# botball_v5.net
KiCad netlist of a schematic drawn in EAGLE
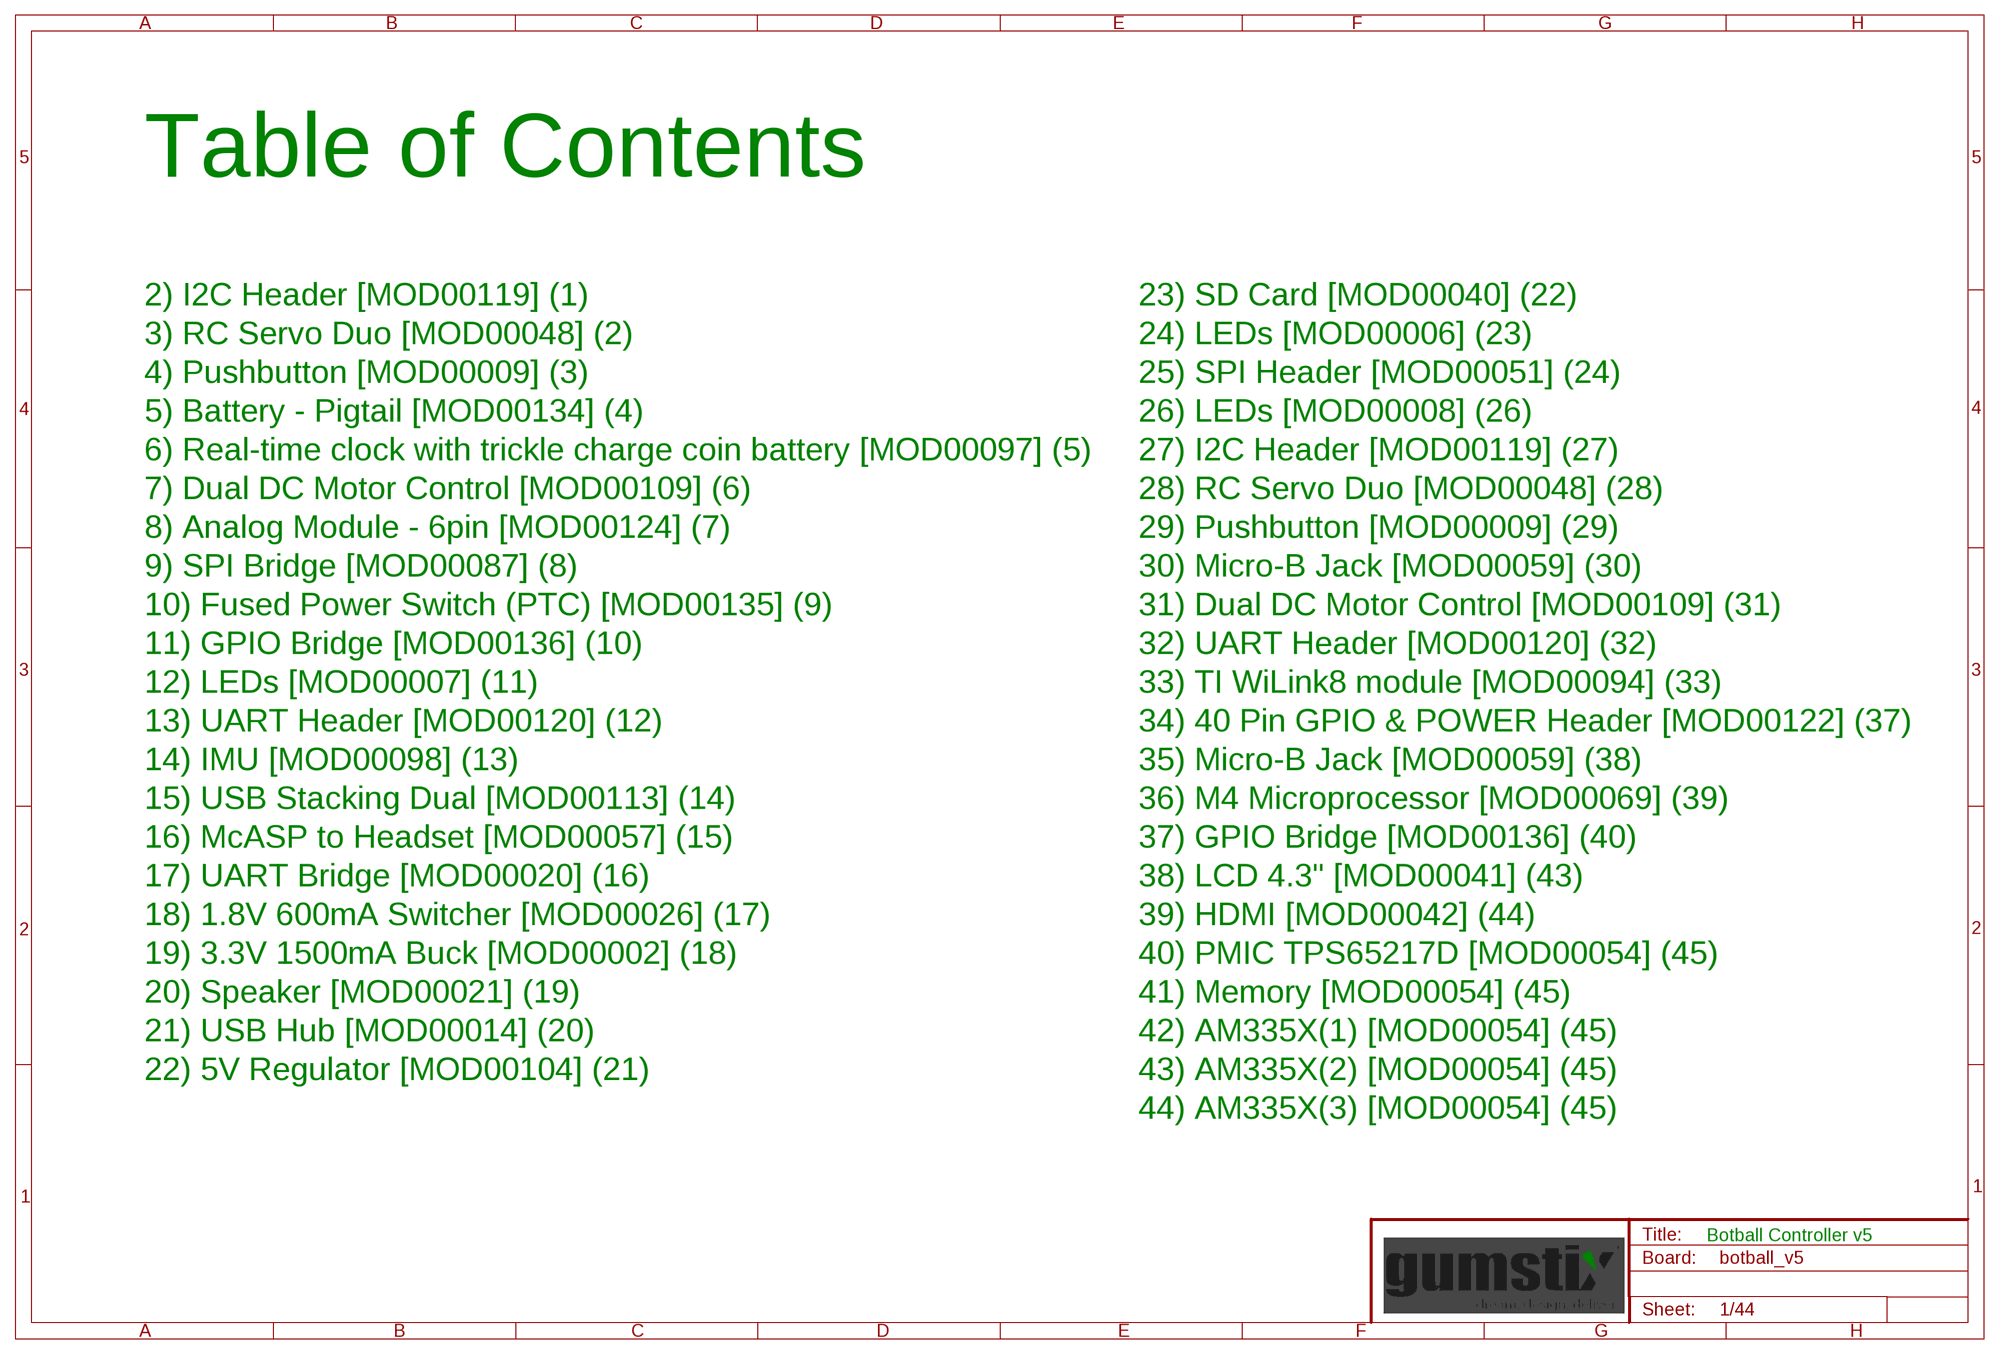
[diagram p0: schematic, sheet 1]
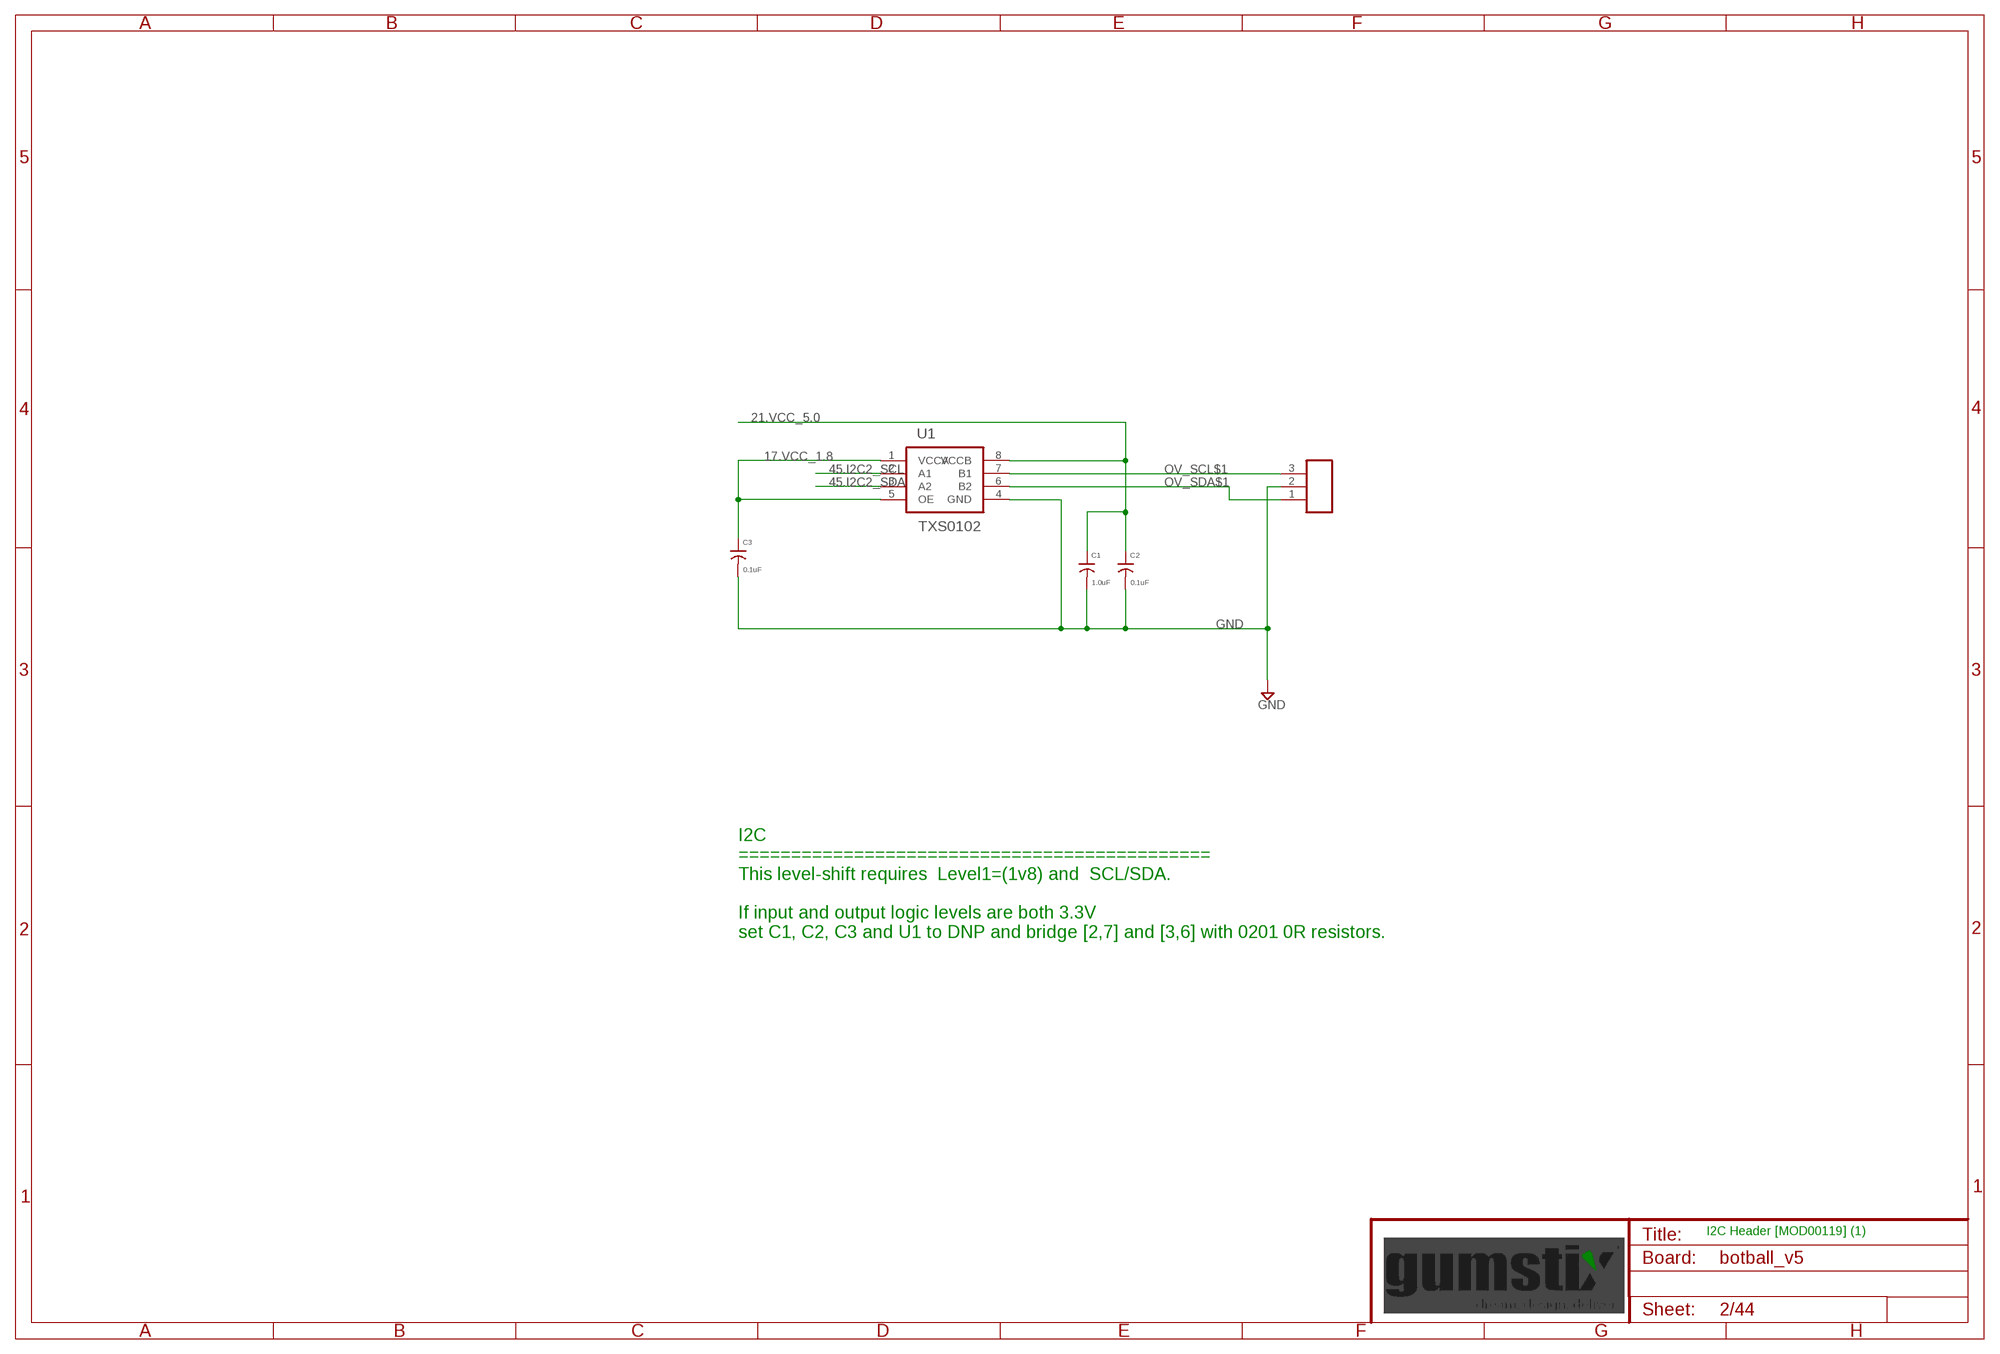
[diagram p1: schematic, sheet 2]
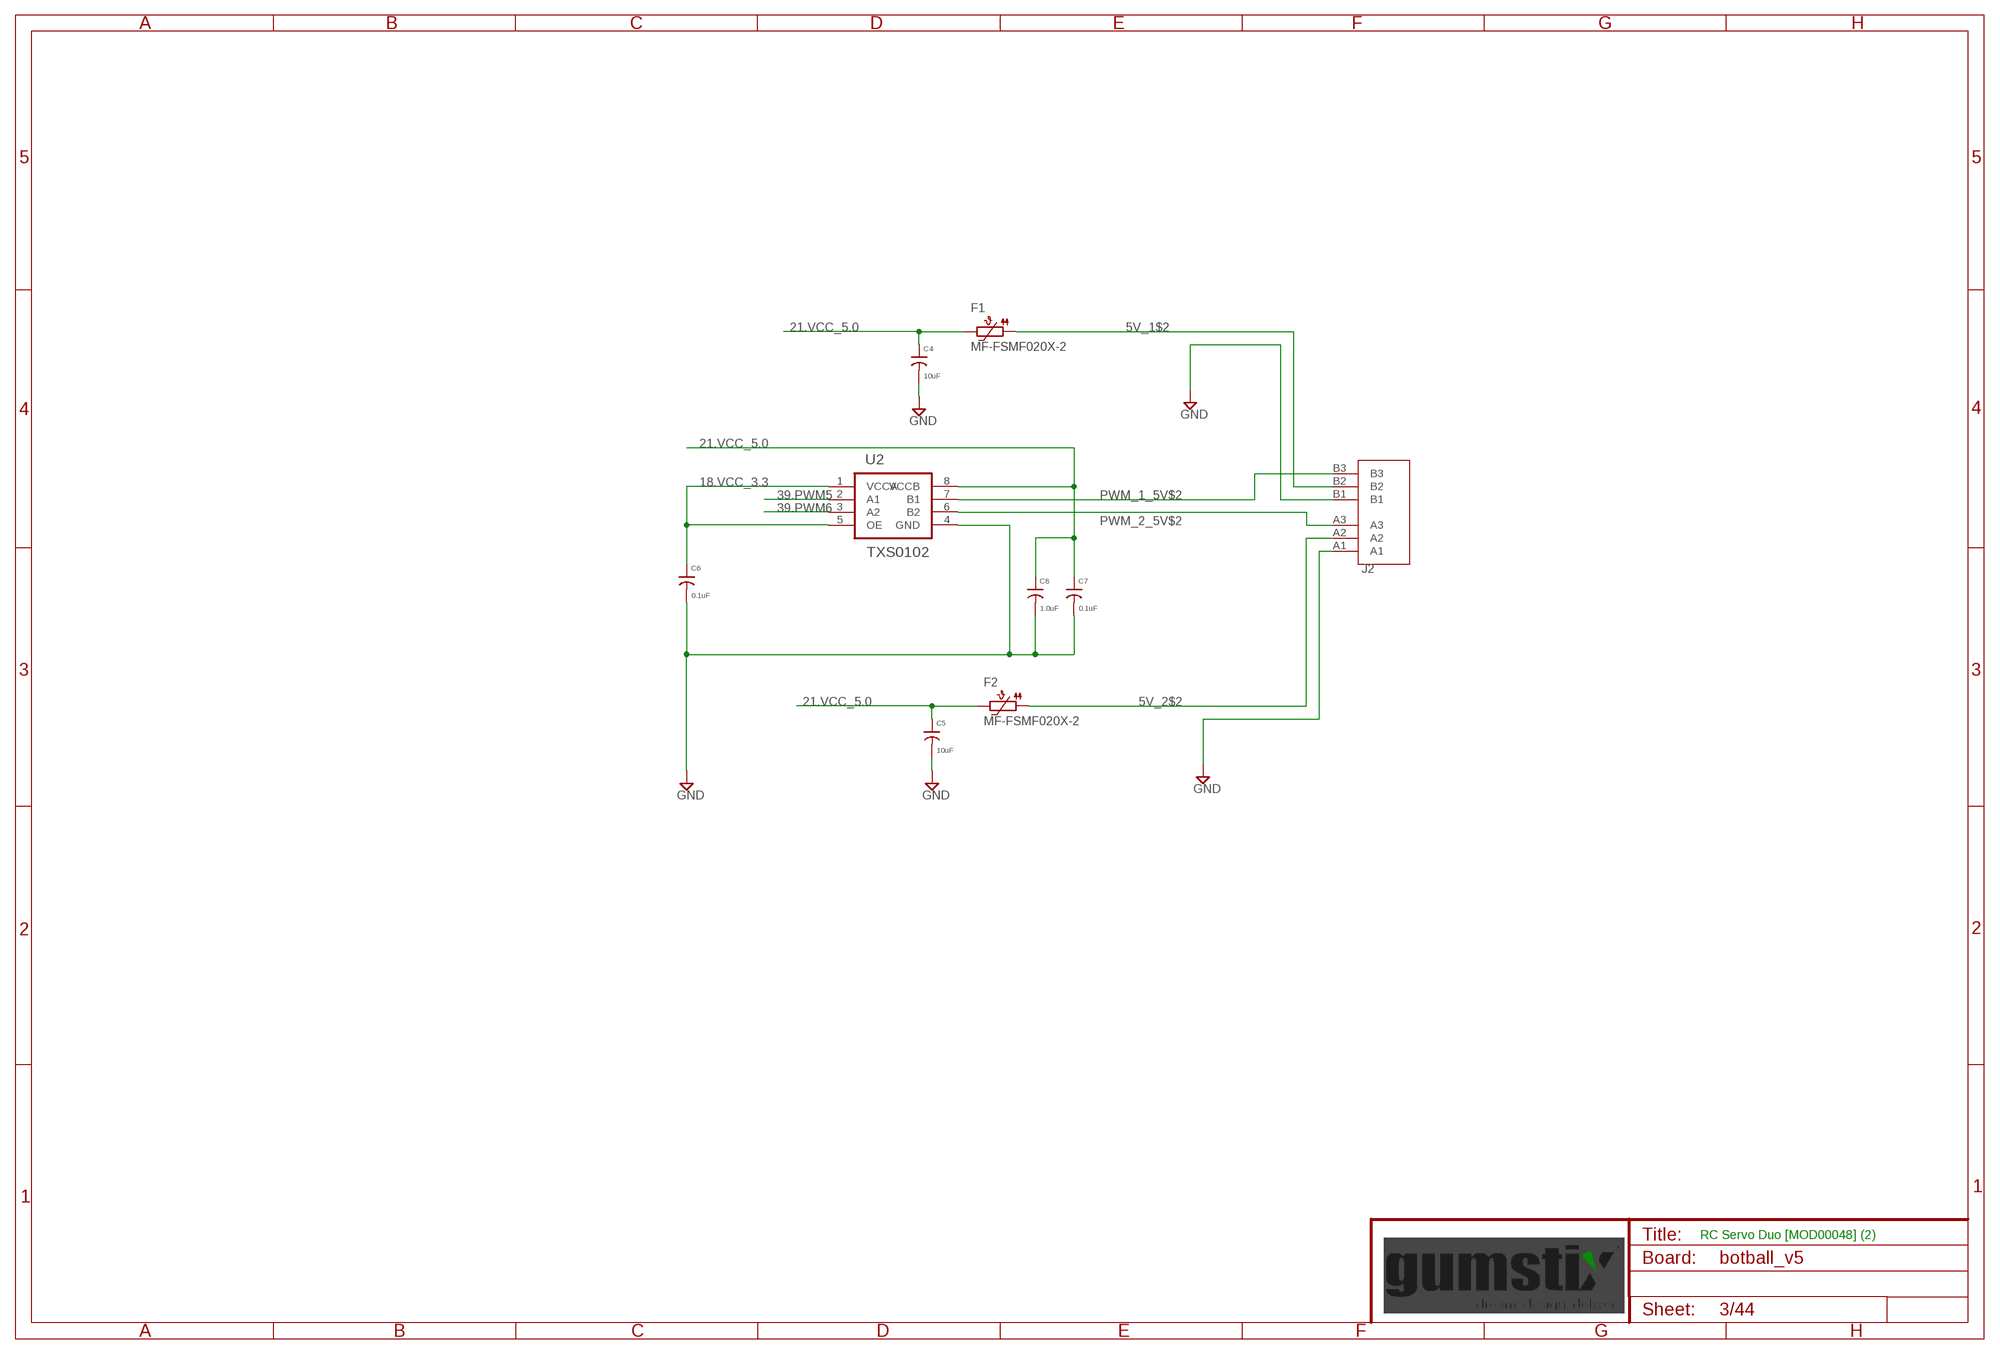
[diagram p2: schematic, sheet 3]
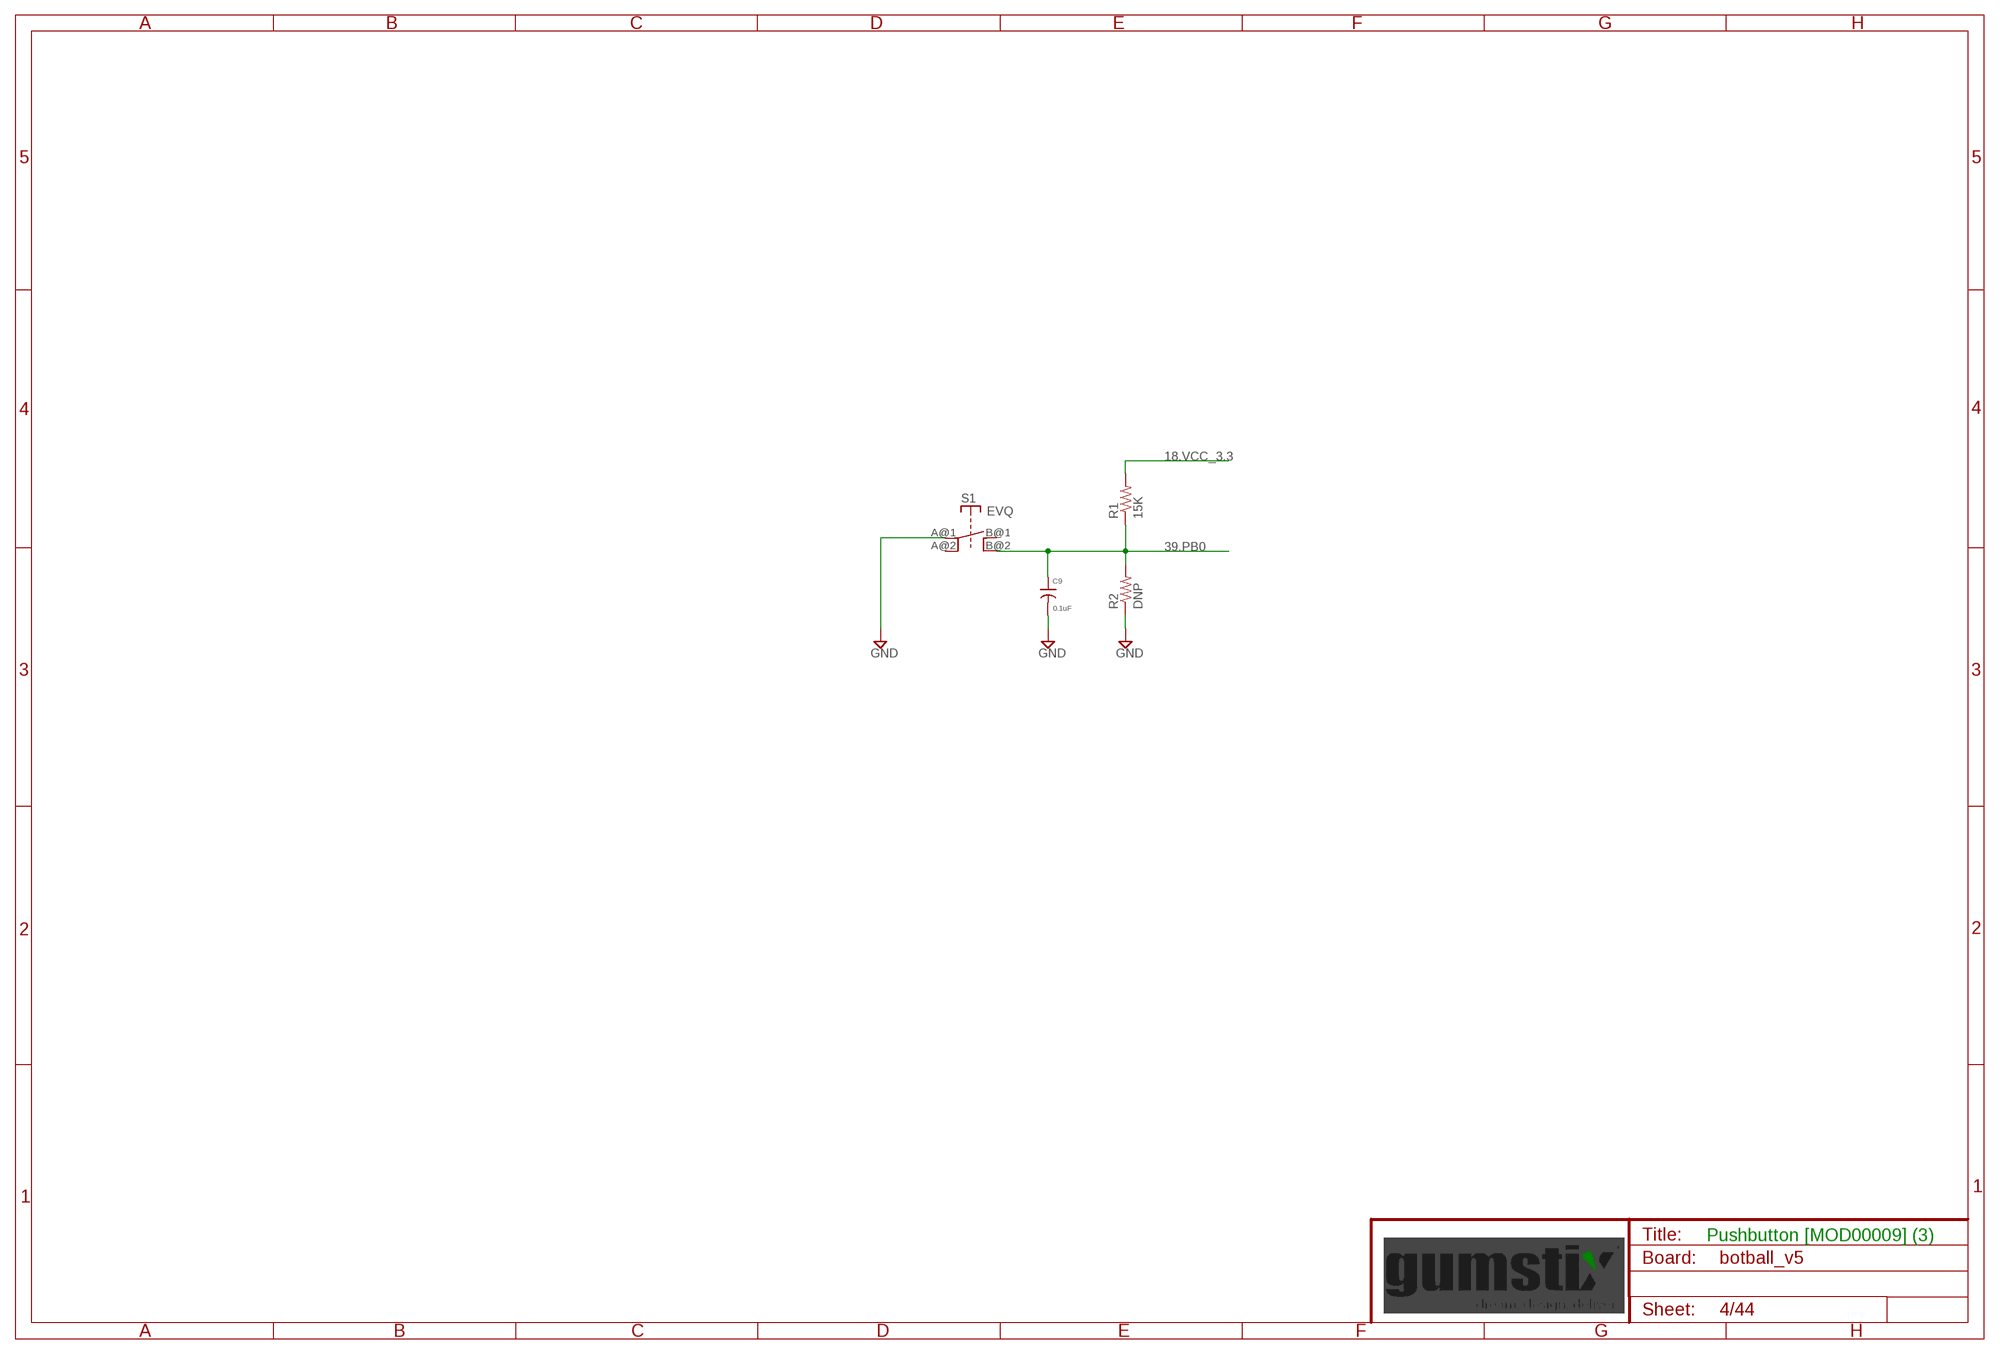
[diagram p3: schematic, sheet 4]
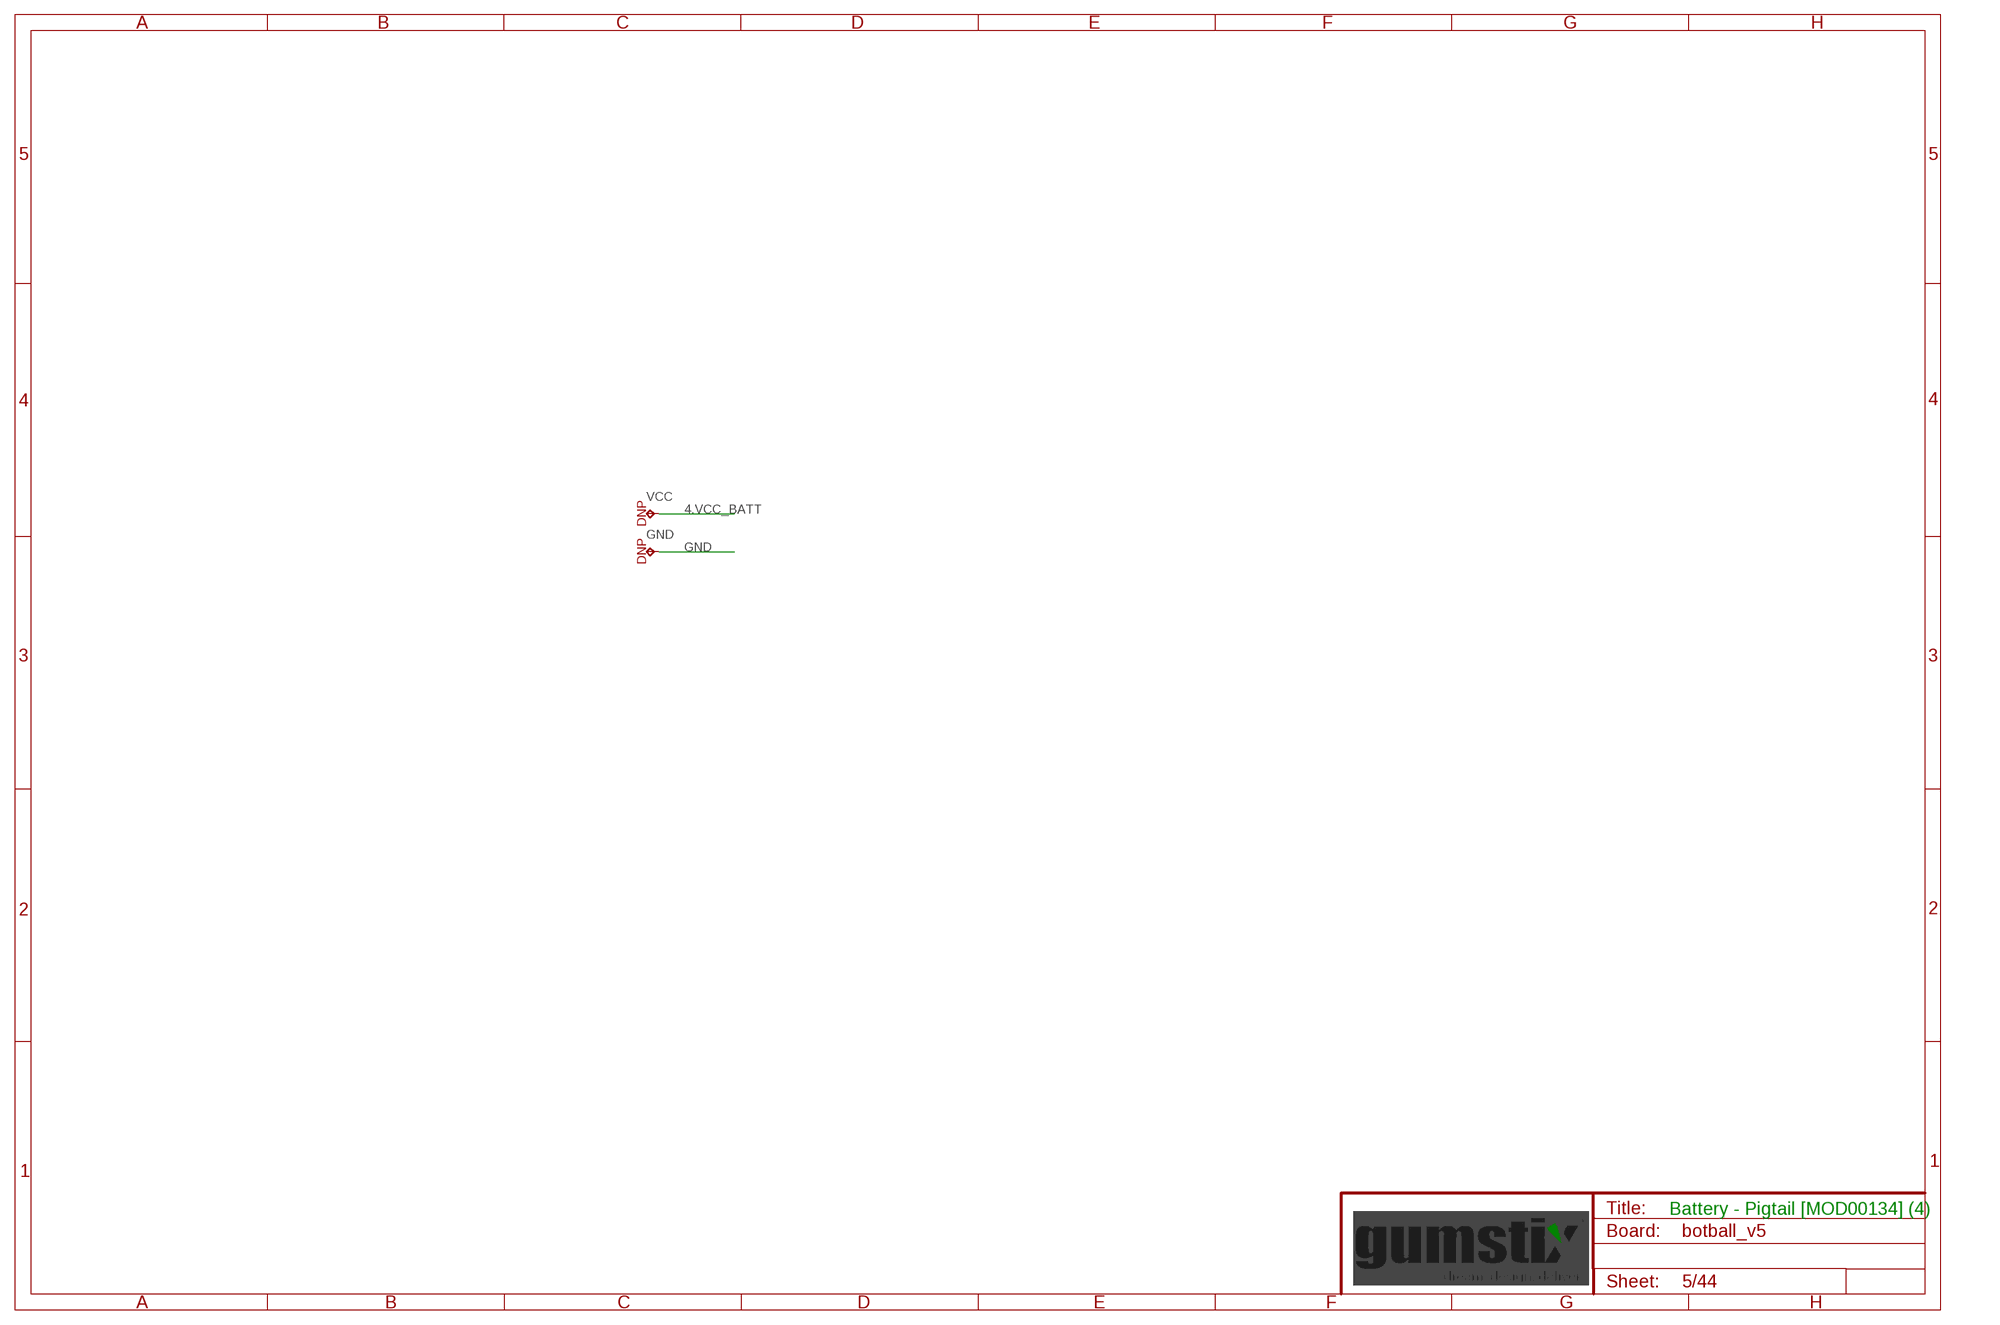
[diagram p4: schematic, sheet 5]
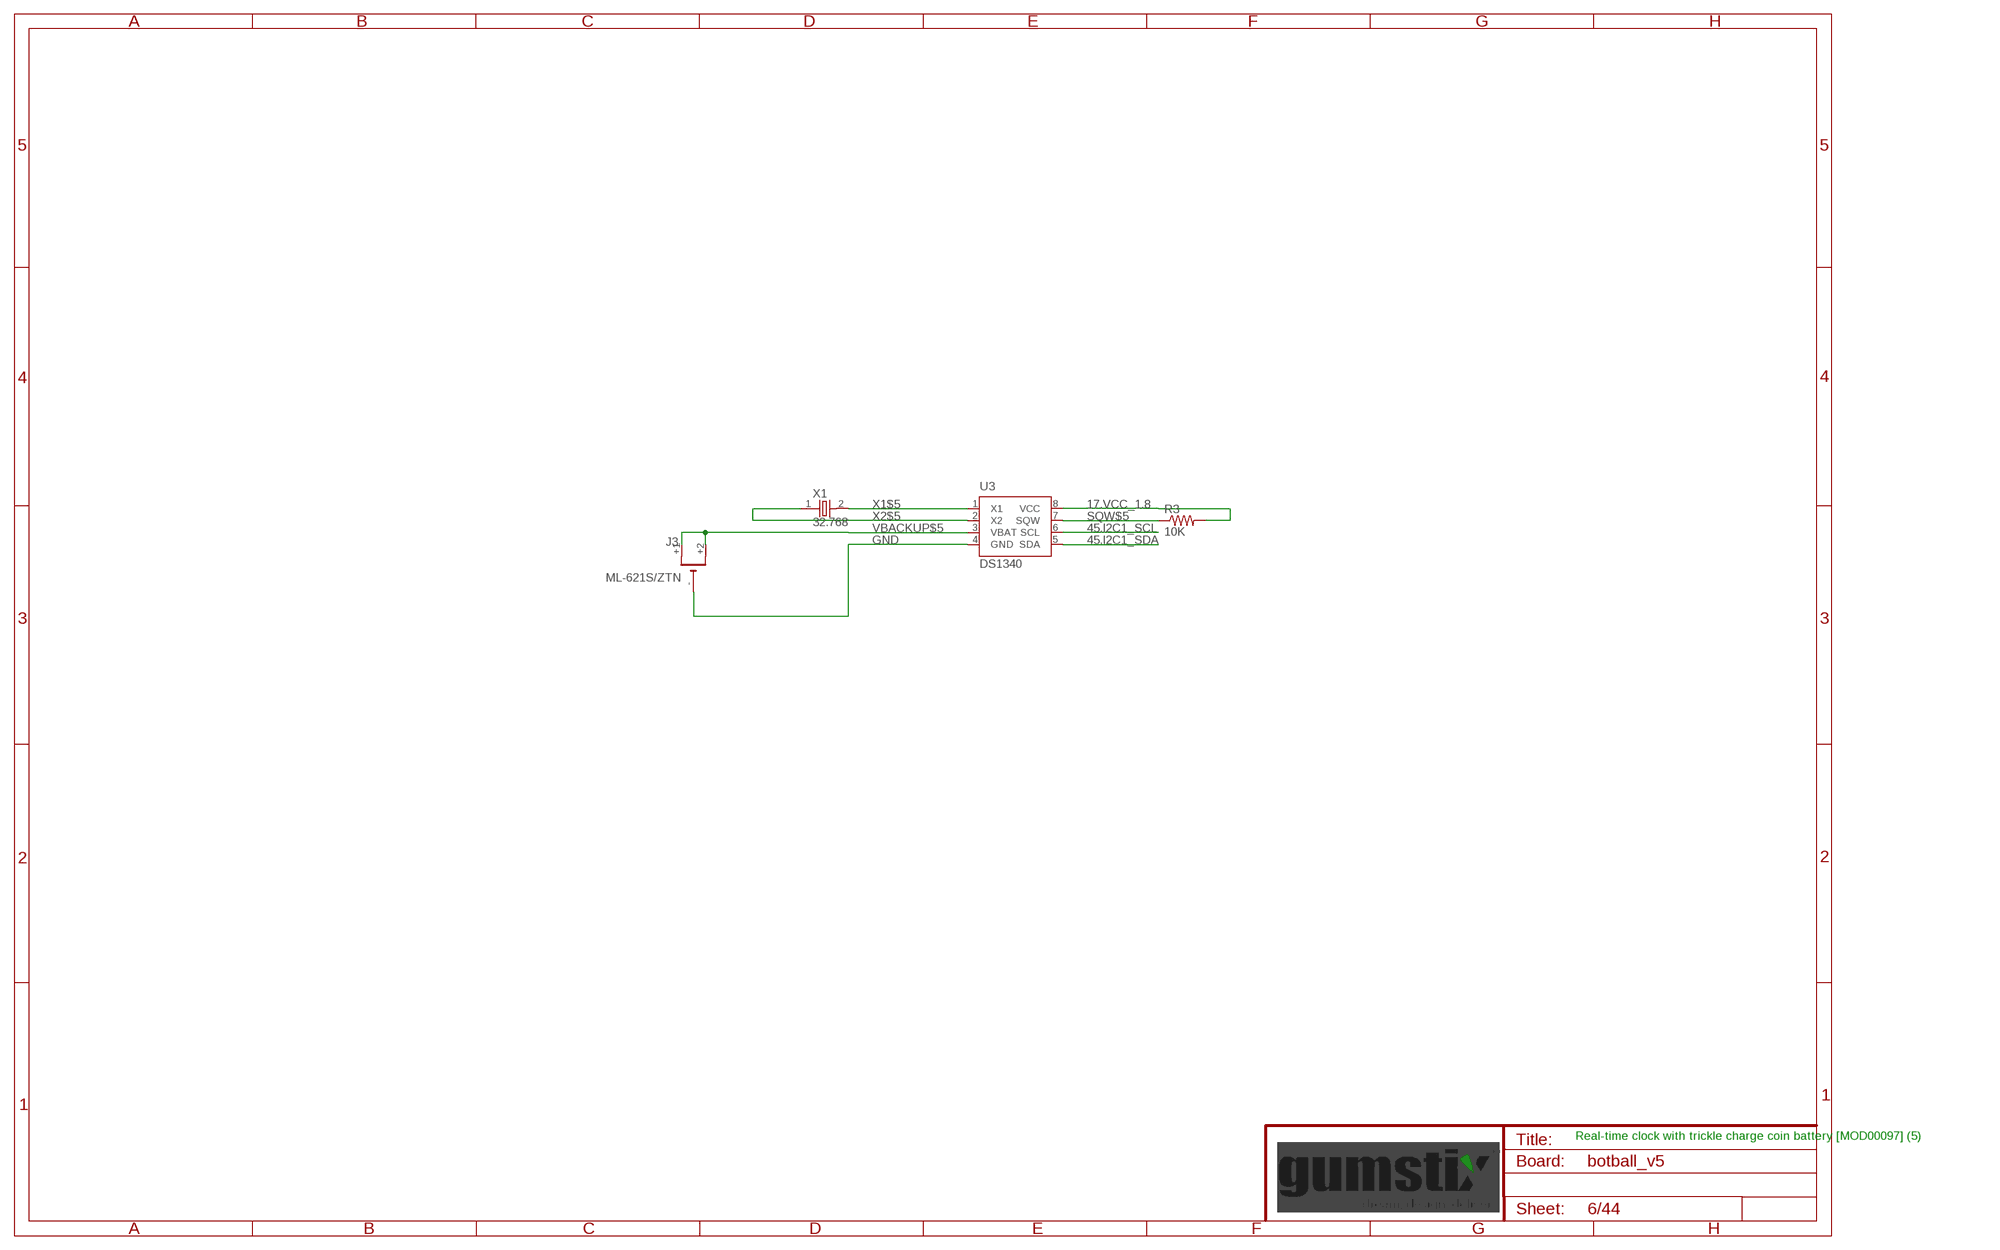
[diagram p5: schematic, sheet 6]
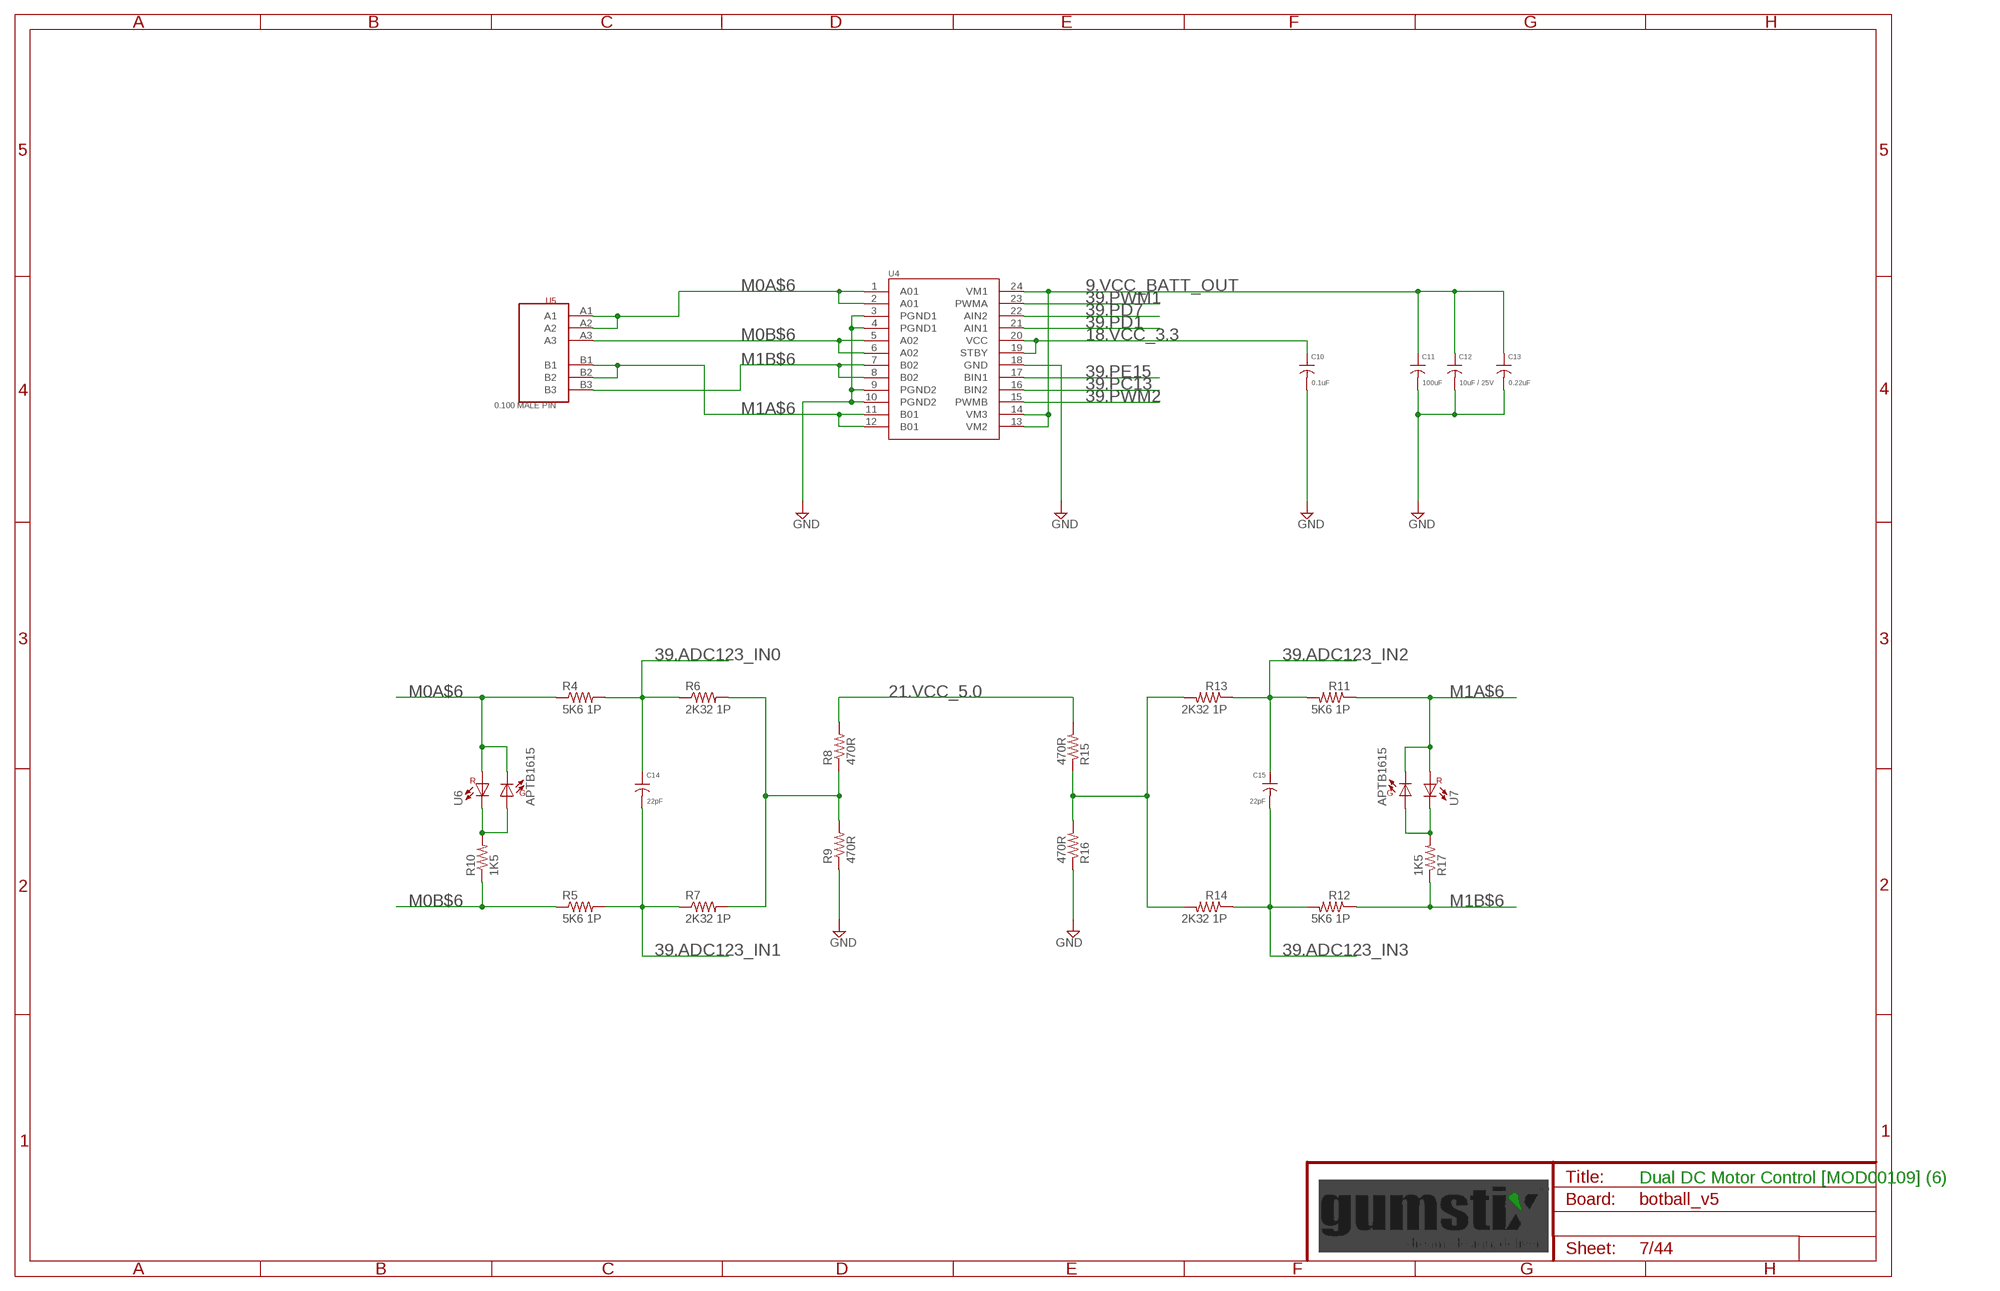
[diagram p6: schematic, sheet 7]
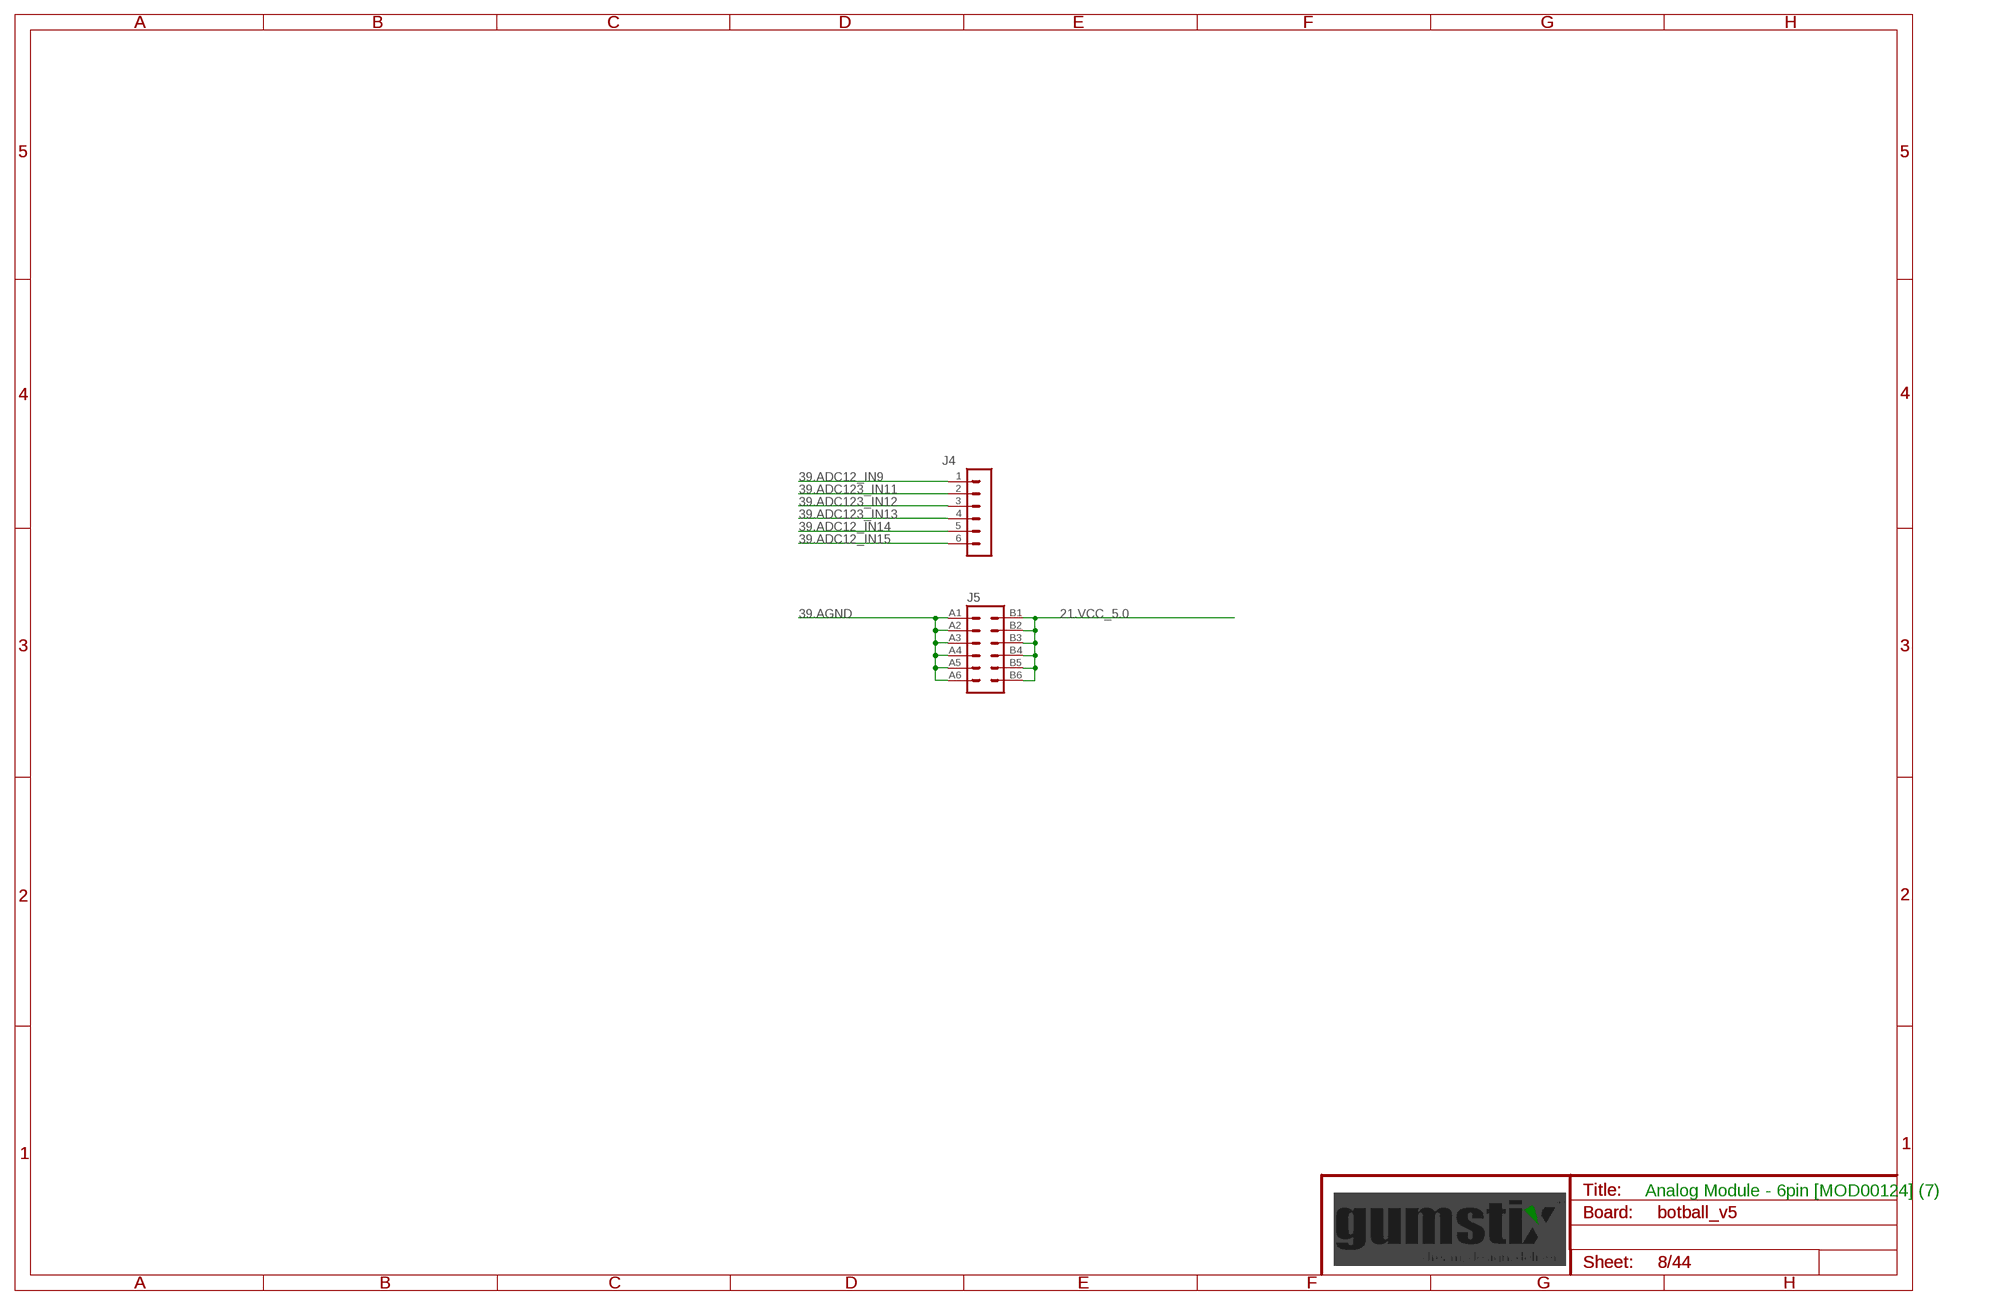
[diagram p7: schematic, sheet 8]
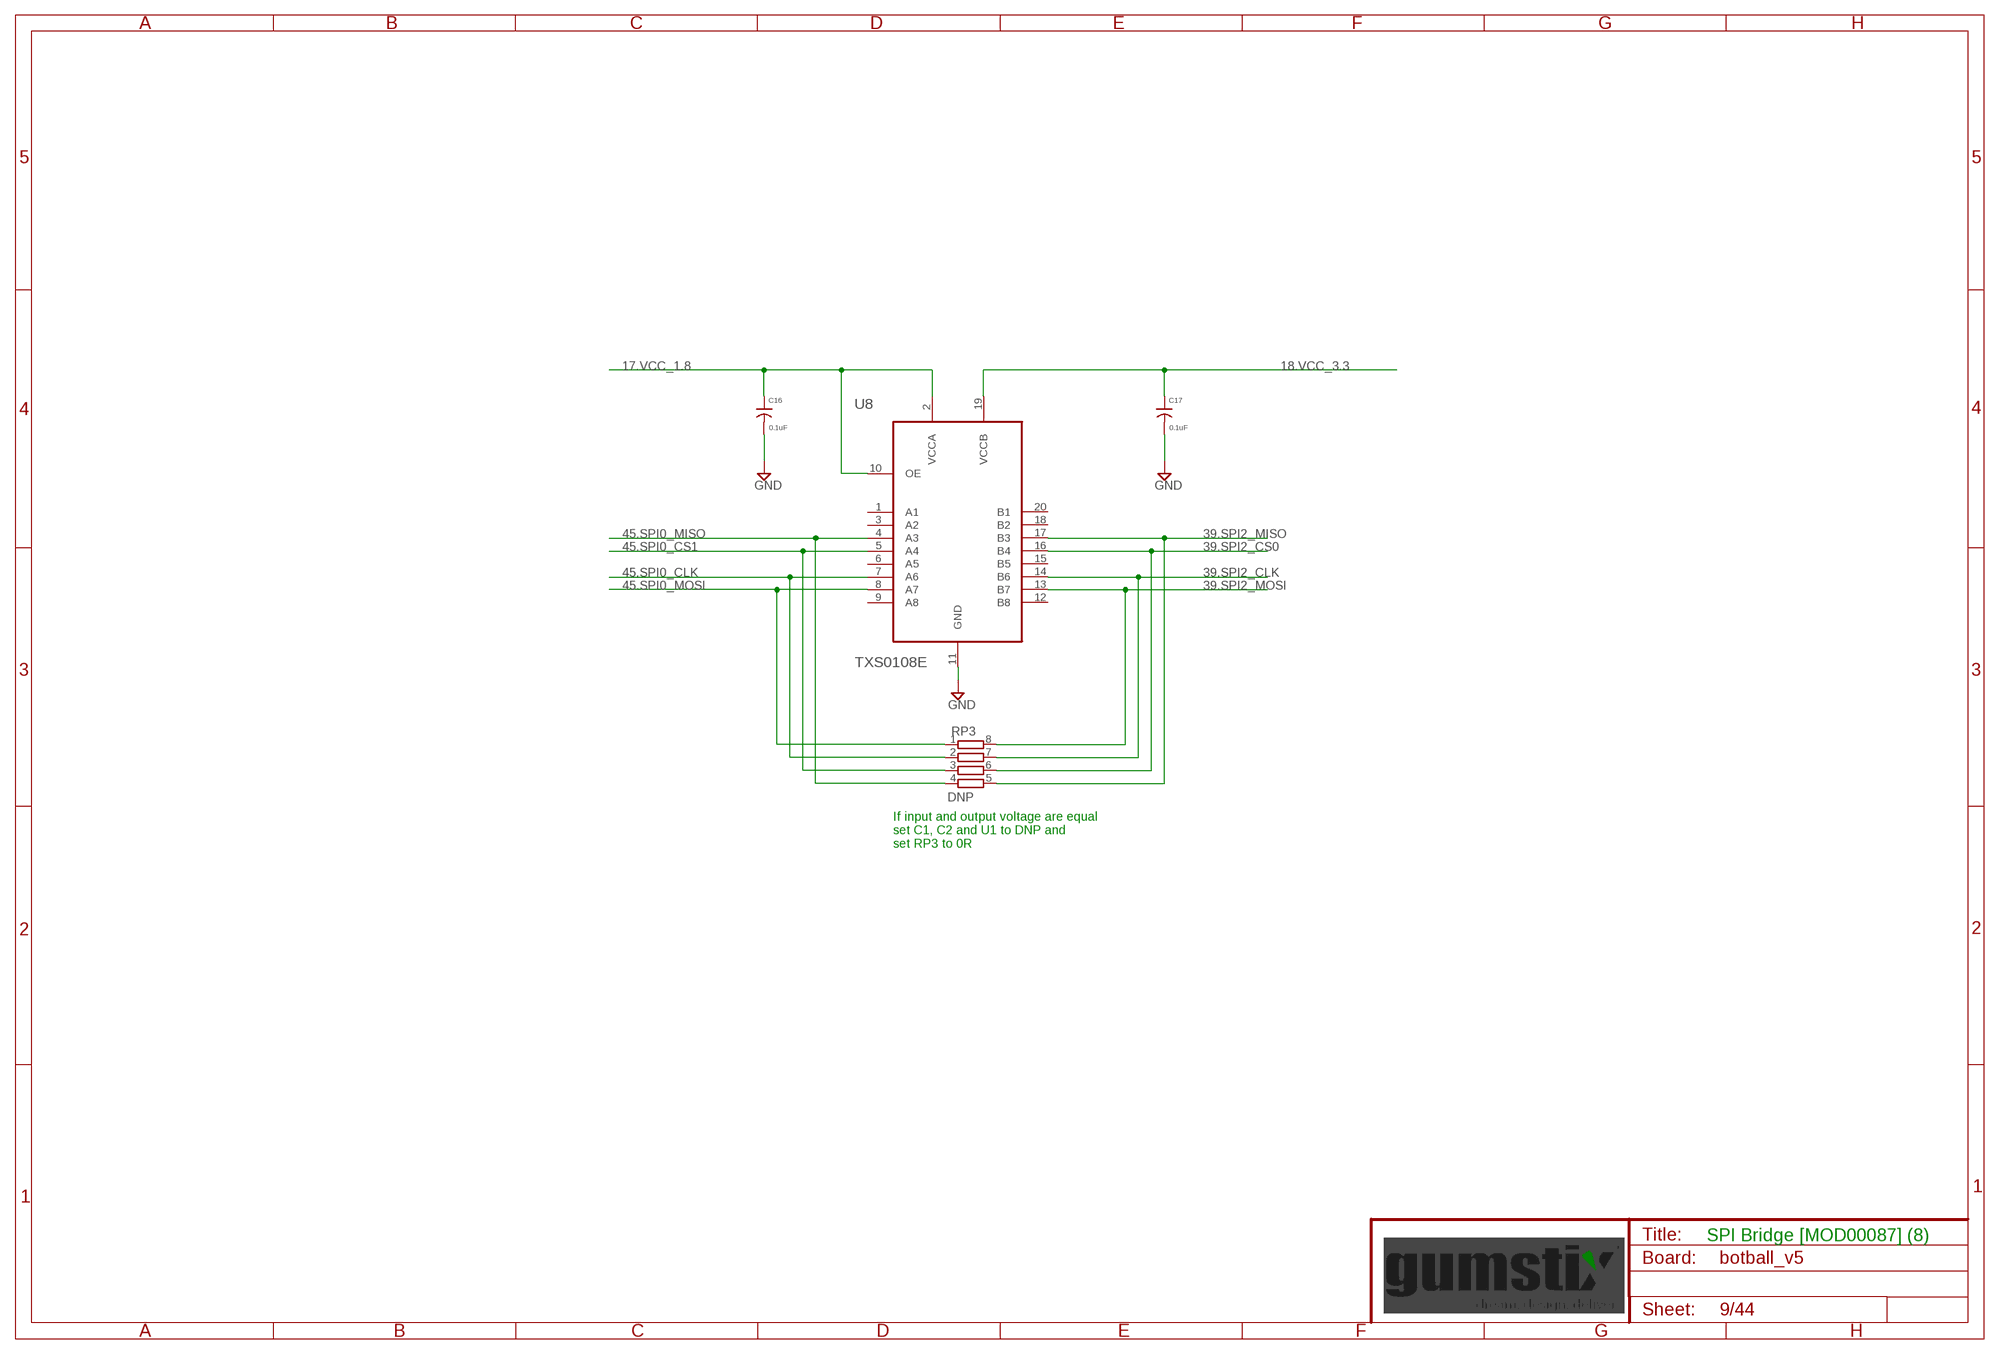
[diagram p8: schematic, sheet 9]
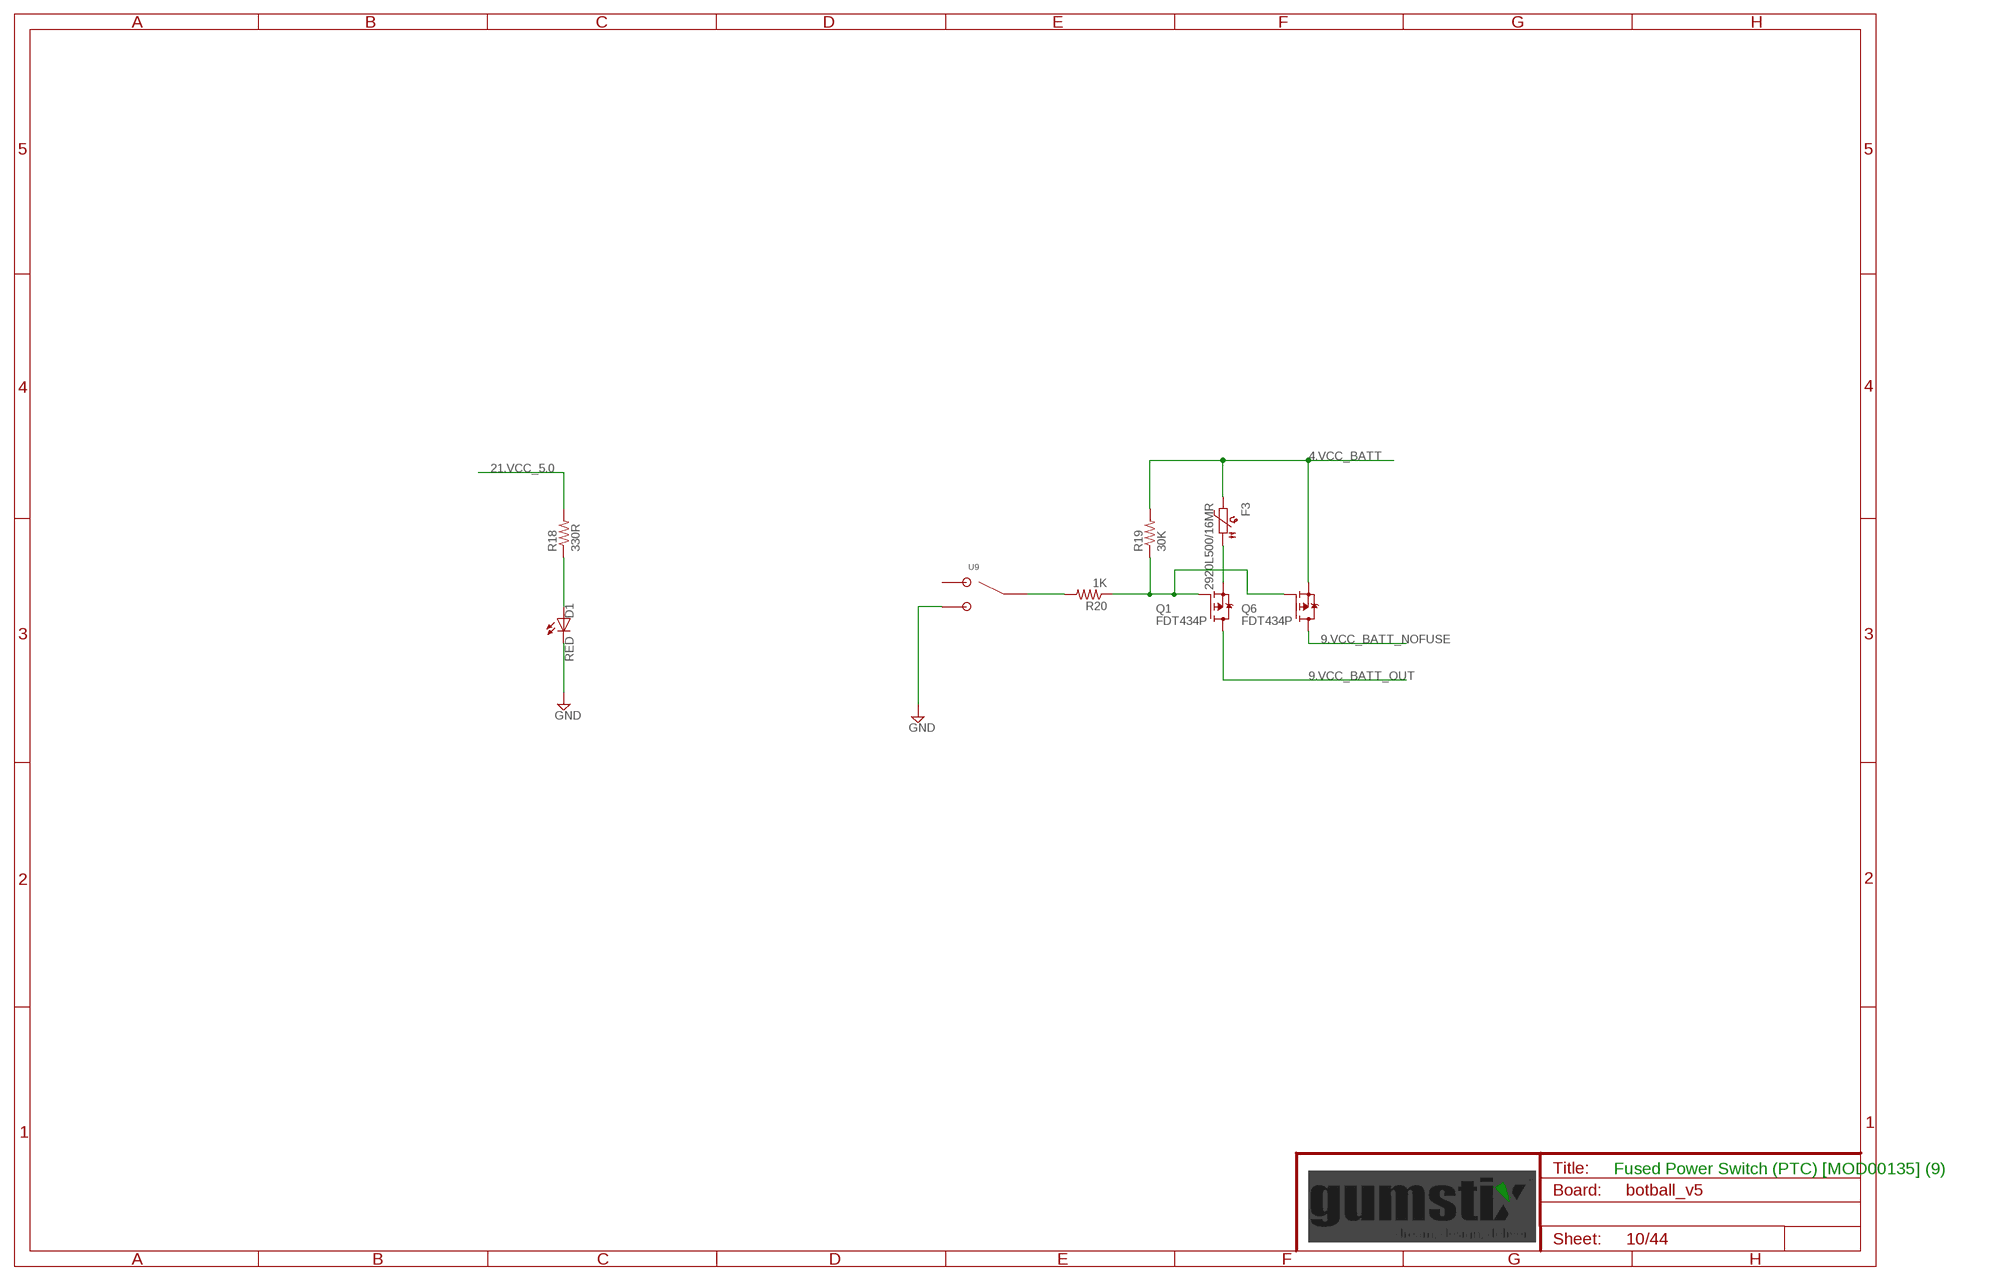
[diagram p9: schematic, sheet 10]
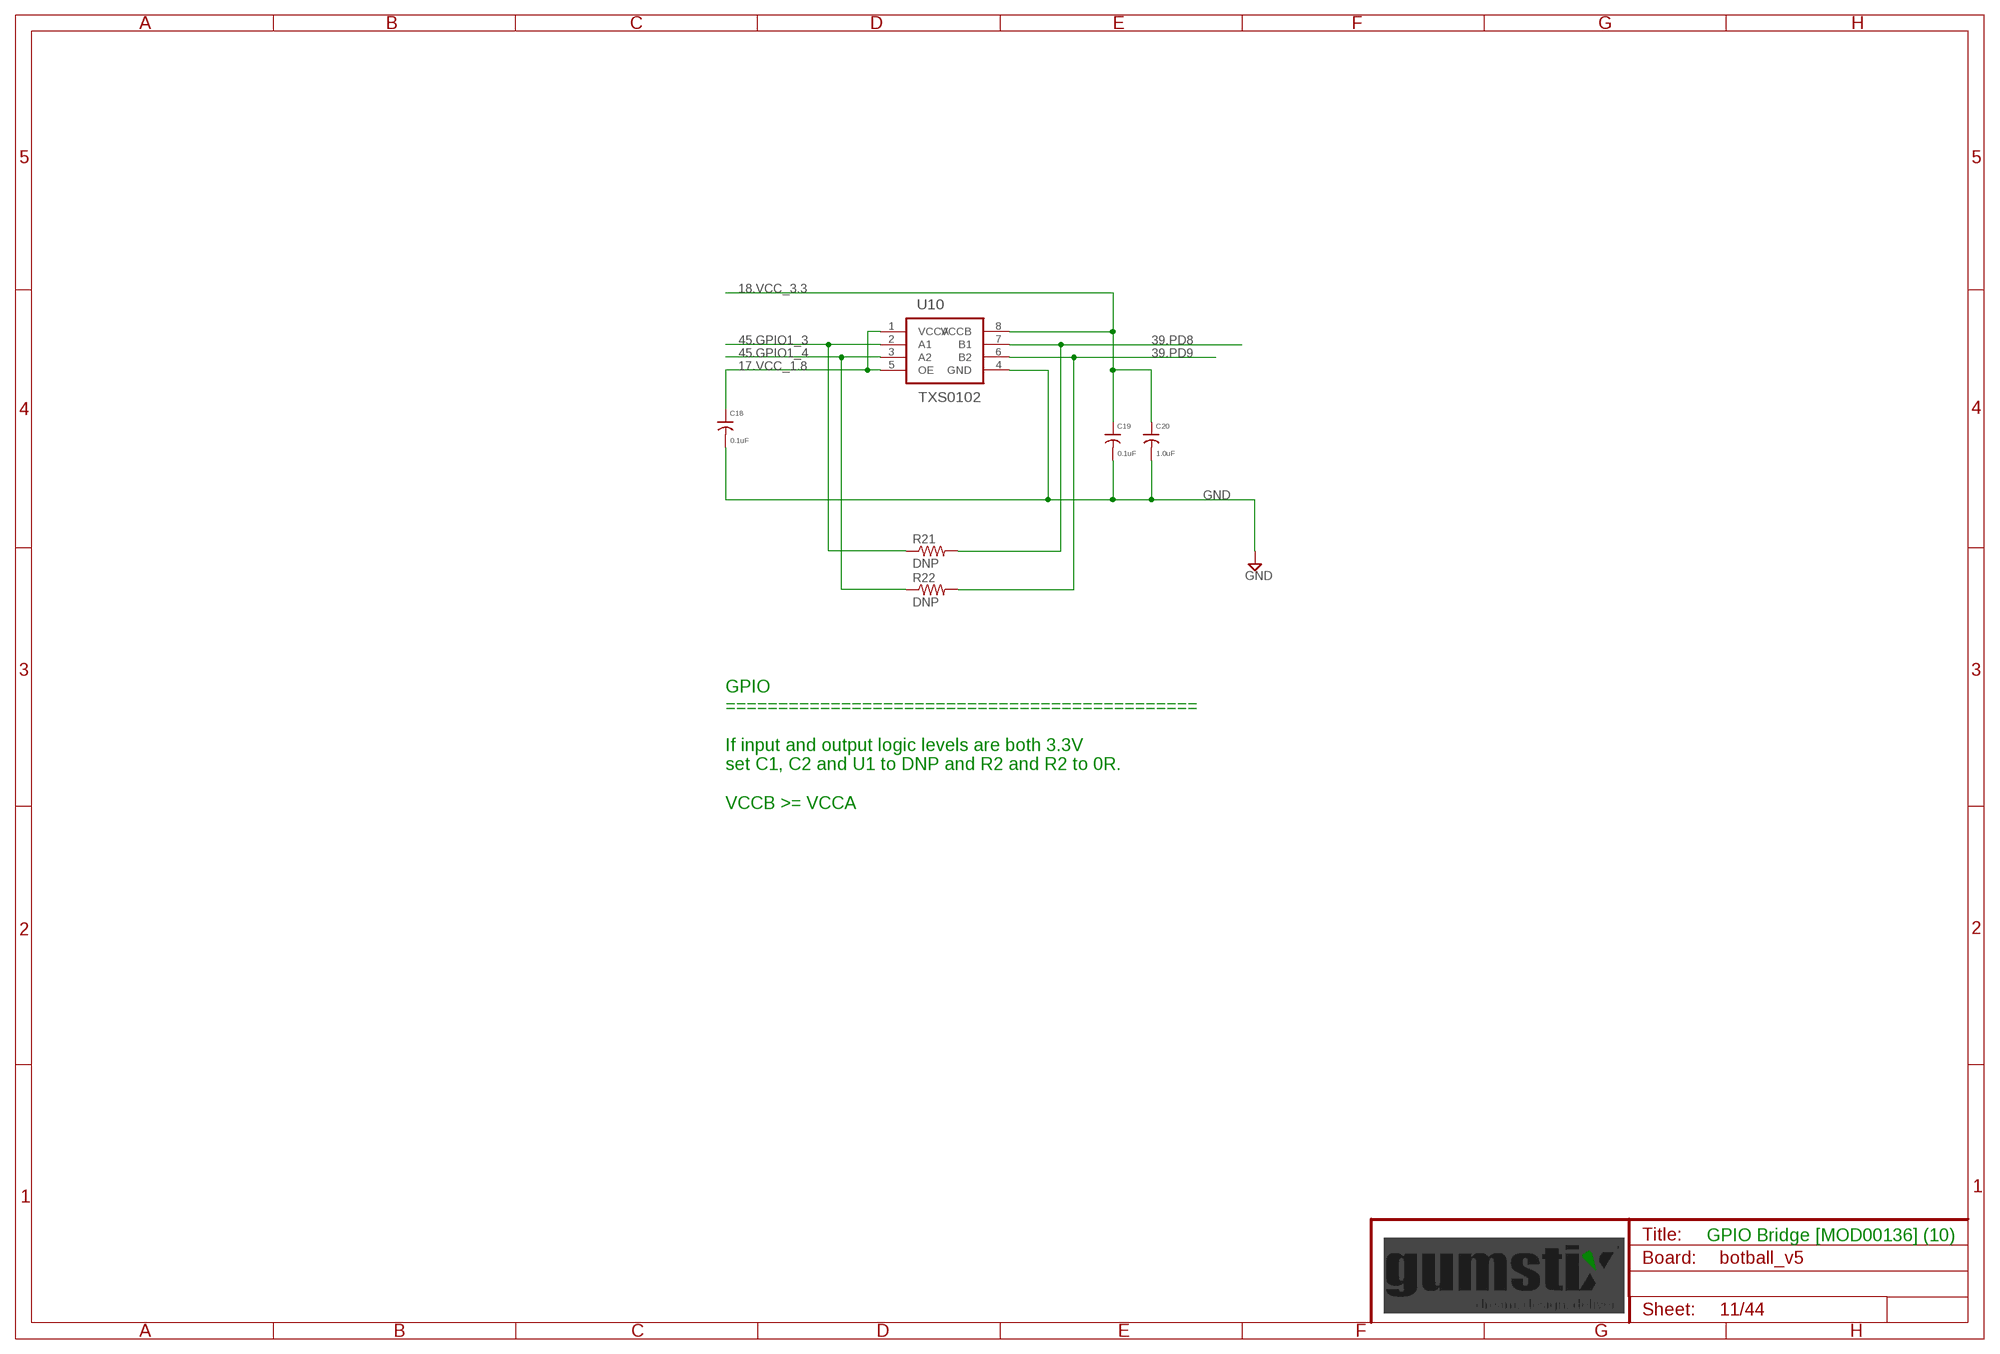
[diagram p10: schematic, sheet 11]
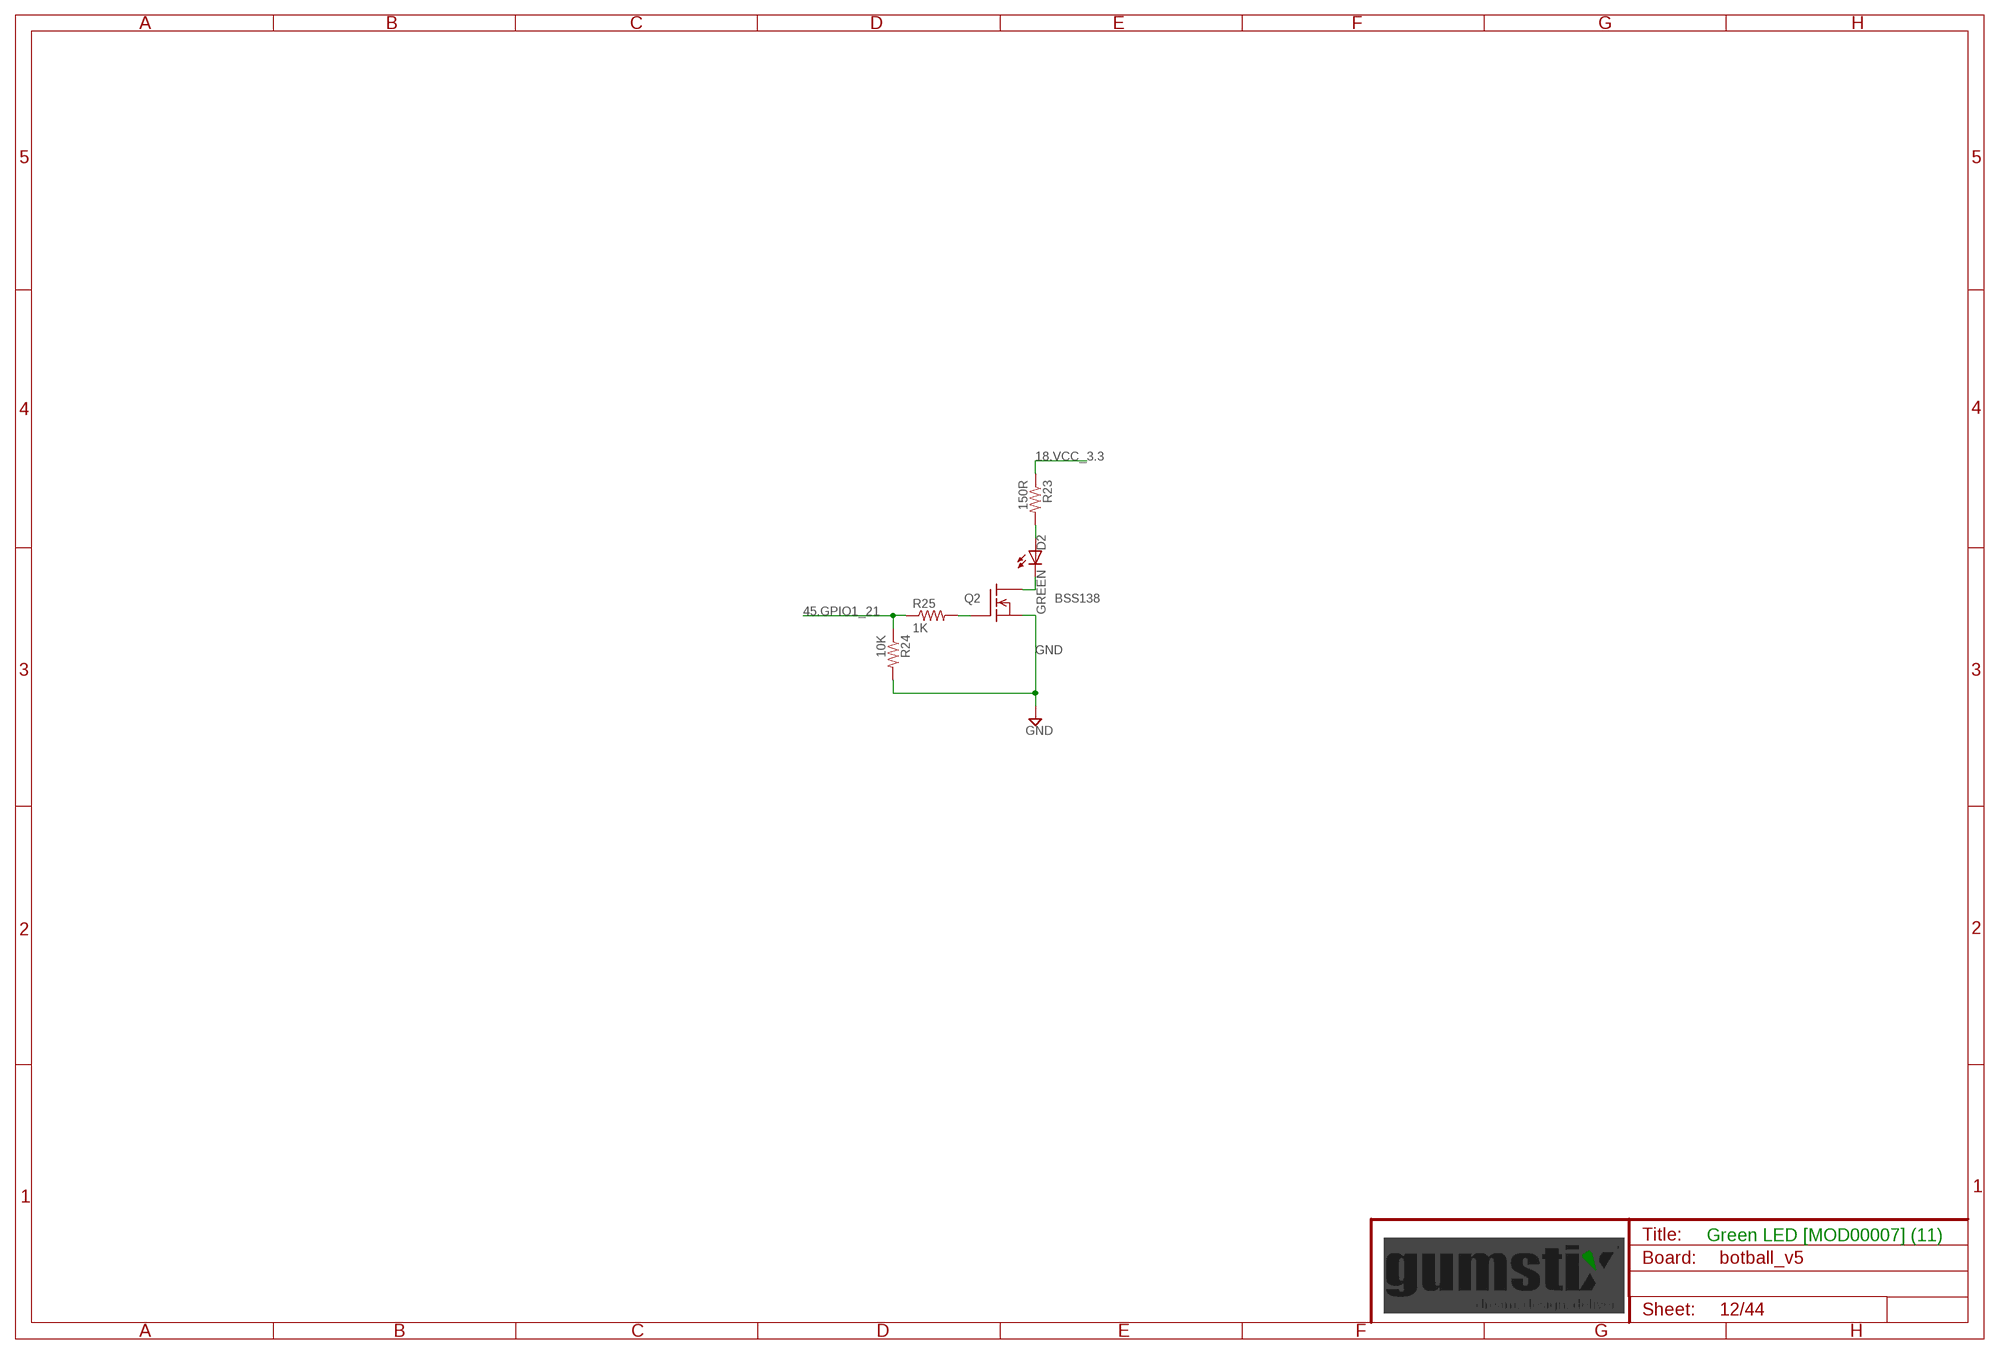
[diagram p11: schematic, sheet 12]
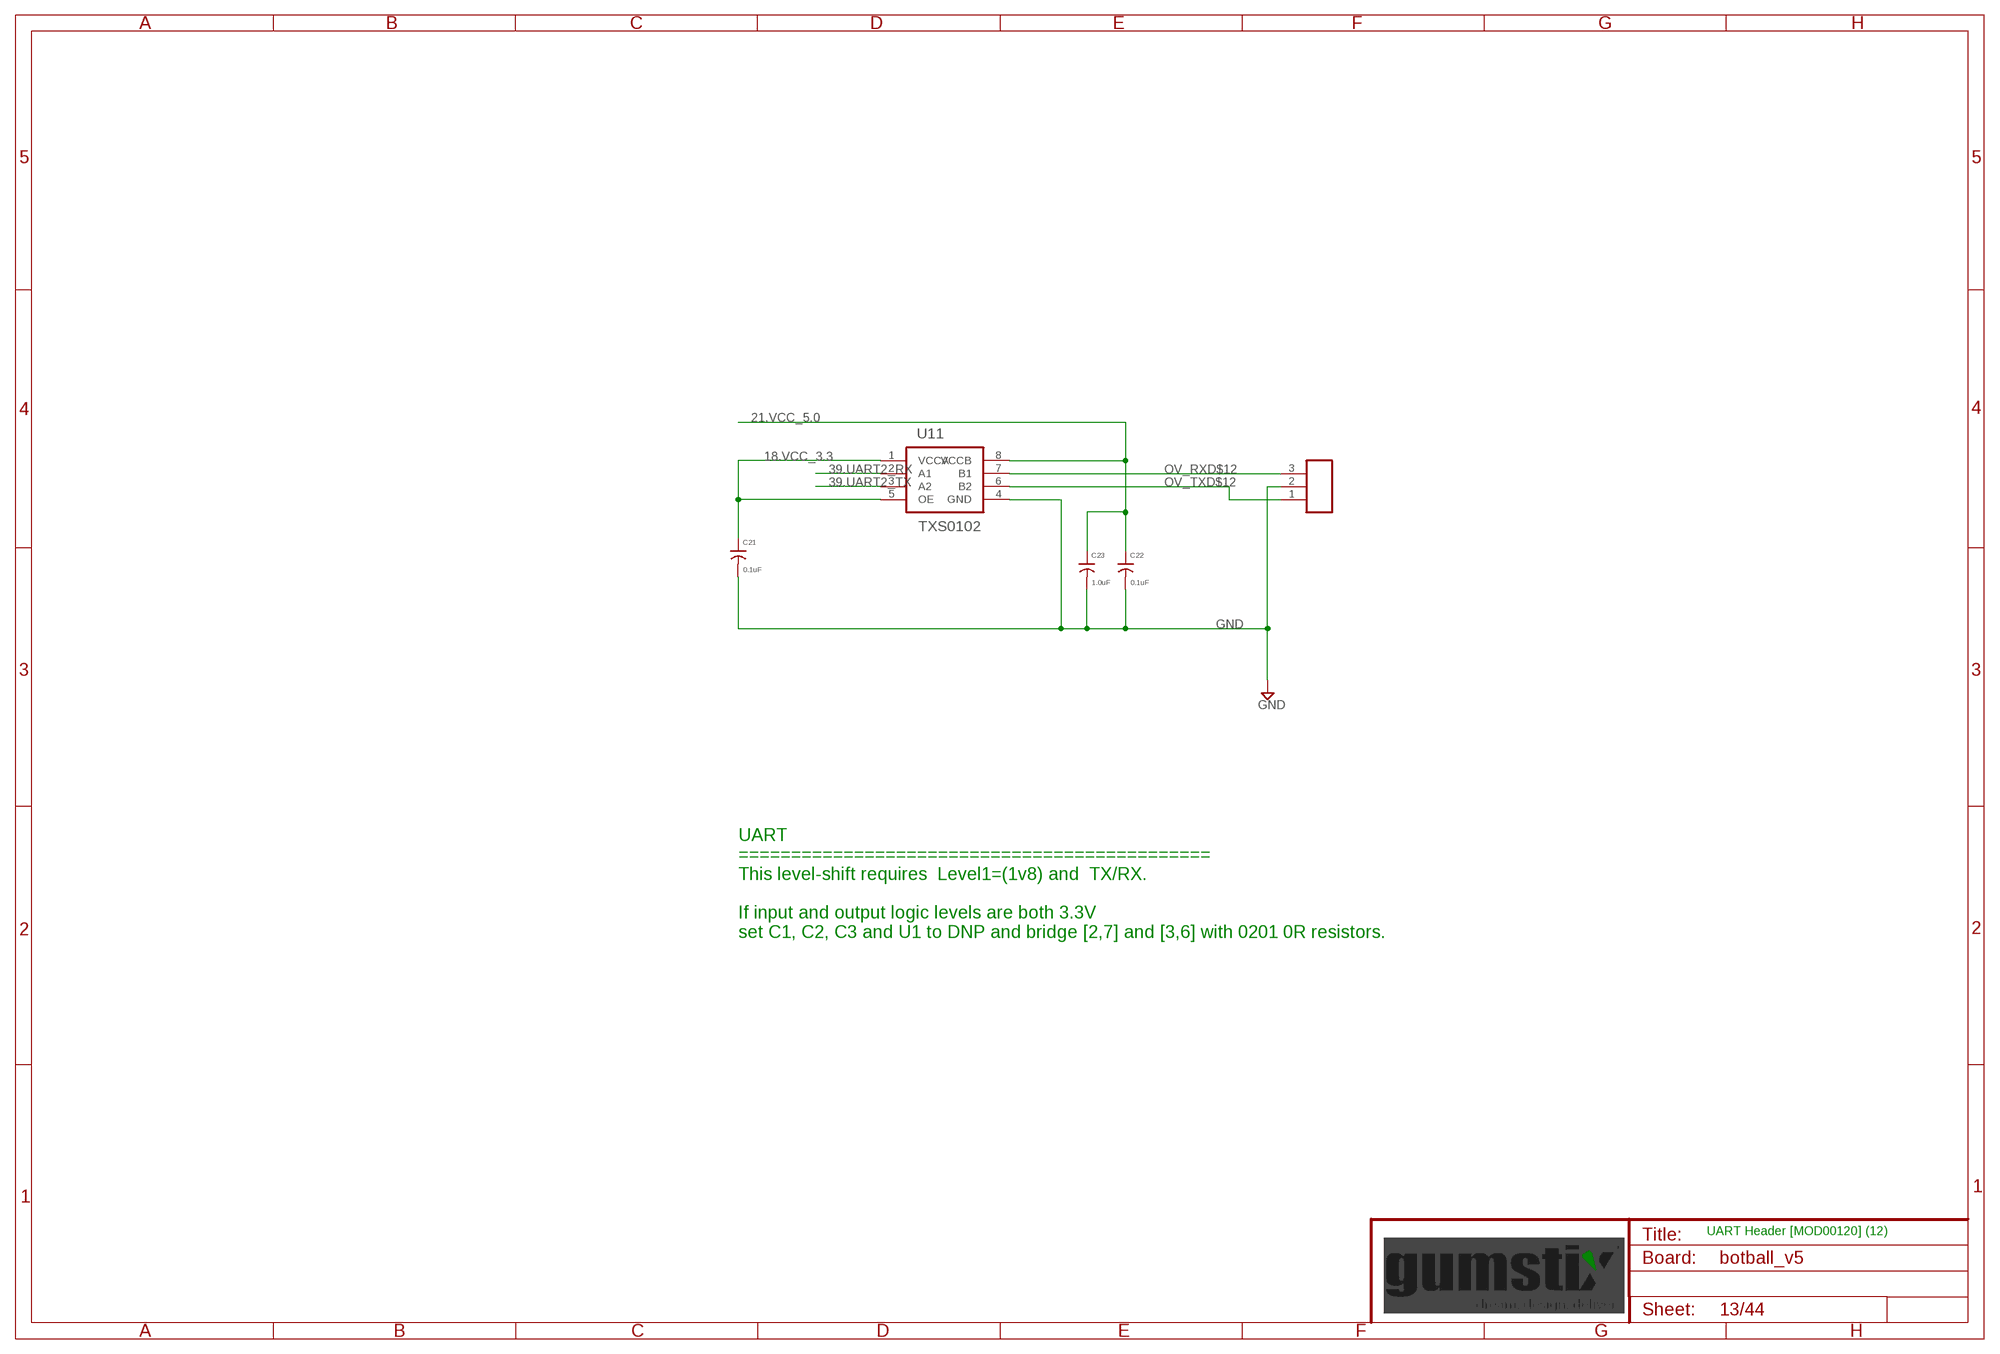
[diagram p12: schematic, sheet 13]
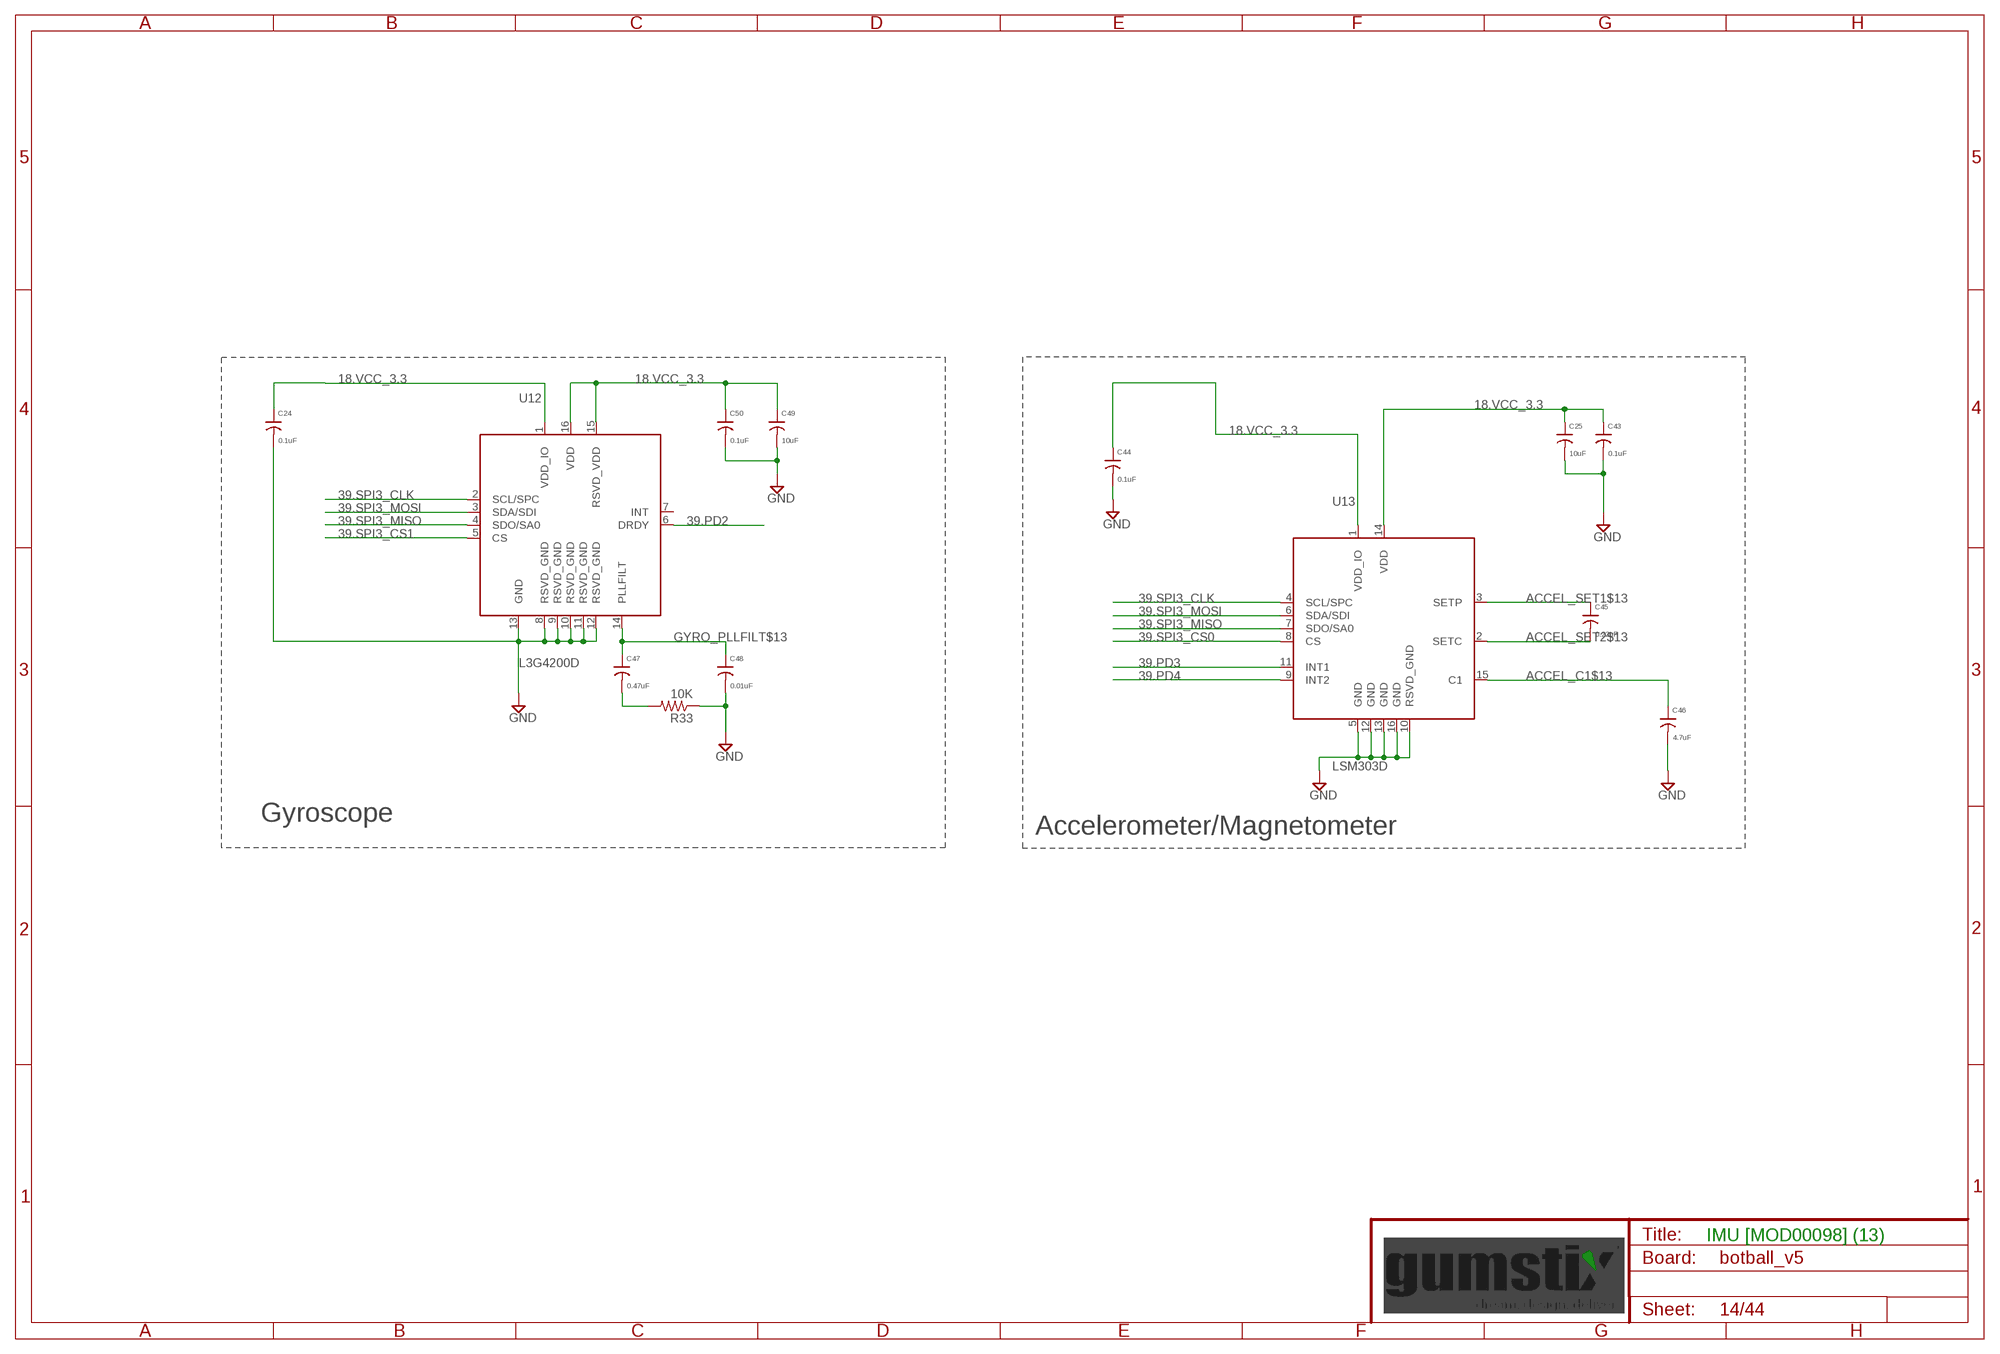
[diagram p13: schematic, sheet 14]
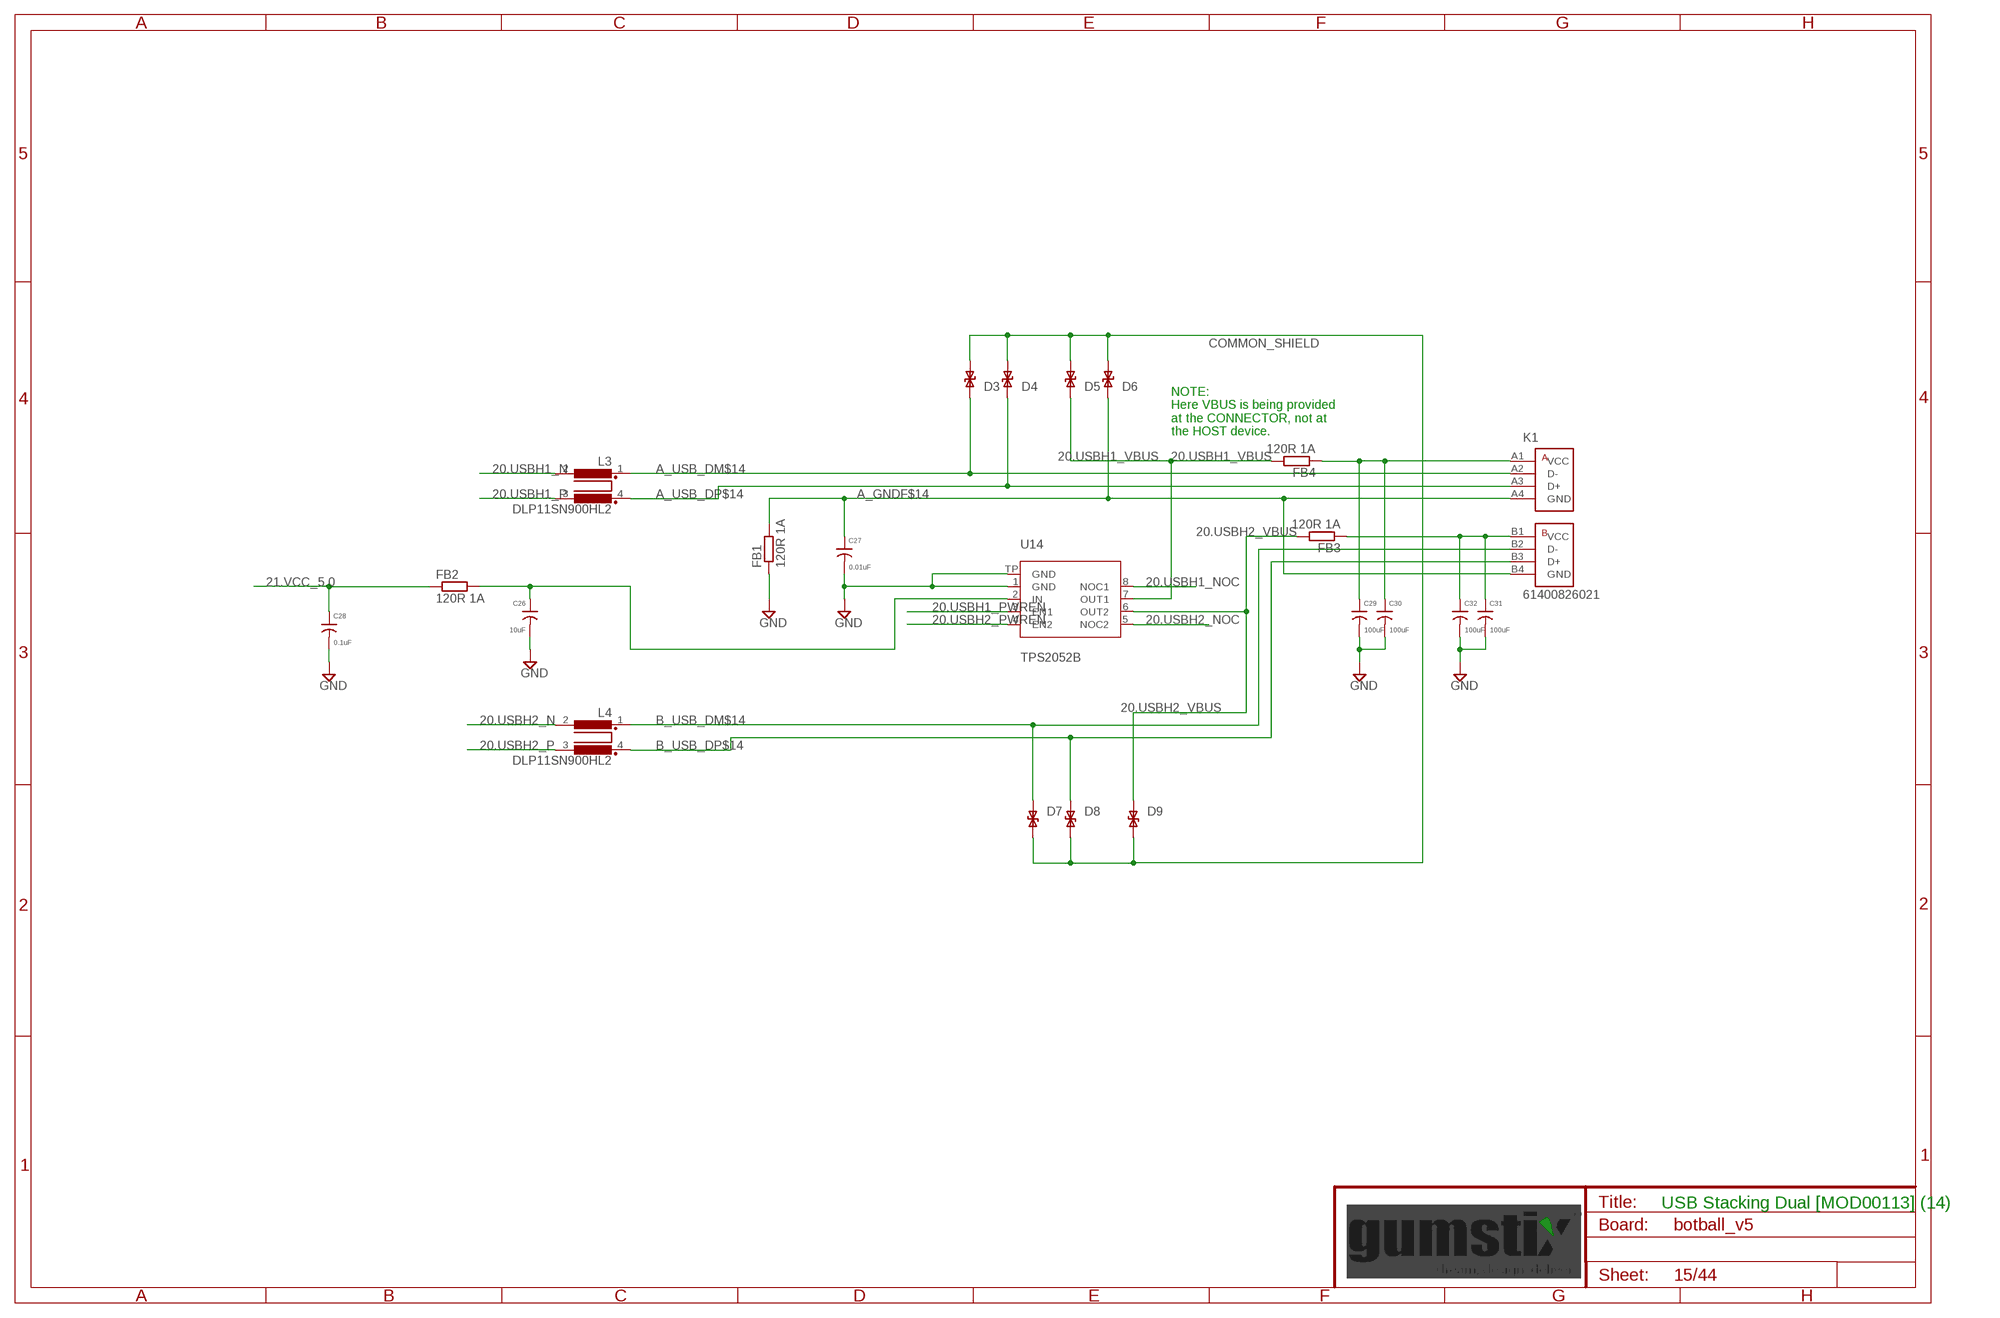
[diagram p14: schematic, sheet 15]
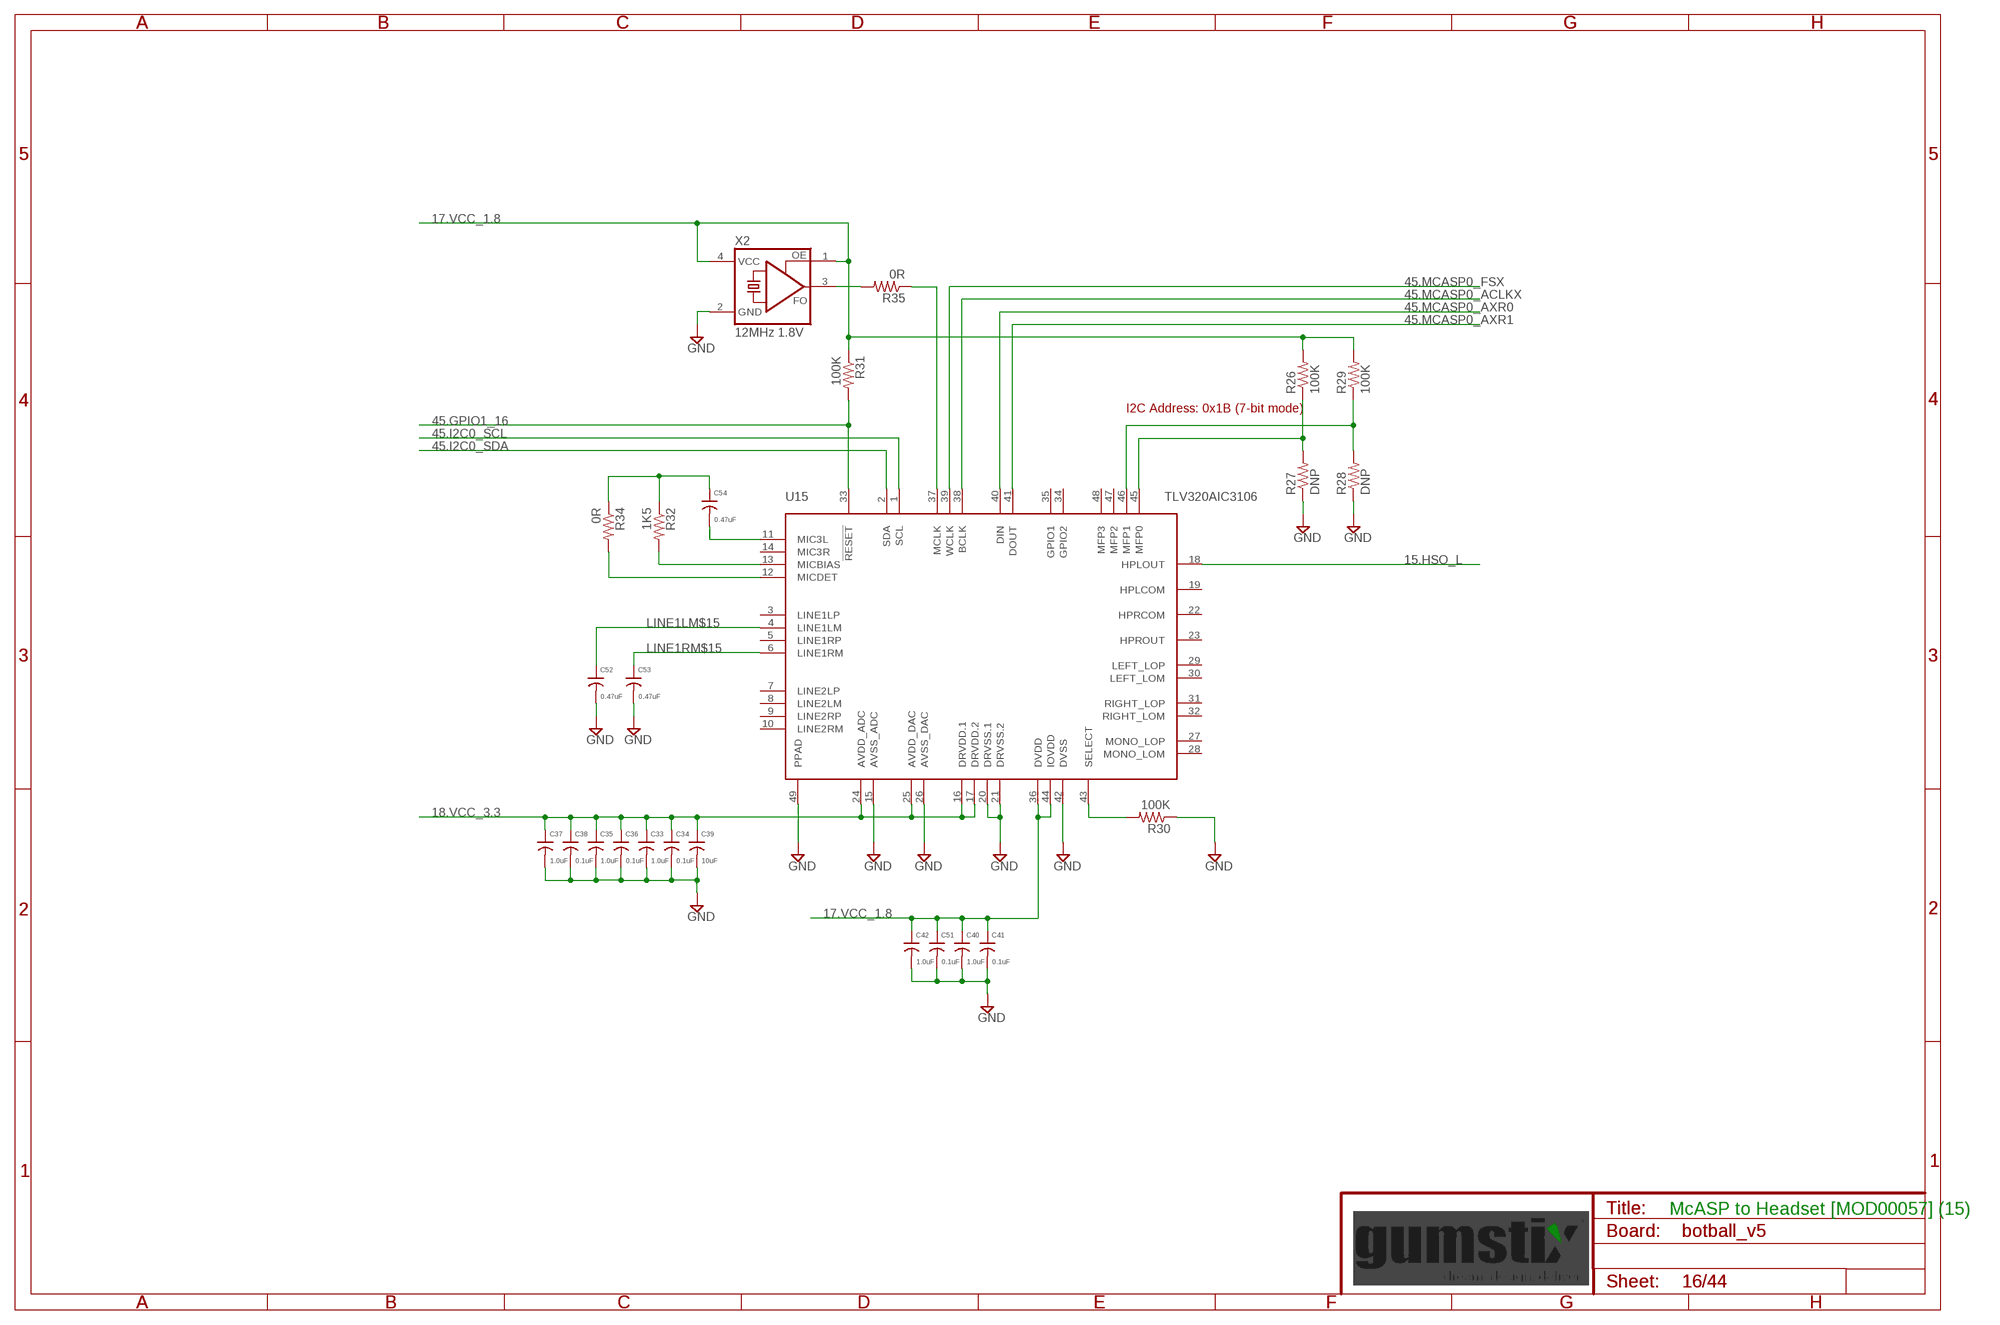
[diagram p15: schematic, sheet 16]
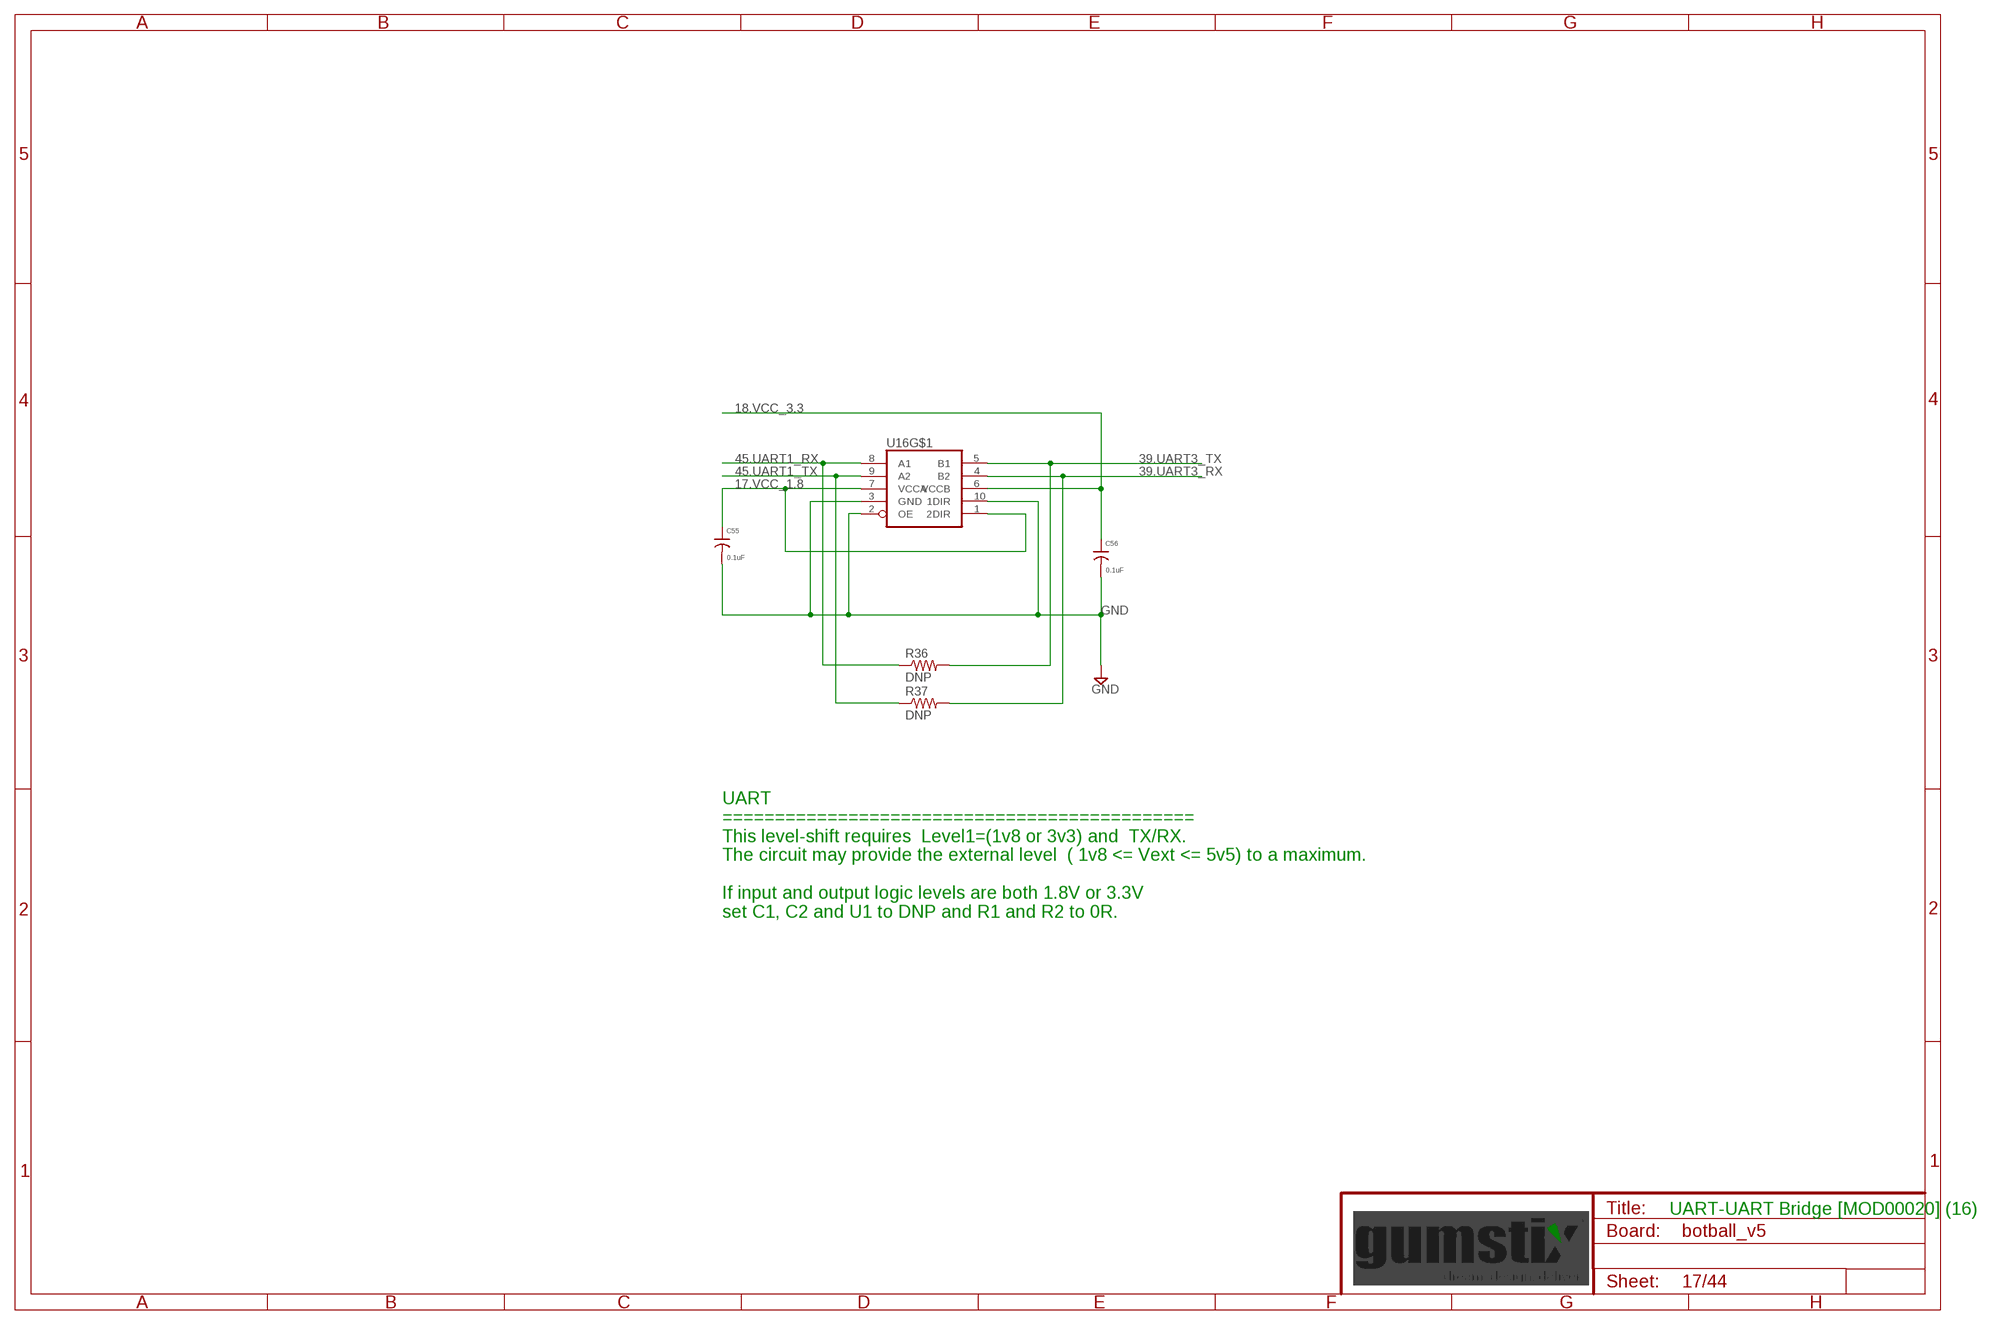
[diagram p16: schematic, sheet 17]
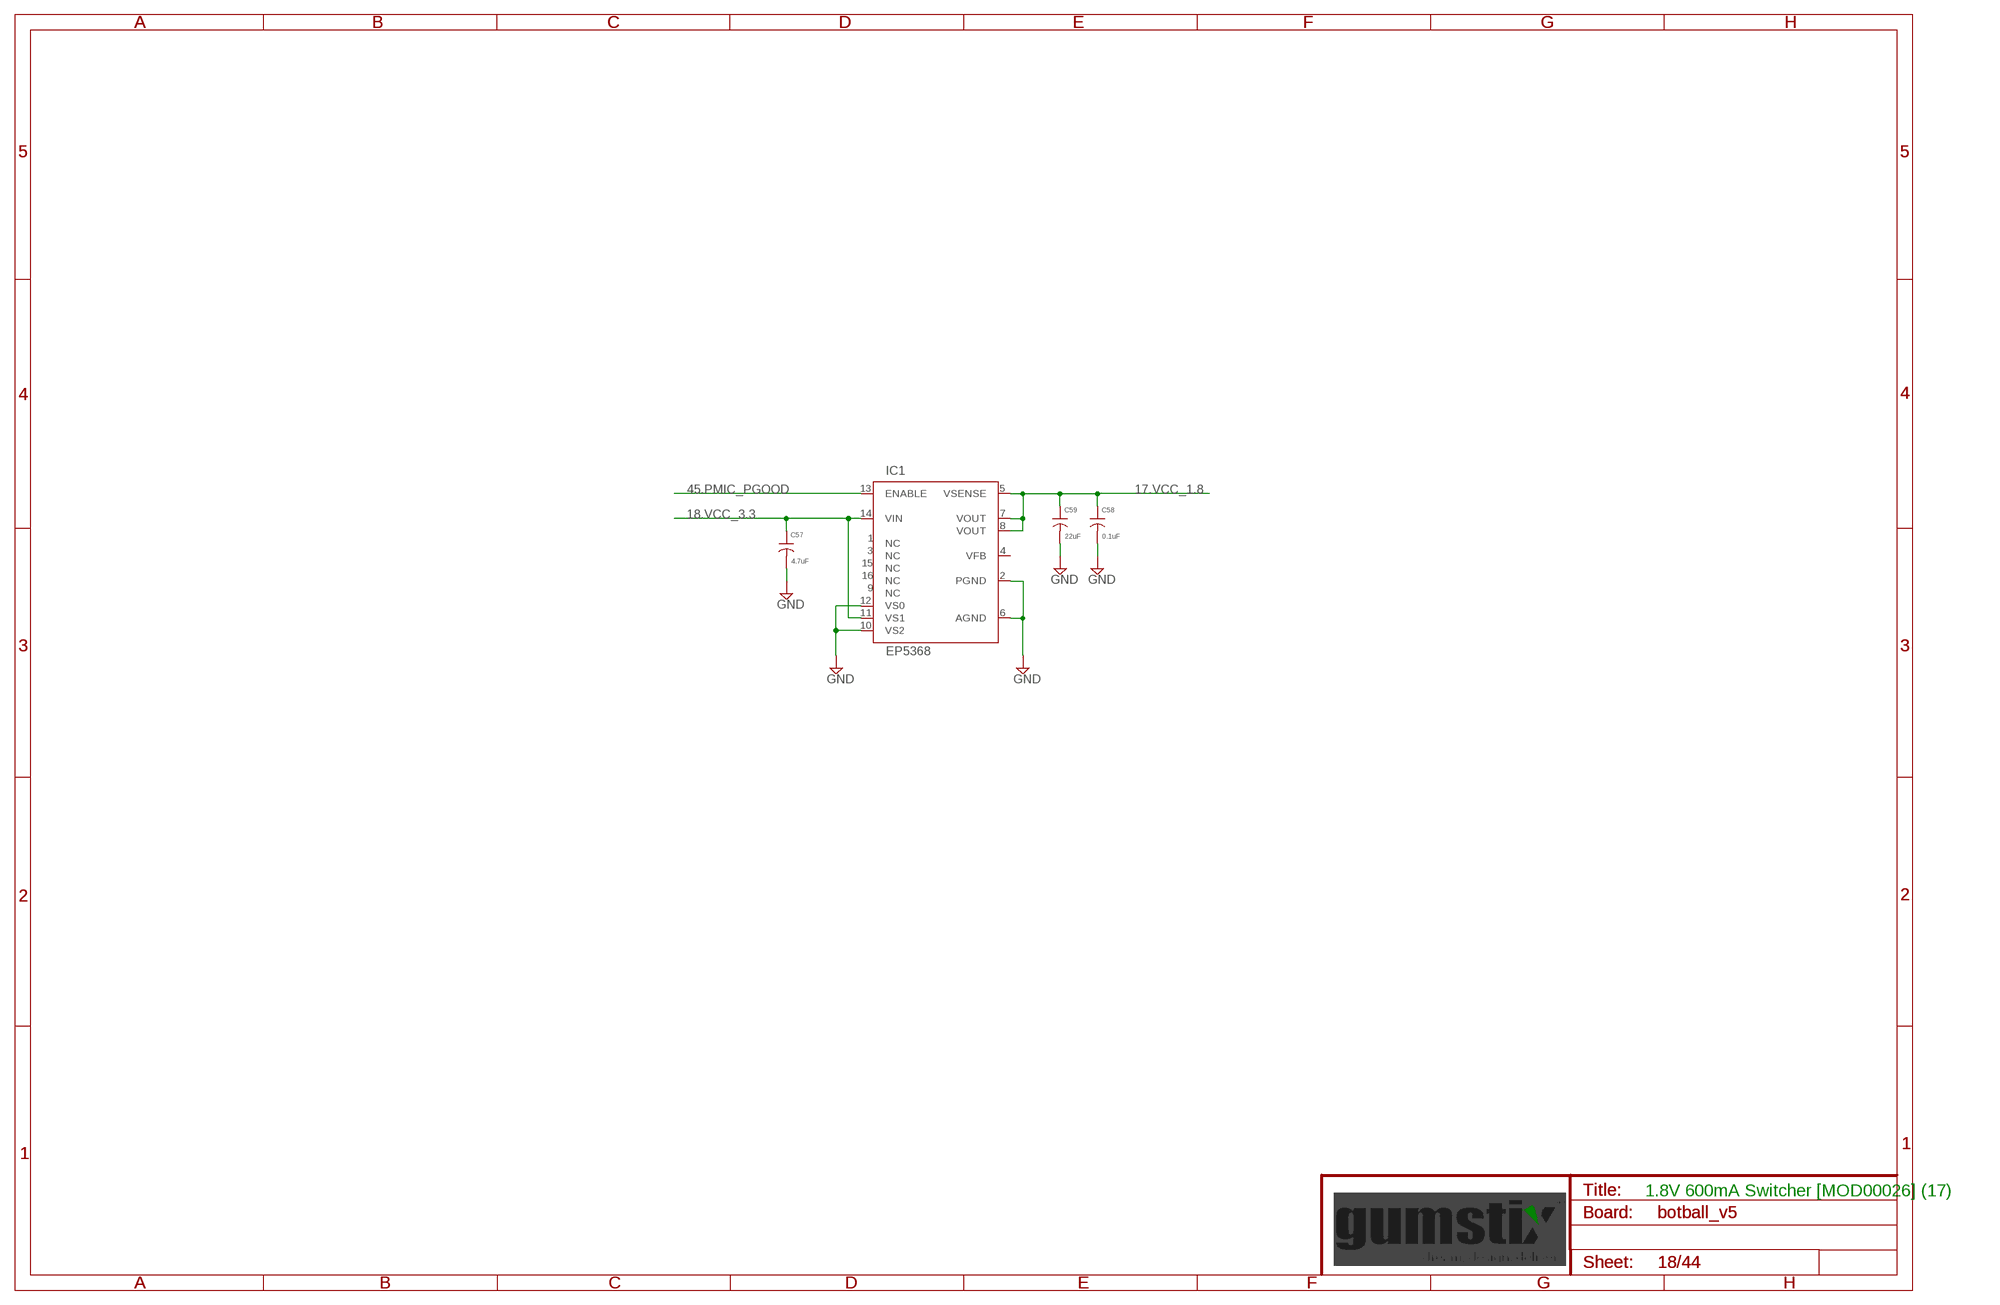
[diagram p17: schematic, sheet 18]
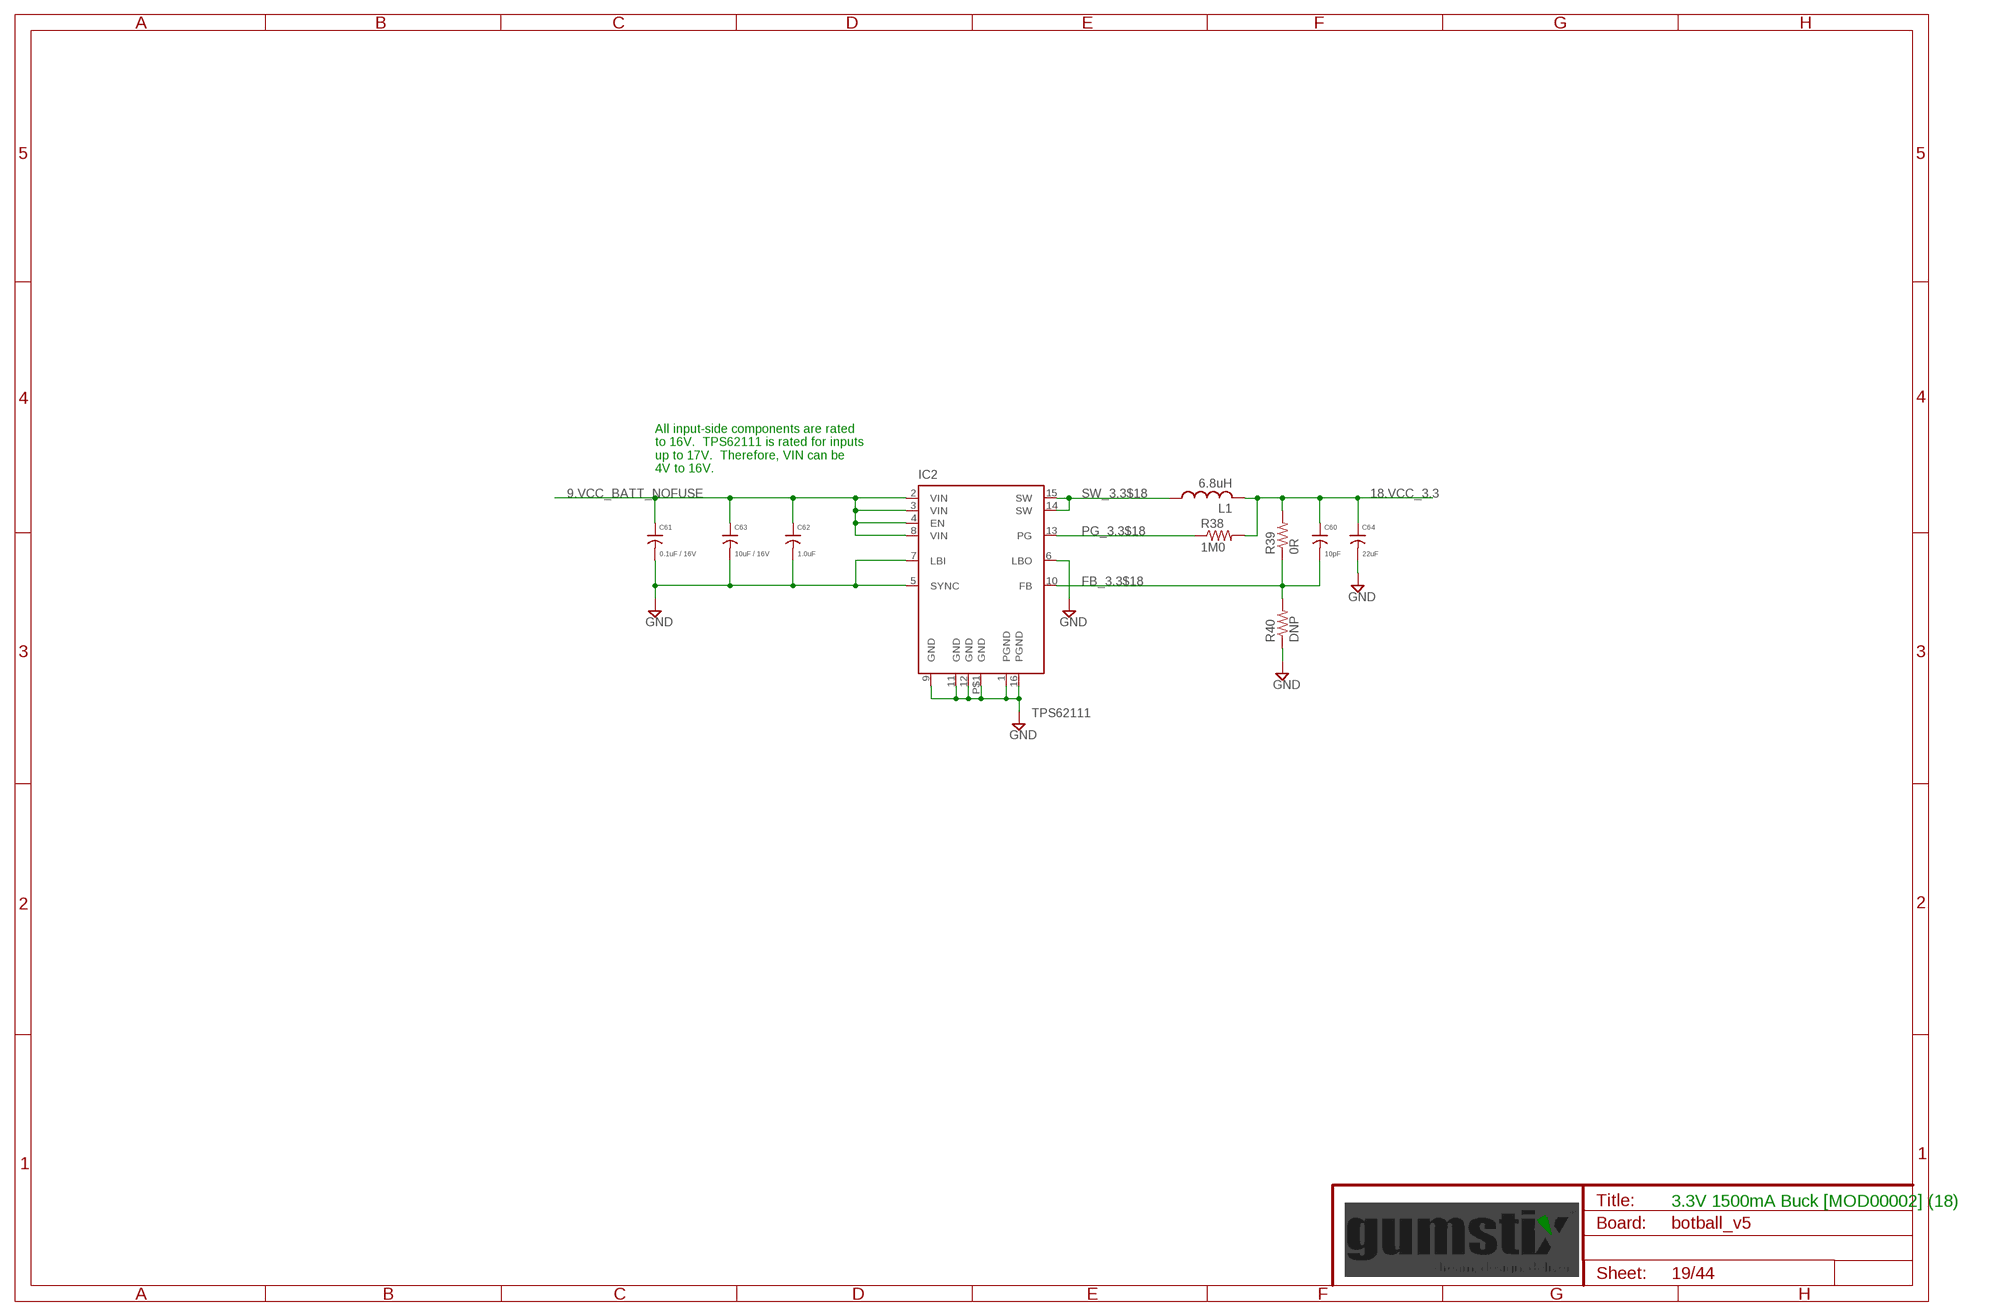
[diagram p18: schematic, sheet 19]
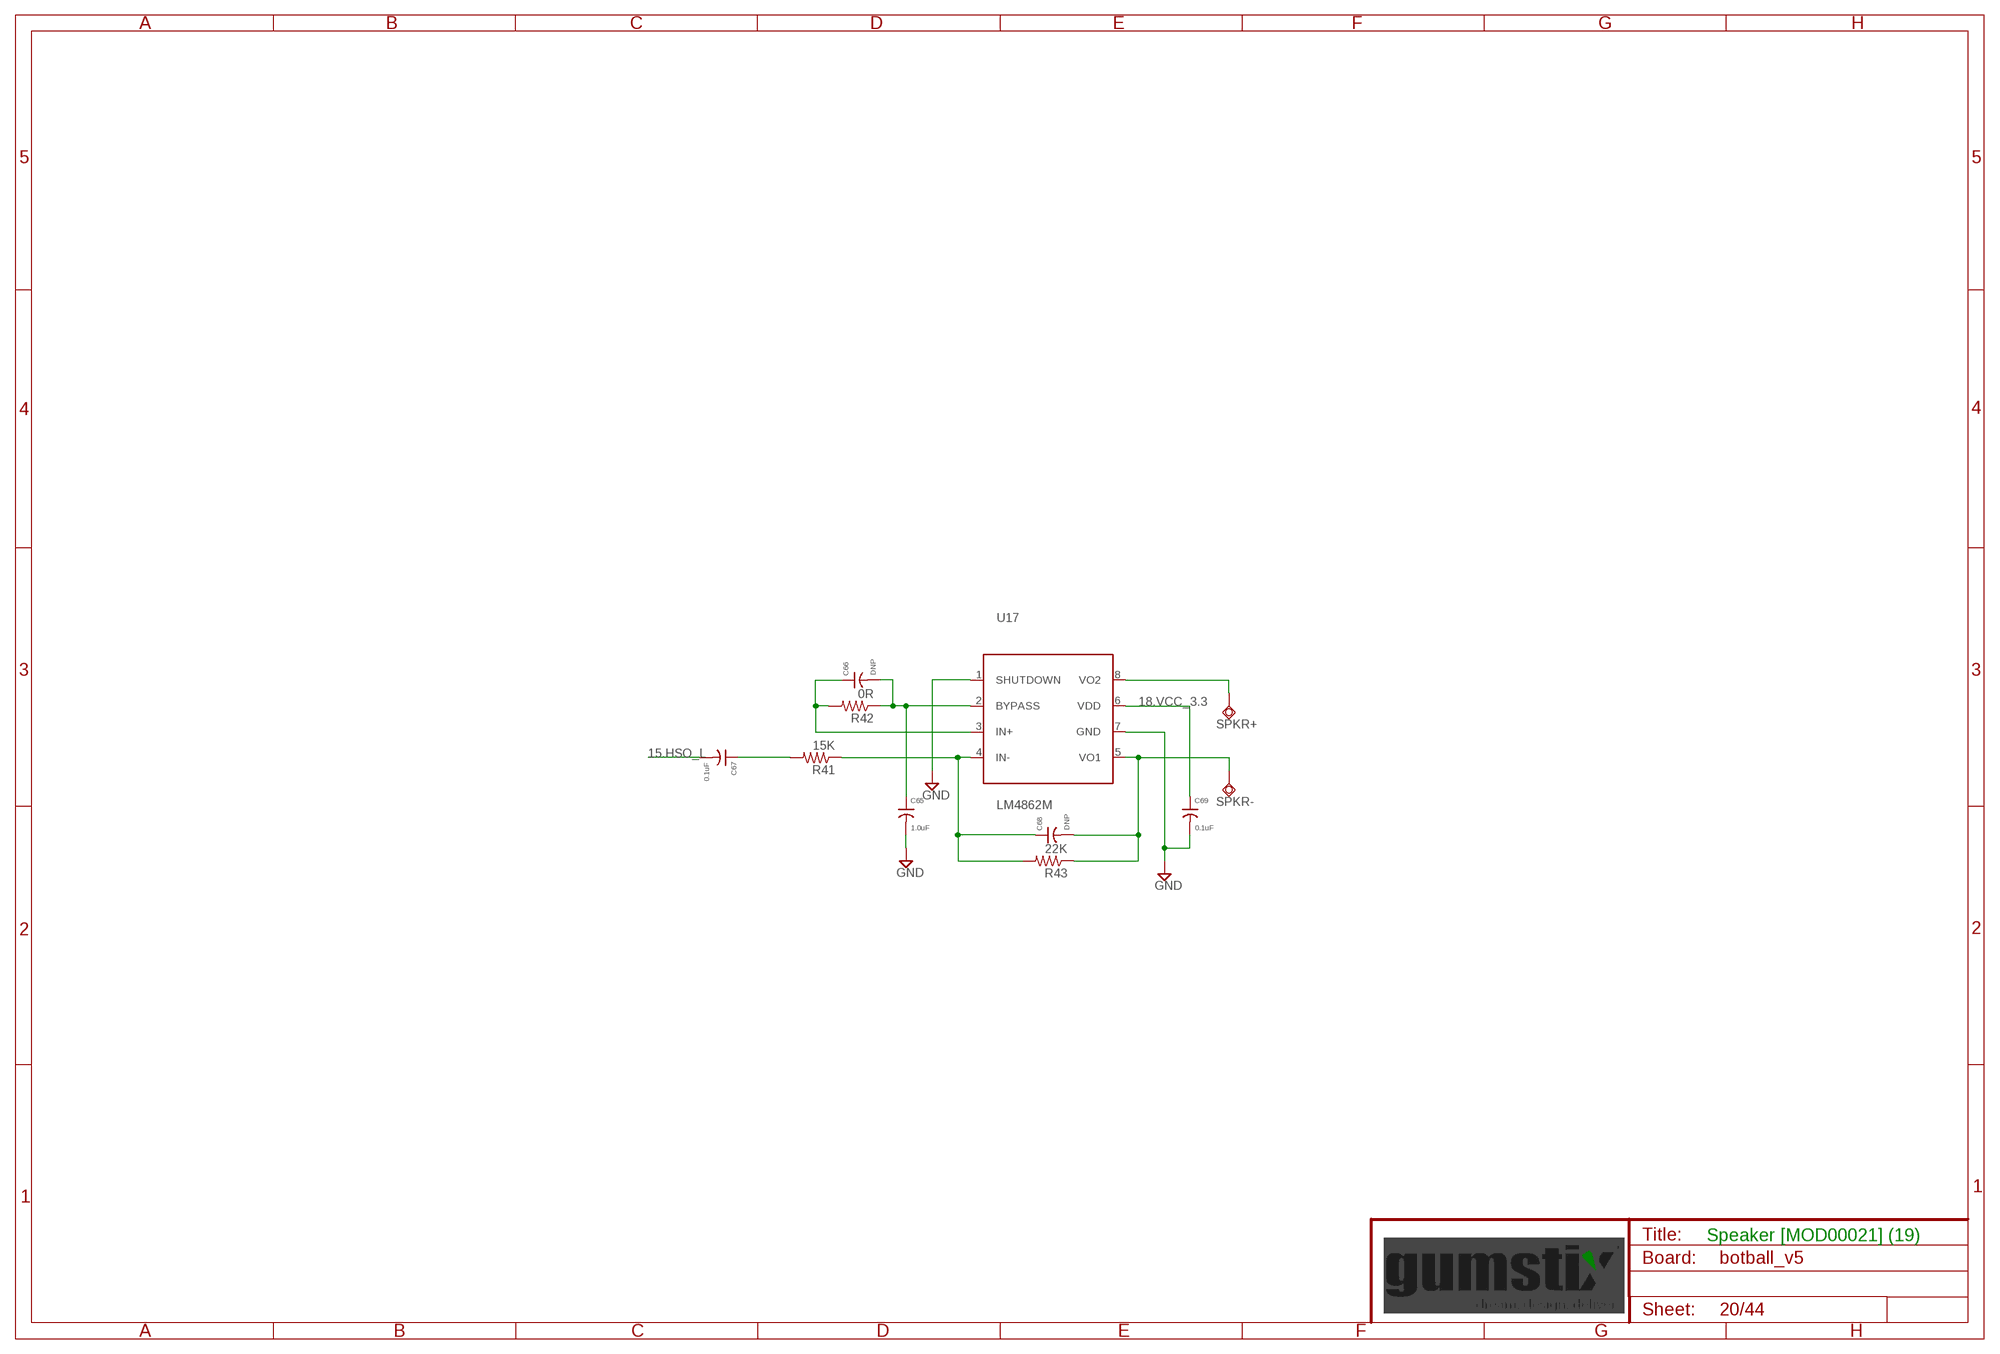
[diagram p19: schematic, sheet 20]
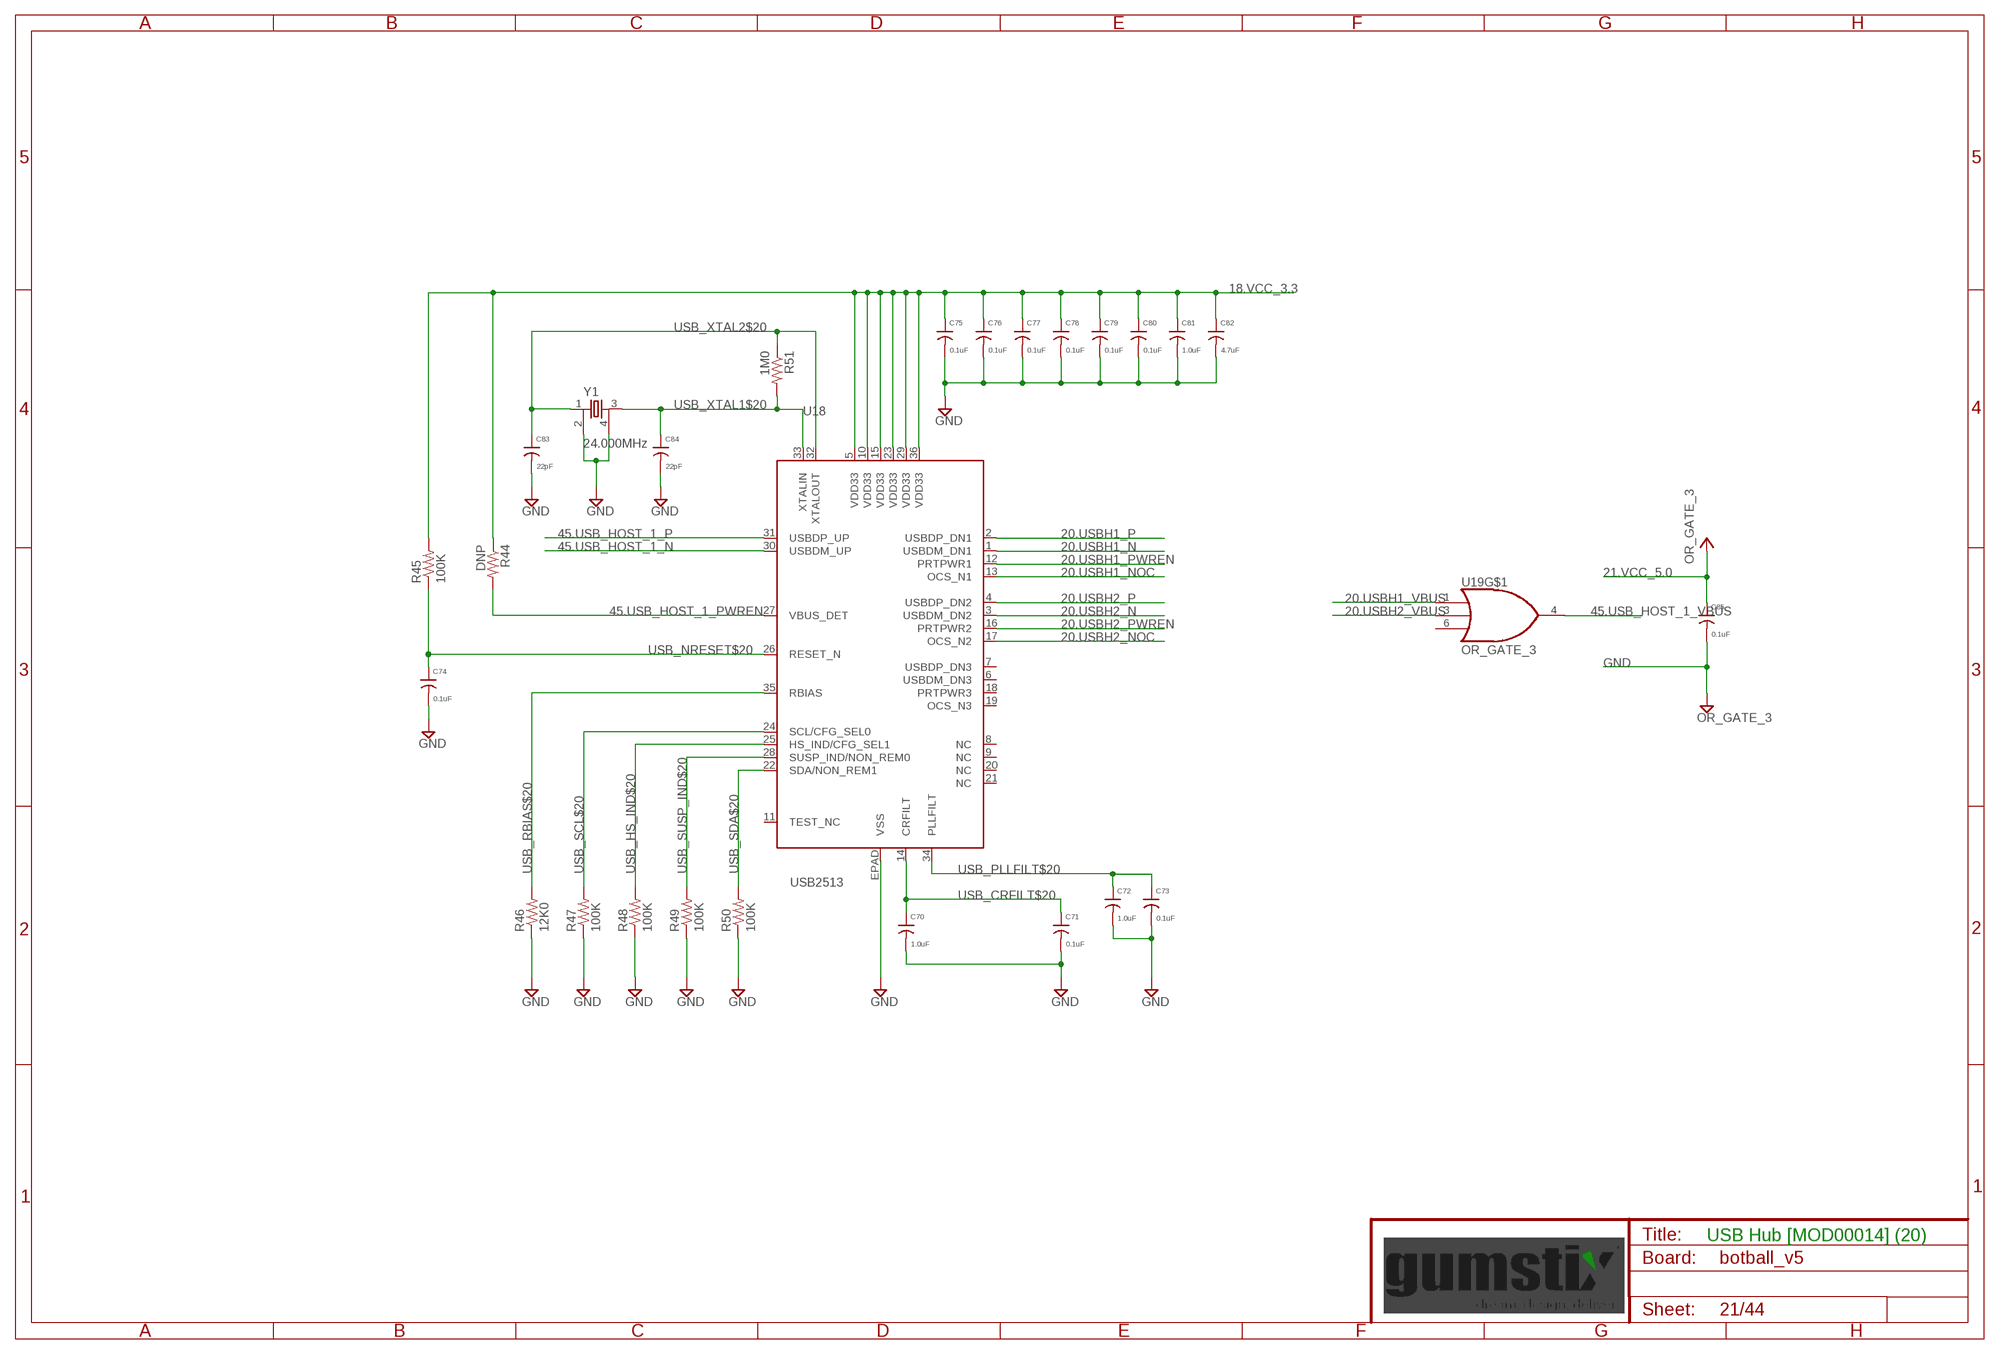
[diagram p20: schematic, sheet 21]
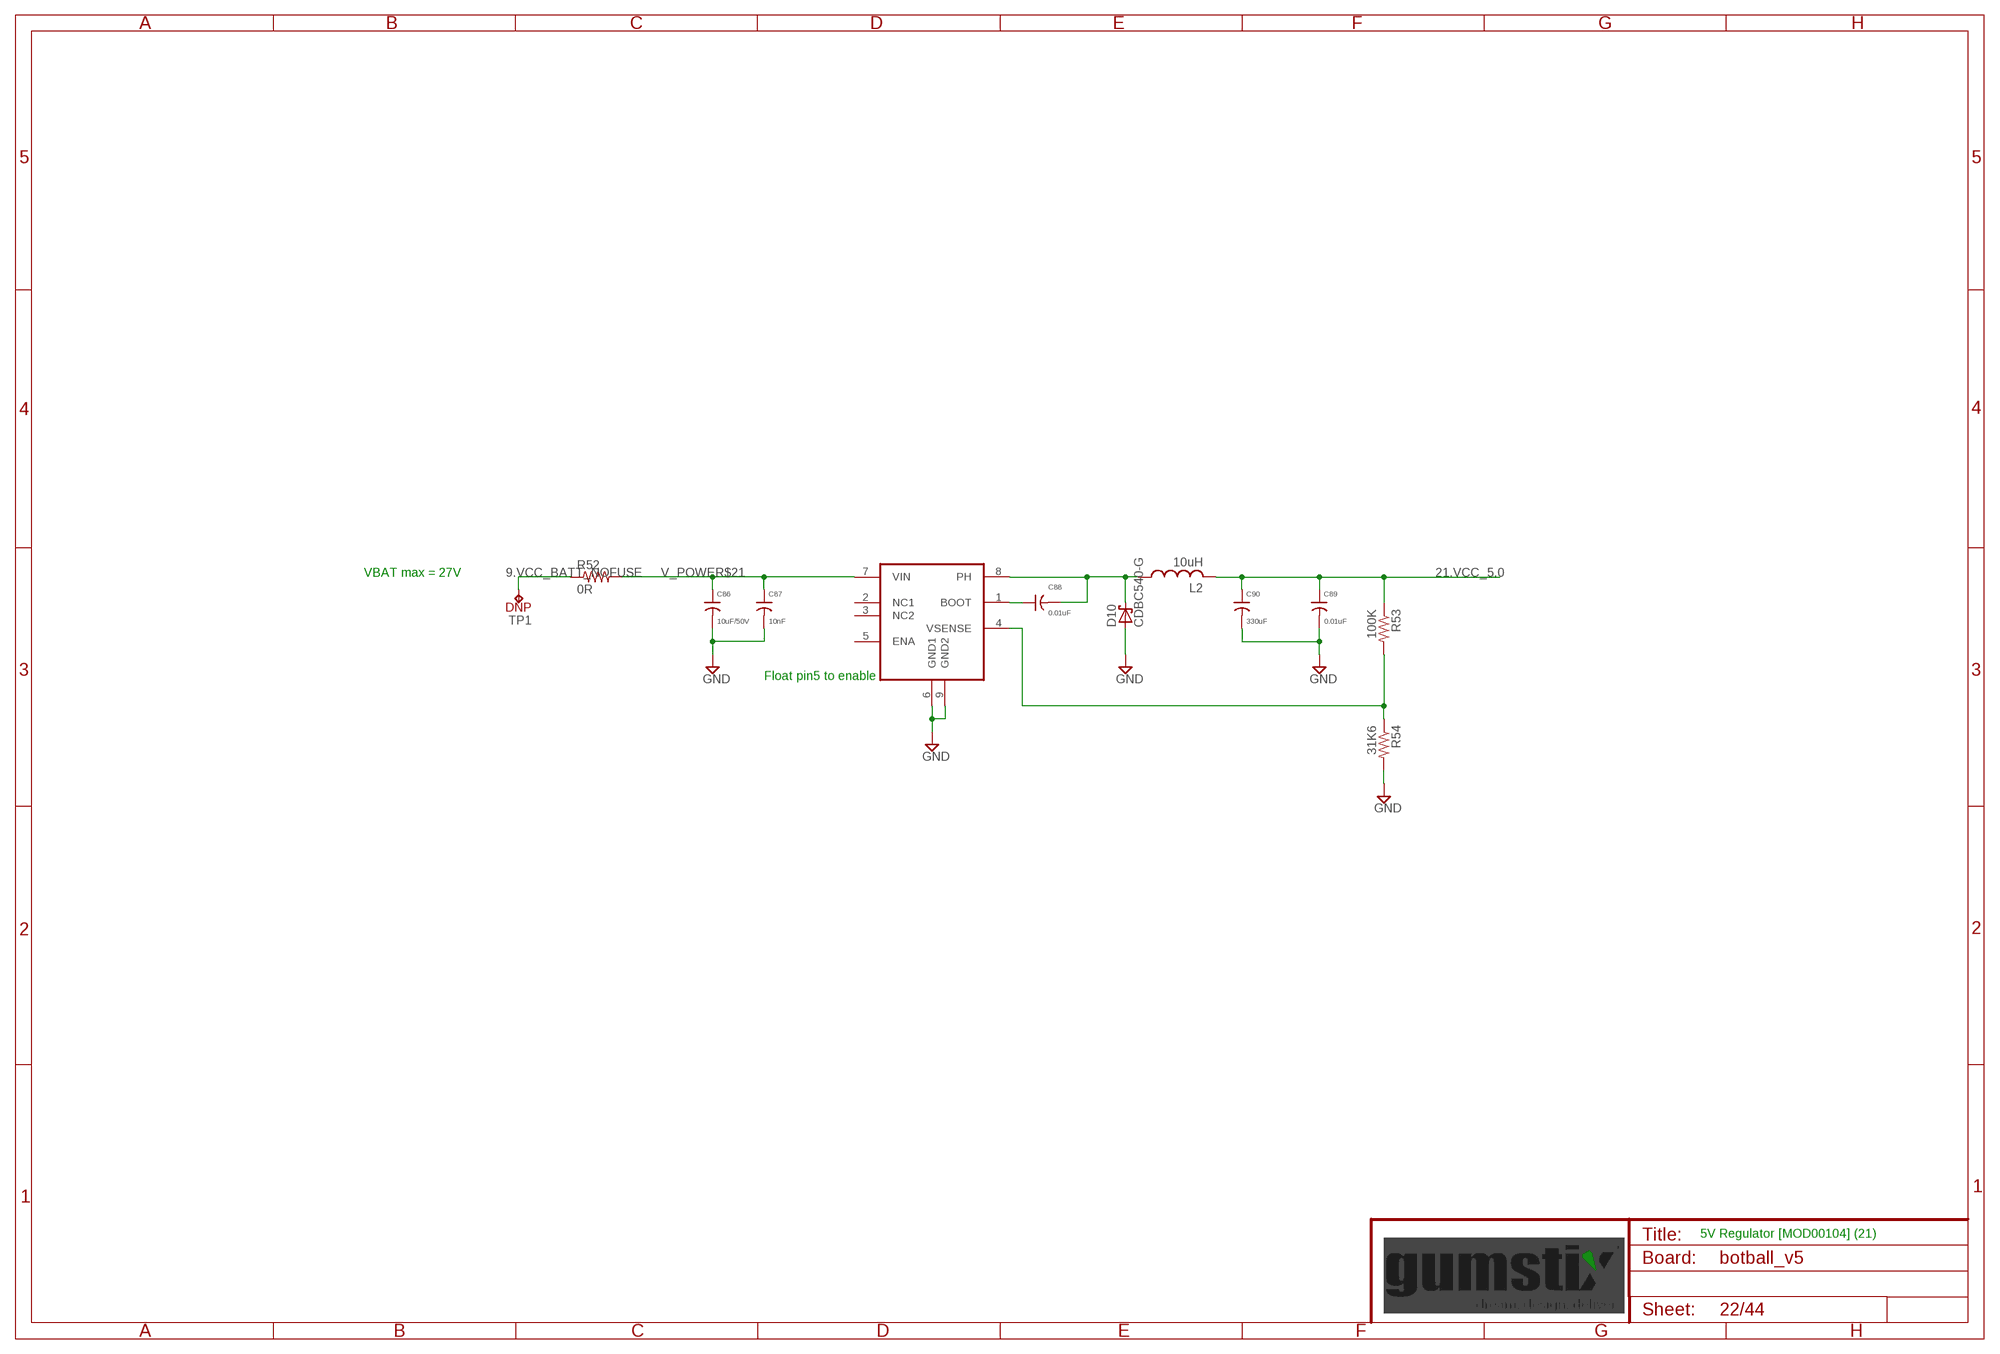
[diagram p21: schematic, sheet 22]
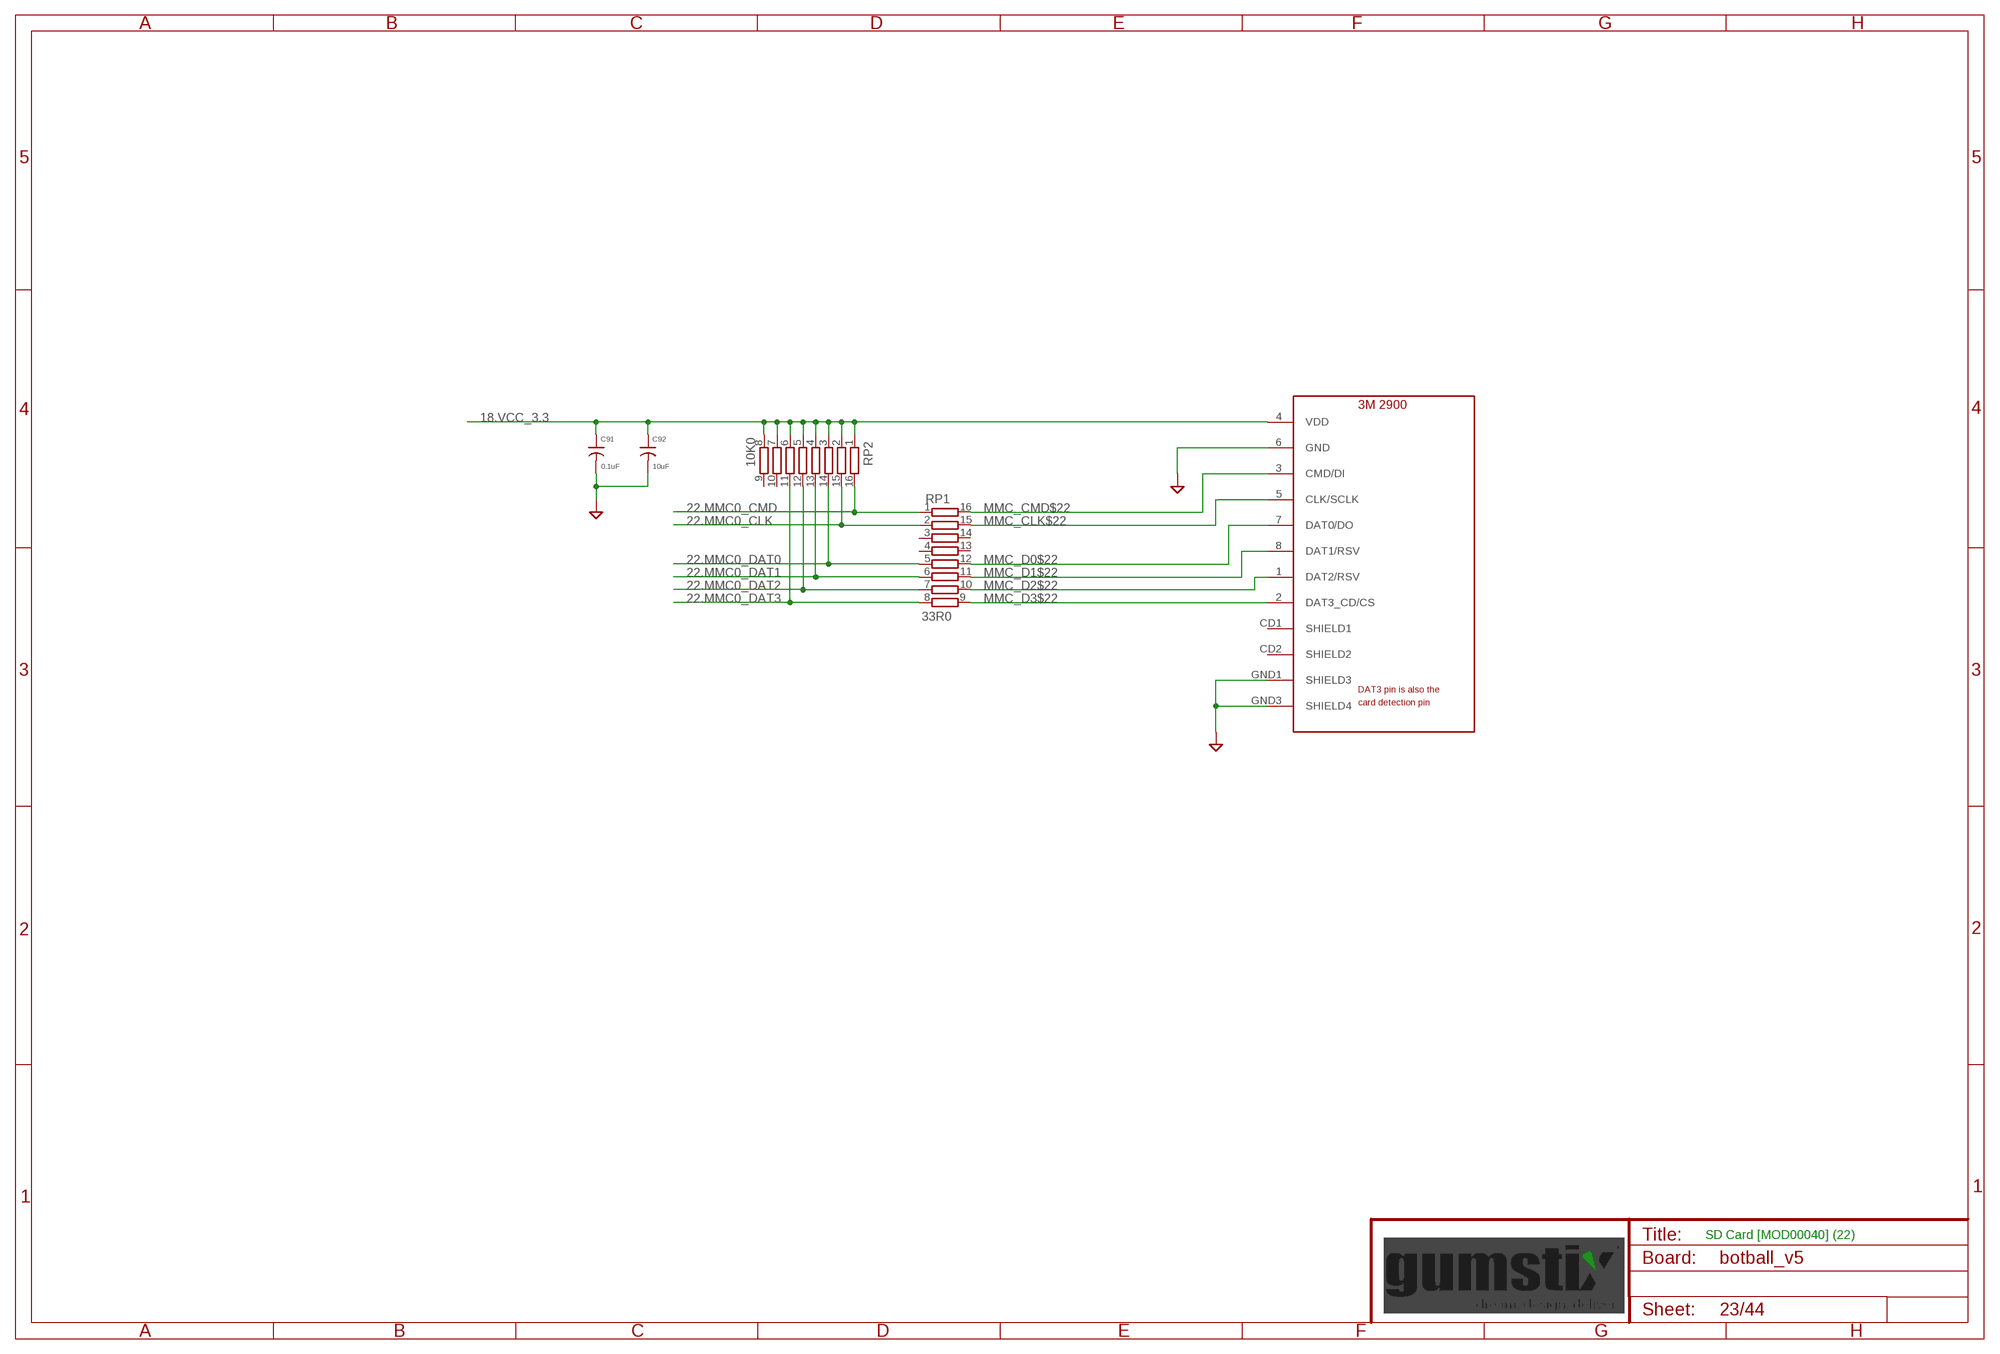
[diagram p22: schematic, sheet 23]
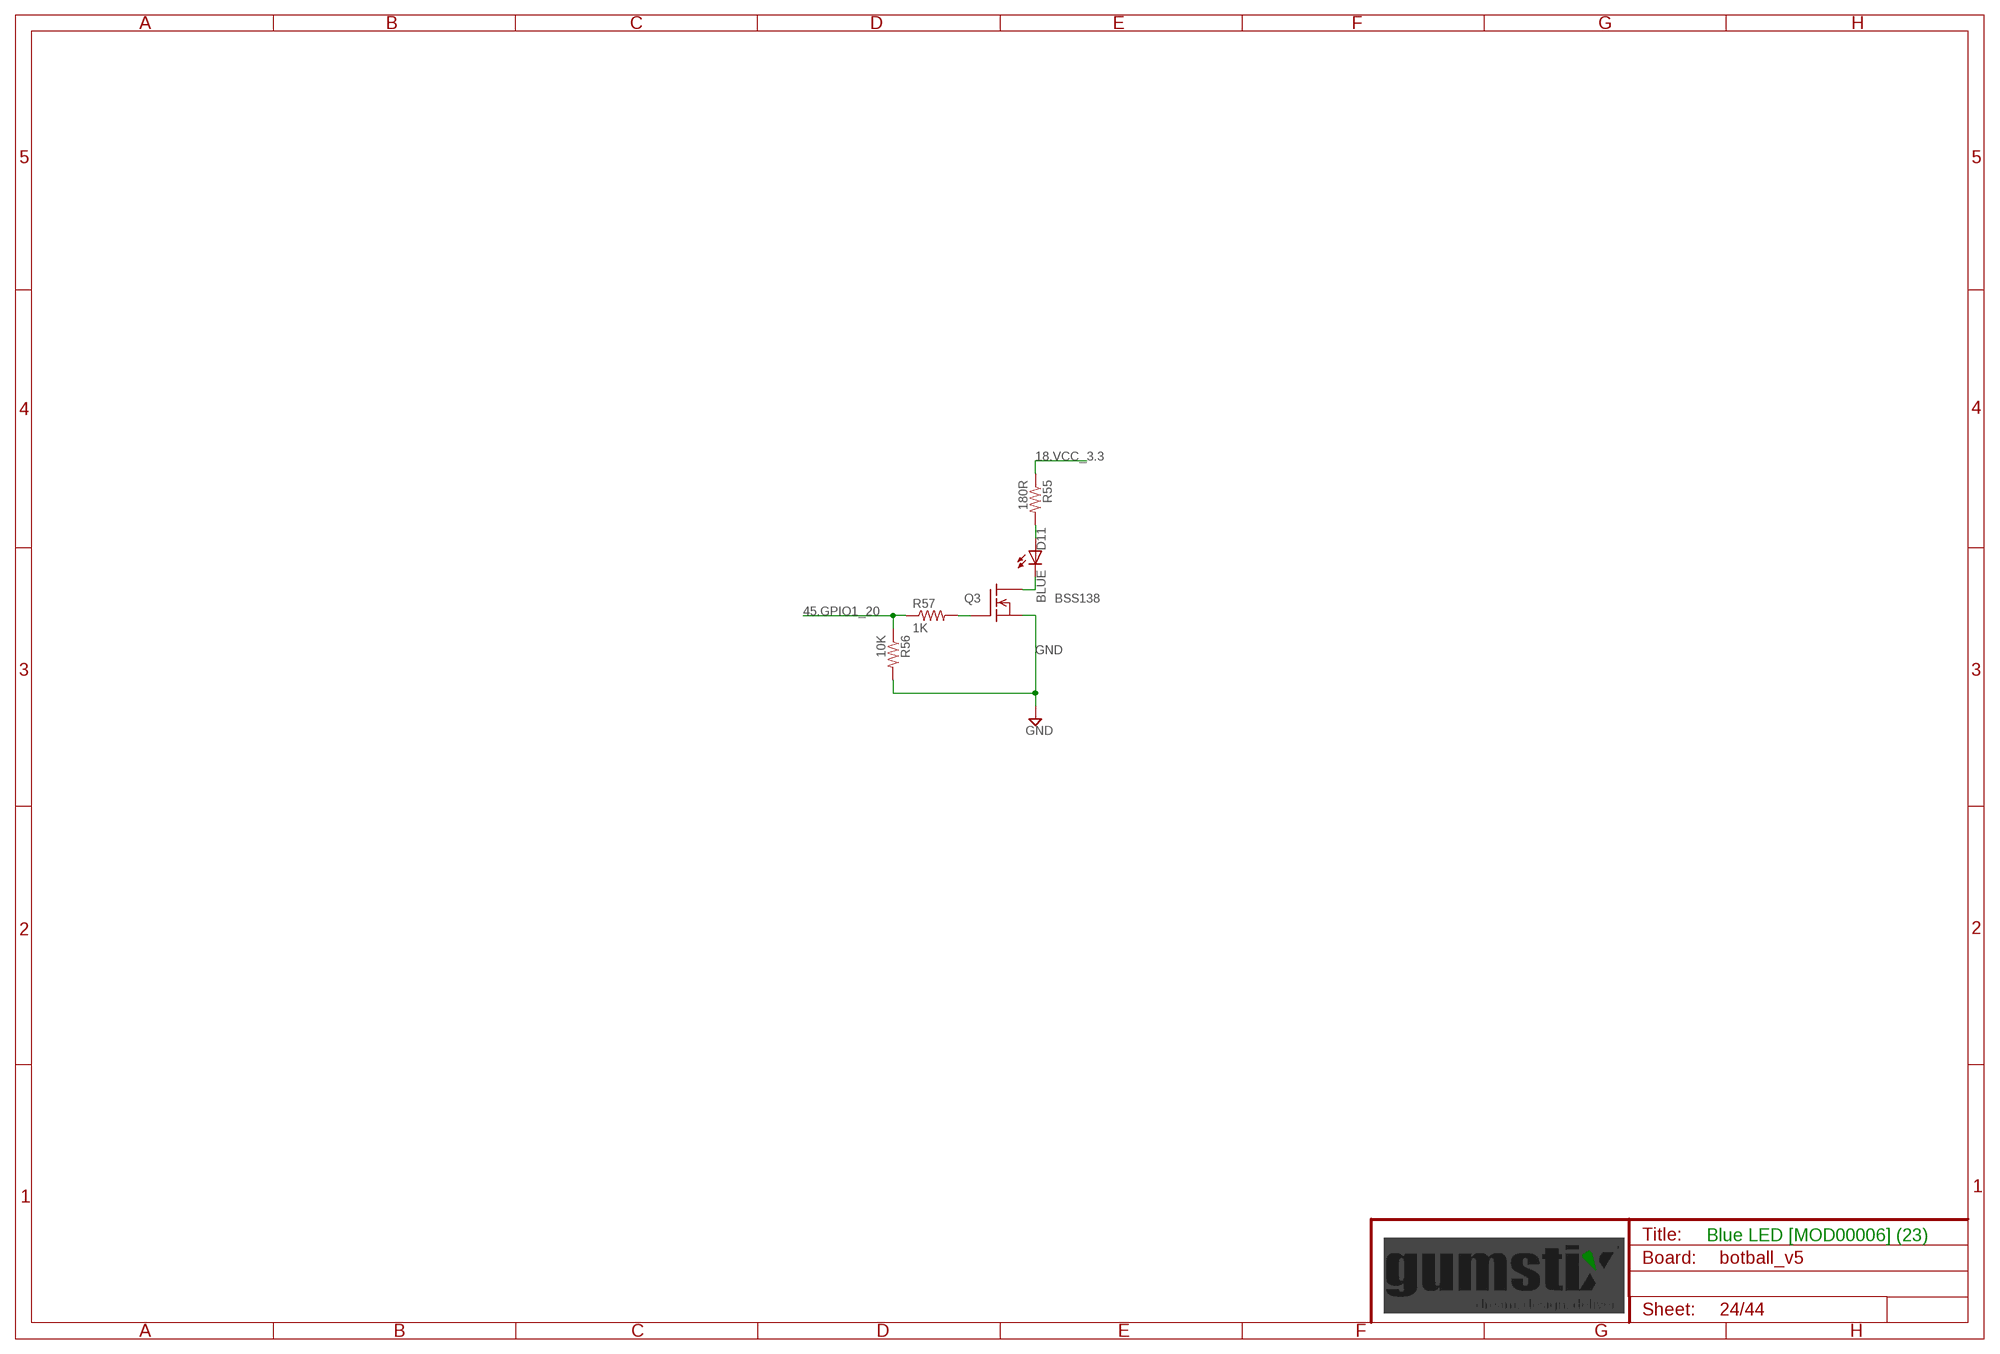
[diagram p23: schematic, sheet 24]
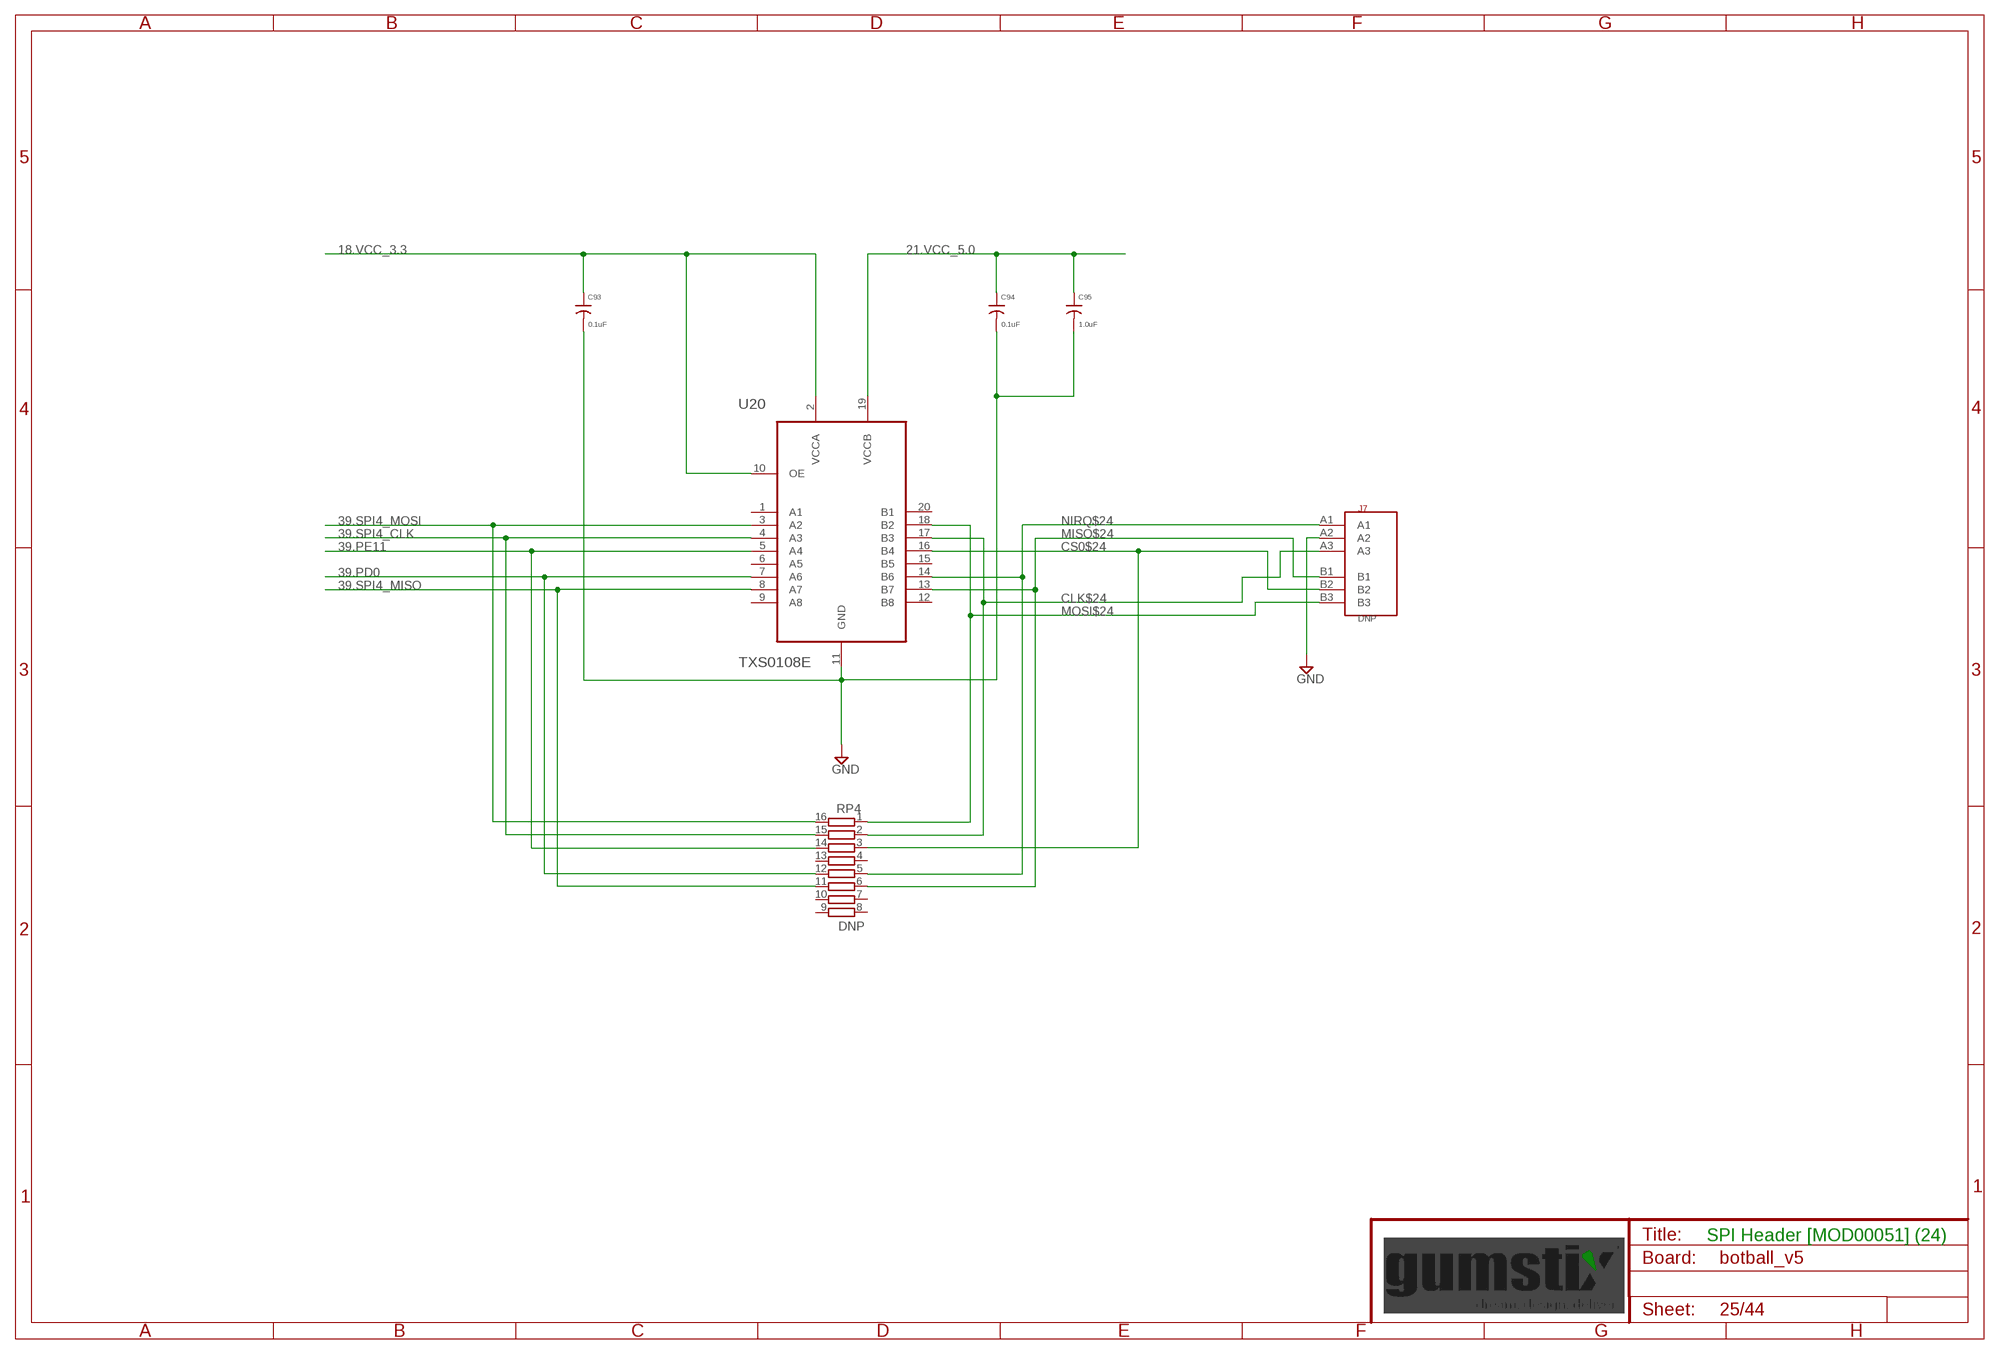
[diagram p24: schematic, sheet 25]
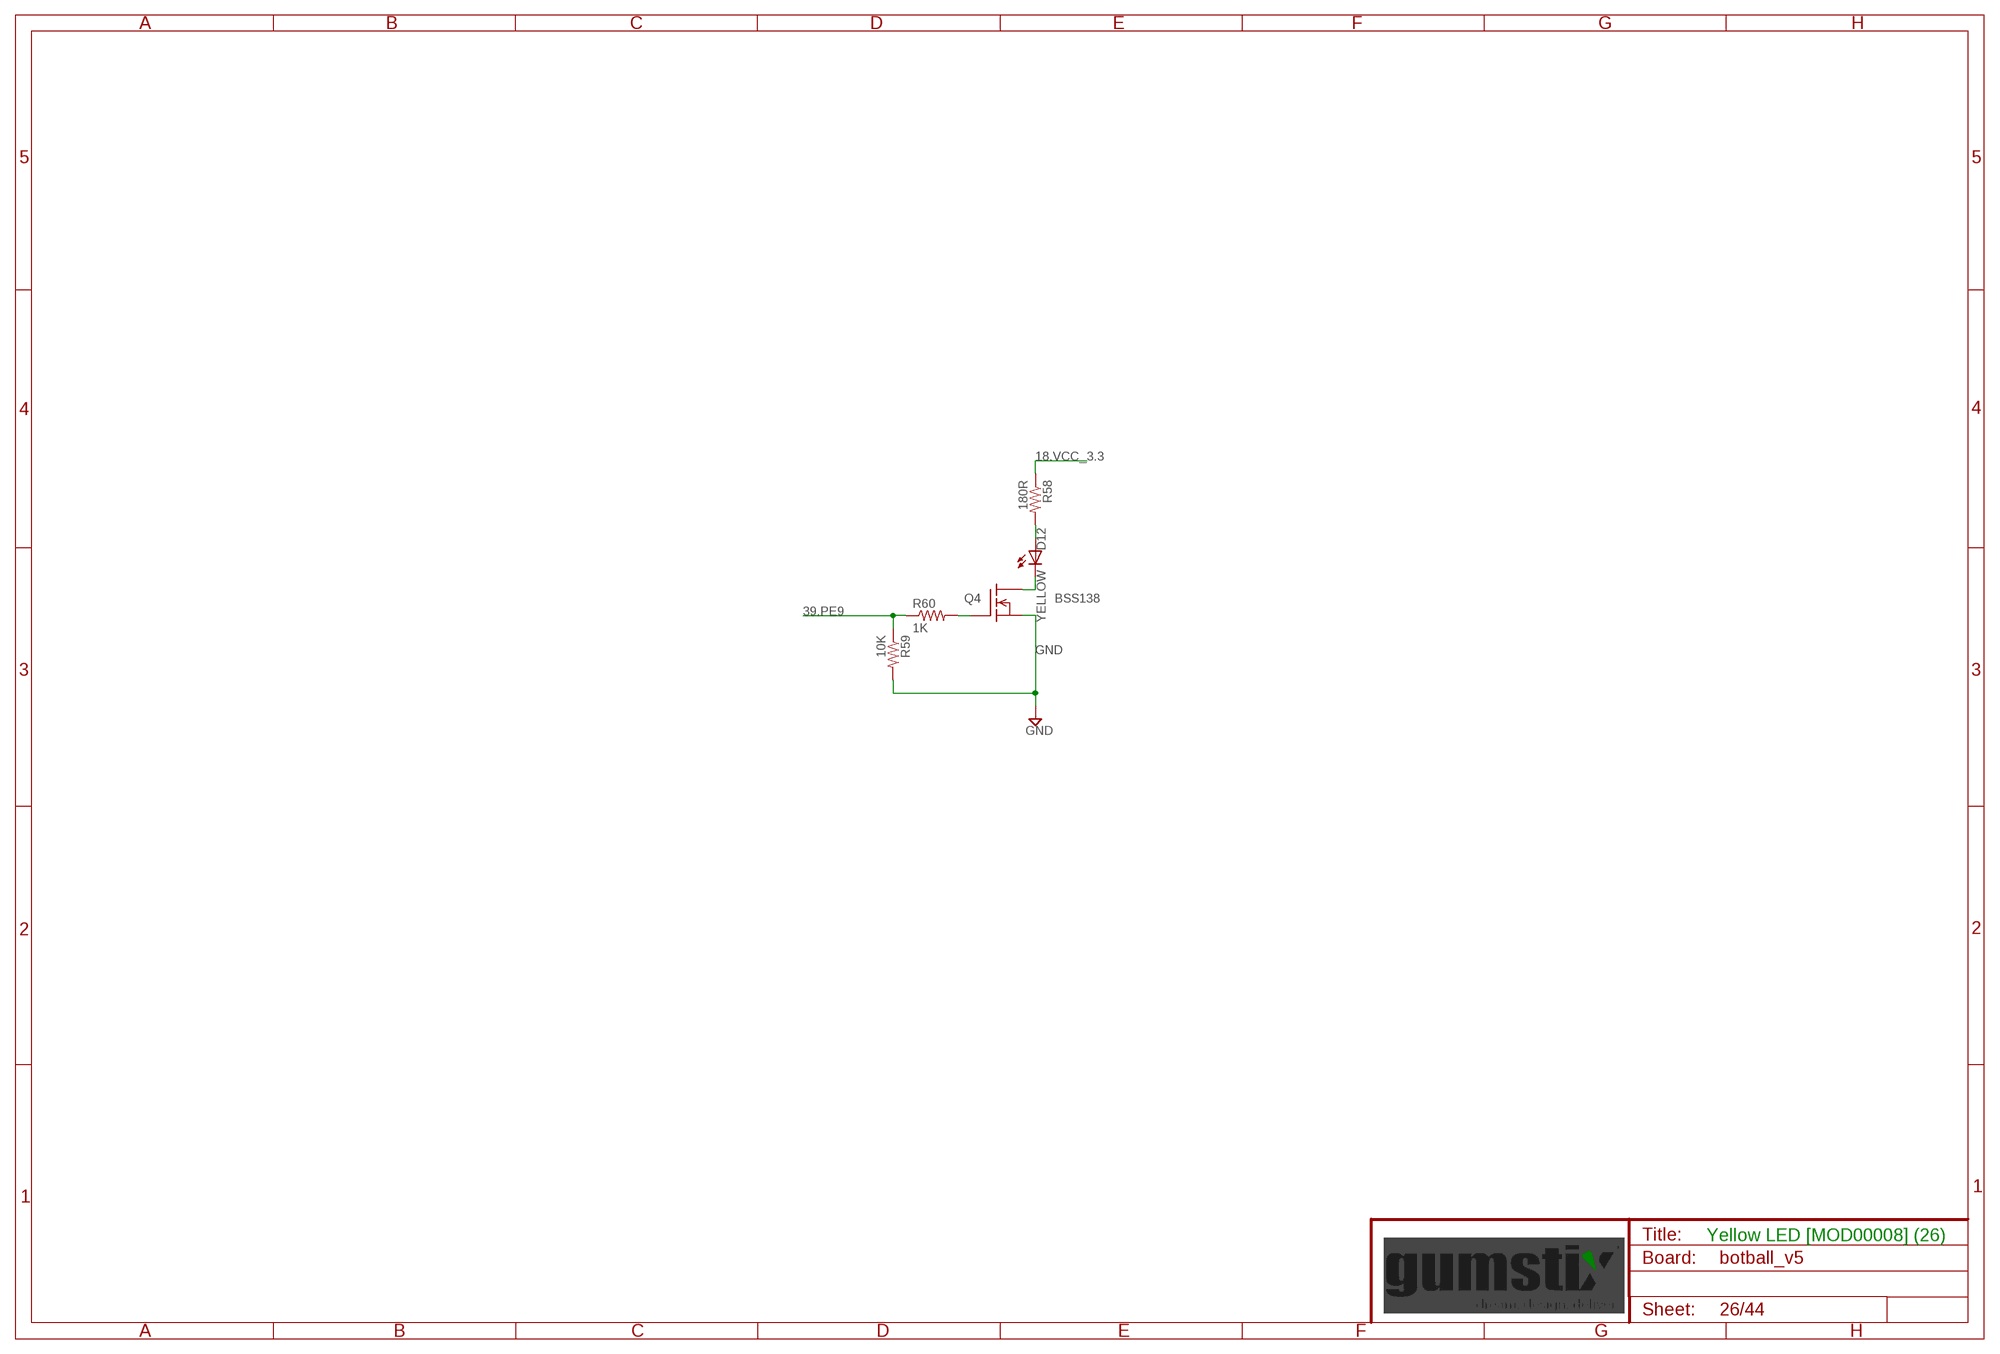
[diagram p25: schematic, sheet 26]
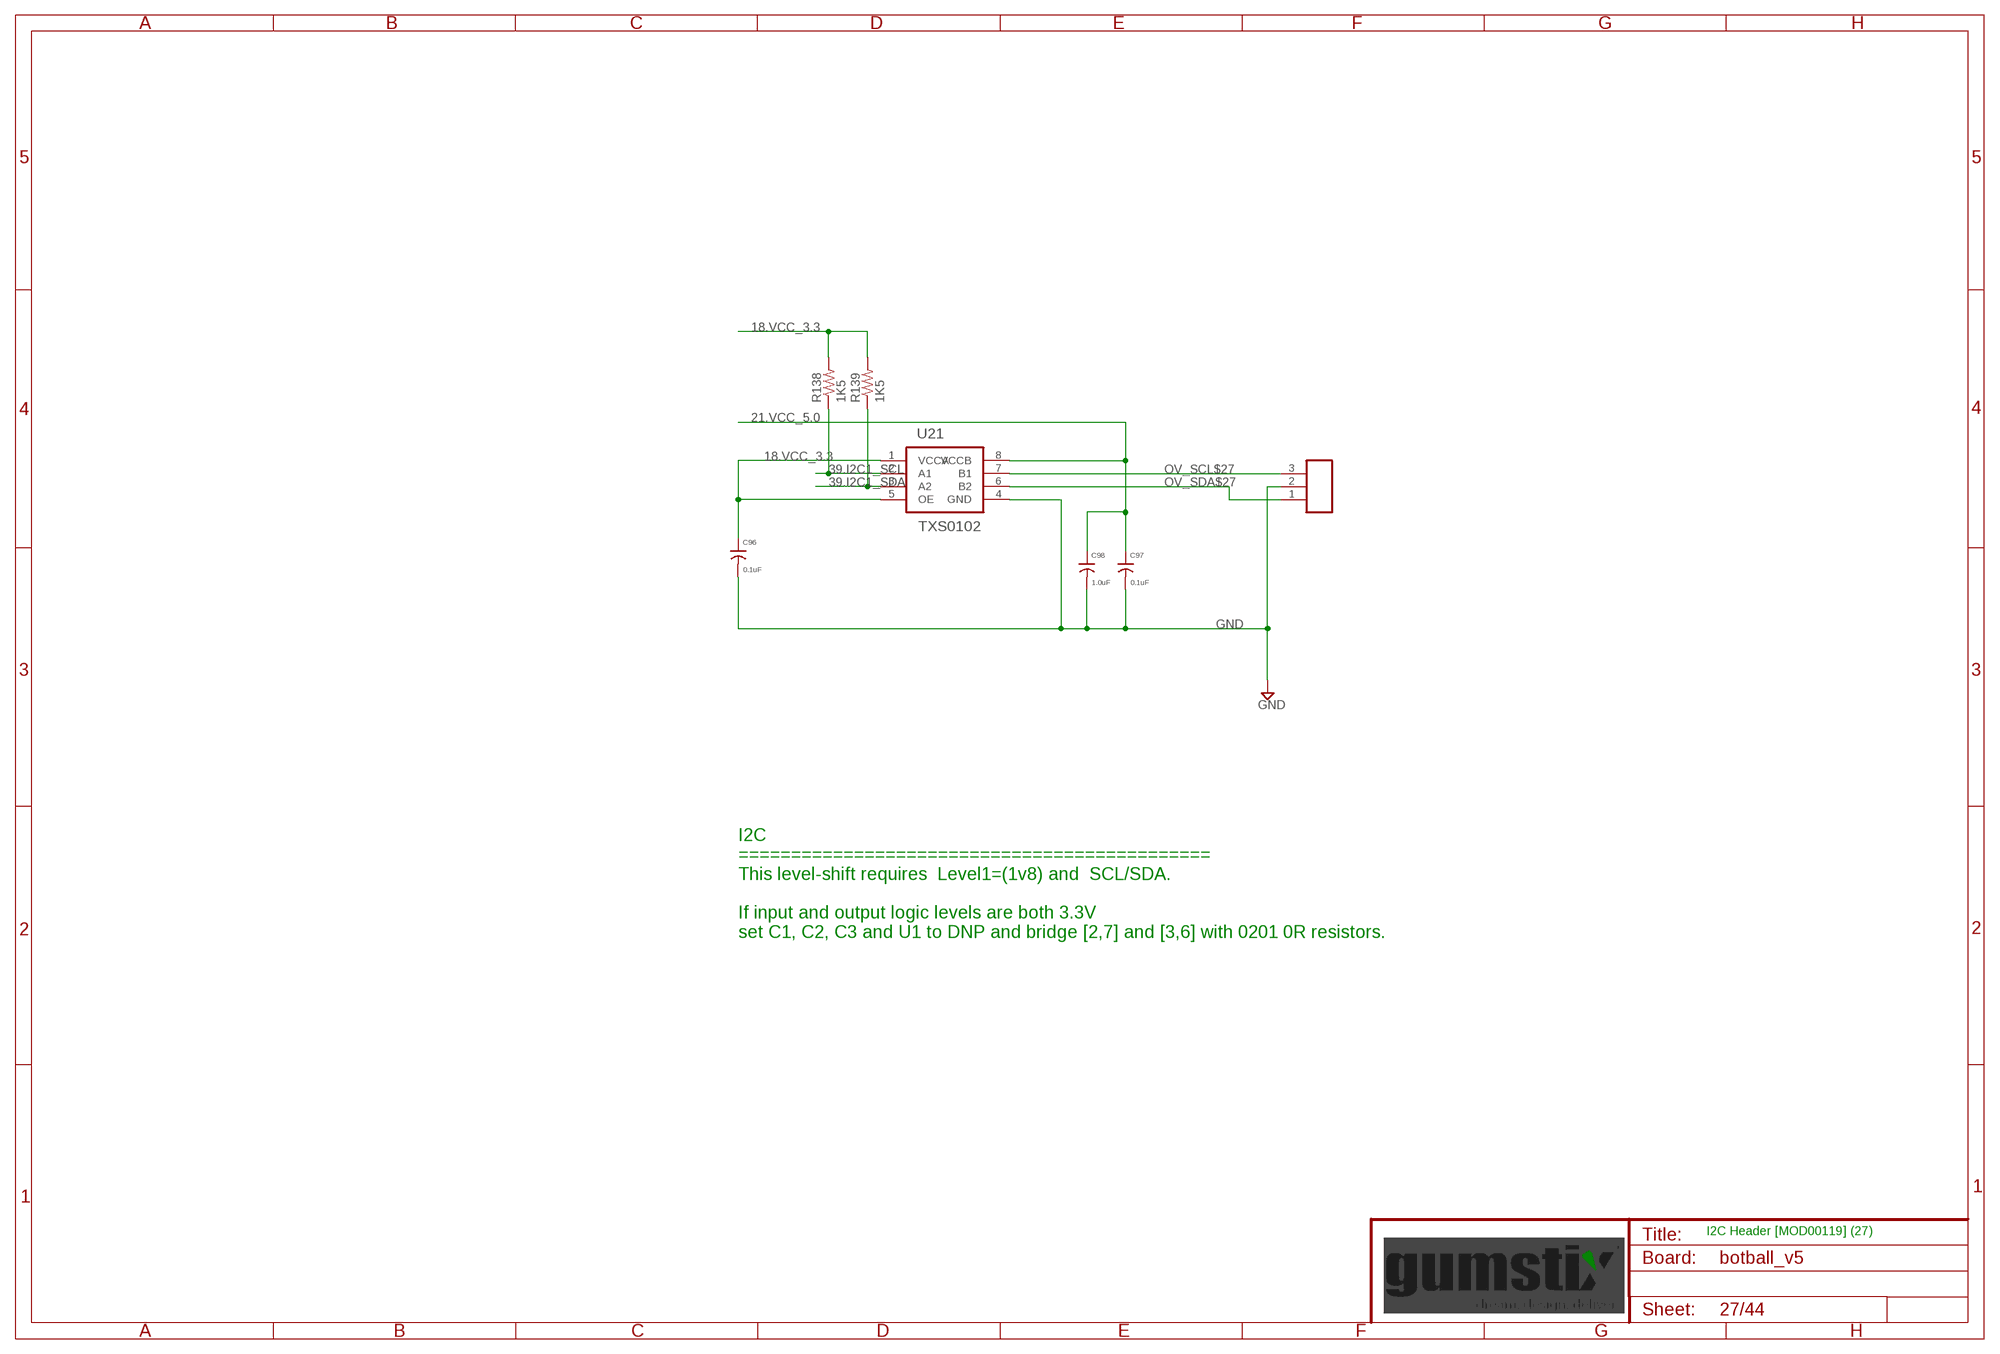
[diagram p26: schematic, sheet 27]
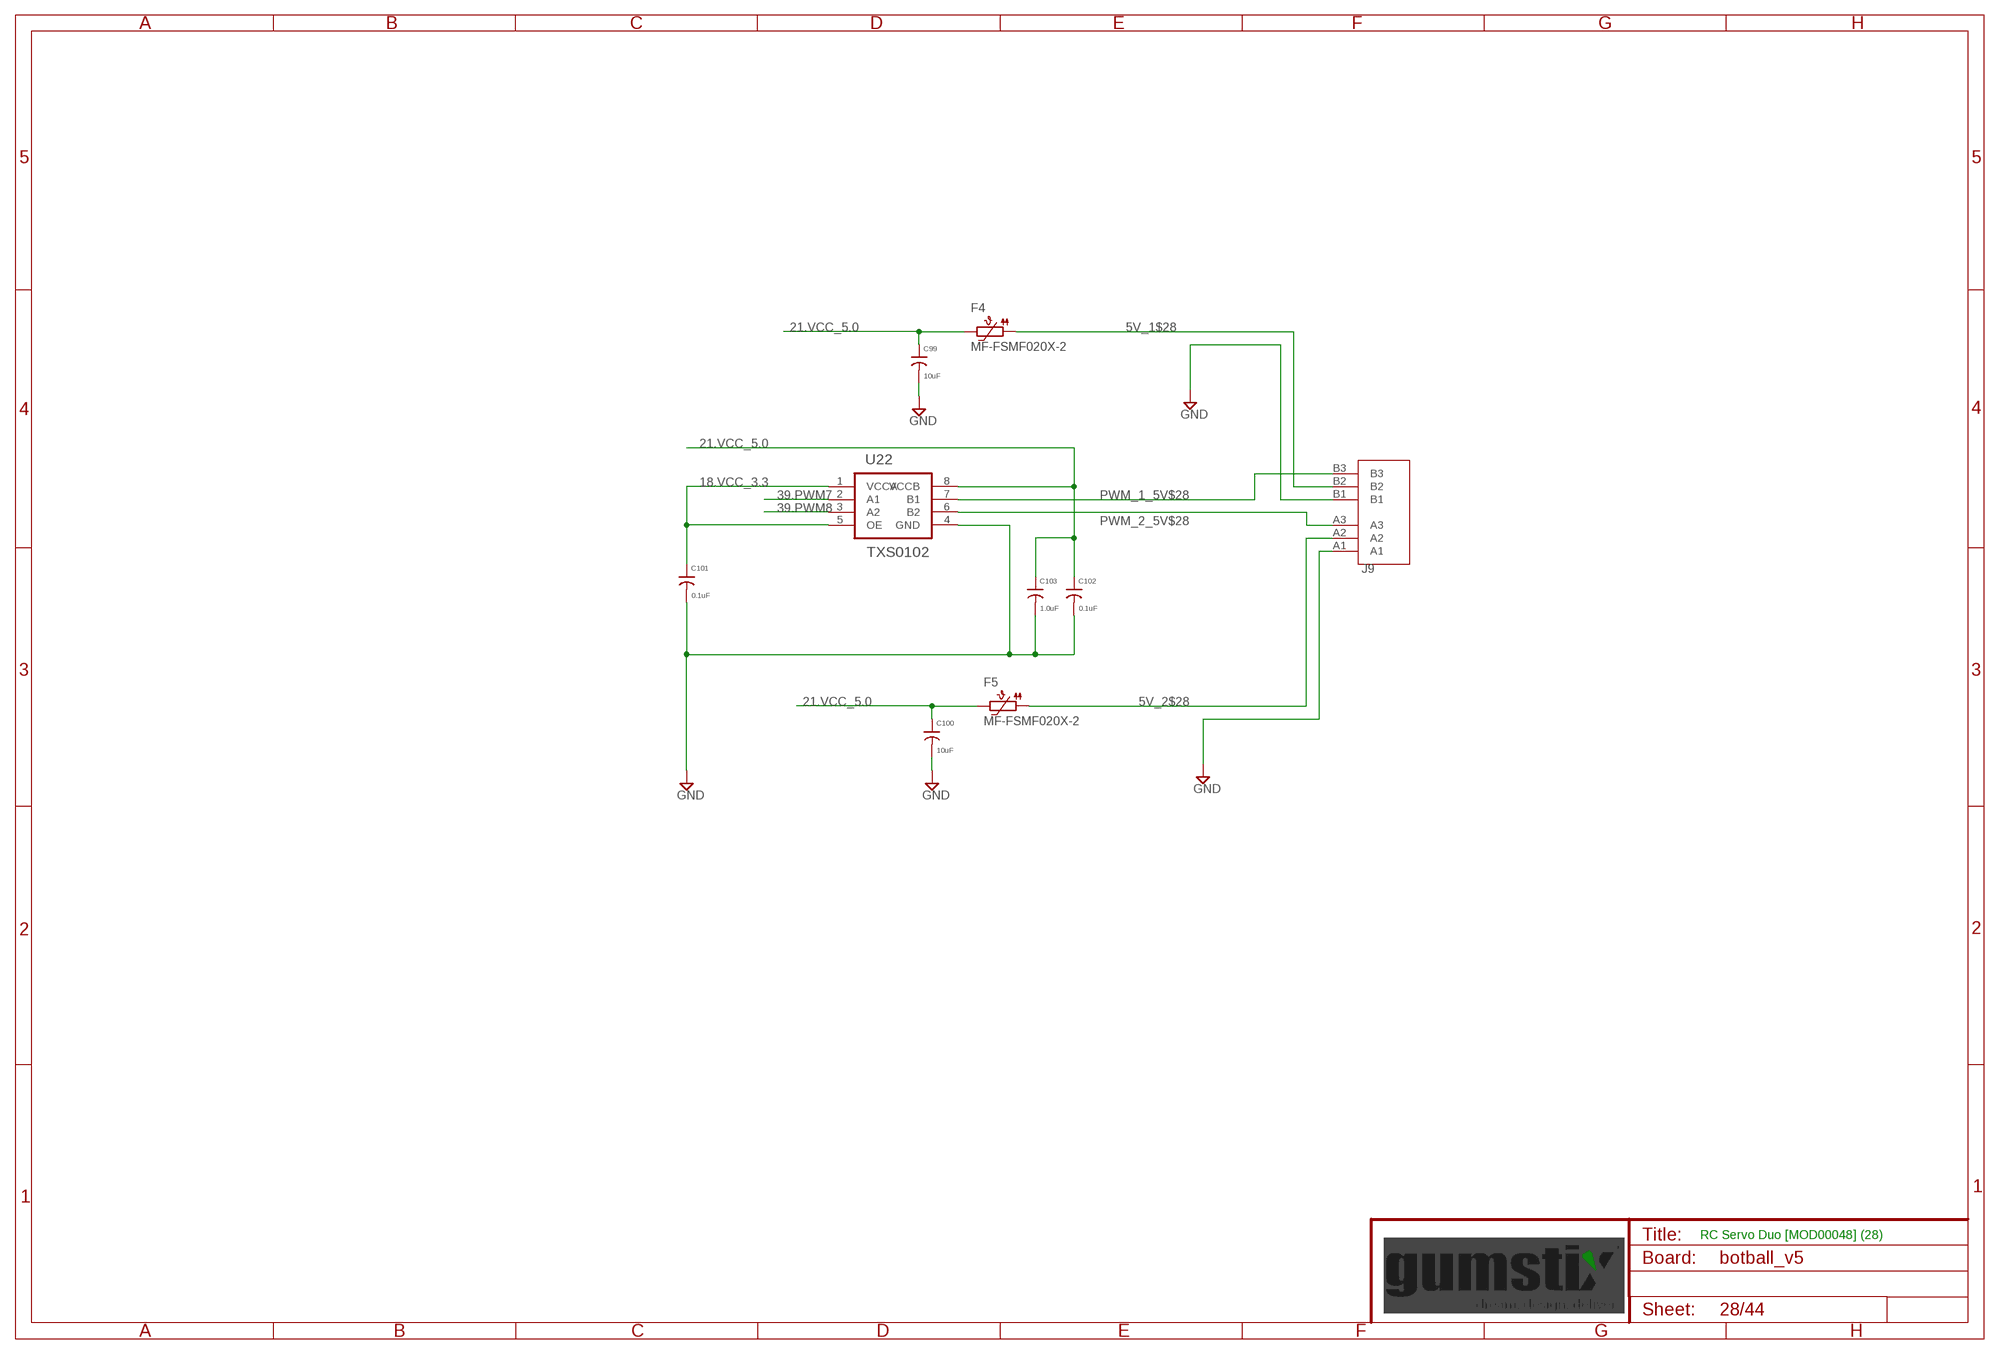
[diagram p27: schematic, sheet 28]
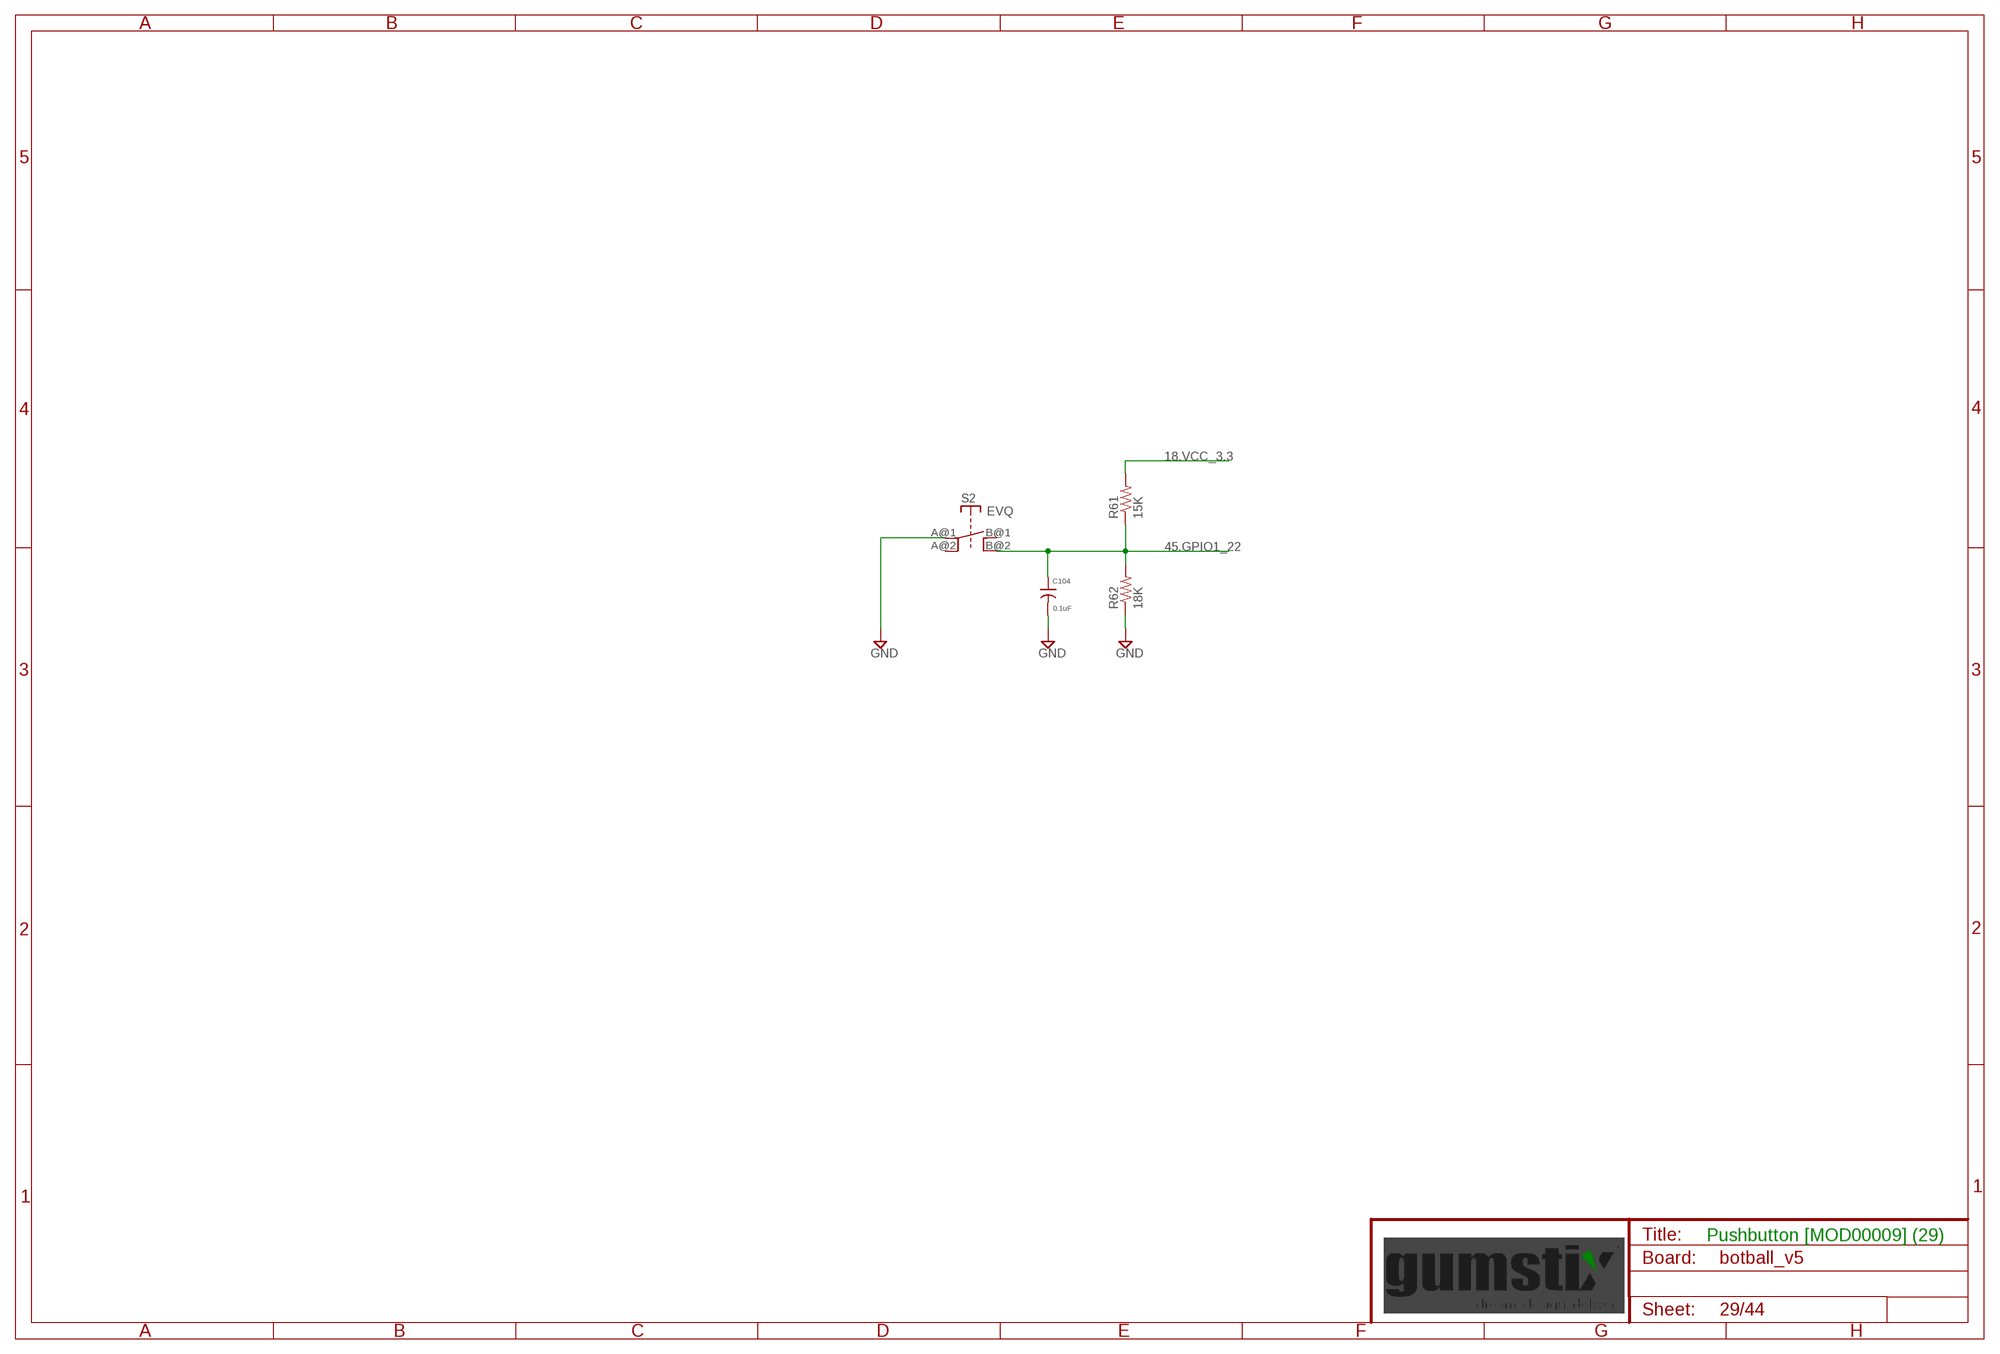
[diagram p28: schematic, sheet 29]
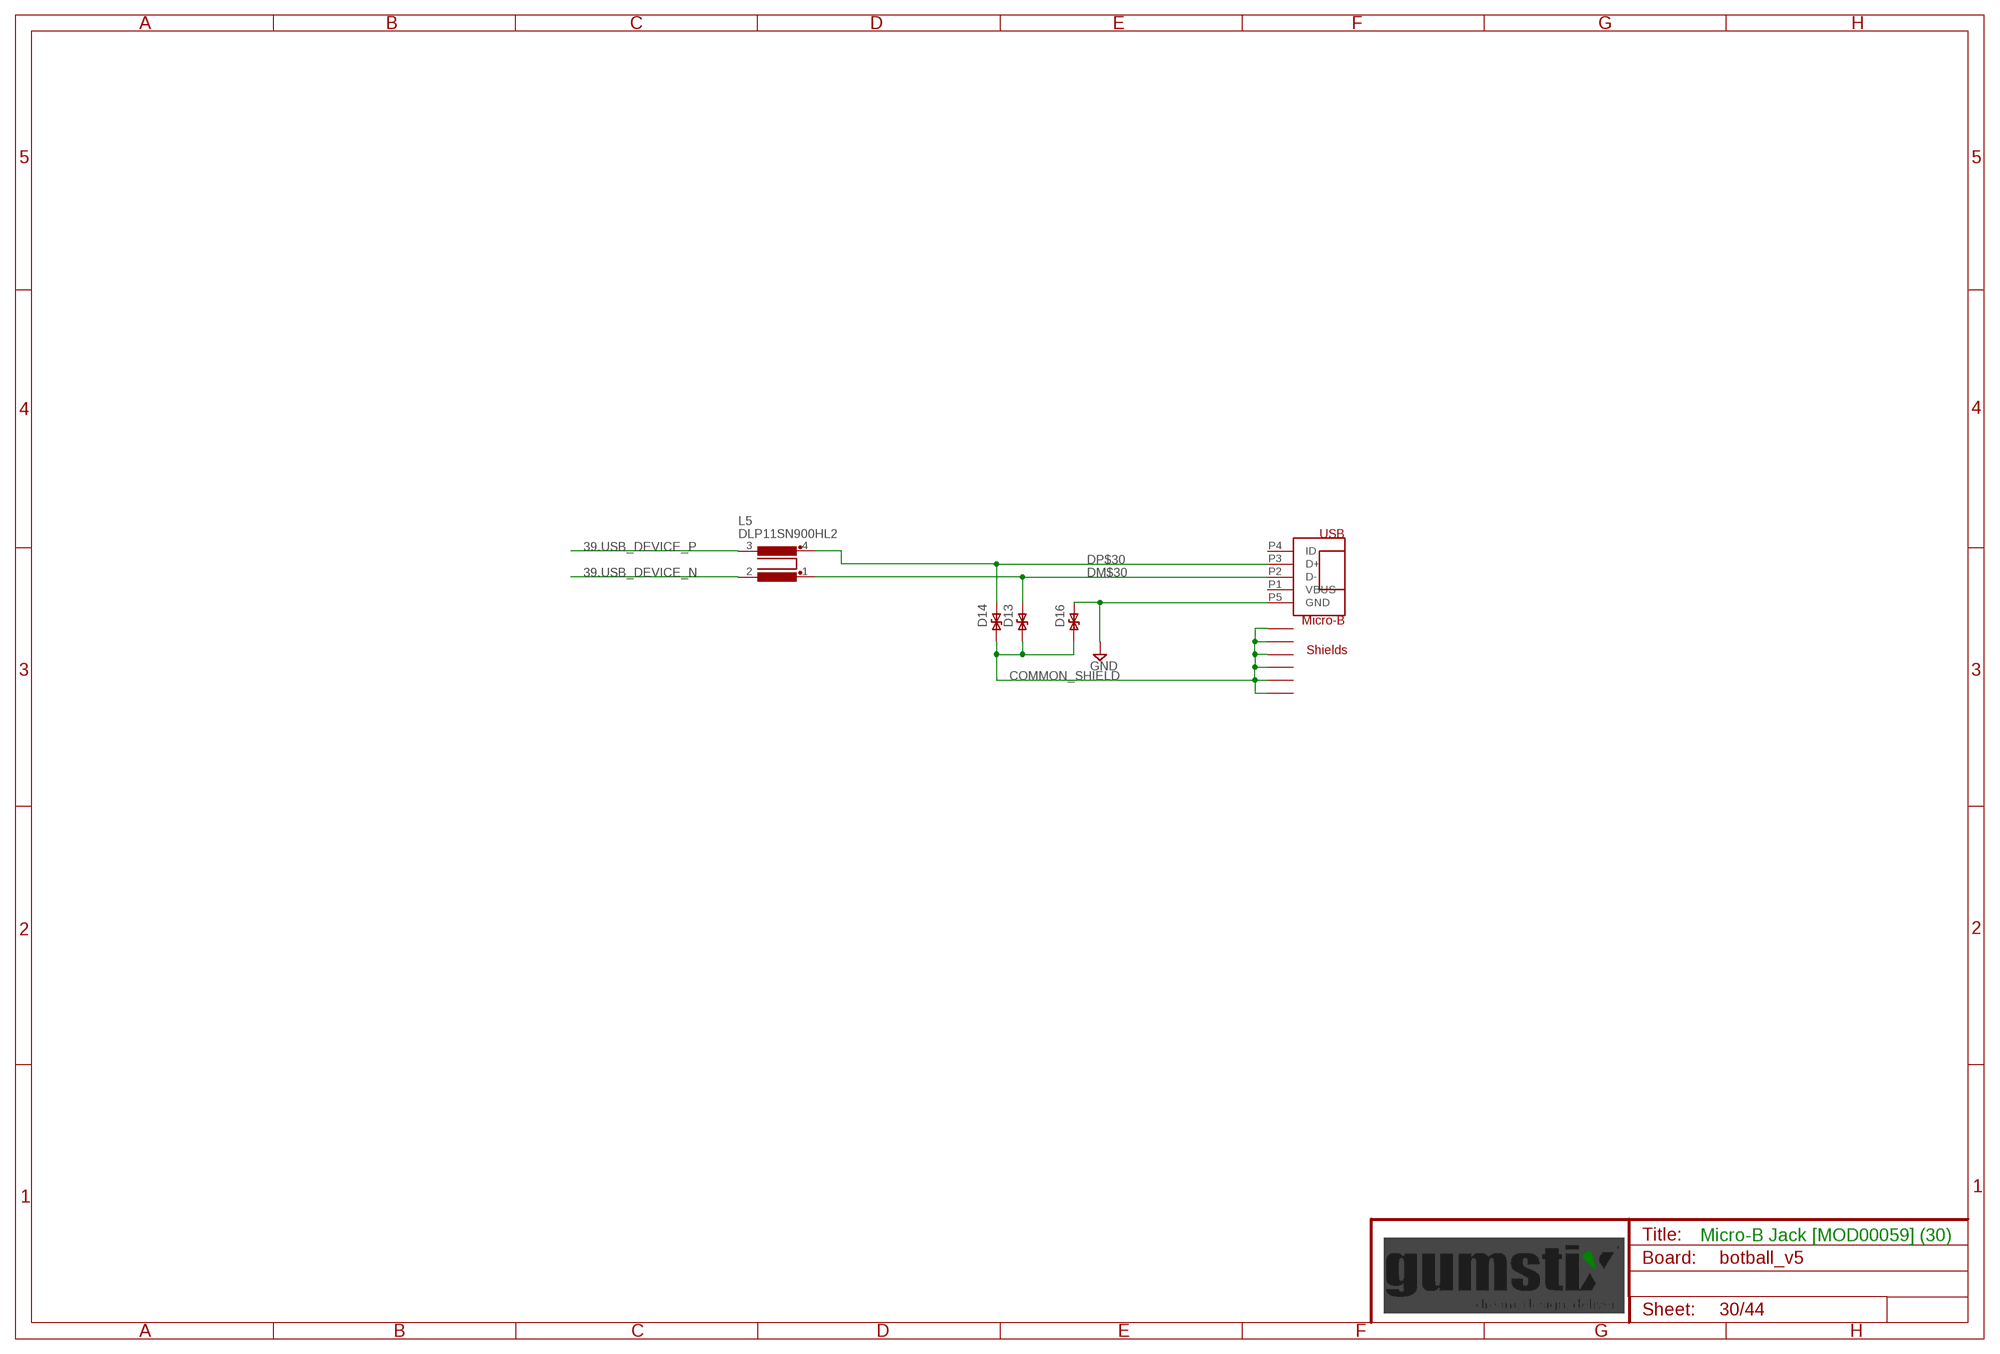
[diagram p29: schematic, sheet 30]
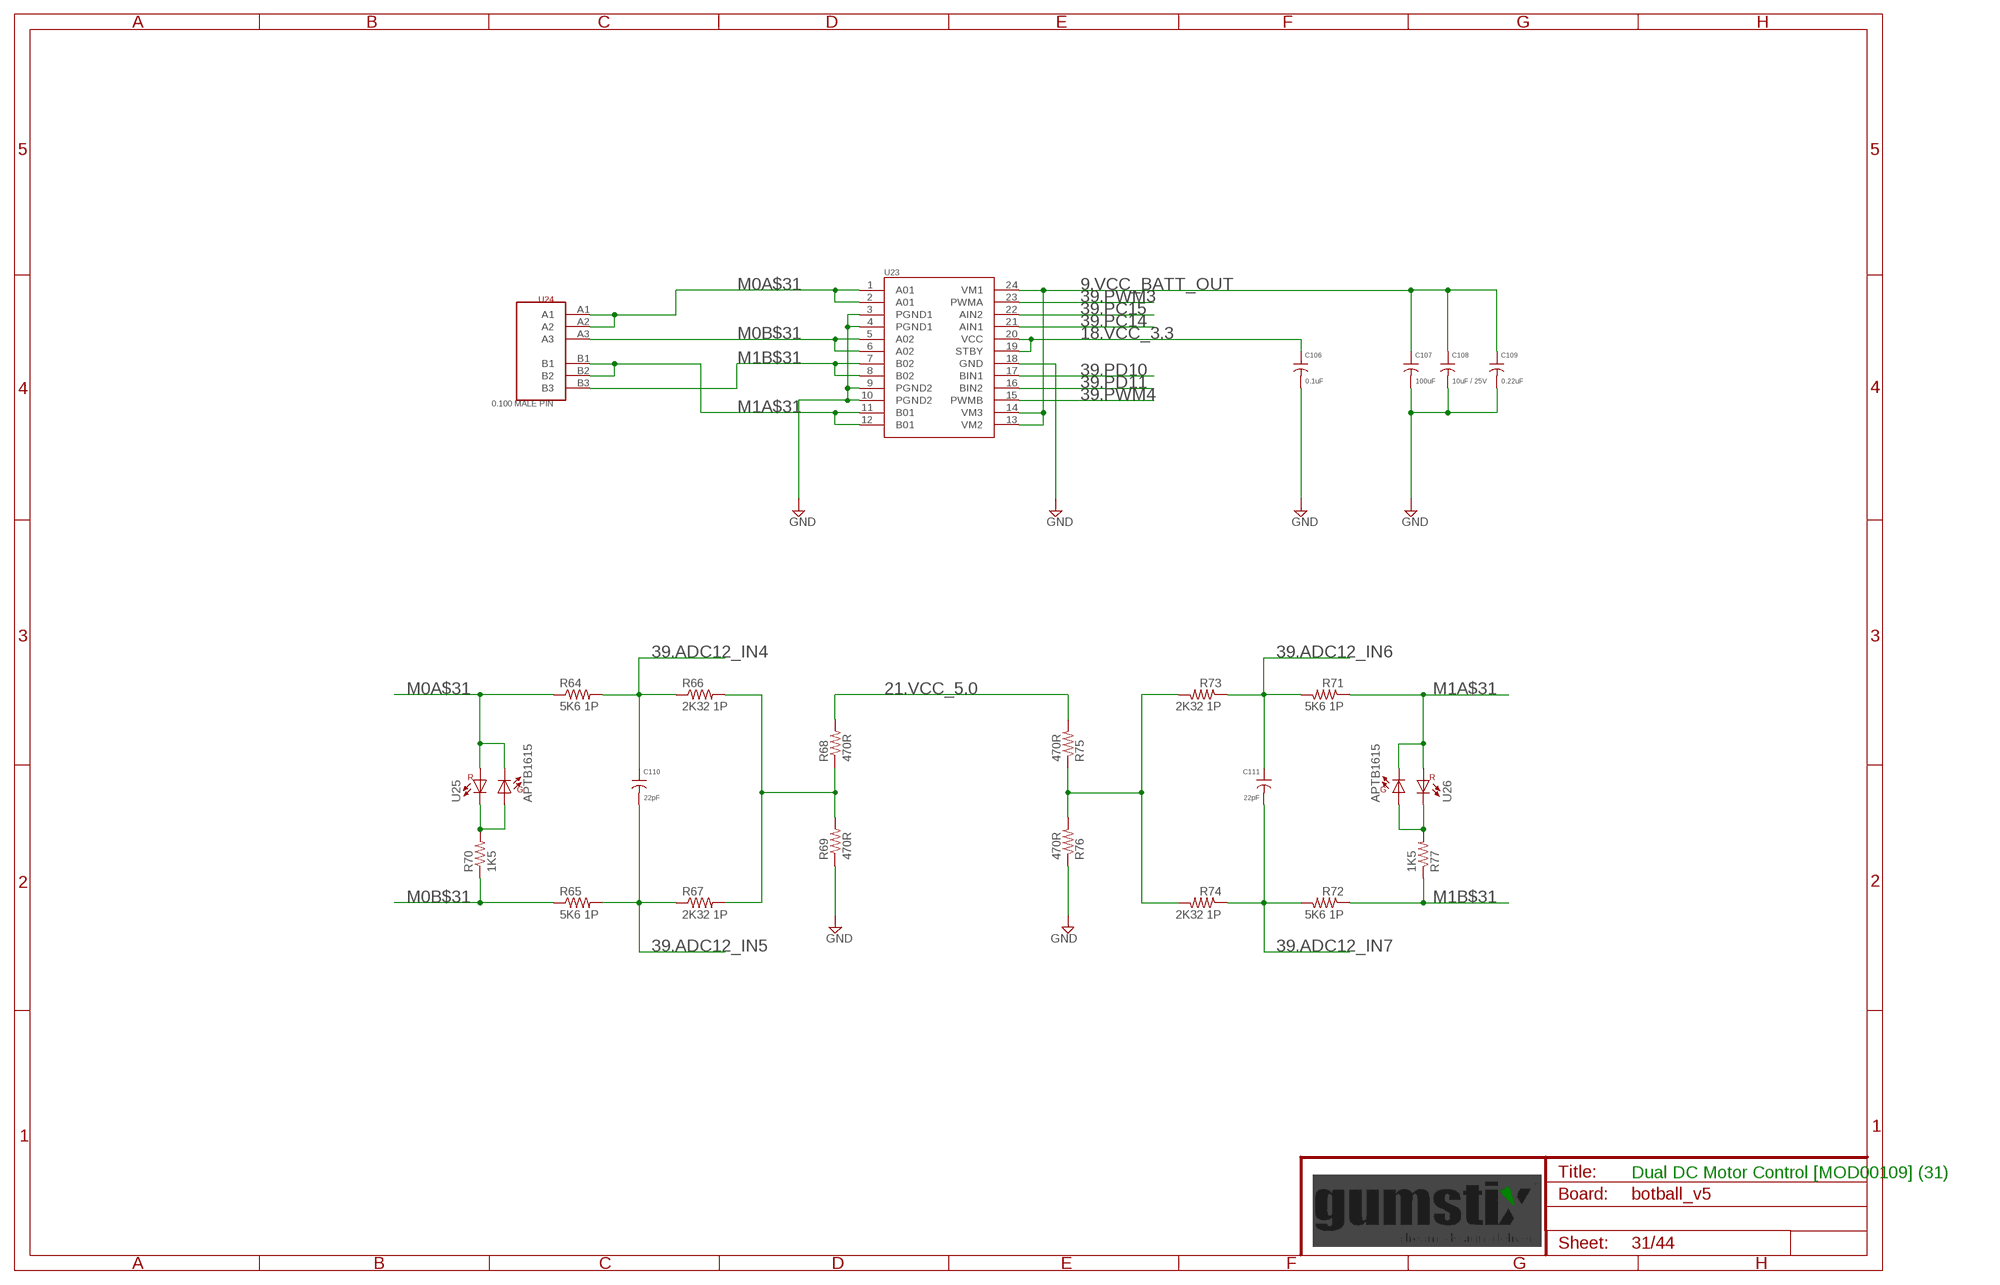
[diagram p30: schematic, sheet 31]
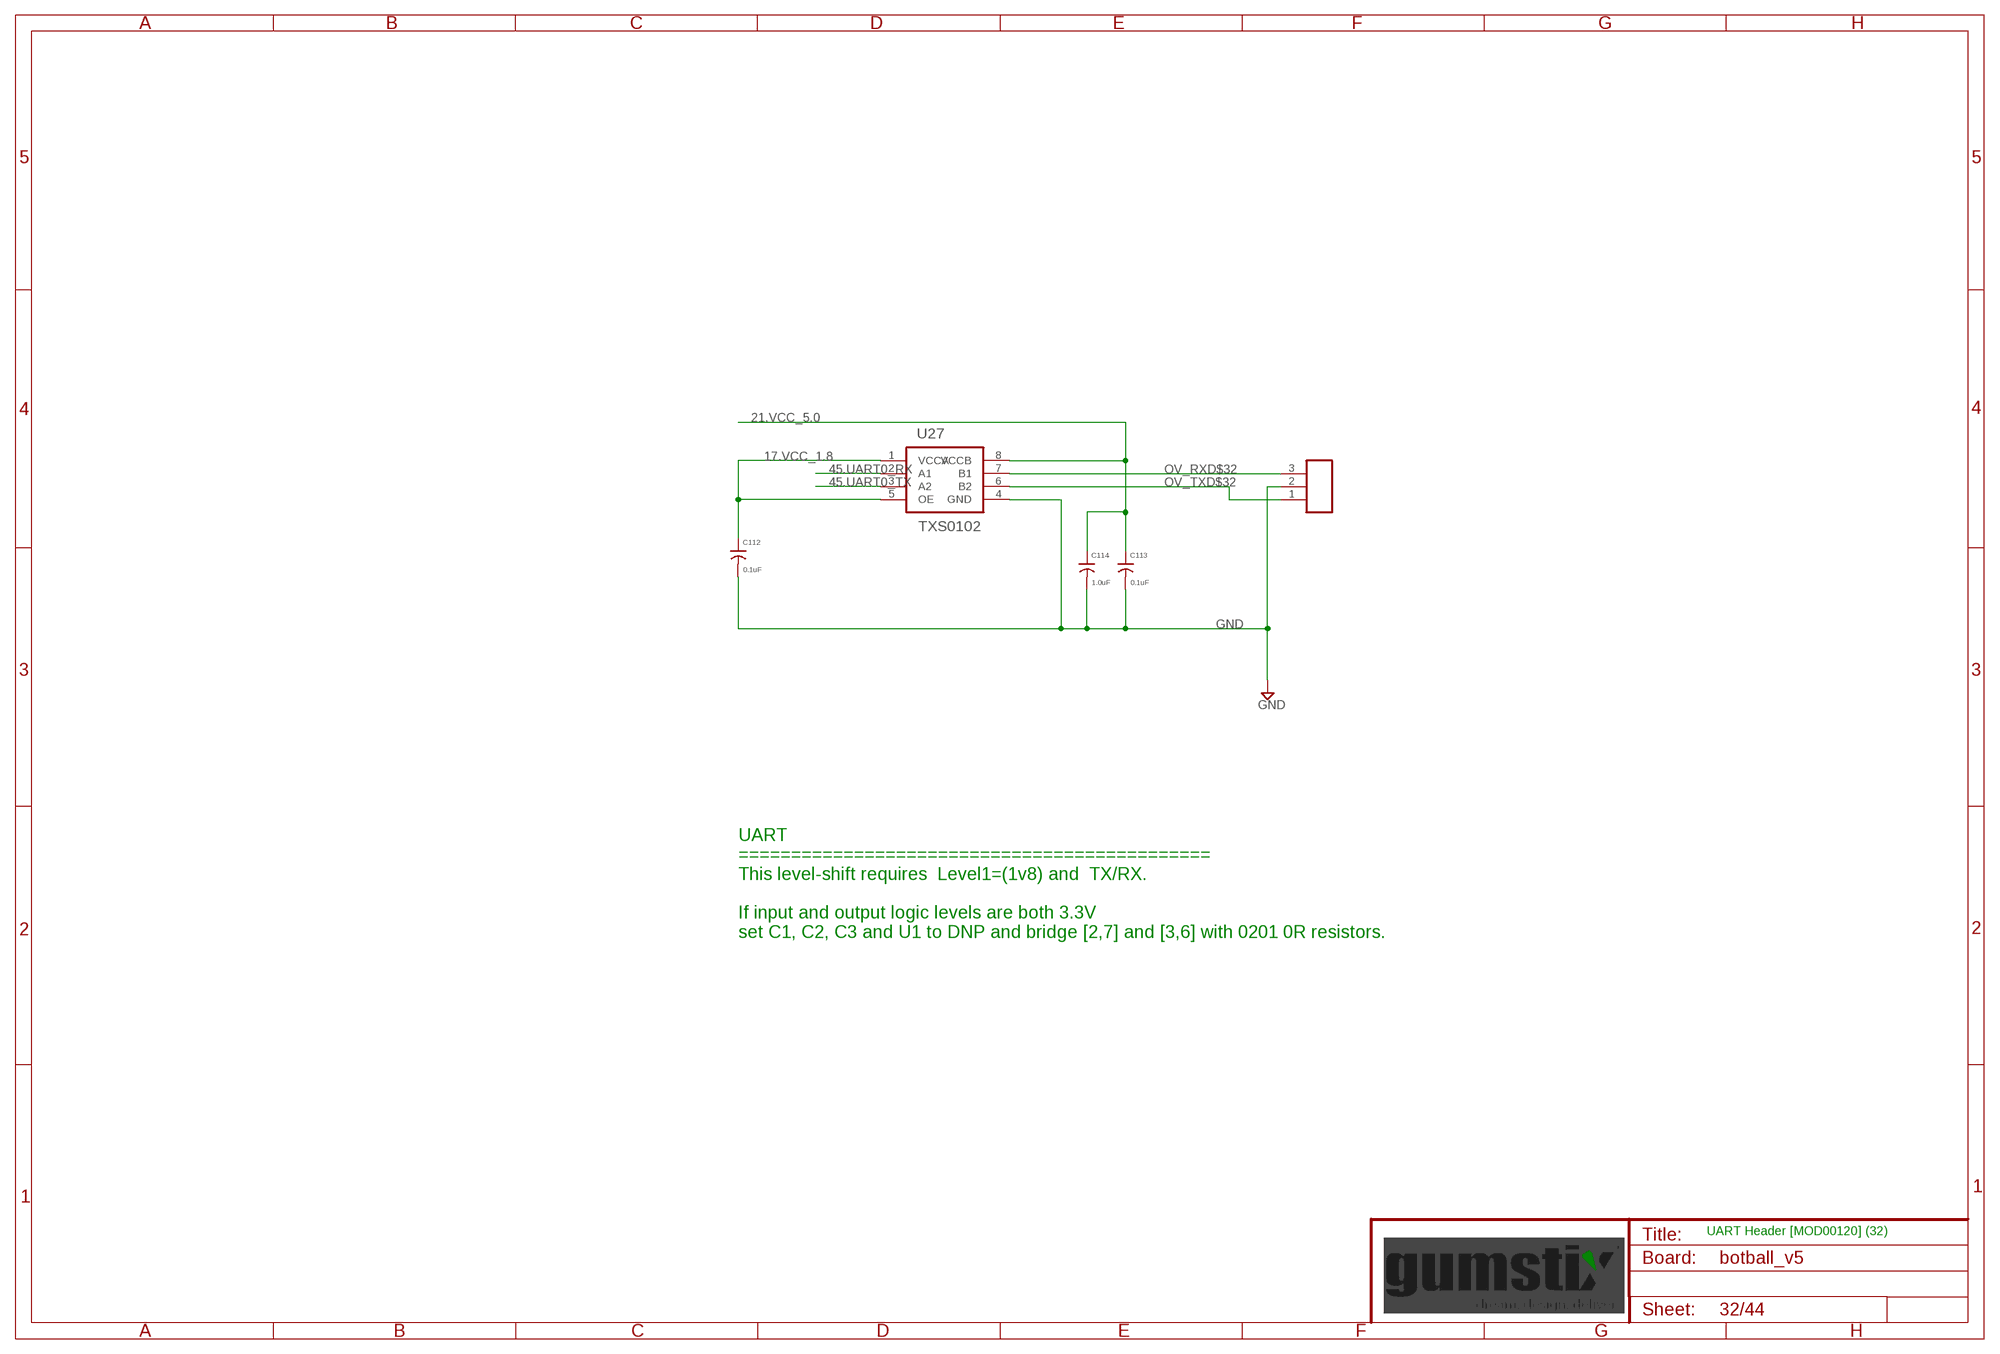
[diagram p31: schematic, sheet 32]
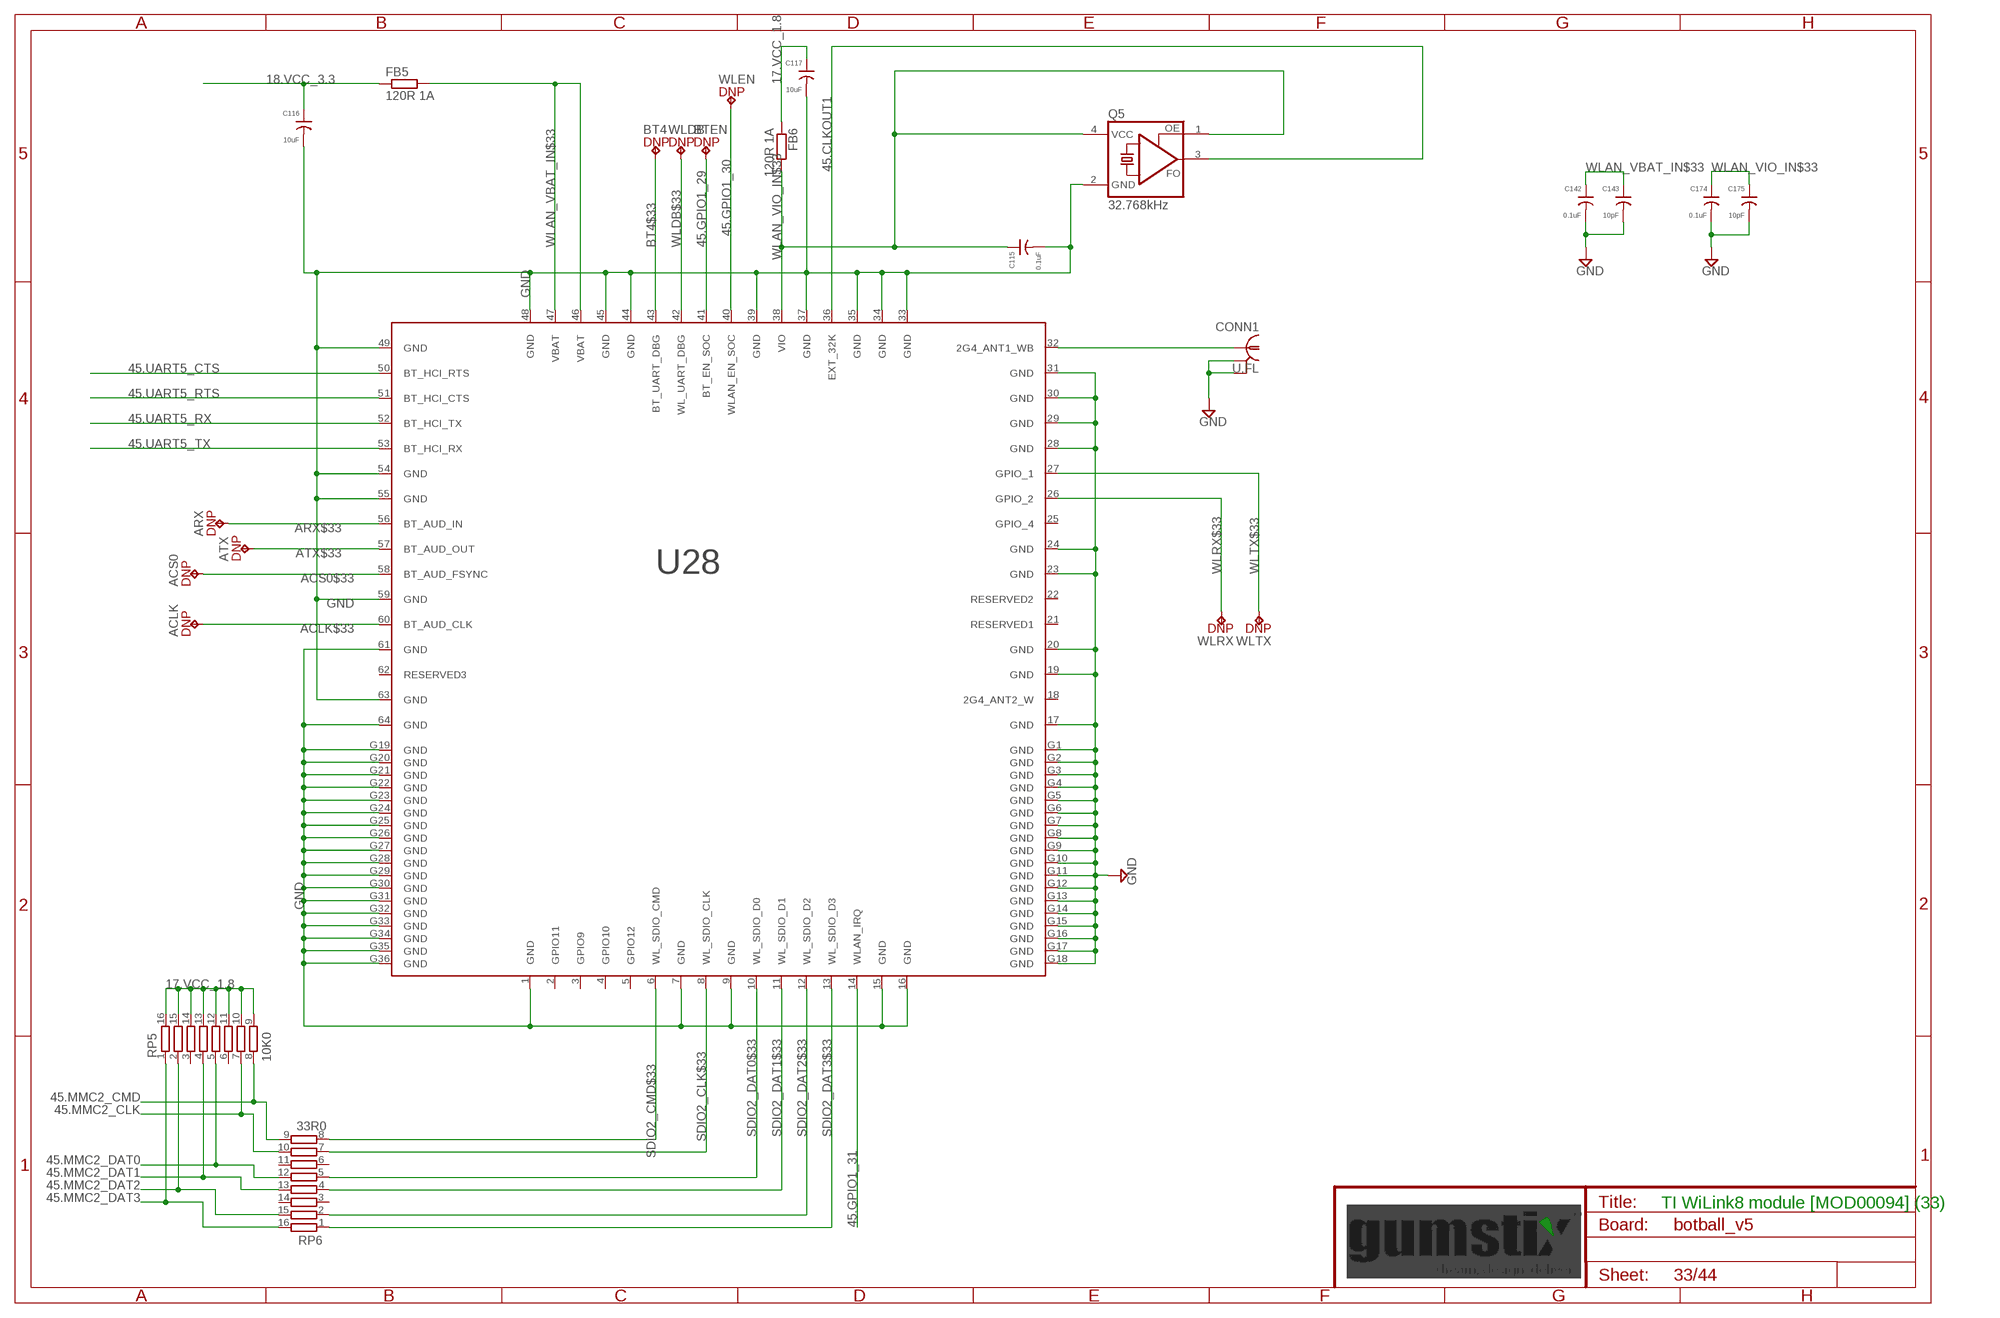
[diagram p32: schematic, sheet 33]
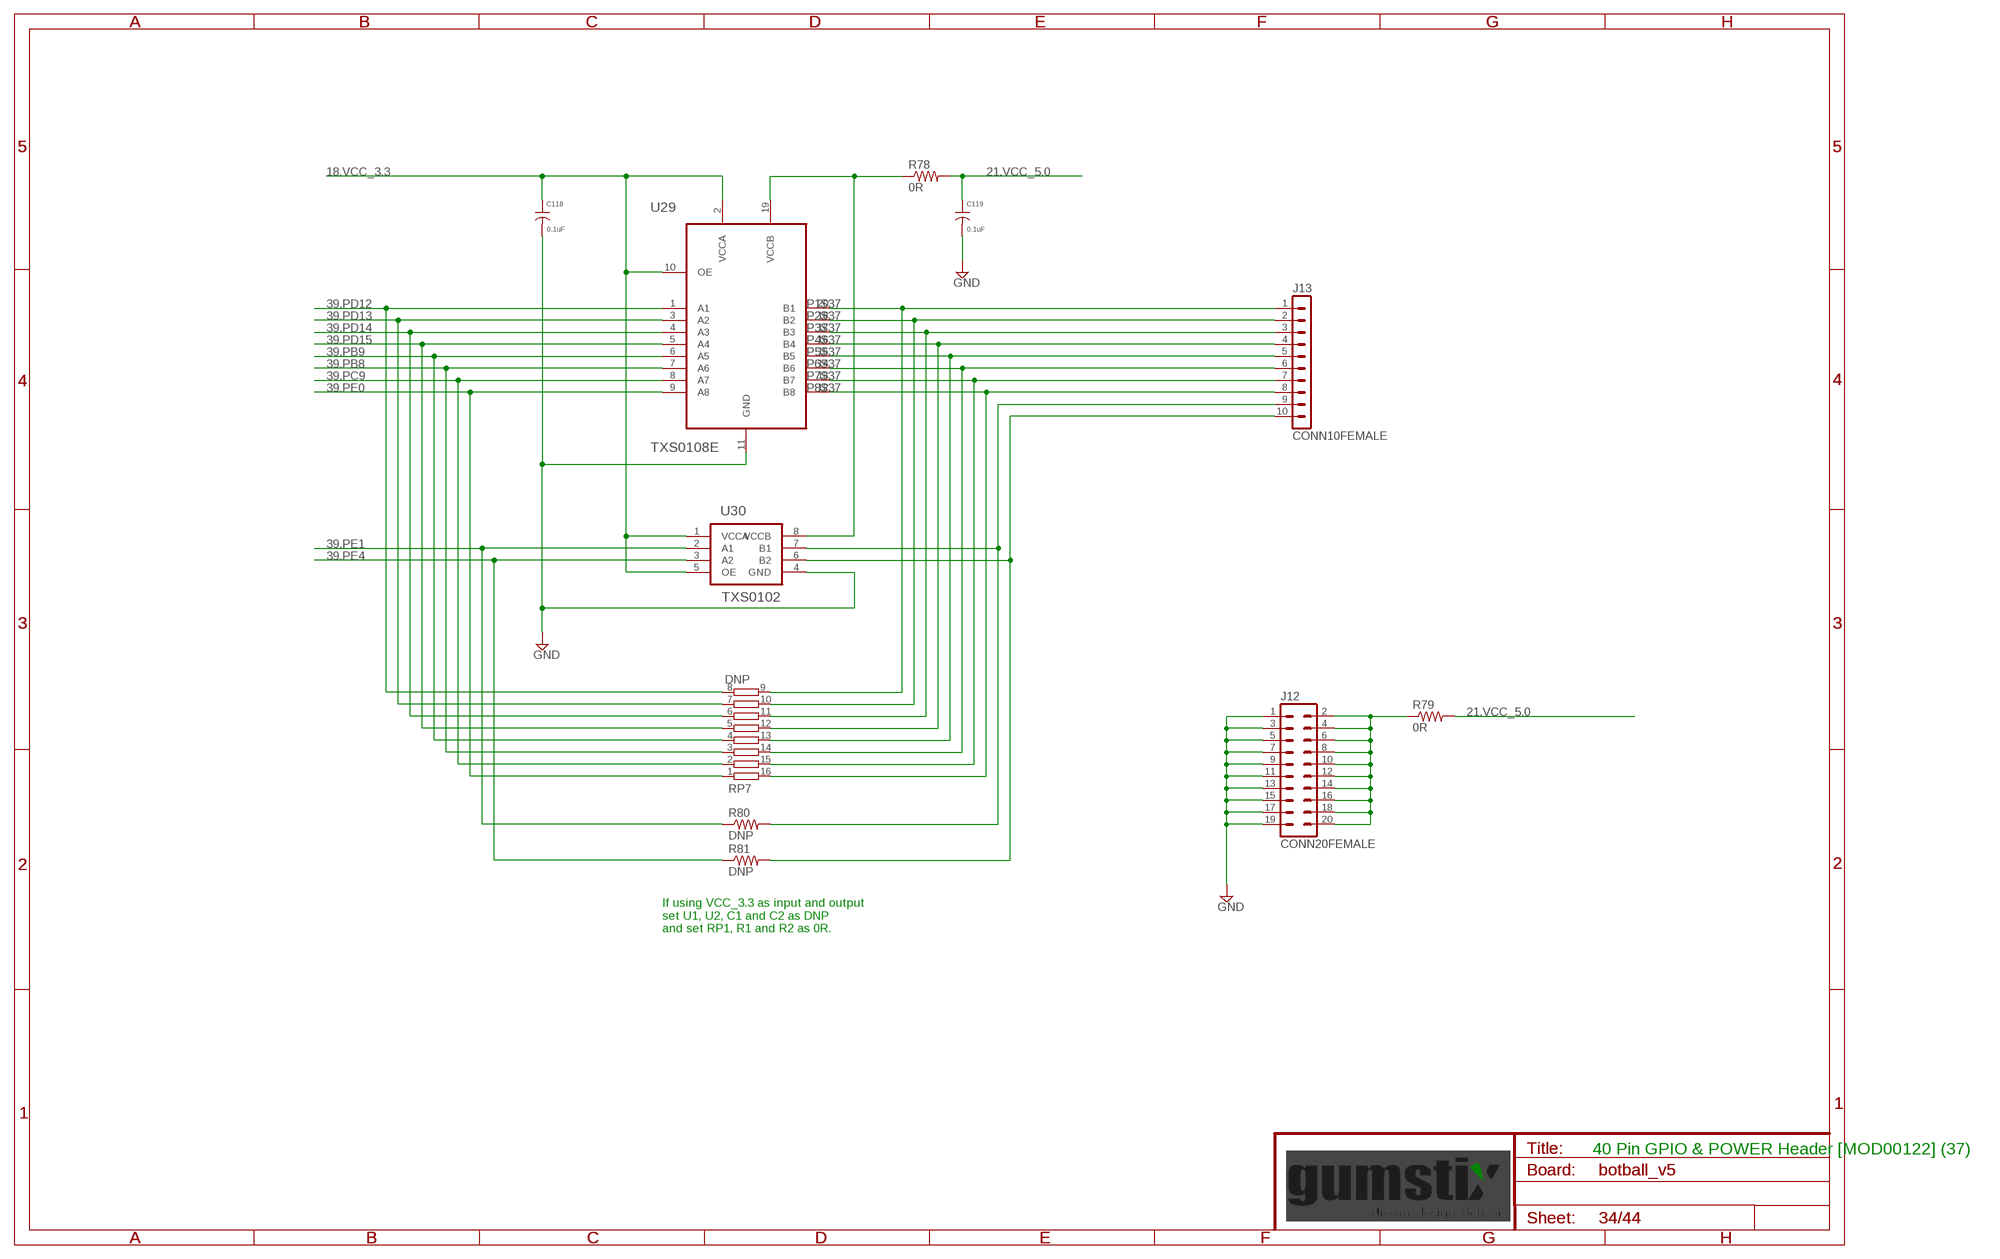
[diagram p33: schematic, sheet 34]
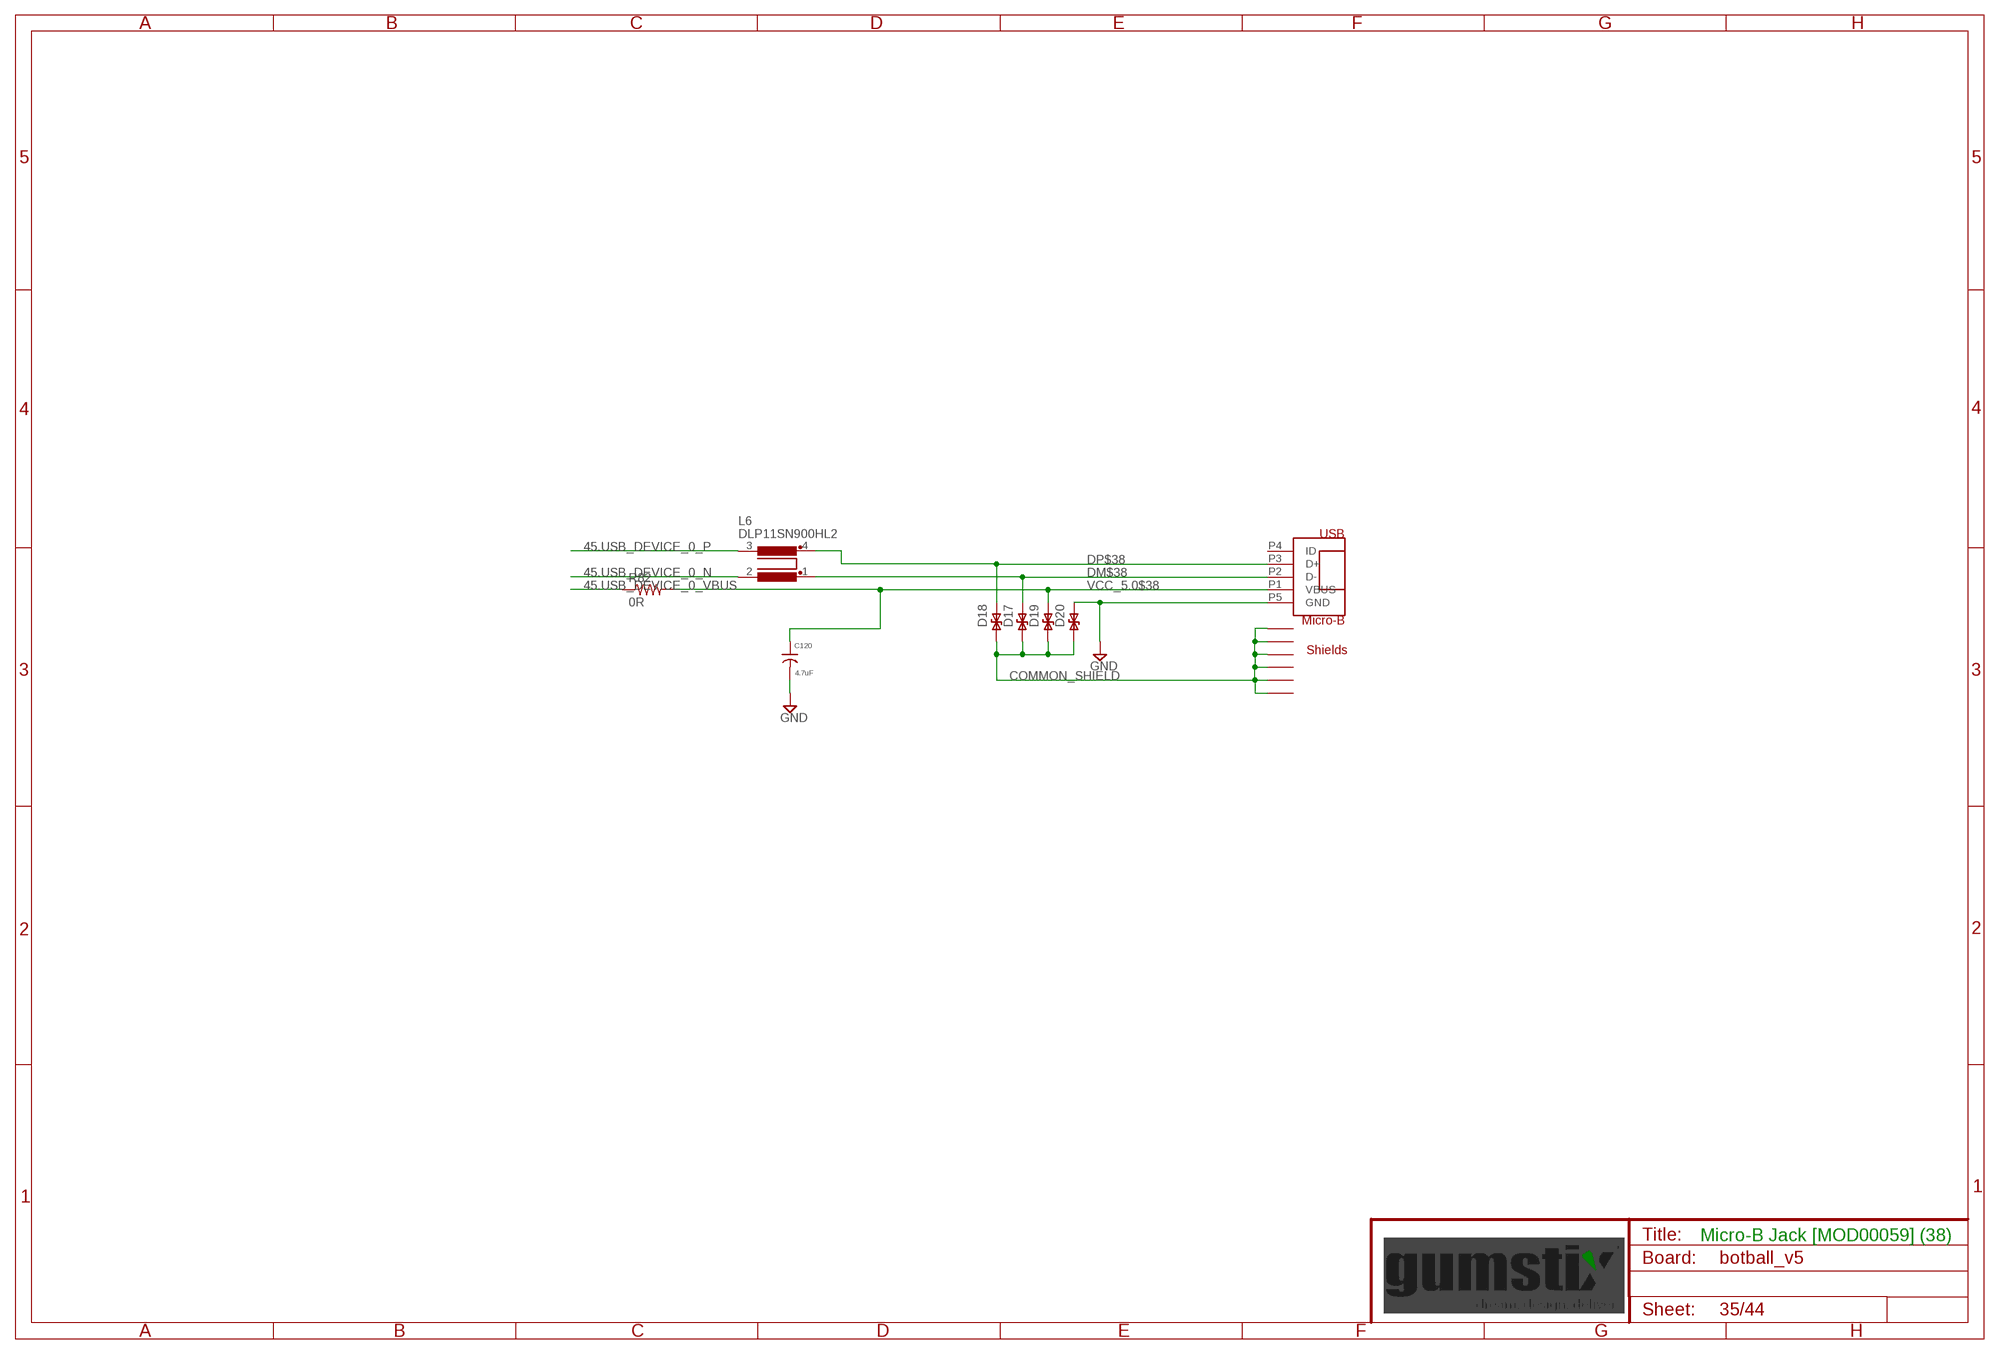
[diagram p34: schematic, sheet 35]
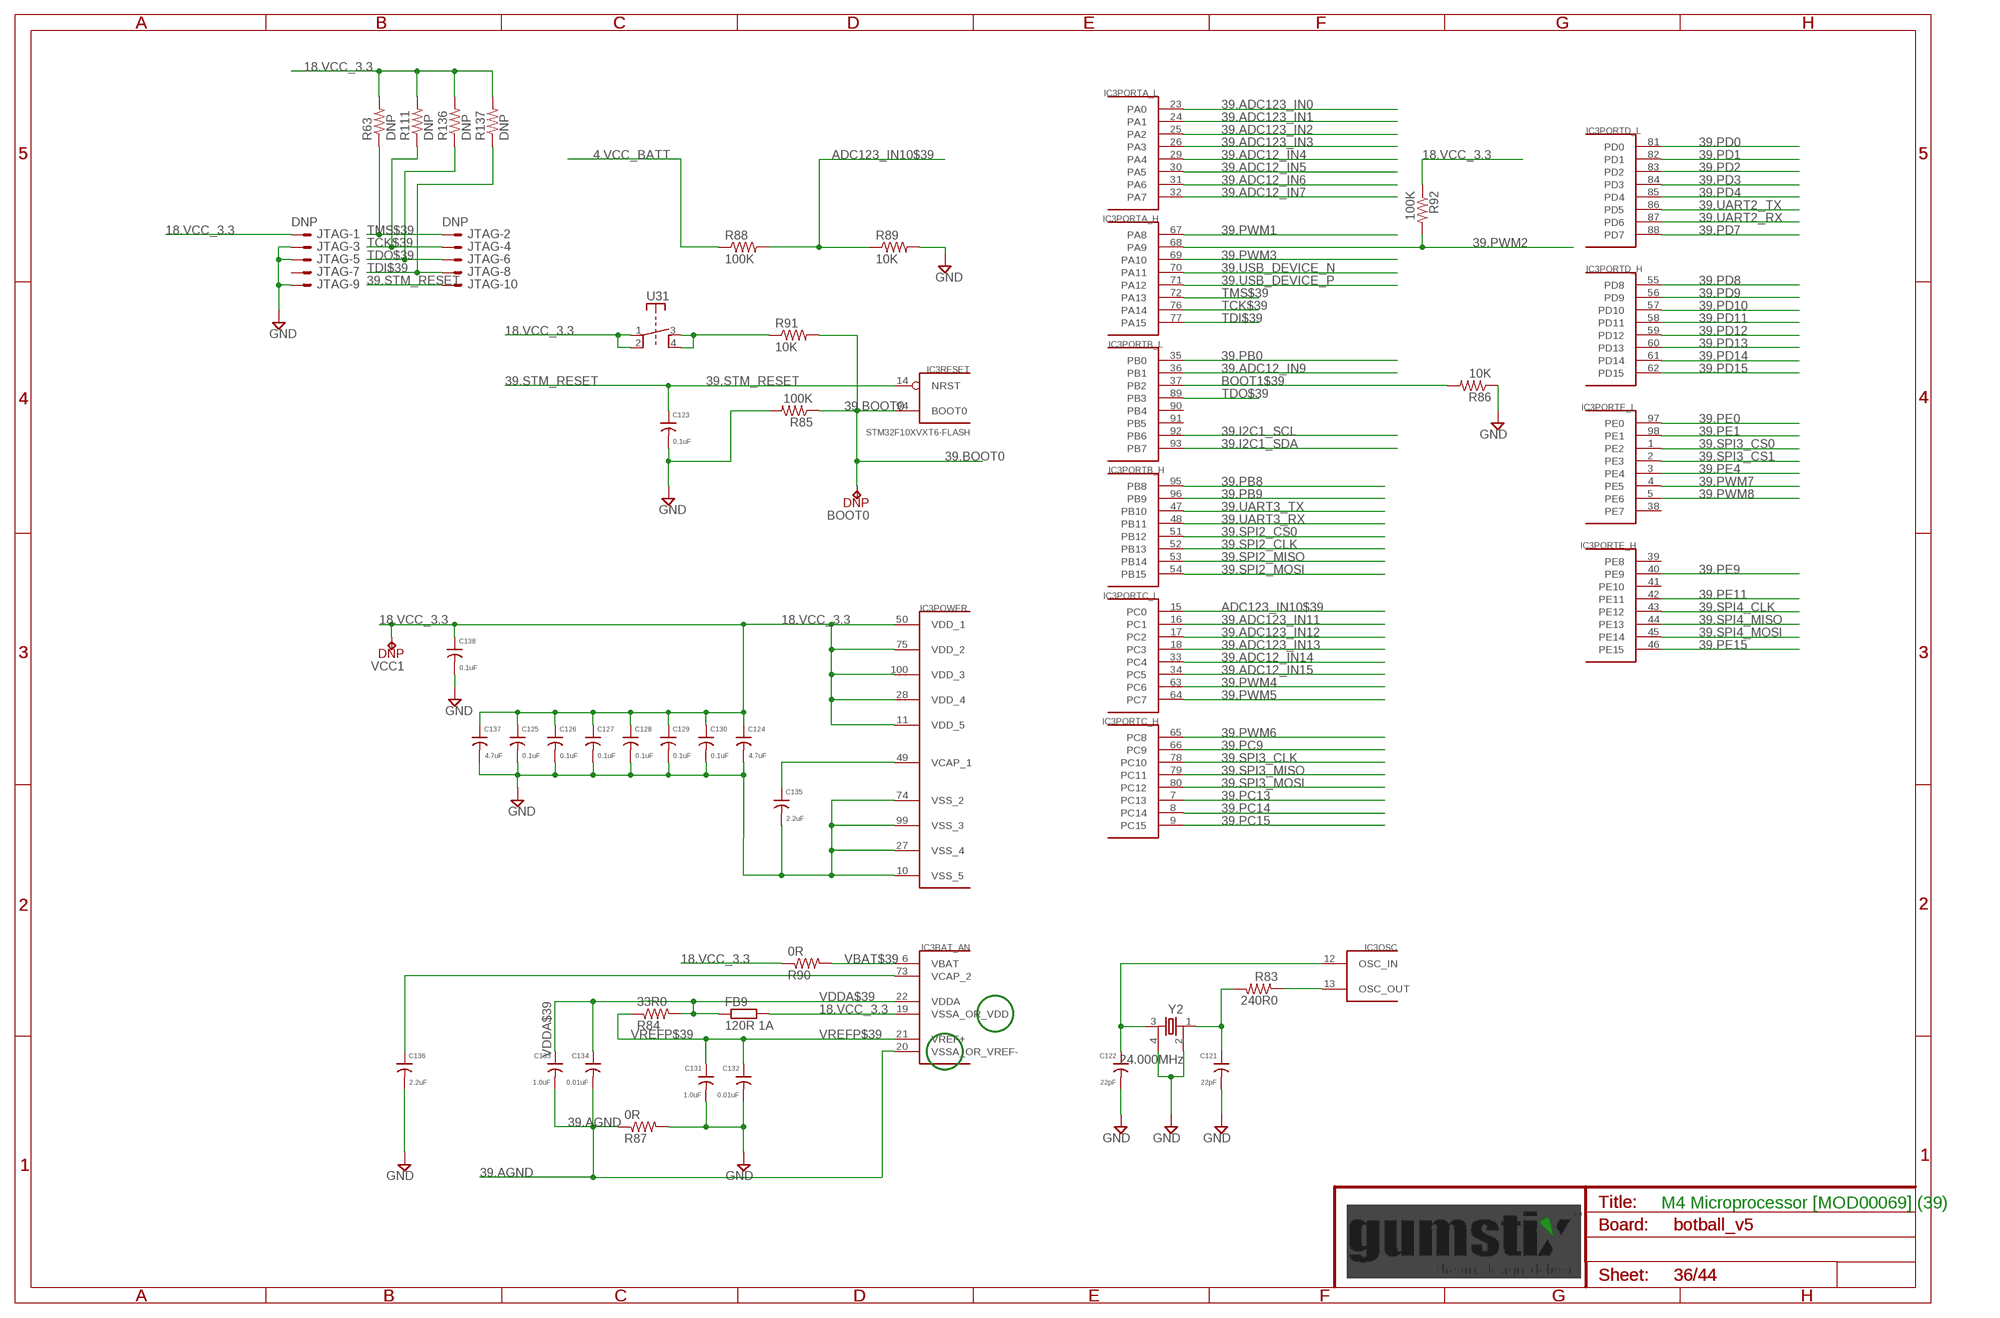
[diagram p35: schematic, sheet 36]
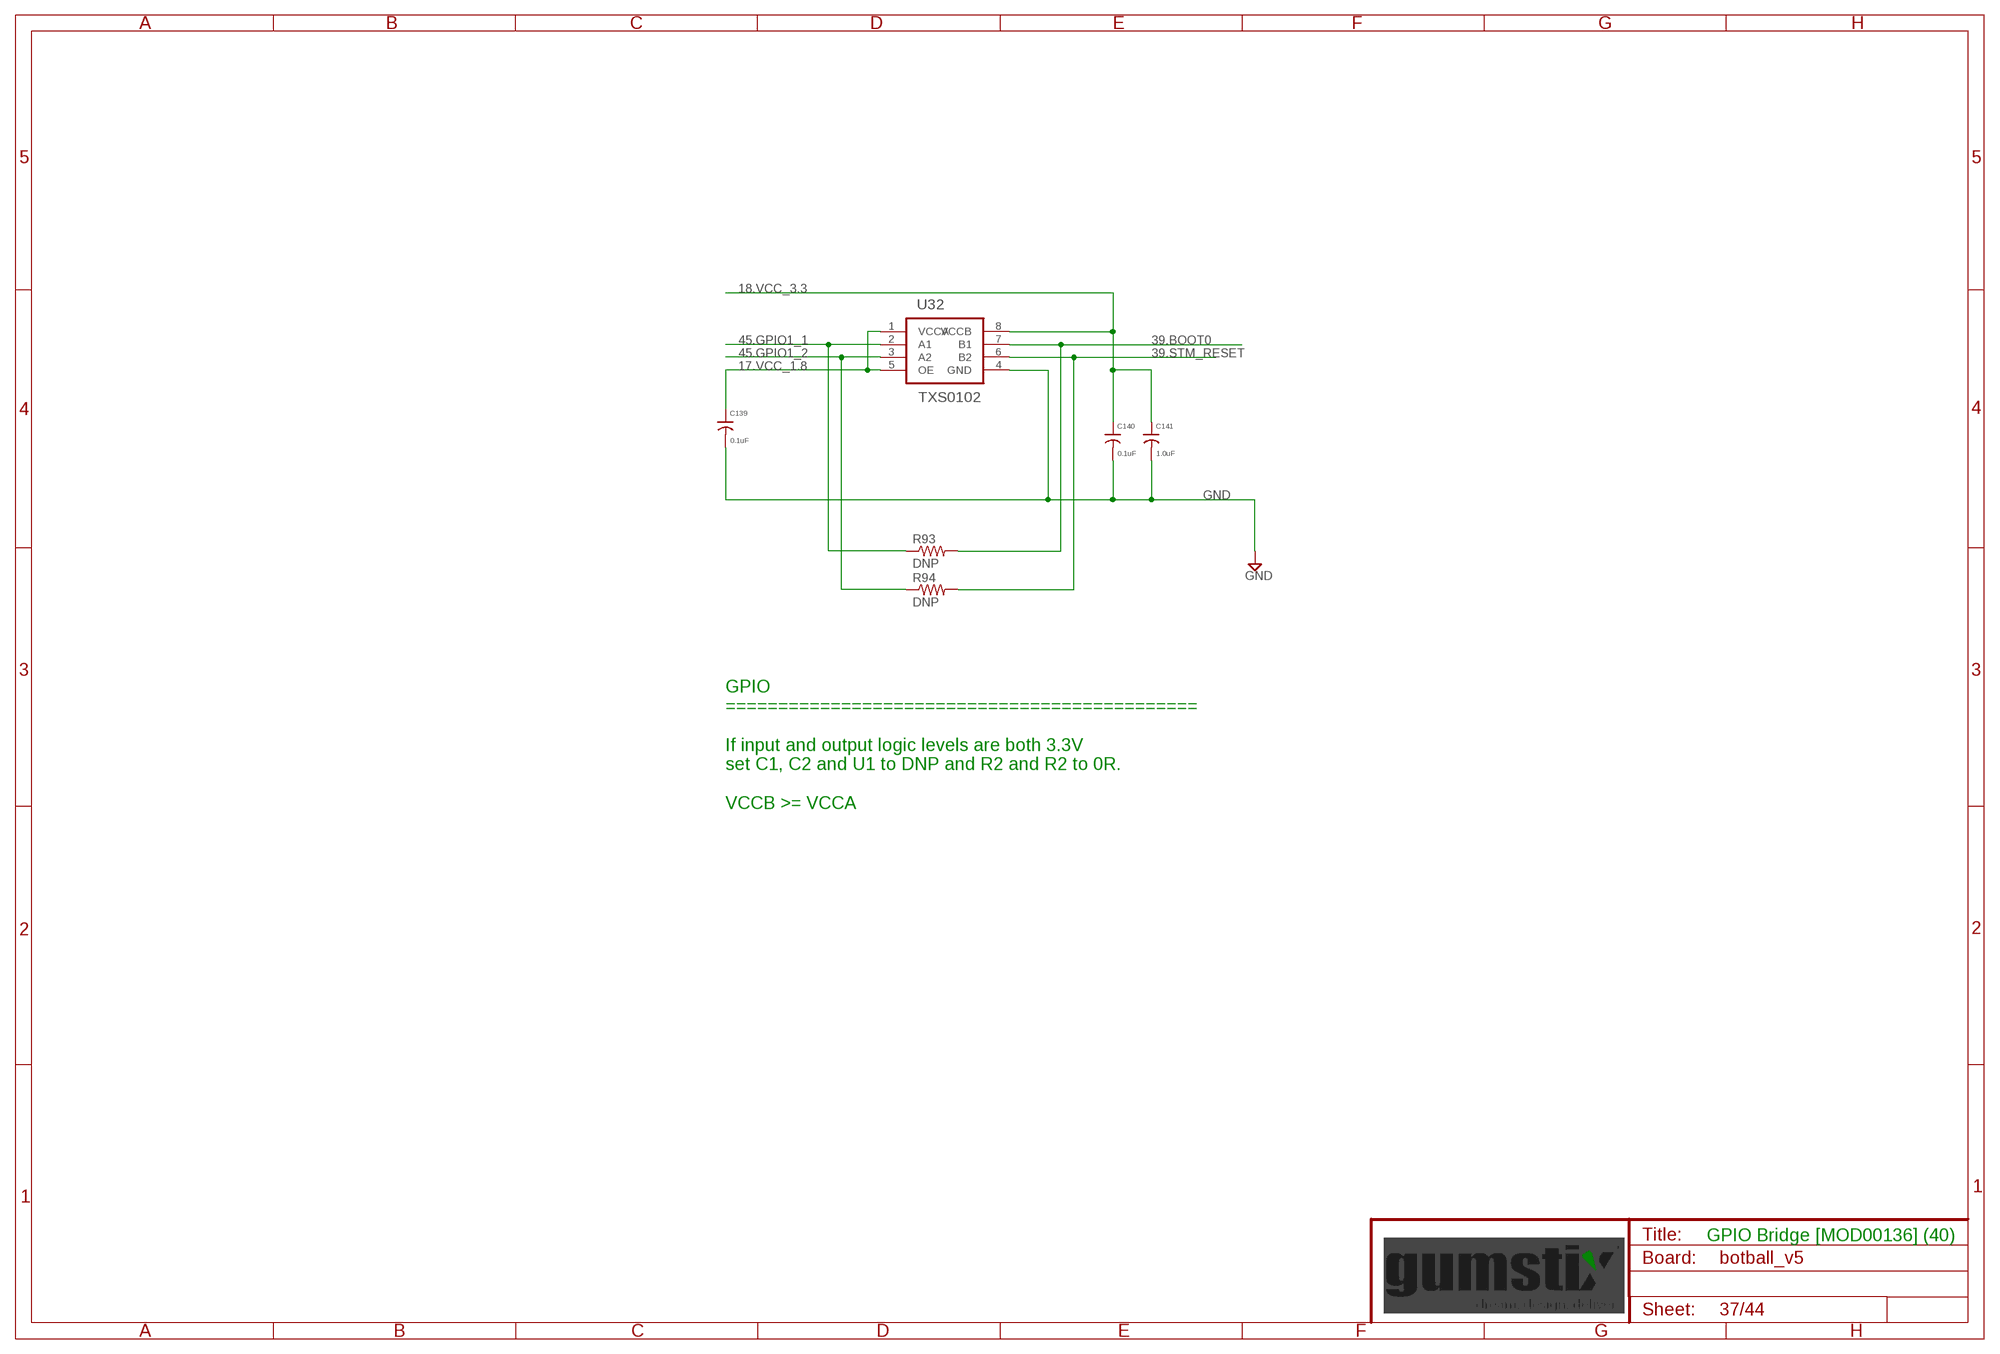
[diagram p36: schematic, sheet 37]
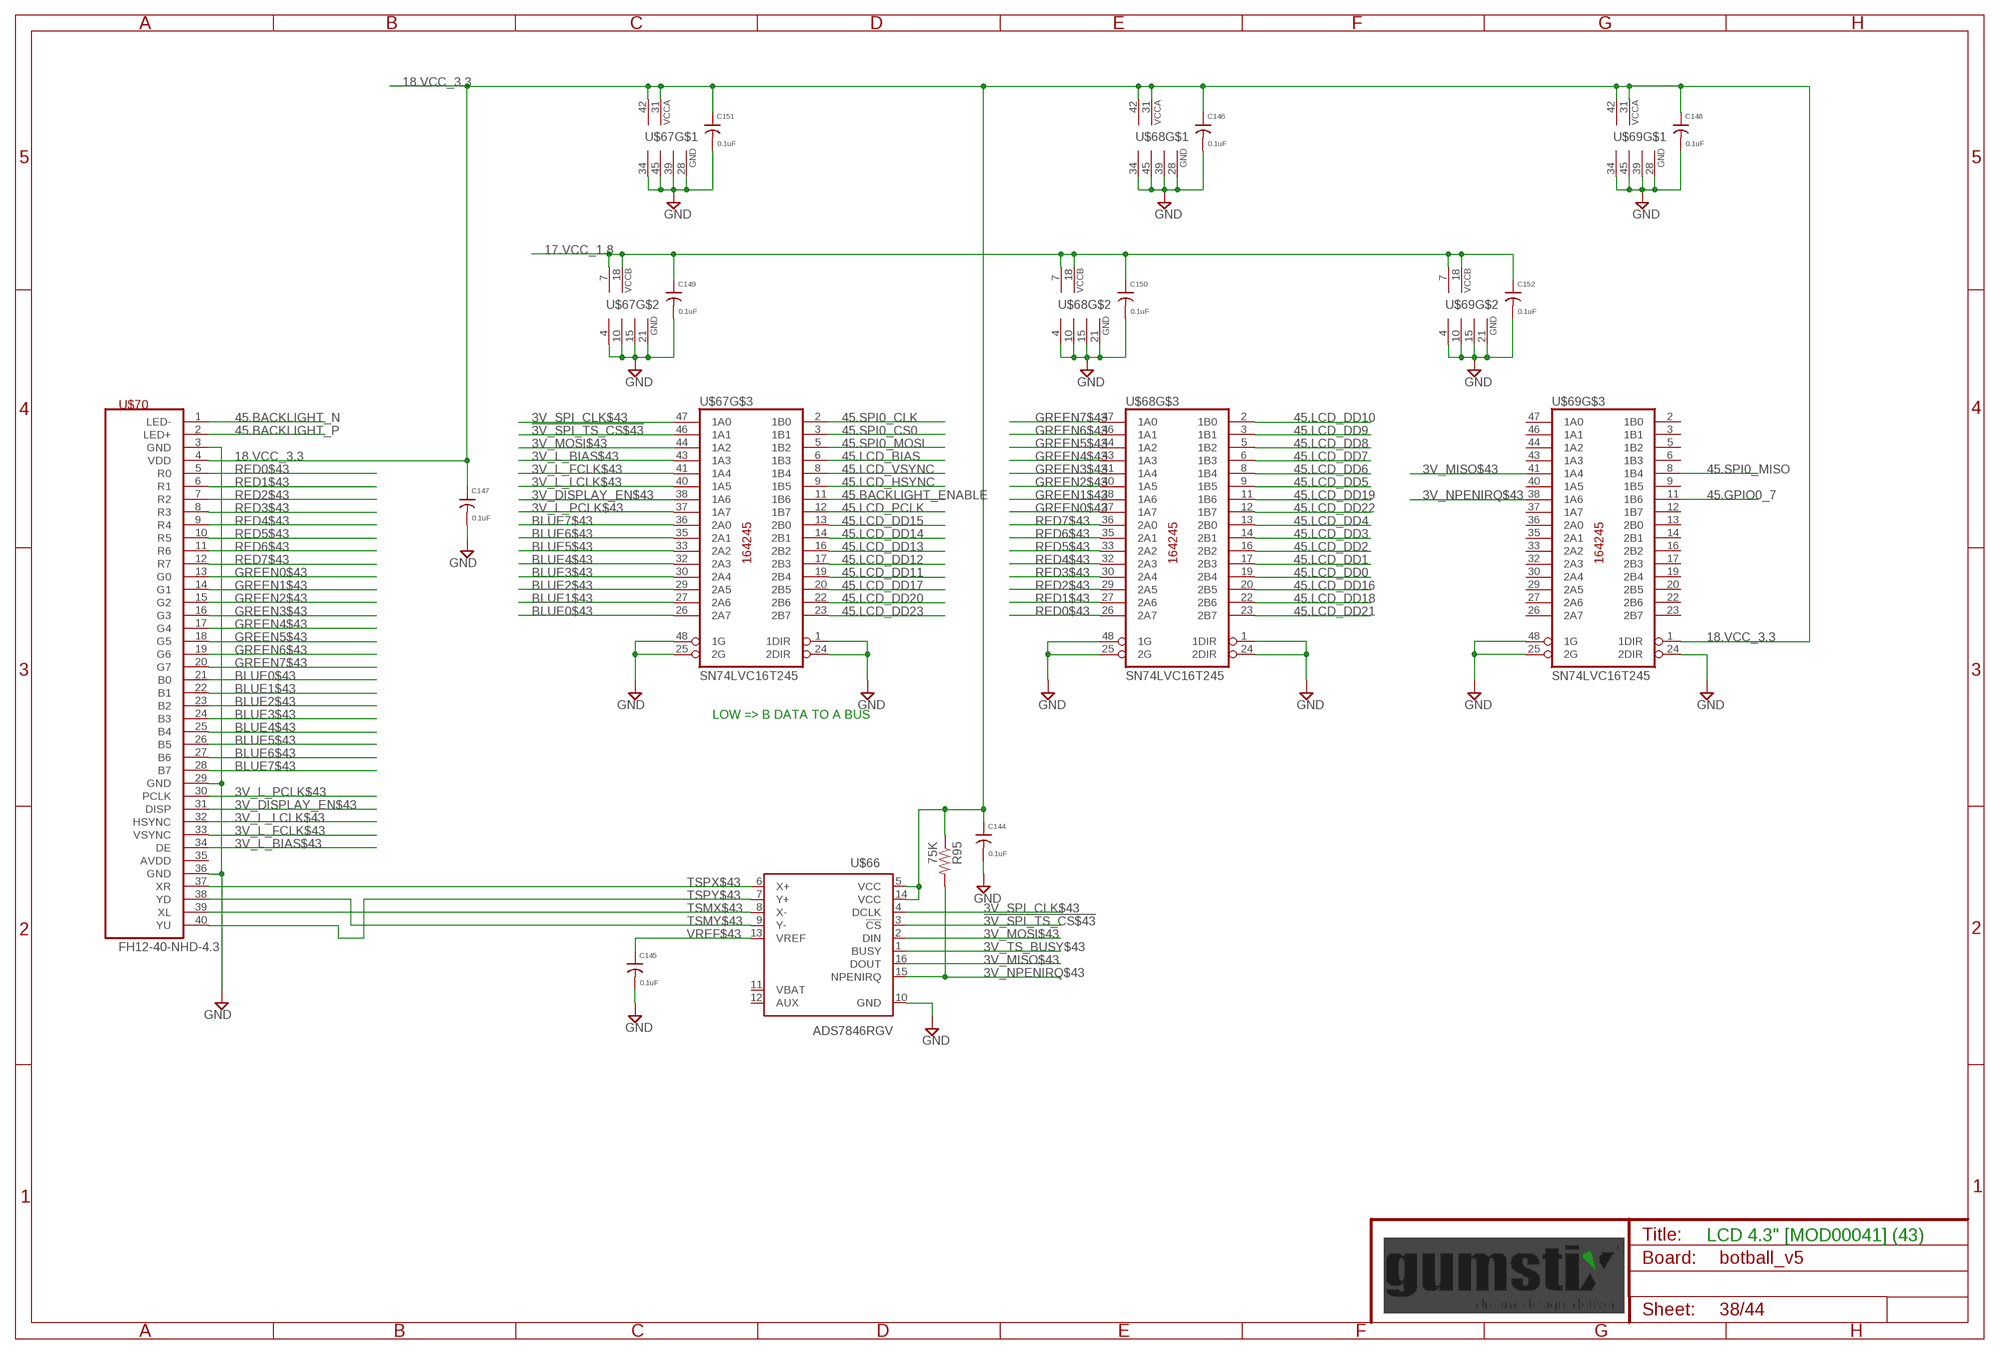
[diagram p37: schematic, sheet 38]
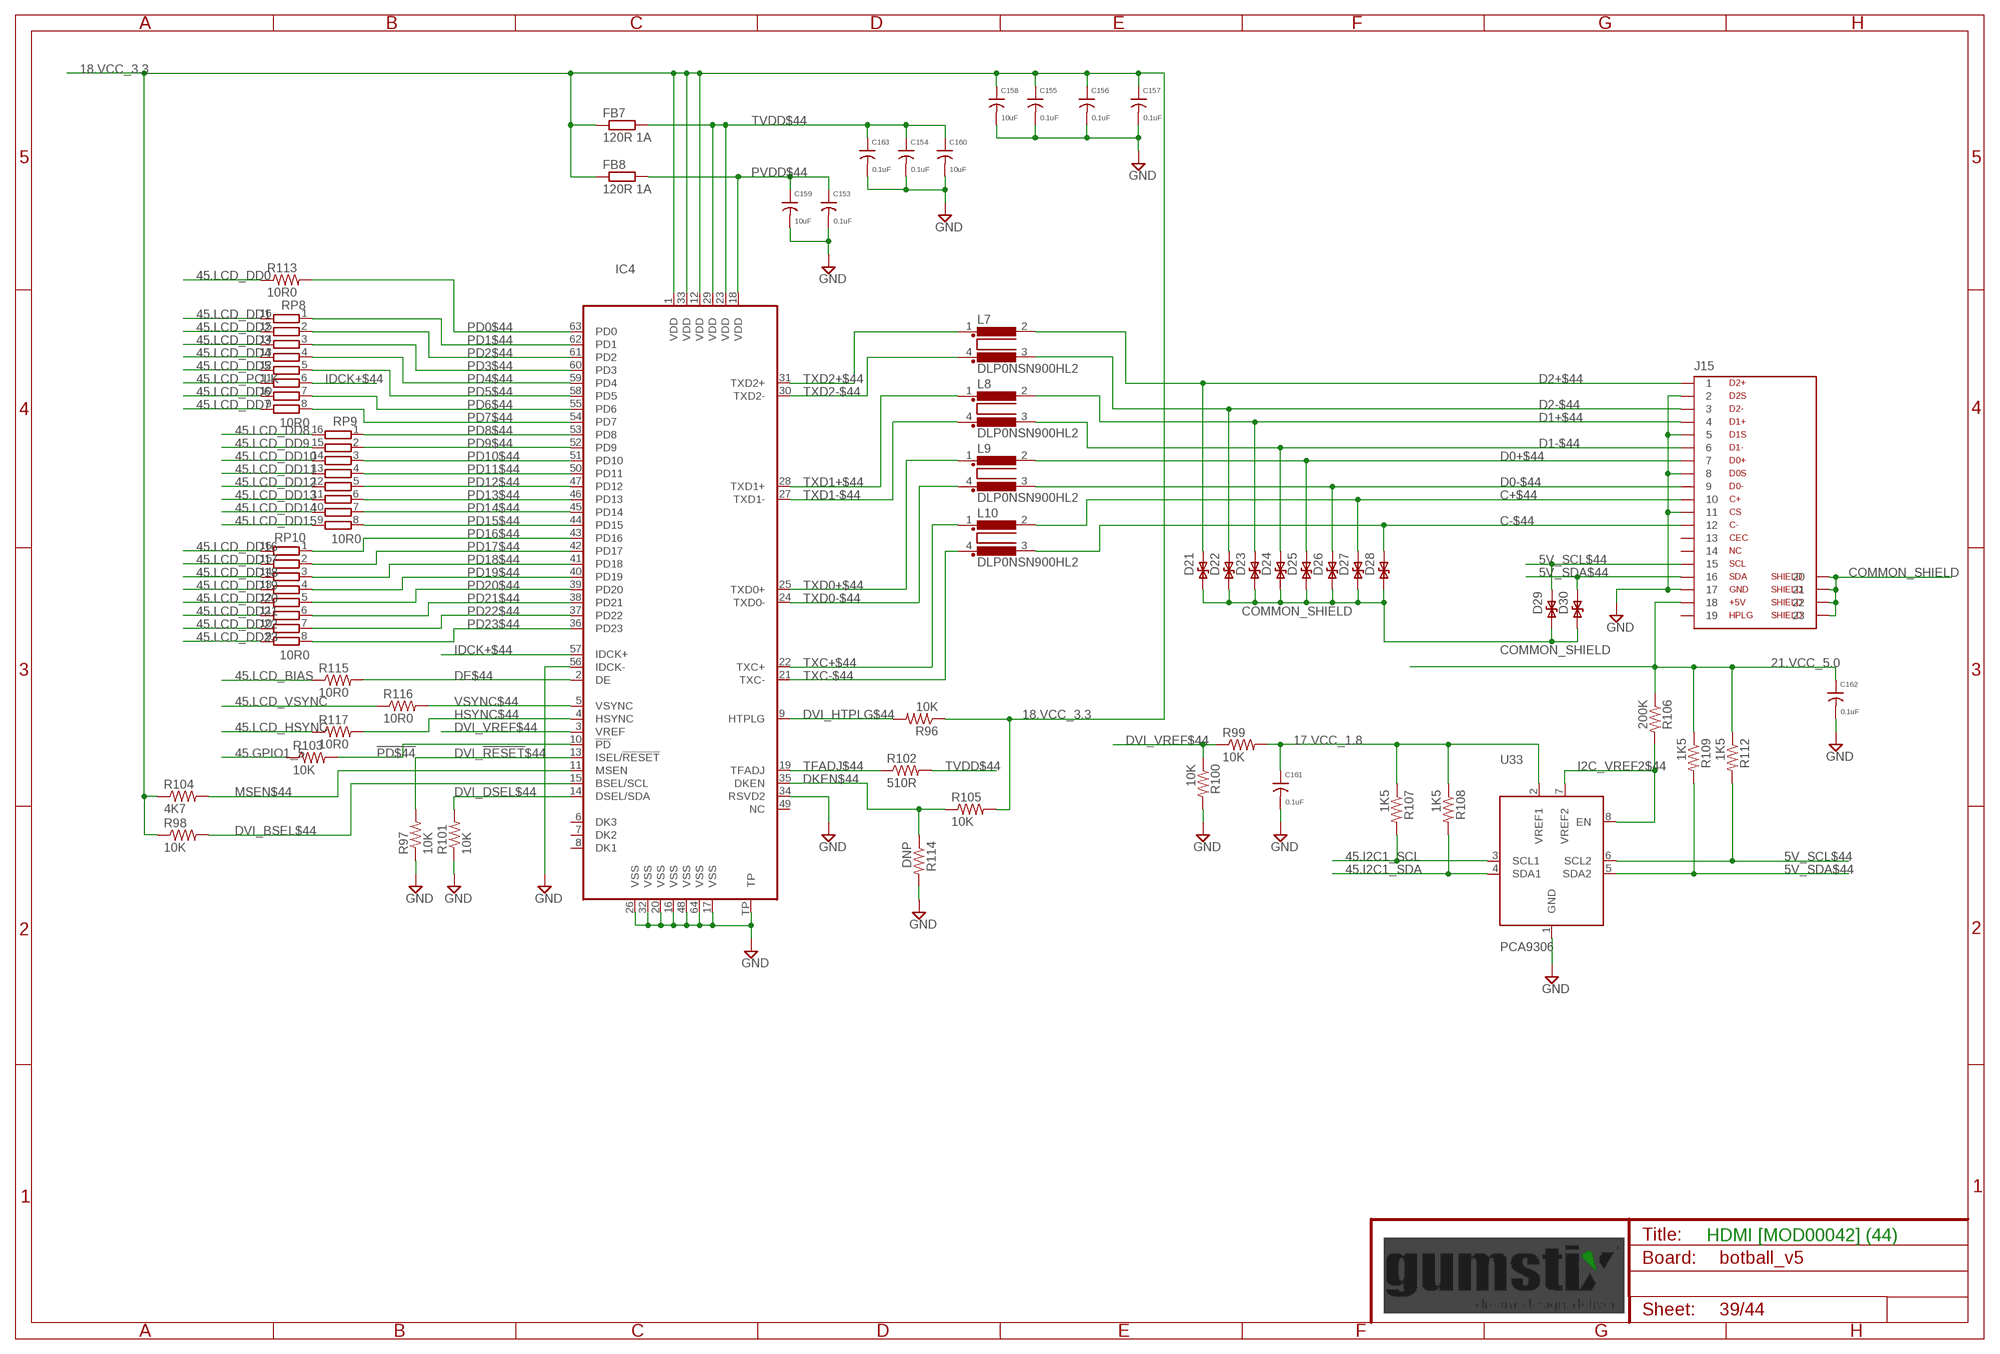
[diagram p38: schematic, sheet 39]
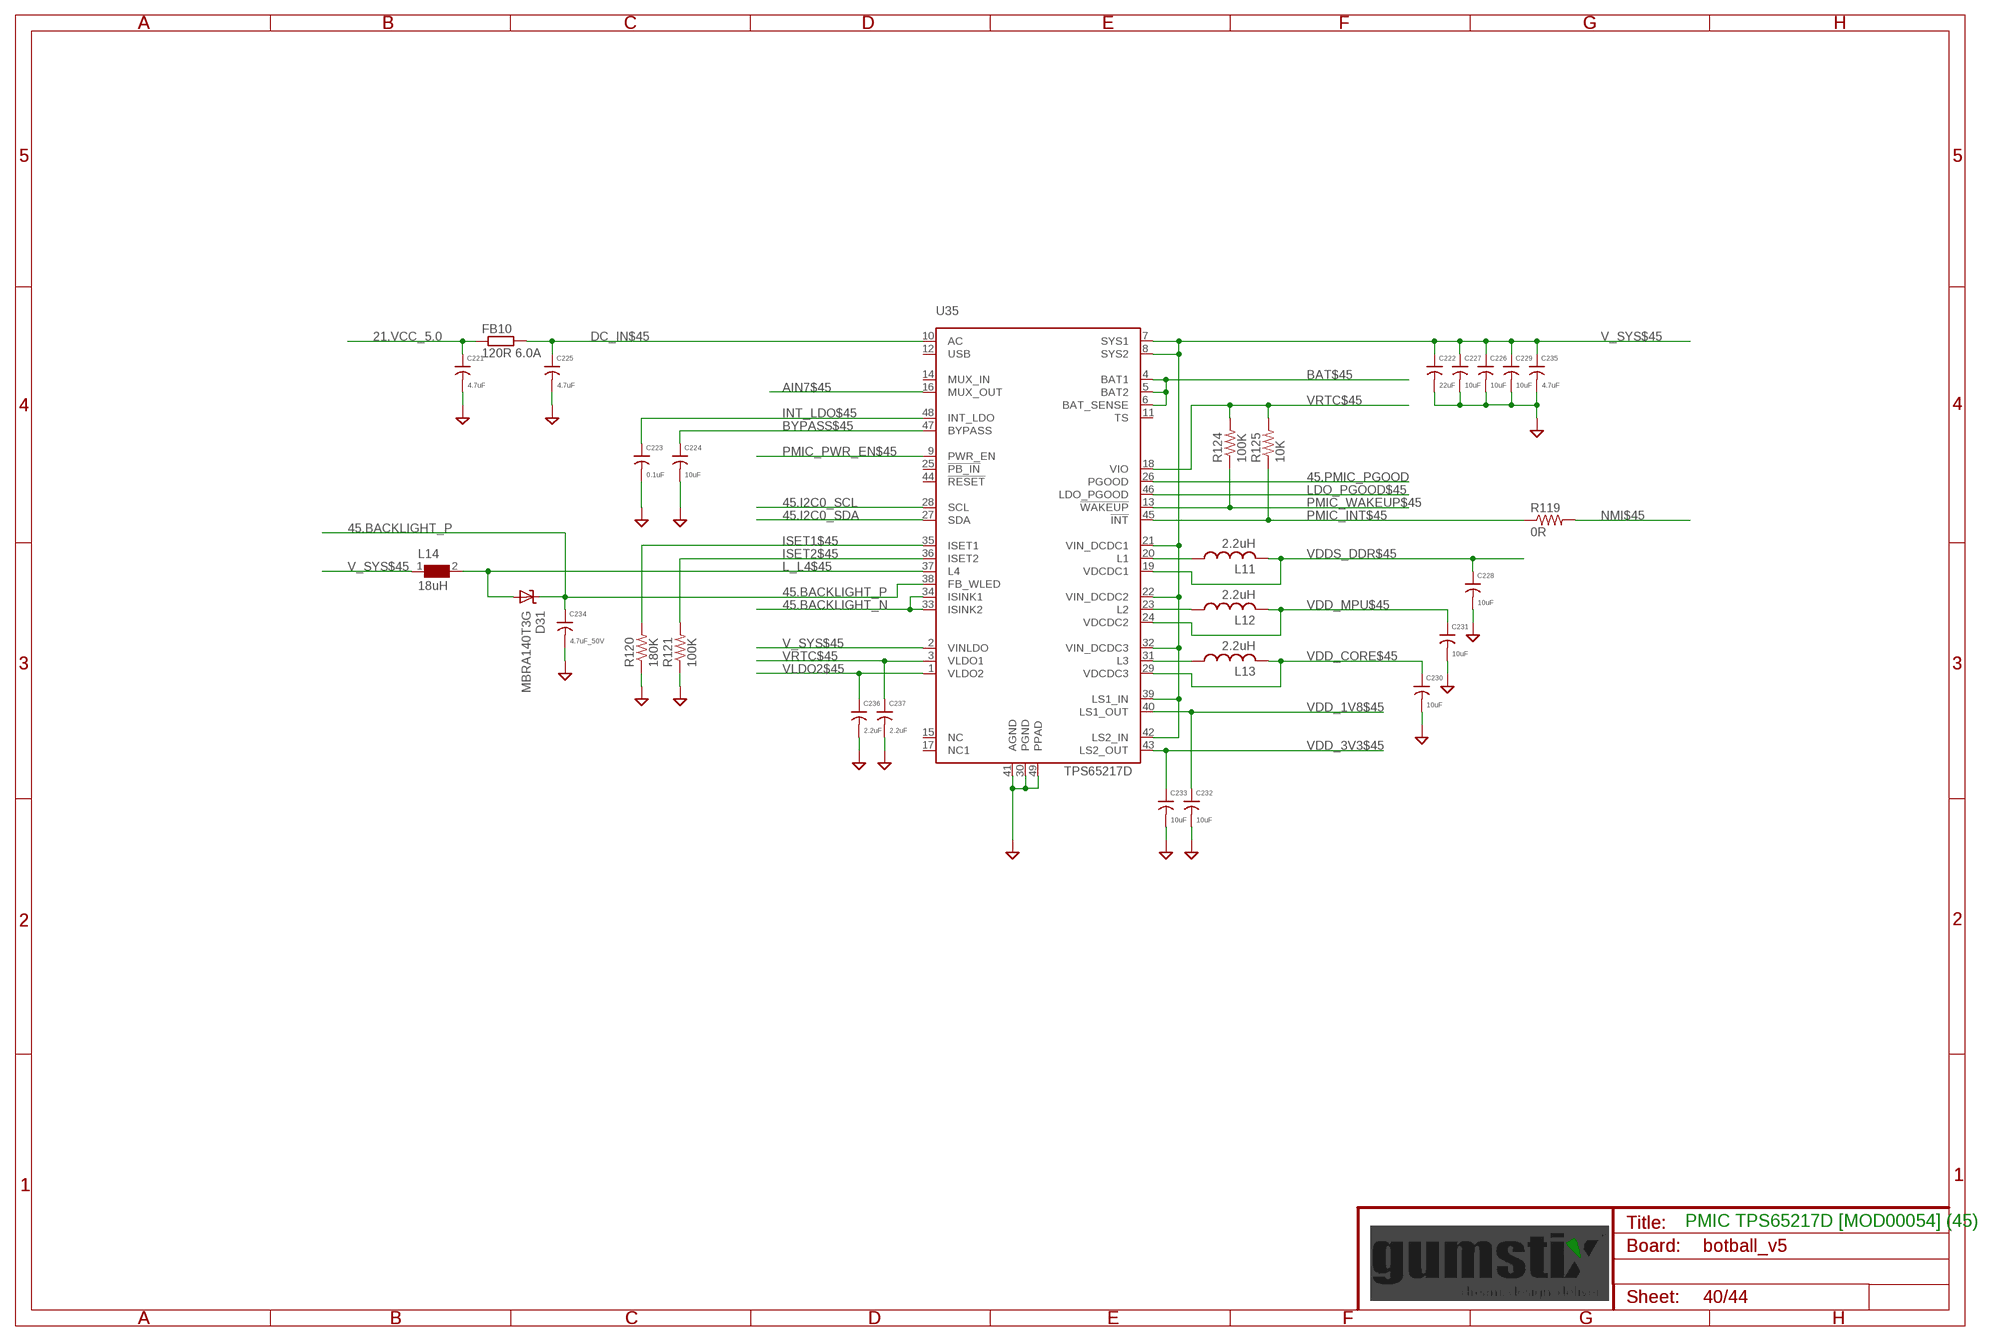
[diagram p39: schematic, sheet 40]
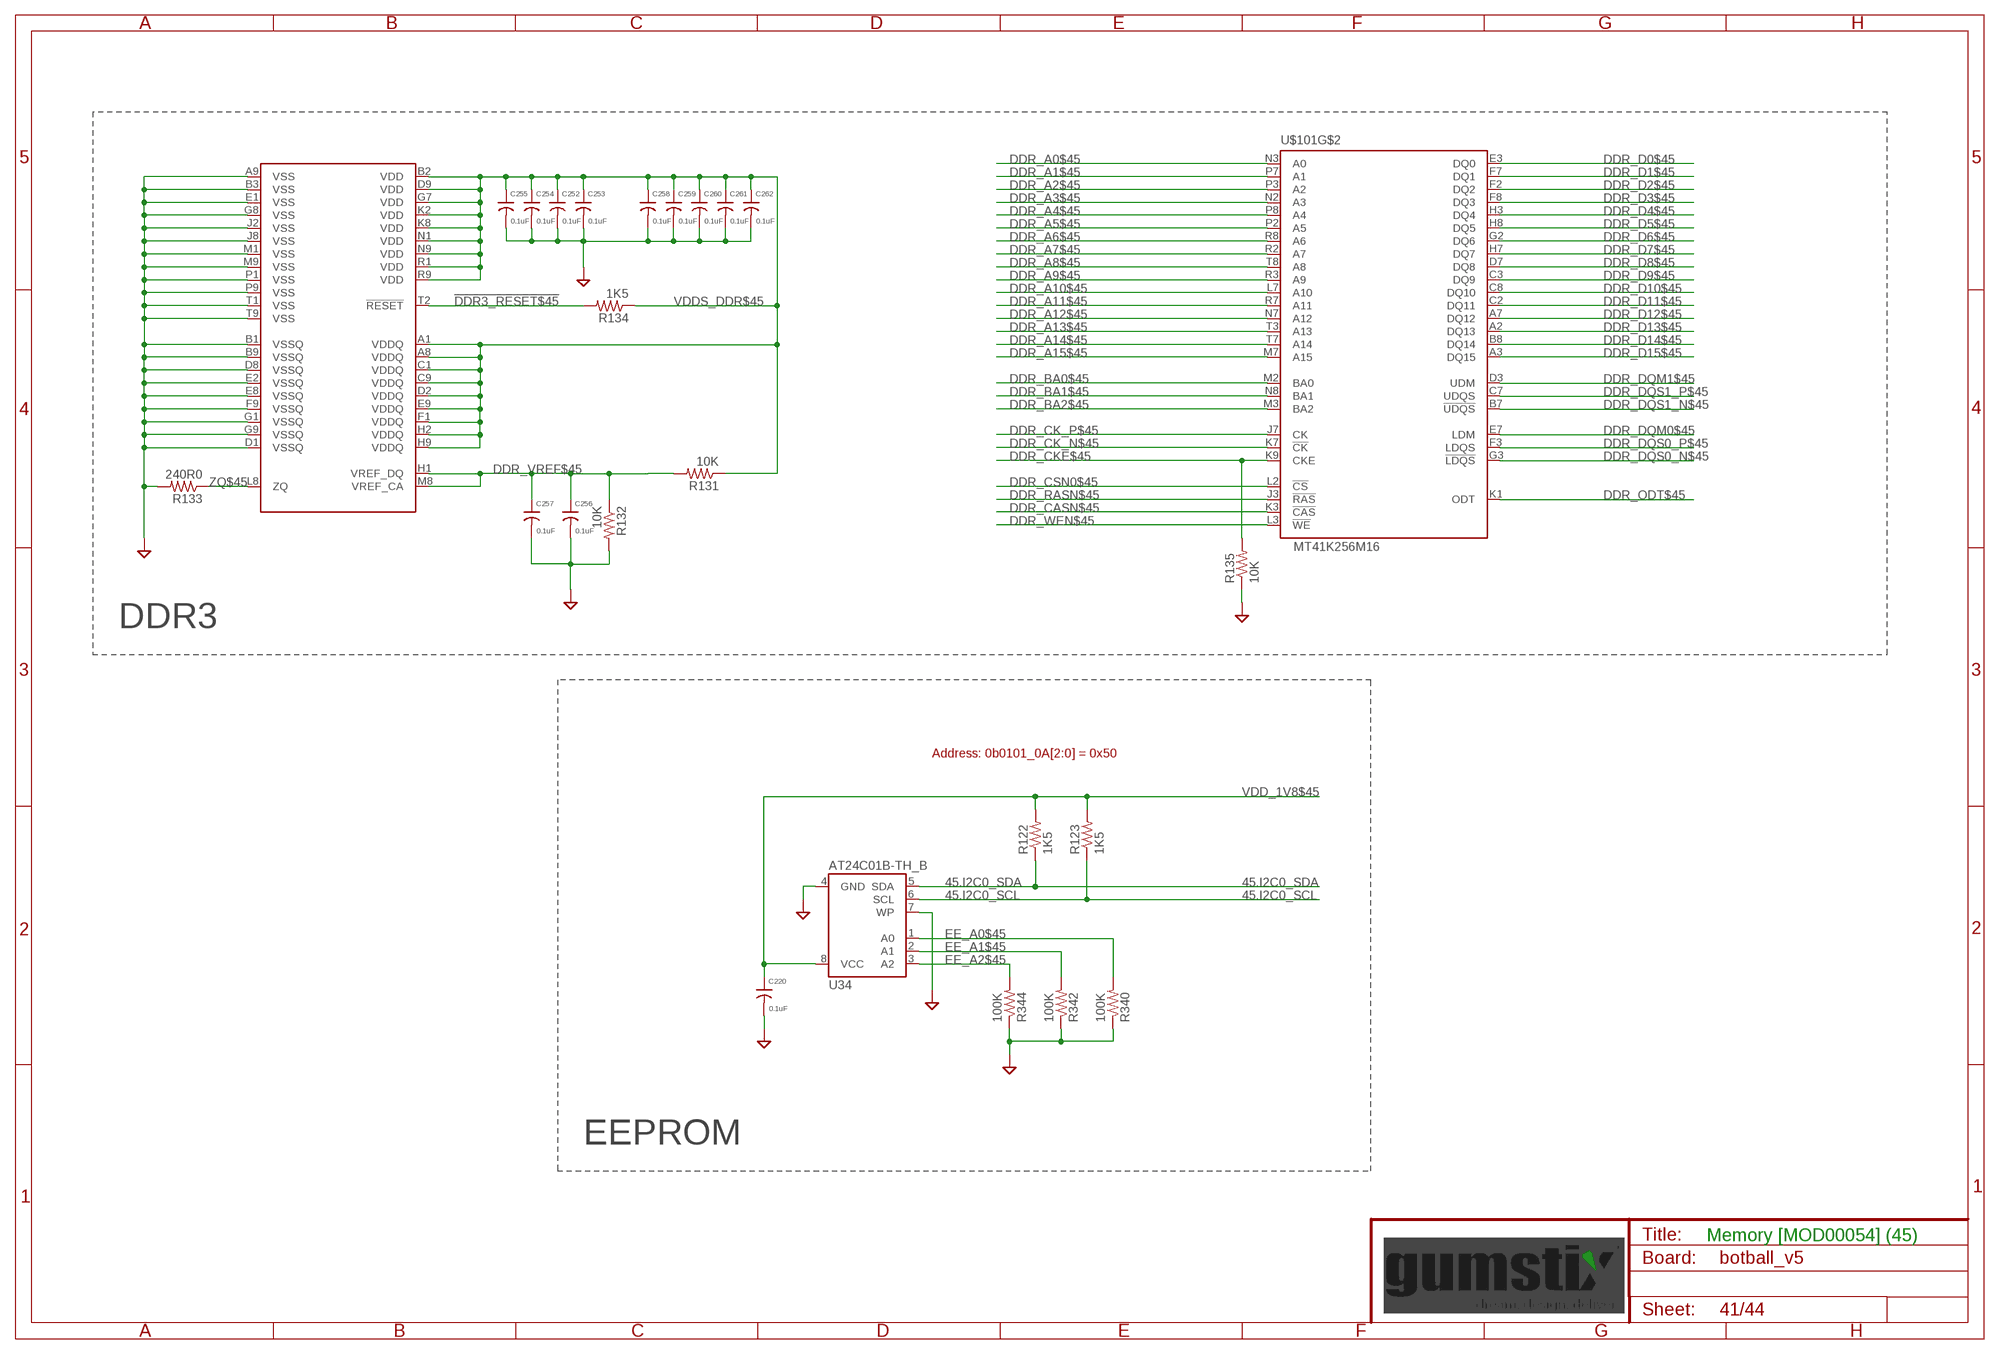
[diagram p40: schematic, sheet 41]
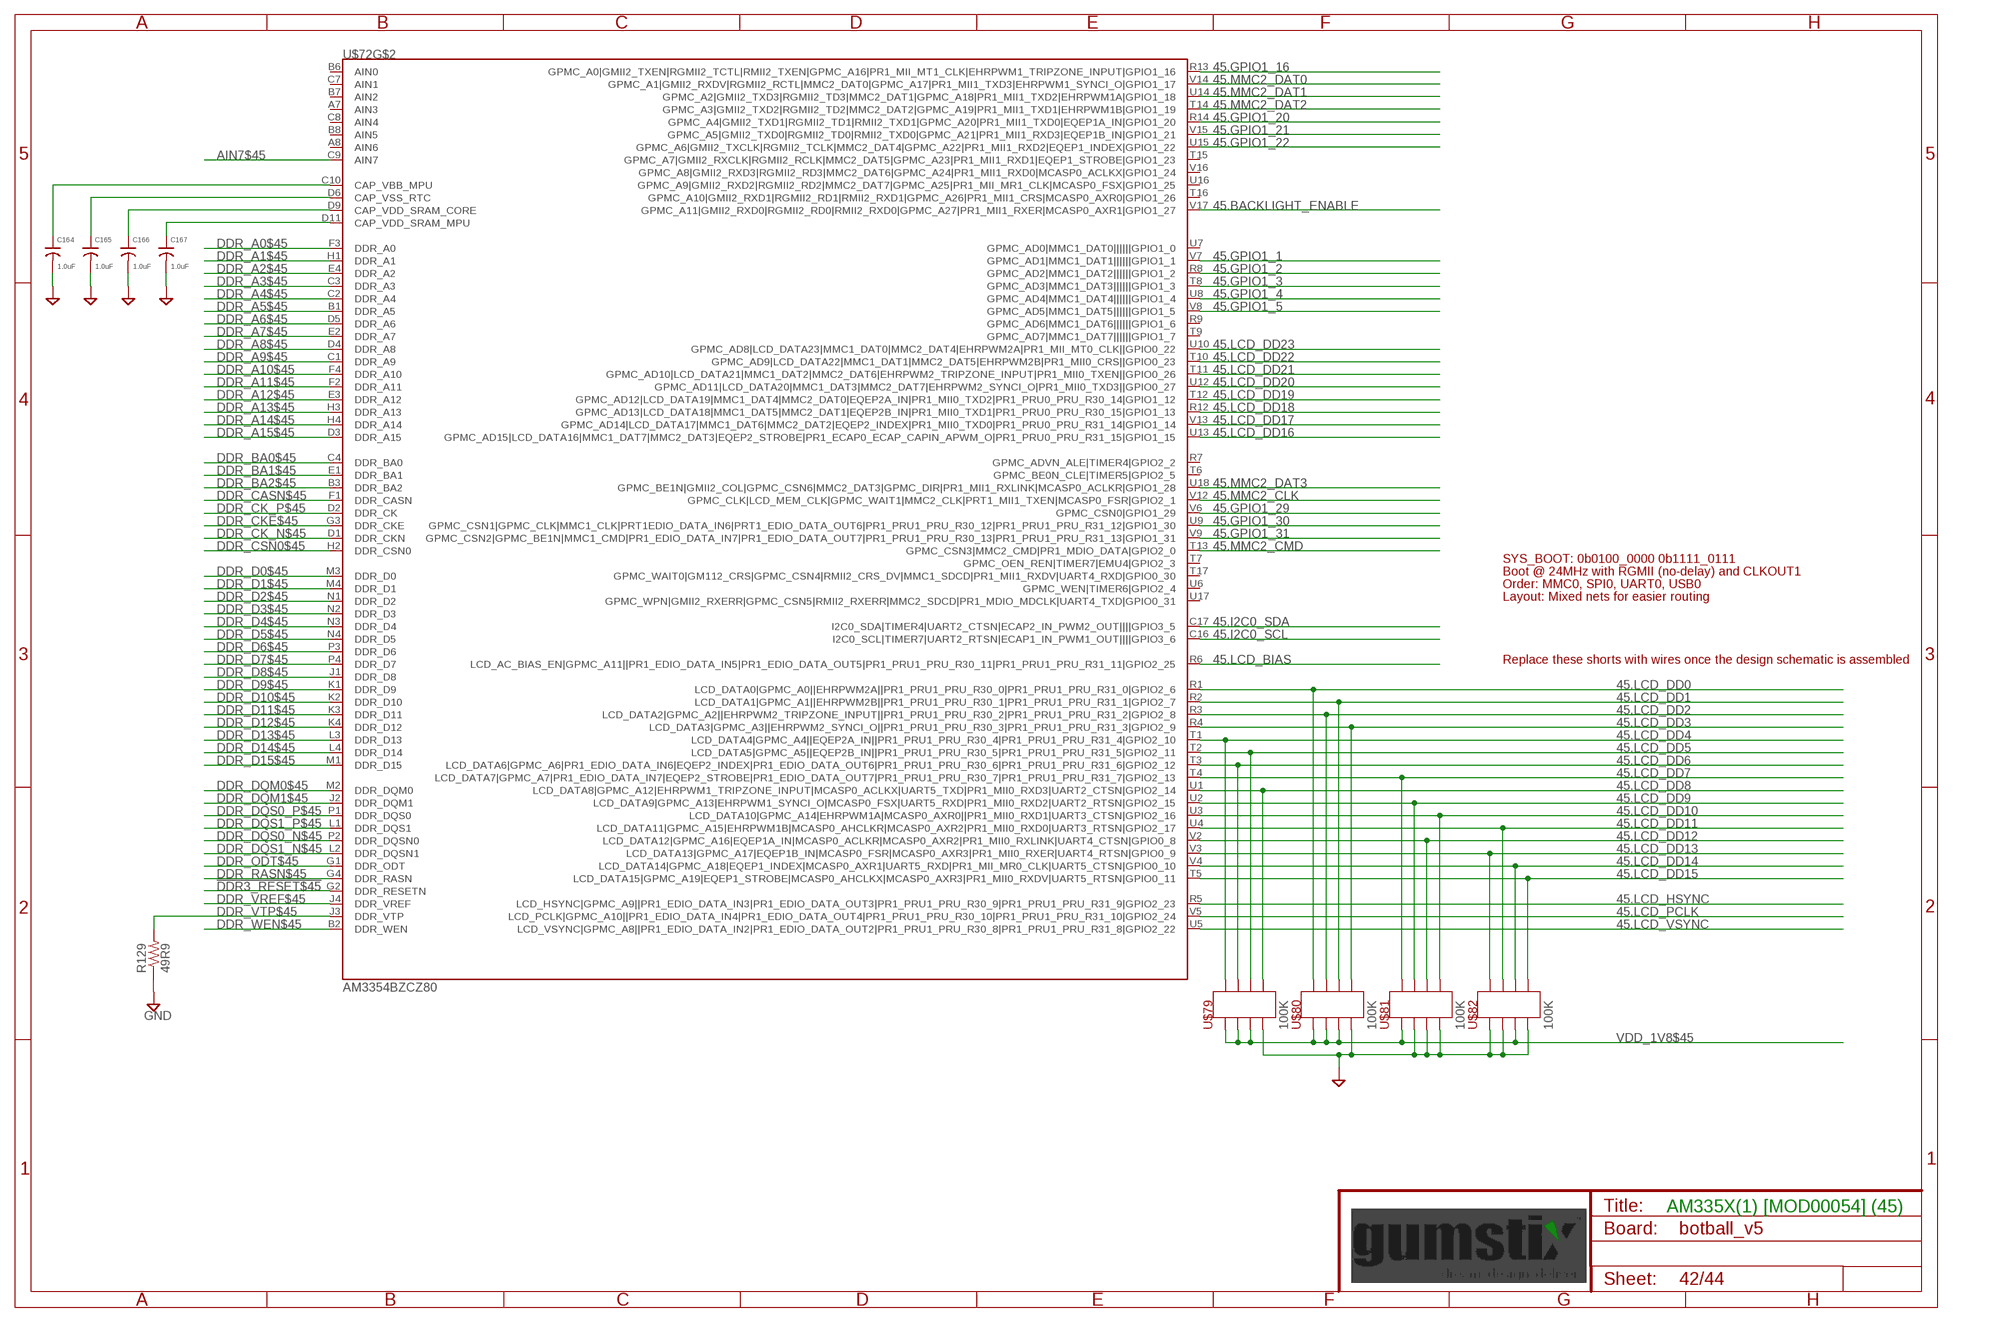
[diagram p41: schematic, sheet 42]
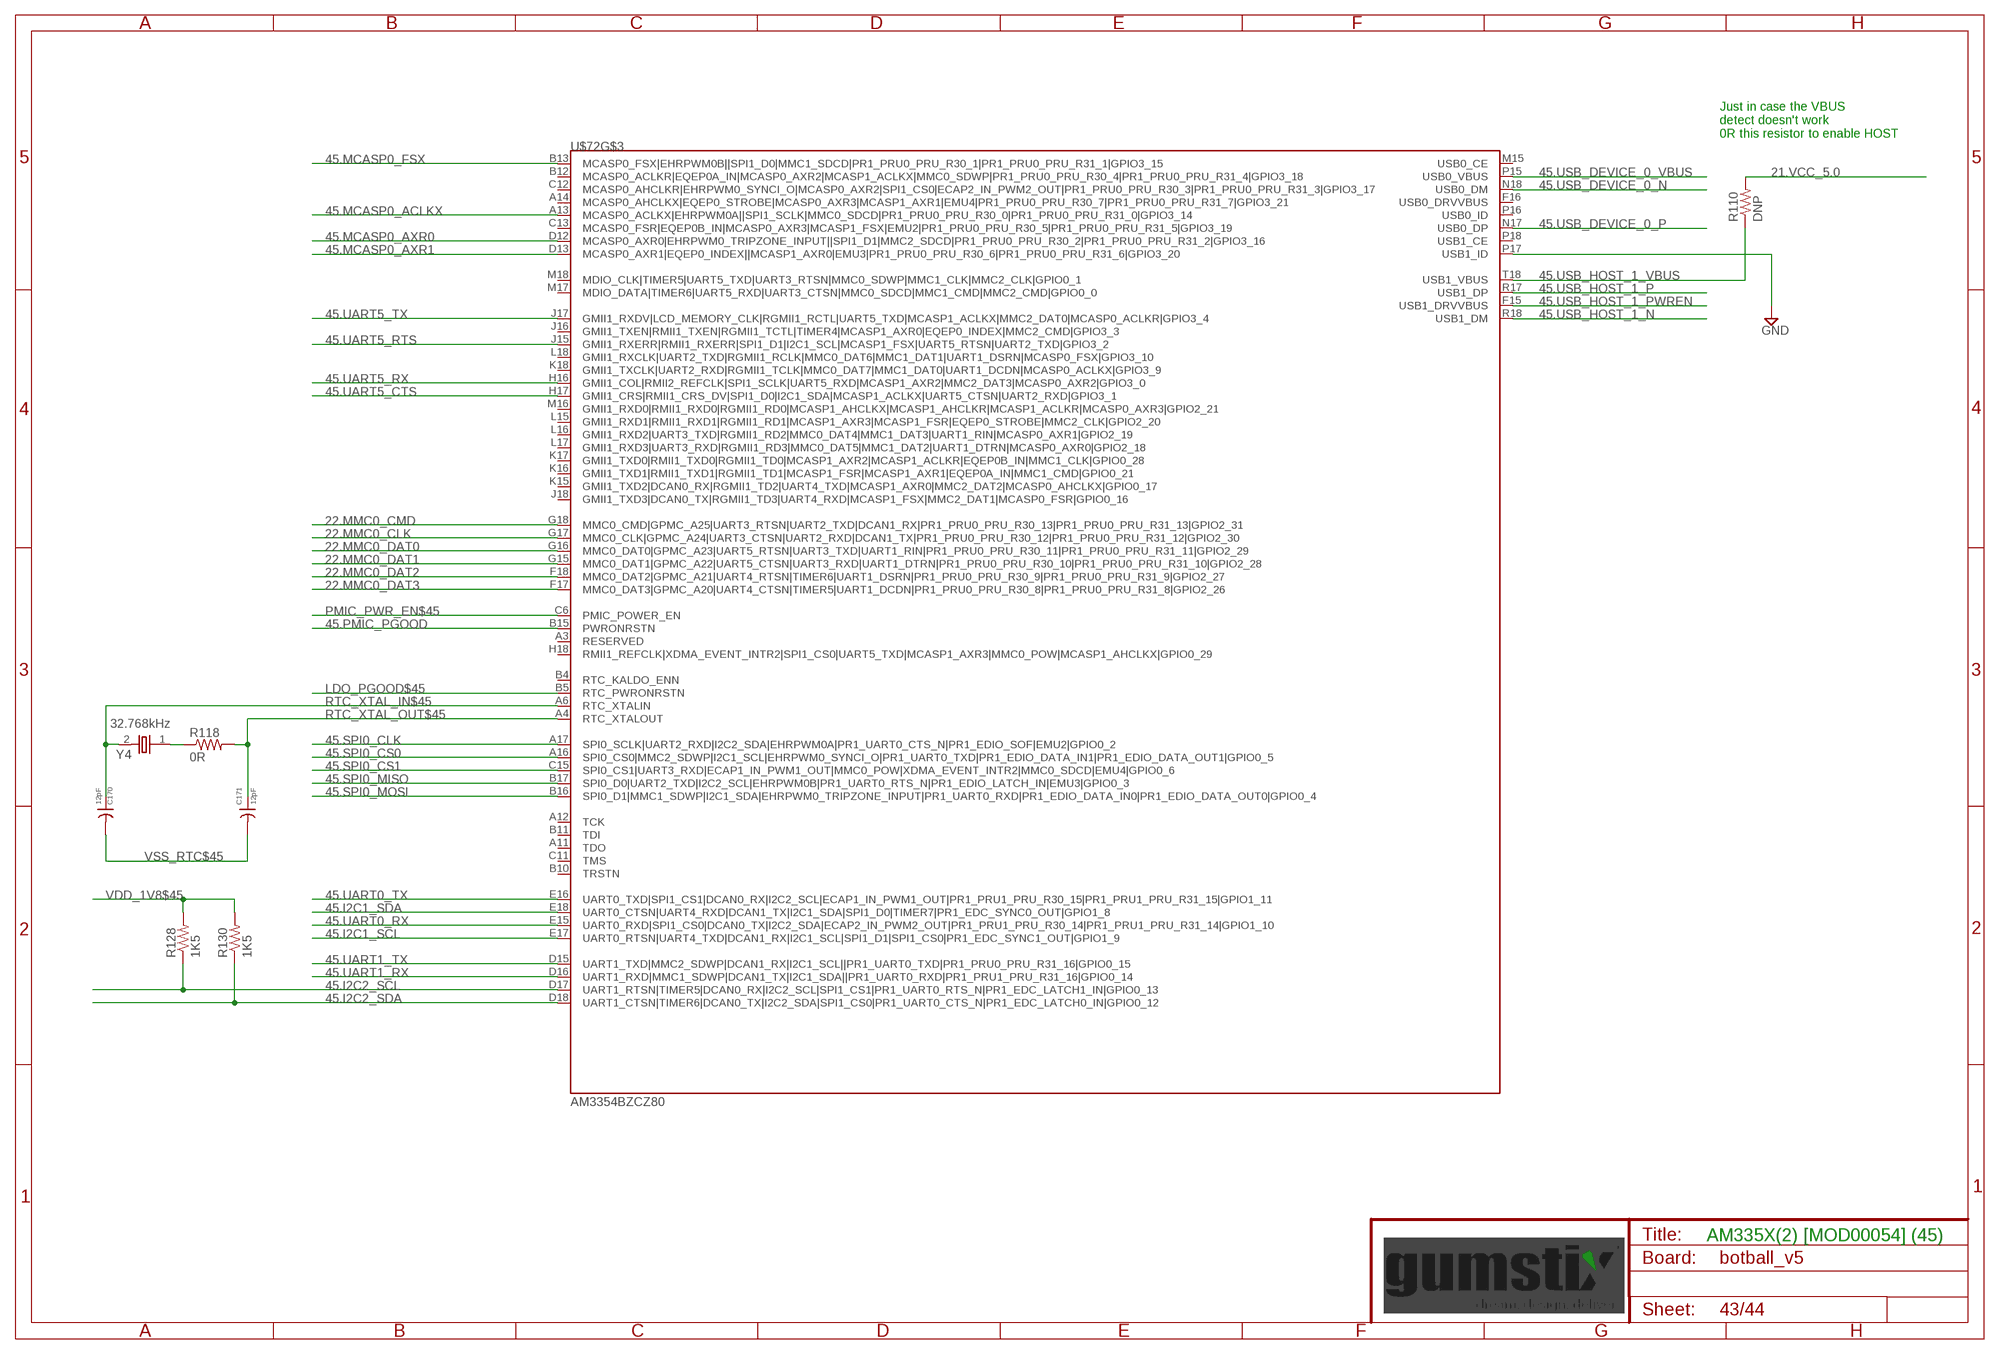
[diagram p42: schematic, sheet 43]
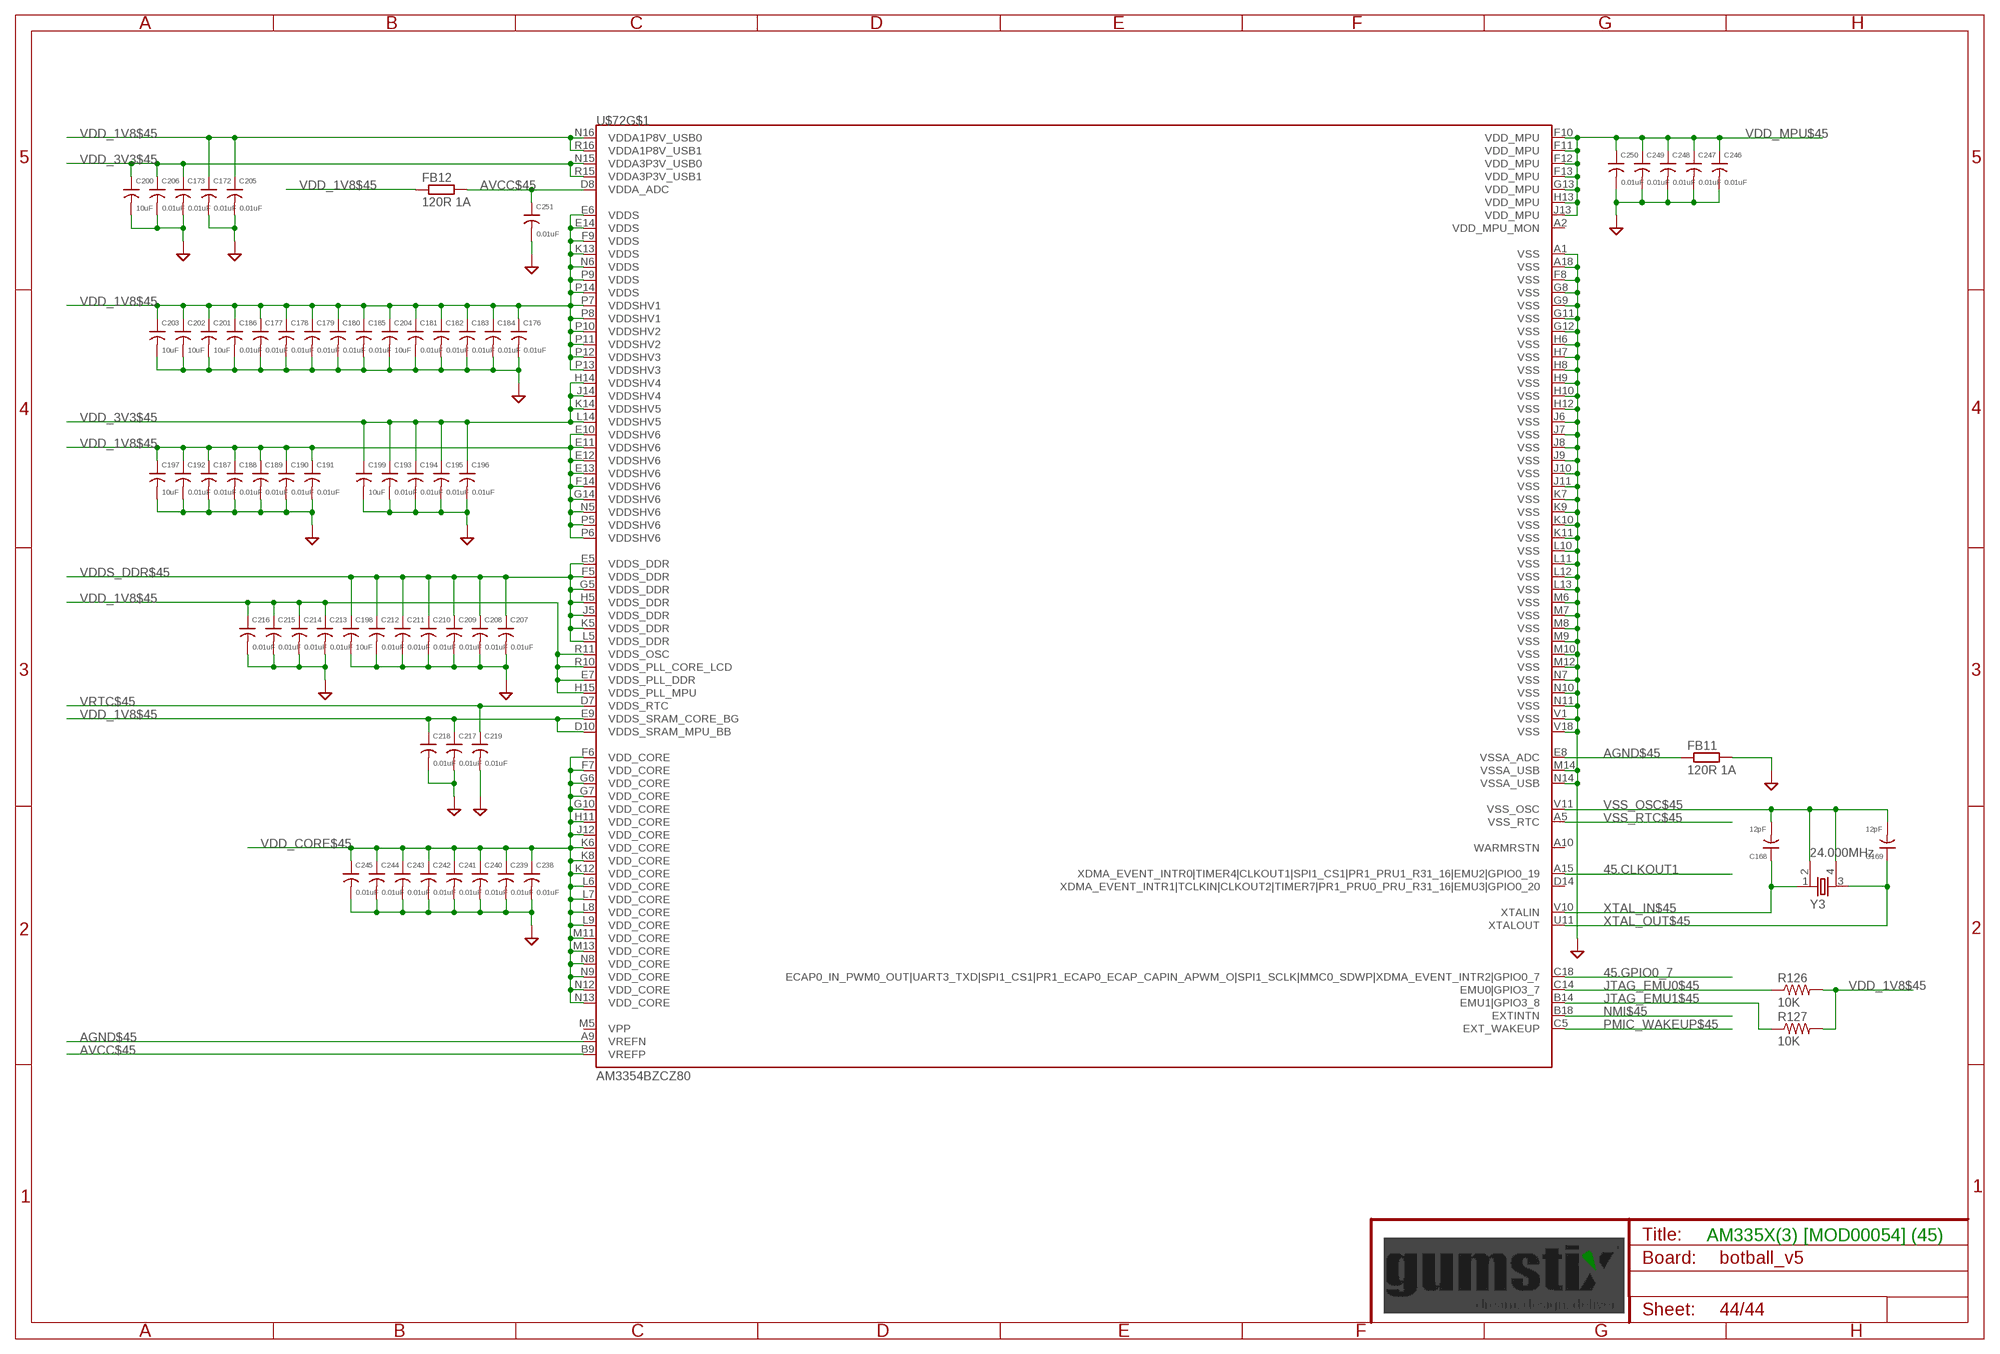
[diagram p43: schematic, sheet 44]

(export (version "E")
  (design (tool "Eeschema 10.0.6"))
  (components
    (comp (ref "C24")
      (value "0.1uF")
      (footprint "eagle-import:0201")
      (libsource (lib "eagle-import") (part "C0201"))
    )
    (comp (ref "C25")
      (value "10uF")
      (footprint "eagle-import:0402")
      (libsource (lib "eagle-import") (part "C0402"))
    )
    (comp (ref "C43")
      (value "0.1uF")
      (footprint "eagle-import:0201")
      (libsource (lib "eagle-import") (part "C0201"))
    )
    (comp (ref "C44")
      (value "0.1uF")
      (footprint "eagle-import:0201")
      (libsource (lib "eagle-import") (part "C0201"))
    )
    (comp (ref "C45")
      (value "0.22uF")
      (footprint "eagle-import:0402")
      (libsource (lib "eagle-import") (part "C0402"))
    )
    (comp (ref "C46")
      (value "4.7uF")
      (footprint "eagle-import:0603")
      (libsource (lib "eagle-import") (part "C0603"))
    )
    (comp (ref "C47")
      (value "0.47uF")
      (footprint "eagle-import:0402")
      (libsource (lib "eagle-import") (part "C0402"))
    )
    (comp (ref "C48")
      (value "0.01uF")
      (footprint "eagle-import:0201")
      (libsource (lib "eagle-import") (part "C0201"))
    )
    (comp (ref "C49")
      (value "10uF")
      (footprint "eagle-import:0402")
      (libsource (lib "eagle-import") (part "C0402"))
    )
    (comp (ref "C50")
      (value "0.1uF")
      (footprint "eagle-import:0201")
      (libsource (lib "eagle-import") (part "C0201"))
    )
    (comp (ref "R33")
      (value "10K")
      (footprint "eagle-import:0201")
      (libsource (lib "eagle-import") (part "R0201"))
    )
    (comp (ref "U12")
      (value "L3G4200D")
      (footprint "eagle-import:LGA16-4X4MM")
      (libsource (lib "eagle-import") (part "L3G4200D"))
    )
    (comp (ref "U13")
      (value "LSM303D")
      (footprint "eagle-import:LGA16-3X3MM")
      (libsource (lib "eagle-import") (part "LSM303DLGA"))
    )
    (comp (ref "C9")
      (value "0.1uF")
      (footprint "eagle-import:0402")
      (libsource (lib "eagle-import") (part "C0402"))
    )
    (comp (ref "R1")
      (value "15K")
      (footprint "eagle-import:0402")
      (libsource (lib "eagle-import") (part "R0402"))
    )
    (comp (ref "R2")
      (value "DNP")
      (footprint "eagle-import:0402")
      (libsource (lib "eagle-import") (part "R0402"))
    )
    (comp (ref "S1")
      (value "EVQ")
      (footprint "eagle-import:EVQ")
      (libsource (lib "eagle-import") (part "EVQ"))
    )
    (comp (ref "C10")
      (value "0.1uF")
      (footprint "eagle-import:0201")
      (libsource (lib "eagle-import") (part "C0201"))
    )
    (comp (ref "C11")
      (value "100uF")
      (footprint "eagle-import:PANASONIC_D")
      (libsource (lib "eagle-import") (part "CPANASONIC_D"))
    )
    (comp (ref "C12")
      (value "10uF / 25V")
      (footprint "eagle-import:1206")
      (libsource (lib "eagle-import") (part "C1206"))
    )
    (comp (ref "C13")
      (value "0.22uF")
      (footprint "eagle-import:0603")
      (libsource (lib "eagle-import") (part "C0603"))
    )
    (comp (ref "C14")
      (value "22pF")
      (footprint "eagle-import:0402")
      (libsource (lib "eagle-import") (part "C0402"))
    )
    (comp (ref "C15")
      (value "22pF")
      (footprint "eagle-import:0402")
      (libsource (lib "eagle-import") (part "C0402"))
    )
    (comp (ref "R4")
      (value "5K6 1P")
      (footprint "eagle-import:0402")
      (libsource (lib "eagle-import") (part "R0402"))
    )
    (comp (ref "R5")
      (value "5K6 1P")
      (footprint "eagle-import:0402")
      (libsource (lib "eagle-import") (part "R0402"))
    )
    (comp (ref "R6")
      (value "2K32 1P")
      (footprint "eagle-import:0402")
      (libsource (lib "eagle-import") (part "R0402"))
    )
    (comp (ref "R7")
      (value "2K32 1P")
      (footprint "eagle-import:0402")
      (libsource (lib "eagle-import") (part "R0402"))
    )
    (comp (ref "R8")
      (value "470R")
      (footprint "eagle-import:0402")
      (libsource (lib "eagle-import") (part "R0402"))
    )
    (comp (ref "R9")
      (value "470R")
      (footprint "eagle-import:0402")
      (libsource (lib "eagle-import") (part "R0402"))
    )
    (comp (ref "R10")
      (value "1K5")
      (footprint "eagle-import:0402")
      (libsource (lib "eagle-import") (part "R0402"))
    )
    (comp (ref "R11")
      (value "5K6 1P")
      (footprint "eagle-import:0402")
      (libsource (lib "eagle-import") (part "R0402"))
    )
    (comp (ref "R12")
      (value "5K6 1P")
      (footprint "eagle-import:0402")
      (libsource (lib "eagle-import") (part "R0402"))
    )
    (comp (ref "R13")
      (value "2K32 1P")
      (footprint "eagle-import:0402")
      (libsource (lib "eagle-import") (part "R0402"))
    )
    (comp (ref "R14")
      (value "2K32 1P")
      (footprint "eagle-import:0402")
      (libsource (lib "eagle-import") (part "R0402"))
    )
    (comp (ref "R15")
      (value "470R")
      (footprint "eagle-import:0402")
      (libsource (lib "eagle-import") (part "R0402"))
    )
    (comp (ref "R16")
      (value "470R")
      (footprint "eagle-import:0402")
      (libsource (lib "eagle-import") (part "R0402"))
    )
    (comp (ref "R17")
      (value "1K5")
      (footprint "eagle-import:0402")
      (libsource (lib "eagle-import") (part "R0402"))
    )
    (comp (ref "U4")
      (value "TB6612FNG")
      (footprint "eagle-import:SSOP24")
      (libsource (lib "eagle-import") (part "TB6612FNG"))
    )
    (comp (ref "U5")
      (value "0.100 MALE PIN")
      (footprint "eagle-import:2X03_SHROUD")
      (libsource (lib "eagle-import") (part "2X03SHROUD"))
    )
    (comp (ref "U6")
      (value "APTB1615")
      (footprint "eagle-import:APTB1615")
      (libsource (lib "eagle-import") (part "APTB1615"))
    )
    (comp (ref "U7")
      (value "APTB1615")
      (footprint "eagle-import:APTB1615")
      (libsource (lib "eagle-import") (part "APTB1615"))
    )
    (comp (ref "C65")
      (value "1.0uF")
      (footprint "eagle-import:0402")
      (libsource (lib "eagle-import") (part "C0402"))
    )
    (comp (ref "C66")
      (value "DNP")
      (footprint "eagle-import:0402")
      (libsource (lib "eagle-import") (part "C0402"))
    )
    (comp (ref "C67")
      (value "0.1uF")
      (footprint "eagle-import:0402")
      (libsource (lib "eagle-import") (part "C0402"))
    )
    (comp (ref "C68")
      (value "DNP")
      (footprint "eagle-import:0402")
      (libsource (lib "eagle-import") (part "C0402"))
    )
    (comp (ref "C69")
      (value "0.1uF")
      (footprint "eagle-import:0402")
      (libsource (lib "eagle-import") (part "C0402"))
    )
    (comp (ref "R41")
      (value "15K")
      (footprint "eagle-import:0201")
      (libsource (lib "eagle-import") (part "R0201"))
    )
    (comp (ref "R42")
      (value "0R")
      (footprint "eagle-import:0201")
      (libsource (lib "eagle-import") (part "R0201"))
    )
    (comp (ref "R43")
      (value "22K")
      (footprint "eagle-import:0402")
      (libsource (lib "eagle-import") (part "R0402"))
    )
    (comp (ref "SPKR+")
      (value "DNP")
      (footprint "eagle-import:P1-13")
      (libsource (lib "eagle-import") (part "TPSQPAD1-13"))
    )
    (comp (ref "SPKR-")
      (value "DNP")
      (footprint "eagle-import:P1-13")
      (libsource (lib "eagle-import") (part "TPSQPAD1-13"))
    )
    (comp (ref "U17")
      (value "LM4862M")
      (footprint "eagle-import:SO-8")
      (libsource (lib "eagle-import") (part "LM4862"))
    )
    (comp (ref "C221")
      (value "4.7uF")
      (footprint "eagle-import:0603")
      (libsource (lib "eagle-import") (part "C0603"))
    )
    (comp (ref "C222")
      (value "22uF")
      (footprint "eagle-import:0805")
      (libsource (lib "eagle-import") (part "C0805"))
    )
    (comp (ref "C223")
      (value "0.1uF")
      (footprint "eagle-import:0201")
      (libsource (lib "eagle-import") (part "C0201"))
    )
    (comp (ref "C224")
      (value "10uF")
      (footprint "eagle-import:0603")
      (libsource (lib "eagle-import") (part "C0603"))
    )
    (comp (ref "C225")
      (value "4.7uF")
      (footprint "eagle-import:0603")
      (libsource (lib "eagle-import") (part "C0603"))
    )
    (comp (ref "C226")
      (value "10uF")
      (footprint "eagle-import:0603")
      (libsource (lib "eagle-import") (part "C0603"))
    )
    (comp (ref "C227")
      (value "10uF")
      (footprint "eagle-import:0603")
      (libsource (lib "eagle-import") (part "C0603"))
    )
    (comp (ref "C228")
      (value "10uF")
      (footprint "eagle-import:0603")
      (libsource (lib "eagle-import") (part "C0603"))
    )
    (comp (ref "C229")
      (value "10uF")
      (footprint "eagle-import:0603")
      (libsource (lib "eagle-import") (part "C0603"))
    )
    (comp (ref "C230")
      (value "10uF")
      (footprint "eagle-import:0603")
      (libsource (lib "eagle-import") (part "C0603"))
    )
    (comp (ref "C231")
      (value "10uF")
      (footprint "eagle-import:0603")
      (libsource (lib "eagle-import") (part "C0603"))
    )
    (comp (ref "C232")
      (value "10uF")
      (footprint "eagle-import:0603")
      (libsource (lib "eagle-import") (part "C0603"))
    )
    (comp (ref "C233")
      (value "10uF")
      (footprint "eagle-import:0603")
      (libsource (lib "eagle-import") (part "C0603"))
    )
    (comp (ref "C234")
      (value "4.7uF_50V")
      (footprint "eagle-import:1210")
      (libsource (lib "eagle-import") (part "C1210"))
    )
    (comp (ref "C235")
      (value "4.7uF")
      (footprint "eagle-import:0603")
      (libsource (lib "eagle-import") (part "C0603"))
    )
    (comp (ref "C236")
      (value "2.2uF")
      (footprint "eagle-import:0402")
      (libsource (lib "eagle-import") (part "C0402"))
    )
    (comp (ref "C237")
      (value "2.2uF")
      (footprint "eagle-import:0402")
      (libsource (lib "eagle-import") (part "C0402"))
    )
    (comp (ref "D31")
      (value "MBRA140T3G")
      (footprint "eagle-import:SMAJ")
      (libsource (lib "eagle-import") (part "DSMA"))
    )
    (comp (ref "FB10")
      (value "120R 6.0A")
      (footprint "eagle-import:0805")
      (libsource (lib "eagle-import") (part "FB0805"))
    )
    (comp (ref "L11")
      (value "2.2uH")
      (footprint "eagle-import:1515")
      (libsource (lib "eagle-import") (part "L1515"))
    )
    (comp (ref "L12")
      (value "2.2uH")
      (footprint "eagle-import:1515")
      (libsource (lib "eagle-import") (part "L1515"))
    )
    (comp (ref "L13")
      (value "2.2uH")
      (footprint "eagle-import:1515")
      (libsource (lib "eagle-import") (part "L1515"))
    )
    (comp (ref "L14")
      (value "18uH")
      (footprint "eagle-import:WE-PD2_4532")
      (libsource (lib "eagle-import") (part "WE-PD2_4532"))
    )
    (comp (ref "R119")
      (value "0R")
      (footprint "eagle-import:0201")
      (libsource (lib "eagle-import") (part "R0201"))
    )
    (comp (ref "R120")
      (value "180K")
      (footprint "eagle-import:0201")
      (libsource (lib "eagle-import") (part "R0201"))
    )
    (comp (ref "R121")
      (value "100K")
      (footprint "eagle-import:0201")
      (libsource (lib "eagle-import") (part "R0201"))
    )
    (comp (ref "R124")
      (value "100K")
      (footprint "eagle-import:0201")
      (libsource (lib "eagle-import") (part "R0201"))
    )
    (comp (ref "R125")
      (value "10K")
      (footprint "eagle-import:0201")
      (libsource (lib "eagle-import") (part "R0201"))
    )
    (comp (ref "U35")
      (value "TPS65217D")
      (footprint "eagle-import:QFN40P600X600X100-49")
      (libsource (lib "eagle-import") (part "TPS65217"))
    )
    (comp (ref "J4")
      (value "0.1 FEMALE")
      (footprint "eagle-import:1X06")
      (libsource (lib "eagle-import") (part "1X06"))
    )
    (comp (ref "J5")
      (value "0.1 FEMALE")
      (footprint "eagle-import:2X06")
      (libsource (lib "eagle-import") (part "2X06"))
    )
    (comp (ref "C18")
      (value "0.1uF")
      (footprint "eagle-import:0201")
      (libsource (lib "eagle-import") (part "C0201"))
    )
    (comp (ref "C19")
      (value "0.1uF")
      (footprint "eagle-import:0201")
      (libsource (lib "eagle-import") (part "C0201"))
    )
    (comp (ref "C20")
      (value "1.0uF")
      (footprint "eagle-import:0201")
      (libsource (lib "eagle-import") (part "C0201"))
    )
    (comp (ref "R21")
      (value "DNP")
      (footprint "eagle-import:0201")
      (libsource (lib "eagle-import") (part "R0201"))
    )
    (comp (ref "R22")
      (value "DNP")
      (footprint "eagle-import:0201")
      (libsource (lib "eagle-import") (part "R0201"))
    )
    (comp (ref "U10")
      (value "TXS0102")
      (footprint "eagle-import:DFN8-0.4P")
      (libsource (lib "eagle-import") (part "TXS0102"))
    )
    (comp (ref "C118")
      (value "0.1uF")
      (footprint "eagle-import:0201")
      (libsource (lib "eagle-import") (part "C0201"))
    )
    (comp (ref "C119")
      (value "0.1uF")
      (footprint "eagle-import:0201")
      (libsource (lib "eagle-import") (part "C0201"))
    )
    (comp (ref "J12")
      (value "CONN20FEMALE")
      (footprint "eagle-import:057-020-1")
      (libsource (lib "eagle-import") (part "CONN20HEADER"))
    )
    (comp (ref "J13")
      (value "CONN10FEMALE")
      (footprint "eagle-import:057-010-1")
      (libsource (lib "eagle-import") (part "CONN10HEADER"))
    )
    (comp (ref "R78")
      (value "0R")
      (footprint "eagle-import:0201")
      (libsource (lib "eagle-import") (part "R0201"))
    )
    (comp (ref "R79")
      (value "0R")
      (footprint "eagle-import:0201")
      (libsource (lib "eagle-import") (part "R0201"))
    )
    (comp (ref "R80")
      (value "DNP")
      (footprint "eagle-import:0201")
      (libsource (lib "eagle-import") (part "R0201"))
    )
    (comp (ref "R81")
      (value "DNP")
      (footprint "eagle-import:0201")
      (libsource (lib "eagle-import") (part "R0201"))
    )
    (comp (ref "RP7")
      (value "DNP")
      (footprint "eagle-import:741X16")
      (libsource (lib "eagle-import") (part "RP741X163"))
    )
    (comp (ref "U29")
      (value "TXS0108E")
      (footprint "eagle-import:QFN20")
      (libsource (lib "eagle-import") (part "TXS0108E"))
    )
    (comp (ref "U30")
      (value "TXS0102")
      (footprint "eagle-import:DFN8-0.4P")
      (libsource (lib "eagle-import") (part "TXS0102"))
    )
    (comp (ref "C93")
      (value "0.1uF")
      (footprint "eagle-import:0201")
      (libsource (lib "eagle-import") (part "C0201"))
    )
    (comp (ref "C94")
      (value "0.1uF")
      (footprint "eagle-import:0201")
      (libsource (lib "eagle-import") (part "C0201"))
    )
    (comp (ref "C95")
      (value "1.0uF")
      (footprint "eagle-import:0402")
      (libsource (lib "eagle-import") (part "C0402"))
    )
    (comp (ref "J7")
      (value "DNP")
      (footprint "eagle-import:2X03")
      (libsource (lib "eagle-import") (part "2X03"))
    )
    (comp (ref "RP4")
      (value "DNP")
      (footprint "eagle-import:741X16")
      (libsource (lib "eagle-import") (part "RP741X163"))
    )
    (comp (ref "U20")
      (value "TXS0108E")
      (footprint "eagle-import:QFN20")
      (libsource (lib "eagle-import") (part "TXS0108E"))
    )
    (comp (ref "C139")
      (value "0.1uF")
      (footprint "eagle-import:0201")
      (libsource (lib "eagle-import") (part "C0201"))
    )
    (comp (ref "C140")
      (value "0.1uF")
      (footprint "eagle-import:0201")
      (libsource (lib "eagle-import") (part "C0201"))
    )
    (comp (ref "C141")
      (value "1.0uF")
      (footprint "eagle-import:0201")
      (libsource (lib "eagle-import") (part "C0201"))
    )
    (comp (ref "R93")
      (value "DNP")
      (footprint "eagle-import:0201")
      (libsource (lib "eagle-import") (part "R0201"))
    )
    (comp (ref "R94")
      (value "DNP")
      (footprint "eagle-import:0201")
      (libsource (lib "eagle-import") (part "R0201"))
    )
    (comp (ref "U32")
      (value "TXS0102")
      (footprint "eagle-import:DFN8-0.4P")
      (libsource (lib "eagle-import") (part "TXS0102"))
    )
    (comp (ref "C86")
      (value "10uF/50V")
      (footprint "eagle-import:1206")
      (libsource (lib "eagle-import") (part "C1206"))
    )
    (comp (ref "C87")
      (value "10nF")
      (footprint "eagle-import:0603")
      (libsource (lib "eagle-import") (part "C0603"))
    )
    (comp (ref "C88")
      (value "0.01uF")
      (footprint "eagle-import:0402")
      (libsource (lib "eagle-import") (part "C0402"))
    )
    (comp (ref "C89")
      (value "0.01uF")
      (footprint "eagle-import:0402")
      (libsource (lib "eagle-import") (part "C0402"))
    )
    (comp (ref "C90")
      (value "330uF")
      (footprint "eagle-import:PANASONIC_F")
      (libsource (lib "eagle-import") (part "CPANASONIC_F"))
    )
    (comp (ref "D10")
      (value "CDBC540-G")
      (footprint "eagle-import:DO-214AB")
      (libsource (lib "eagle-import") (part "SCHOTTKY-DIODE"))
    )
    (comp (ref "L2")
      (value "10uH")
      (footprint "eagle-import:3232DZ")
      (libsource (lib "eagle-import") (part "L3232DZ"))
    )
    (comp (ref "R52")
      (value "0R")
      (footprint "eagle-import:0805")
      (libsource (lib "eagle-import") (part "R0805"))
    )
    (comp (ref "R53")
      (value "100K")
      (footprint "eagle-import:0402")
      (libsource (lib "eagle-import") (part "R0402"))
    )
    (comp (ref "R54")
      (value "31K6")
      (footprint "eagle-import:0402")
      (libsource (lib "eagle-import") (part "R0402"))
    )
    (comp (ref "TP1")
      (value "DNP")
      (footprint "eagle-import:TP0500")
      (libsource (lib "eagle-import") (part "TP05"))
    )
    (comp (ref "U$27")
      (value "TPS5450")
      (footprint "eagle-import:8SO_POWERPAD")
      (libsource (lib "eagle-import") (part "TPS5450"))
    )
    (comp (ref "C91")
      (value "0.1uF")
      (footprint "eagle-import:0402")
      (libsource (lib "eagle-import") (part "C0402"))
    )
    (comp (ref "C92")
      (value "10uF")
      (footprint "eagle-import:0603")
      (libsource (lib "eagle-import") (part "C0603"))
    )
    (comp (ref "RP1")
      (value "33R0")
      (footprint "eagle-import:741X16")
      (libsource (lib "eagle-import") (part "RP741X163"))
    )
    (comp (ref "RP2")
      (value "10K0")
      (footprint "eagle-import:741X16")
      (libsource (lib "eagle-import") (part "RP741X163"))
    )
    (comp (ref "U$30")
      (value "USD_3M2900")
      (footprint "eagle-import:USD")
      (libsource (lib "eagle-import") (part "USD_3M2900"))
    )
    (comp (ref "D1")
      (value "RED")
      (footprint "eagle-import:D0603")
      (libsource (lib "eagle-import") (part "LED0603"))
    )
    (comp (ref "F3")
      (value "2920L500/16MR")
      (footprint "eagle-import:2920")
      (libsource (lib "eagle-import") (part "PTC2920"))
    )
    (comp (ref "Q1")
      (value "FDT434P")
      (footprint "eagle-import:SOT223")
      (libsource (lib "eagle-import") (part "BSP170P"))
    )
    (comp (ref "Q6")
      (value "FDT434P")
      (footprint "eagle-import:SOT223")
      (libsource (lib "eagle-import") (part "BSP170P"))
    )
    (comp (ref "R18")
      (value "330R")
      (footprint "eagle-import:0201")
      (libsource (lib "eagle-import") (part "R0201"))
    )
    (comp (ref "R19")
      (value "30K")
      (footprint "eagle-import:0201")
      (libsource (lib "eagle-import") (part "R0201"))
    )
    (comp (ref "R20")
      (value "1K")
      (footprint "eagle-import:0201")
      (libsource (lib "eagle-import") (part "R0201"))
    )
    (comp (ref "U9")
      (value "JS102011SAQN")
      (footprint "eagle-import:JS102011SAQN")
      (libsource (lib "eagle-import") (part "JS102011SAQN"))
    )
    (comp (ref "C26")
      (value "10uF")
      (footprint "eagle-import:0603")
      (libsource (lib "eagle-import") (part "C0603"))
    )
    (comp (ref "C27")
      (value "0.01uF")
      (footprint "eagle-import:0402")
      (libsource (lib "eagle-import") (part "C0402"))
    )
    (comp (ref "C28")
      (value "0.1uF")
      (footprint "eagle-import:0402")
      (libsource (lib "eagle-import") (part "C0402"))
    )
    (comp (ref "C29")
      (value "100uF")
      (footprint "eagle-import:1206")
      (libsource (lib "eagle-import") (part "C1206"))
    )
    (comp (ref "C30")
      (value "100uF")
      (footprint "eagle-import:1206")
      (libsource (lib "eagle-import") (part "C1206"))
    )
    (comp (ref "C31")
      (value "100uF")
      (footprint "eagle-import:1206")
      (libsource (lib "eagle-import") (part "C1206"))
    )
    (comp (ref "C32")
      (value "100uF")
      (footprint "eagle-import:1206")
      (libsource (lib "eagle-import") (part "C1206"))
    )
    (comp (ref "D3")
      (value "PS04LTVA1")
      (footprint "eagle-import:D0402")
      (libsource (lib "eagle-import") (part "ESD-DIODE"))
    )
    (comp (ref "D4")
      (value "PS04LTVA1")
      (footprint "eagle-import:D0402")
      (libsource (lib "eagle-import") (part "ESD-DIODE"))
    )
    (comp (ref "D5")
      (value "B72590D50A060")
      (footprint "eagle-import:D0402")
      (libsource (lib "eagle-import") (part "ESD-DIODE"))
    )
    (comp (ref "D6")
      (value "B72590D50A060")
      (footprint "eagle-import:D0402")
      (libsource (lib "eagle-import") (part "ESD-DIODE"))
    )
    (comp (ref "D7")
      (value "PS04LTVA1")
      (footprint "eagle-import:D0402")
      (libsource (lib "eagle-import") (part "ESD-DIODE"))
    )
    (comp (ref "D8")
      (value "PS04LTVA1")
      (footprint "eagle-import:D0402")
      (libsource (lib "eagle-import") (part "ESD-DIODE"))
    )
    (comp (ref "D9")
      (value "B72590D50A060")
      (footprint "eagle-import:D0402")
      (libsource (lib "eagle-import") (part "ESD-DIODE"))
    )
    (comp (ref "FB1")
      (value "120R 1A")
      (footprint "eagle-import:0402")
      (libsource (lib "eagle-import") (part "FB0402"))
    )
    (comp (ref "FB2")
      (value "120R 1A")
      (footprint "eagle-import:0402")
      (libsource (lib "eagle-import") (part "FB0402"))
    )
    (comp (ref "FB3")
      (value "120R 1A")
      (footprint "eagle-import:0402")
      (libsource (lib "eagle-import") (part "FB0402"))
    )
    (comp (ref "FB4")
      (value "120R 1A")
      (footprint "eagle-import:0402")
      (libsource (lib "eagle-import") (part "FB0402"))
    )
    (comp (ref "K1")
      (value "61400826021")
      (footprint "eagle-import:61400826021")
      (libsource (lib "eagle-import") (part "61400826021"))
    )
    (comp (ref "L3")
      (value "DLP11SN900HL2")
      (footprint "eagle-import:0504-DLP11S")
      (libsource (lib "eagle-import") (part "COM_MODE_CHOKE"))
    )
    (comp (ref "L4")
      (value "DLP11SN900HL2")
      (footprint "eagle-import:0504-DLP11S")
      (libsource (lib "eagle-import") (part "COM_MODE_CHOKE"))
    )
    (comp (ref "U14")
      (value "TPS2052B")
      (footprint "eagle-import:MSOP8-PAD")
      (libsource (lib "eagle-import") (part "TPS2052"))
    )
    (comp (ref "D2")
      (value "GREEN")
      (footprint "eagle-import:D0603")
      (libsource (lib "eagle-import") (part "LED0603"))
    )
    (comp (ref "Q2")
      (value "BSS138")
      (footprint "eagle-import:SOT23")
      (libsource (lib "eagle-import") (part "BSS138"))
    )
    (comp (ref "R23")
      (value "150R")
      (footprint "eagle-import:0402")
      (libsource (lib "eagle-import") (part "R0402"))
    )
    (comp (ref "R24")
      (value "10K")
      (footprint "eagle-import:0402")
      (libsource (lib "eagle-import") (part "R0402"))
    )
    (comp (ref "R25")
      (value "1K")
      (footprint "eagle-import:0402")
      (libsource (lib "eagle-import") (part "R0402"))
    )
    (comp (ref "D11")
      (value "BLUE")
      (footprint "eagle-import:D0603")
      (libsource (lib "eagle-import") (part "LED0603"))
    )
    (comp (ref "Q3")
      (value "BSS138")
      (footprint "eagle-import:SOT23")
      (libsource (lib "eagle-import") (part "BSS138"))
    )
    (comp (ref "R55")
      (value "180R")
      (footprint "eagle-import:0402")
      (libsource (lib "eagle-import") (part "R0402"))
    )
    (comp (ref "R56")
      (value "10K")
      (footprint "eagle-import:0402")
      (libsource (lib "eagle-import") (part "R0402"))
    )
    (comp (ref "R57")
      (value "1K")
      (footprint "eagle-import:0402")
      (libsource (lib "eagle-import") (part "R0402"))
    )
    (comp (ref "C112")
      (value "0.1uF")
      (footprint "eagle-import:0201")
      (libsource (lib "eagle-import") (part "C0201"))
    )
    (comp (ref "C113")
      (value "0.1uF")
      (footprint "eagle-import:0201")
      (libsource (lib "eagle-import") (part "C0201"))
    )
    (comp (ref "C114")
      (value "1.0uF")
      (footprint "eagle-import:0402")
      (libsource (lib "eagle-import") (part "C0402"))
    )
    (comp (ref "J11")
      (value "MA03X1 FEMALE")
      (footprint "eagle-import:MA03-100")
      (libsource (lib "eagle-import") (part "MA03X1100"))
    )
    (comp (ref "U27")
      (value "TXS0102")
      (footprint "eagle-import:DFN8-0.4P")
      (libsource (lib "eagle-import") (part "TXS0102"))
    )
    (comp (ref "GND")
      (value "DNP")
      (footprint "eagle-import:P1-13")
      (libsource (lib "eagle-import") (part "TP"))
    )
    (comp (ref "VCC")
      (value "DNP")
      (footprint "eagle-import:P1-13")
      (libsource (lib "eagle-import") (part "TP"))
    )
    (comp (ref "C1")
      (value "1.0uF")
      (footprint "eagle-import:0402")
      (libsource (lib "eagle-import") (part "C0402"))
    )
    (comp (ref "C2")
      (value "0.1uF")
      (footprint "eagle-import:0201")
      (libsource (lib "eagle-import") (part "C0201"))
    )
    (comp (ref "C3")
      (value "0.1uF")
      (footprint "eagle-import:0201")
      (libsource (lib "eagle-import") (part "C0201"))
    )
    (comp (ref "J1")
      (value "MA03X1 FEMALE")
      (footprint "eagle-import:MA03-100")
      (libsource (lib "eagle-import") (part "MA03X1100"))
    )
    (comp (ref "U1")
      (value "TXS0102")
      (footprint "eagle-import:DFN8-0.4P")
      (libsource (lib "eagle-import") (part "TXS0102"))
    )
    (comp (ref "C120")
      (value "4.7uF")
      (footprint "eagle-import:0603")
      (libsource (lib "eagle-import") (part "C0603"))
    )
    (comp (ref "D17")
      (value "PS04LTVA1")
      (footprint "eagle-import:D0402")
      (libsource (lib "eagle-import") (part "ESD-DIODE"))
    )
    (comp (ref "D18")
      (value "PS04LTVA1")
      (footprint "eagle-import:D0402")
      (libsource (lib "eagle-import") (part "ESD-DIODE"))
    )
    (comp (ref "D19")
      (value "B72590D50A060")
      (footprint "eagle-import:D0402")
      (libsource (lib "eagle-import") (part "ESD-DIODE"))
    )
    (comp (ref "D20")
      (value "B72590D50A060")
      (footprint "eagle-import:D0402")
      (libsource (lib "eagle-import") (part "ESD-DIODE"))
    )
    (comp (ref "J14")
      (value "USB_MICRO_B")
      (footprint "eagle-import:USB_MICRO_B")
      (libsource (lib "eagle-import") (part "USB_MICRO_B"))
    )
    (comp (ref "L6")
      (value "DLP11SN900HL2")
      (footprint "eagle-import:0504-DLP11S")
      (libsource (lib "eagle-import") (part "COM_MODE_CHOKE"))
    )
    (comp (ref "R82")
      (value "0R")
      (footprint "eagle-import:0402")
      (libsource (lib "eagle-import") (part "R0402"))
    )
    (comp (ref "C170")
      (value "12pF")
      (footprint "eagle-import:0201")
      (libsource (lib "eagle-import") (part "C0201"))
    )
    (comp (ref "C171")
      (value "12pF")
      (footprint "eagle-import:0201")
      (libsource (lib "eagle-import") (part "C0201"))
    )
    (comp (ref "R110")
      (value "DNP")
      (footprint "eagle-import:0603")
      (libsource (lib "eagle-import") (part "R0603"))
    )
    (comp (ref "R118")
      (value "0R")
      (footprint "eagle-import:0201")
      (libsource (lib "eagle-import") (part "R0201"))
    )
    (comp (ref "R128")
      (value "1K5")
      (footprint "eagle-import:0201")
      (libsource (lib "eagle-import") (part "R0201"))
    )
    (comp (ref "R130")
      (value "1K5")
      (footprint "eagle-import:0201")
      (libsource (lib "eagle-import") (part "R0201"))
    )
    (comp (ref "U$72")
      (value "AM3354BZCZ80")
      (footprint "eagle-import:BGA324C80P18X18")
      (libsource (lib "eagle-import") (part "AM335_ZCZ"))
    )
    (comp (ref "Y4")
      (value "32.768kHz")
      (footprint "eagle-import:1206")
      (libsource (lib "eagle-import") (part "X21206"))
    )
    (comp (ref "C57")
      (value "4.7uF")
      (footprint "eagle-import:0603")
      (libsource (lib "eagle-import") (part "C0603"))
    )
    (comp (ref "C58")
      (value "0.1uF")
      (footprint "eagle-import:0201")
      (libsource (lib "eagle-import") (part "C0201"))
    )
    (comp (ref "C59")
      (value "22uF")
      (footprint "eagle-import:0805")
      (libsource (lib "eagle-import") (part "C0805"))
    )
    (comp (ref "IC1")
      (value "EP5368")
      (footprint "eagle-import:EP-3X3MMQFN16")
      (libsource (lib "eagle-import") (part "EP5368"))
    )
    (comp (ref "C164")
      (value "1.0uF")
      (footprint "eagle-import:0201")
      (libsource (lib "eagle-import") (part "C0201"))
    )
    (comp (ref "C165")
      (value "1.0uF")
      (footprint "eagle-import:0201")
      (libsource (lib "eagle-import") (part "C0201"))
    )
    (comp (ref "C166")
      (value "1.0uF")
      (footprint "eagle-import:0201")
      (libsource (lib "eagle-import") (part "C0201"))
    )
    (comp (ref "C167")
      (value "1.0uF")
      (footprint "eagle-import:0201")
      (libsource (lib "eagle-import") (part "C0201"))
    )
    (comp (ref "R129")
      (value "49R9")
      (footprint "eagle-import:0201")
      (libsource (lib "eagle-import") (part "R0201"))
    )
    (comp (ref "U$79")
      (value "100K")
      (footprint "eagle-import:741C083")
      (libsource (lib "eagle-import") (part "741C083"))
    )
    (comp (ref "U$80")
      (value "100K")
      (footprint "eagle-import:741C083")
      (libsource (lib "eagle-import") (part "741C083"))
    )
    (comp (ref "U$81")
      (value "100K")
      (footprint "eagle-import:741C083")
      (libsource (lib "eagle-import") (part "741C083"))
    )
    (comp (ref "U$82")
      (value "100K")
      (footprint "eagle-import:741C083")
      (libsource (lib "eagle-import") (part "741C083"))
    )
    (comp (ref "D13")
      (value "PS04LTVA1")
      (footprint "eagle-import:D0402")
      (libsource (lib "eagle-import") (part "ESD-DIODE"))
    )
    (comp (ref "D14")
      (value "PS04LTVA1")
      (footprint "eagle-import:D0402")
      (libsource (lib "eagle-import") (part "ESD-DIODE"))
    )
    (comp (ref "D16")
      (value "B72590D50A060")
      (footprint "eagle-import:D0402")
      (libsource (lib "eagle-import") (part "ESD-DIODE"))
    )
    (comp (ref "J10")
      (value "USB_MICRO_B")
      (footprint "eagle-import:USB_MICRO_B")
      (libsource (lib "eagle-import") (part "USB_MICRO_B"))
    )
    (comp (ref "L5")
      (value "DLP11SN900HL2")
      (footprint "eagle-import:0504-DLP11S")
      (libsource (lib "eagle-import") (part "COM_MODE_CHOKE"))
    )
    (comp (ref "C96")
      (value "0.1uF")
      (footprint "eagle-import:0201")
      (libsource (lib "eagle-import") (part "C0201"))
    )
    (comp (ref "C97")
      (value "0.1uF")
      (footprint "eagle-import:0201")
      (libsource (lib "eagle-import") (part "C0201"))
    )
    (comp (ref "C98")
      (value "1.0uF")
      (footprint "eagle-import:0402")
      (libsource (lib "eagle-import") (part "C0402"))
    )
    (comp (ref "J8")
      (value "DNP")
      (footprint "eagle-import:MA03-100")
      (libsource (lib "eagle-import") (part "MA03X1100"))
    )
    (comp (ref "R138")
      (value "1K5")
      (footprint "eagle-import:0201")
      (libsource (lib "eagle-import") (part "R0201"))
    )
    (comp (ref "R139")
      (value "1K5")
      (footprint "eagle-import:0201")
      (libsource (lib "eagle-import") (part "R0201"))
    )
    (comp (ref "U21")
      (value "TXS0102")
      (footprint "eagle-import:DFN8-0.4P")
      (libsource (lib "eagle-import") (part "TXS0102"))
    )
    (comp (ref "C153")
      (value "0.1uF")
      (footprint "eagle-import:0402")
      (libsource (lib "eagle-import") (part "C0402"))
    )
    (comp (ref "C154")
      (value "0.1uF")
      (footprint "eagle-import:0402")
      (libsource (lib "eagle-import") (part "C0402"))
    )
    (comp (ref "C155")
      (value "0.1uF")
      (footprint "eagle-import:0402")
      (libsource (lib "eagle-import") (part "C0402"))
    )
    (comp (ref "C156")
      (value "0.1uF")
      (footprint "eagle-import:0402")
      (libsource (lib "eagle-import") (part "C0402"))
    )
    (comp (ref "C157")
      (value "0.1uF")
      (footprint "eagle-import:0402")
      (libsource (lib "eagle-import") (part "C0402"))
    )
    (comp (ref "C158")
      (value "10uF")
      (footprint "eagle-import:0603")
      (libsource (lib "eagle-import") (part "C0603"))
    )
    (comp (ref "C159")
      (value "10uF")
      (footprint "eagle-import:0603")
      (libsource (lib "eagle-import") (part "C0603"))
    )
    (comp (ref "C160")
      (value "10uF")
      (footprint "eagle-import:0603")
      (libsource (lib "eagle-import") (part "C0603"))
    )
    (comp (ref "C161")
      (value "0.1uF")
      (footprint "eagle-import:0402")
      (libsource (lib "eagle-import") (part "C0402"))
    )
    (comp (ref "C162")
      (value "0.1uF")
      (footprint "eagle-import:0402")
      (libsource (lib "eagle-import") (part "C0402"))
    )
    (comp (ref "C163")
      (value "0.1uF")
      (footprint "eagle-import:0402")
      (libsource (lib "eagle-import") (part "C0402"))
    )
    (comp (ref "D21")
      (value "PS04LTVA1")
      (footprint "eagle-import:D0402")
      (libsource (lib "eagle-import") (part "ESD-DIODE"))
    )
    (comp (ref "D22")
      (value "PS04LTVA1")
      (footprint "eagle-import:D0402")
      (libsource (lib "eagle-import") (part "ESD-DIODE"))
    )
    (comp (ref "D23")
      (value "PS04LTVA1")
      (footprint "eagle-import:D0402")
      (libsource (lib "eagle-import") (part "ESD-DIODE"))
    )
    (comp (ref "D24")
      (value "PS04LTVA1")
      (footprint "eagle-import:D0402")
      (libsource (lib "eagle-import") (part "ESD-DIODE"))
    )
    (comp (ref "D25")
      (value "PS04LTVA1")
      (footprint "eagle-import:D0402")
      (libsource (lib "eagle-import") (part "ESD-DIODE"))
    )
    (comp (ref "D26")
      (value "PS04LTVA1")
      (footprint "eagle-import:D0402")
      (libsource (lib "eagle-import") (part "ESD-DIODE"))
    )
    (comp (ref "D27")
      (value "PS04LTVA1")
      (footprint "eagle-import:D0402")
      (libsource (lib "eagle-import") (part "ESD-DIODE"))
    )
    (comp (ref "D28")
      (value "PS04LTVA1")
      (footprint "eagle-import:D0402")
      (libsource (lib "eagle-import") (part "ESD-DIODE"))
    )
    (comp (ref "D29")
      (value "PS04LTVA1")
      (footprint "eagle-import:D0402")
      (libsource (lib "eagle-import") (part "ESD-DIODE"))
    )
    (comp (ref "D30")
      (value "PS04LTVA1")
      (footprint "eagle-import:D0402")
      (libsource (lib "eagle-import") (part "ESD-DIODE"))
    )
    (comp (ref "FB7")
      (value "120R 1A")
      (footprint "eagle-import:0402")
      (libsource (lib "eagle-import") (part "FB0402"))
    )
    (comp (ref "FB8")
      (value "120R 1A")
      (footprint "eagle-import:0402")
      (libsource (lib "eagle-import") (part "FB0402"))
    )
    (comp (ref "IC4")
      (value "TFP410")
      (footprint "eagle-import:TQFP-64")
      (libsource (lib "eagle-import") (part "TFP100"))
    )
    (comp (ref "J15")
      (value "HDMIMICRO")
      (footprint "eagle-import:46765-001")
      (libsource (lib "eagle-import") (part "HDMIMICRO"))
    )
    (comp (ref "L7")
      (value "DLP0NSN900HL2")
      (footprint "eagle-import:03025-DLP0NS")
      (libsource (lib "eagle-import") (part "COM_MODE_CHOKE03025"))
    )
    (comp (ref "L8")
      (value "DLP0NSN900HL2")
      (footprint "eagle-import:03025-DLP0NS")
      (libsource (lib "eagle-import") (part "COM_MODE_CHOKE03025"))
    )
    (comp (ref "L9")
      (value "DLP0NSN900HL2")
      (footprint "eagle-import:03025-DLP0NS")
      (libsource (lib "eagle-import") (part "COM_MODE_CHOKE03025"))
    )
    (comp (ref "L10")
      (value "DLP0NSN900HL2")
      (footprint "eagle-import:03025-DLP0NS")
      (libsource (lib "eagle-import") (part "COM_MODE_CHOKE03025"))
    )
    (comp (ref "R96")
      (value "10K")
      (footprint "eagle-import:0402")
      (libsource (lib "eagle-import") (part "R0402"))
    )
    (comp (ref "R97")
      (value "10K")
      (footprint "eagle-import:0402")
      (libsource (lib "eagle-import") (part "R0402"))
    )
    (comp (ref "R98")
      (value "10K")
      (footprint "eagle-import:0402")
      (libsource (lib "eagle-import") (part "R0402"))
    )
    (comp (ref "R99")
      (value "10K")
      (footprint "eagle-import:0402")
      (libsource (lib "eagle-import") (part "R0402"))
    )
    (comp (ref "R100")
      (value "10K")
      (footprint "eagle-import:0402")
      (libsource (lib "eagle-import") (part "R0402"))
    )
    (comp (ref "R101")
      (value "10K")
      (footprint "eagle-import:0402")
      (libsource (lib "eagle-import") (part "R0402"))
    )
    (comp (ref "R102")
      (value "510R")
      (footprint "eagle-import:0402")
      (libsource (lib "eagle-import") (part "R0402"))
    )
    (comp (ref "R103")
      (value "10K")
      (footprint "eagle-import:0402")
      (libsource (lib "eagle-import") (part "R0402"))
    )
    (comp (ref "R104")
      (value "4K7")
      (footprint "eagle-import:0402")
      (libsource (lib "eagle-import") (part "R0402"))
    )
    (comp (ref "R105")
      (value "10K")
      (footprint "eagle-import:0402")
      (libsource (lib "eagle-import") (part "R0402"))
    )
    (comp (ref "R106")
      (value "200K")
      (footprint "eagle-import:0402")
      (libsource (lib "eagle-import") (part "R0402"))
    )
    (comp (ref "R107")
      (value "1K5")
      (footprint "eagle-import:0402")
      (libsource (lib "eagle-import") (part "R0402"))
    )
    (comp (ref "R108")
      (value "1K5")
      (footprint "eagle-import:0402")
      (libsource (lib "eagle-import") (part "R0402"))
    )
    (comp (ref "R109")
      (value "1K5")
      (footprint "eagle-import:0402")
      (libsource (lib "eagle-import") (part "R0402"))
    )
    (comp (ref "R112")
      (value "1K5")
      (footprint "eagle-import:0402")
      (libsource (lib "eagle-import") (part "R0402"))
    )
    (comp (ref "R113")
      (value "10R0")
      (footprint "eagle-import:0402")
      (libsource (lib "eagle-import") (part "R0402"))
    )
    (comp (ref "R114")
      (value "DNP")
      (footprint "eagle-import:0402")
      (libsource (lib "eagle-import") (part "R0402"))
    )
    (comp (ref "R115")
      (value "10R0")
      (footprint "eagle-import:0402")
      (libsource (lib "eagle-import") (part "R0402"))
    )
    (comp (ref "R116")
      (value "10R0")
      (footprint "eagle-import:0402")
      (libsource (lib "eagle-import") (part "R0402"))
    )
    (comp (ref "R117")
      (value "10R0")
      (footprint "eagle-import:0402")
      (libsource (lib "eagle-import") (part "R0402"))
    )
    (comp (ref "RP8")
      (value "10R0")
      (footprint "eagle-import:741X16")
      (libsource (lib "eagle-import") (part "RP741X163"))
    )
    (comp (ref "RP9")
      (value "10R0")
      (footprint "eagle-import:741X16")
      (libsource (lib "eagle-import") (part "RP741X163"))
    )
    (comp (ref "RP10")
      (value "10R0")
      (footprint "eagle-import:741X16")
      (libsource (lib "eagle-import") (part "RP741X163"))
    )
    (comp (ref "U33")
      (value "PCA9306")
      (footprint "eagle-import:DCT-8(SSOP)")
      (libsource (lib "eagle-import") (part "PCA9306"))
    )
    (comp (ref "C99")
      (value "10uF")
      (footprint "eagle-import:0402")
      (libsource (lib "eagle-import") (part "C0402"))
    )
    (comp (ref "C100")
      (value "10uF")
      (footprint "eagle-import:0402")
      (libsource (lib "eagle-import") (part "C0402"))
    )
    (comp (ref "C101")
      (value "0.1uF")
      (footprint "eagle-import:0201")
      (libsource (lib "eagle-import") (part "C0201"))
    )
    (comp (ref "C102")
      (value "0.1uF")
      (footprint "eagle-import:0201")
      (libsource (lib "eagle-import") (part "C0201"))
    )
    (comp (ref "C103")
      (value "1.0uF")
      (footprint "eagle-import:0402")
      (libsource (lib "eagle-import") (part "C0402"))
    )
    (comp (ref "F4")
      (value "MF-FSMF020X-2")
      (footprint "eagle-import:0603")
      (libsource (lib "eagle-import") (part "PTC0603"))
    )
    (comp (ref "F5")
      (value "MF-FSMF020X-2")
      (footprint "eagle-import:0603")
      (libsource (lib "eagle-import") (part "PTC0603"))
    )
    (comp (ref "J9")
      (value "MA03X2 FEMALE")
      (footprint "eagle-import:MA03-2")
      (libsource (lib "eagle-import") (part "MA03X2"))
    )
    (comp (ref "U22")
      (value "TXS0102")
      (footprint "eagle-import:DFN8-0.4P")
      (libsource (lib "eagle-import") (part "TXS0102"))
    )
    (comp (ref "C104")
      (value "0.1uF")
      (footprint "eagle-import:0402")
      (libsource (lib "eagle-import") (part "C0402"))
    )
    (comp (ref "R61")
      (value "15K")
      (footprint "eagle-import:0402")
      (libsource (lib "eagle-import") (part "R0402"))
    )
    (comp (ref "R62")
      (value "18K")
      (footprint "eagle-import:0402")
      (libsource (lib "eagle-import") (part "R0402"))
    )
    (comp (ref "S2")
      (value "EVQ")
      (footprint "eagle-import:EVQ")
      (libsource (lib "eagle-import") (part "EVQ"))
    )
    (comp (ref "C4")
      (value "10uF")
      (footprint "eagle-import:0402")
      (libsource (lib "eagle-import") (part "C0402"))
    )
    (comp (ref "C5")
      (value "10uF")
      (footprint "eagle-import:0402")
      (libsource (lib "eagle-import") (part "C0402"))
    )
    (comp (ref "C6")
      (value "0.1uF")
      (footprint "eagle-import:0201")
      (libsource (lib "eagle-import") (part "C0201"))
    )
    (comp (ref "C7")
      (value "0.1uF")
      (footprint "eagle-import:0201")
      (libsource (lib "eagle-import") (part "C0201"))
    )
    (comp (ref "C8")
      (value "1.0uF")
      (footprint "eagle-import:0402")
      (libsource (lib "eagle-import") (part "C0402"))
    )
    (comp (ref "F1")
      (value "MF-FSMF020X-2")
      (footprint "eagle-import:0603")
      (libsource (lib "eagle-import") (part "PTC0603"))
    )
    (comp (ref "F2")
      (value "MF-FSMF020X-2")
      (footprint "eagle-import:0603")
      (libsource (lib "eagle-import") (part "PTC0603"))
    )
    (comp (ref "J2")
      (value "MA03X2 FEMALE")
      (footprint "eagle-import:MA03-2")
      (libsource (lib "eagle-import") (part "MA03X2"))
    )
    (comp (ref "U2")
      (value "TXS0102")
      (footprint "eagle-import:DFN8-0.4P")
      (libsource (lib "eagle-import") (part "TXS0102"))
    )
    (comp (ref "J3")
      (value "ML-621S/ZTN")
      (footprint "eagle-import:BATTERY_6.8MM-2998")
      (libsource (lib "eagle-import") (part "COIN_CELL_6.8MM"))
    )
    (comp (ref "R3")
      (value "10K")
      (footprint "eagle-import:0201")
      (libsource (lib "eagle-import") (part "R0201"))
    )
    (comp (ref "U3")
      (value "DS1340")
      (footprint "eagle-import:SO-8")
      (libsource (lib "eagle-import") (part "DS1339"))
    )
    (comp (ref "X1")
      (value "32.768")
      (footprint "eagle-import:CM415")
      (libsource (lib "eagle-import") (part "X2CM415"))
    )
    (comp (ref "C70")
      (value "1.0uF")
      (footprint "eagle-import:0402")
      (libsource (lib "eagle-import") (part "C0402"))
    )
    (comp (ref "C71")
      (value "0.1uF")
      (footprint "eagle-import:0402")
      (libsource (lib "eagle-import") (part "C0402"))
    )
    (comp (ref "C72")
      (value "1.0uF")
      (footprint "eagle-import:0402")
      (libsource (lib "eagle-import") (part "C0402"))
    )
    (comp (ref "C73")
      (value "0.1uF")
      (footprint "eagle-import:0402")
      (libsource (lib "eagle-import") (part "C0402"))
    )
    (comp (ref "C74")
      (value "0.1uF")
      (footprint "eagle-import:0402")
      (libsource (lib "eagle-import") (part "C0402"))
    )
    (comp (ref "C75")
      (value "0.1uF")
      (footprint "eagle-import:0402")
      (libsource (lib "eagle-import") (part "C0402"))
    )
    (comp (ref "C76")
      (value "0.1uF")
      (footprint "eagle-import:0402")
      (libsource (lib "eagle-import") (part "C0402"))
    )
    (comp (ref "C77")
      (value "0.1uF")
      (footprint "eagle-import:0402")
      (libsource (lib "eagle-import") (part "C0402"))
    )
    (comp (ref "C78")
      (value "0.1uF")
      (footprint "eagle-import:0402")
      (libsource (lib "eagle-import") (part "C0402"))
    )
    (comp (ref "C79")
      (value "0.1uF")
      (footprint "eagle-import:0402")
      (libsource (lib "eagle-import") (part "C0402"))
    )
    (comp (ref "C80")
      (value "0.1uF")
      (footprint "eagle-import:0402")
      (libsource (lib "eagle-import") (part "C0402"))
    )
    (comp (ref "C81")
      (value "1.0uF")
      (footprint "eagle-import:0402")
      (libsource (lib "eagle-import") (part "C0402"))
    )
    (comp (ref "C82")
      (value "4.7uF")
      (footprint "eagle-import:0603")
      (libsource (lib "eagle-import") (part "C0603"))
    )
    (comp (ref "C83")
      (value "22pF")
      (footprint "eagle-import:0402")
      (libsource (lib "eagle-import") (part "C0402"))
    )
    (comp (ref "C84")
      (value "22pF")
      (footprint "eagle-import:0402")
      (libsource (lib "eagle-import") (part "C0402"))
    )
    (comp (ref "C85")
      (value "0.1uF")
      (footprint "eagle-import:0402")
      (libsource (lib "eagle-import") (part "C0402"))
    )
    (comp (ref "R44")
      (value "DNP")
      (footprint "eagle-import:0402")
      (libsource (lib "eagle-import") (part "R0402"))
    )
    (comp (ref "R45")
      (value "100K")
      (footprint "eagle-import:0402")
      (libsource (lib "eagle-import") (part "R0402"))
    )
    (comp (ref "R46")
      (value "12K0")
      (footprint "eagle-import:0402")
      (libsource (lib "eagle-import") (part "R0402"))
    )
    (comp (ref "R47")
      (value "100K")
      (footprint "eagle-import:0402")
      (libsource (lib "eagle-import") (part "R0402"))
    )
    (comp (ref "R48")
      (value "100K")
      (footprint "eagle-import:0402")
      (libsource (lib "eagle-import") (part "R0402"))
    )
    (comp (ref "R49")
      (value "100K")
      (footprint "eagle-import:0402")
      (libsource (lib "eagle-import") (part "R0402"))
    )
    (comp (ref "R50")
      (value "100K")
      (footprint "eagle-import:0402")
      (libsource (lib "eagle-import") (part "R0402"))
    )
    (comp (ref "R51")
      (value "1M0")
      (footprint "eagle-import:0402")
      (libsource (lib "eagle-import") (part "R0402"))
    )
    (comp (ref "U18")
      (value "USB2513")
      (footprint "eagle-import:QFN36-6X6MM")
      (libsource (lib "eagle-import") (part "USB2513"))
    )
    (comp (ref "U19")
      (value "OR_GATE_3")
      (footprint "eagle-import:SOT-23-6")
      (libsource (lib "eagle-import") (part "OR_GATE_3"))
    )
    (comp (ref "Y1")
      (value "24.000MHz")
      (footprint "eagle-import:CRYSTAL-3225")
      (libsource (lib "eagle-import") (part "Y4CRYSTAL-3225"))
    )
    (comp (ref "C220")
      (value "0.1uF")
      (footprint "eagle-import:0201")
      (libsource (lib "eagle-import") (part "C0201"))
    )
    (comp (ref "C252")
      (value "0.1uF")
      (footprint "eagle-import:0201")
      (libsource (lib "eagle-import") (part "C0201"))
    )
    (comp (ref "C253")
      (value "0.1uF")
      (footprint "eagle-import:0201")
      (libsource (lib "eagle-import") (part "C0201"))
    )
    (comp (ref "C254")
      (value "0.1uF")
      (footprint "eagle-import:0201")
      (libsource (lib "eagle-import") (part "C0201"))
    )
    (comp (ref "C255")
      (value "0.1uF")
      (footprint "eagle-import:0201")
      (libsource (lib "eagle-import") (part "C0201"))
    )
    (comp (ref "C256")
      (value "0.1uF")
      (footprint "eagle-import:0201")
      (libsource (lib "eagle-import") (part "C0201"))
    )
    (comp (ref "C257")
      (value "0.1uF")
      (footprint "eagle-import:0201")
      (libsource (lib "eagle-import") (part "C0201"))
    )
    (comp (ref "C258")
      (value "0.1uF")
      (footprint "eagle-import:0201")
      (libsource (lib "eagle-import") (part "C0201"))
    )
    (comp (ref "C259")
      (value "0.1uF")
      (footprint "eagle-import:0201")
      (libsource (lib "eagle-import") (part "C0201"))
    )
    (comp (ref "C260")
      (value "0.1uF")
      (footprint "eagle-import:0201")
      (libsource (lib "eagle-import") (part "C0201"))
    )
    (comp (ref "C261")
      (value "0.1uF")
      (footprint "eagle-import:0201")
      (libsource (lib "eagle-import") (part "C0201"))
    )
    (comp (ref "C262")
      (value "0.1uF")
      (footprint "eagle-import:0201")
      (libsource (lib "eagle-import") (part "C0201"))
    )
    (comp (ref "R122")
      (value "1K5")
      (footprint "eagle-import:0201")
      (libsource (lib "eagle-import") (part "R0201"))
    )
    (comp (ref "R123")
      (value "1K5")
      (footprint "eagle-import:0201")
      (libsource (lib "eagle-import") (part "R0201"))
    )
    (comp (ref "R131")
      (value "10K")
      (footprint "eagle-import:0201")
      (libsource (lib "eagle-import") (part "R0201"))
    )
    (comp (ref "R132")
      (value "10K")
      (footprint "eagle-import:0201")
      (libsource (lib "eagle-import") (part "R0201"))
    )
    (comp (ref "R133")
      (value "240R0")
      (footprint "eagle-import:0201")
      (libsource (lib "eagle-import") (part "R0201"))
    )
    (comp (ref "R134")
      (value "1K5")
      (footprint "eagle-import:0201")
      (libsource (lib "eagle-import") (part "R0201"))
    )
    (comp (ref "R135")
      (value "10K")
      (footprint "eagle-import:0201")
      (libsource (lib "eagle-import") (part "R0201"))
    )
    (comp (ref "R340")
      (value "100K")
      (footprint "eagle-import:0201")
      (libsource (lib "eagle-import") (part "R0201"))
    )
    (comp (ref "R342")
      (value "100K")
      (footprint "eagle-import:0201")
      (libsource (lib "eagle-import") (part "R0201"))
    )
    (comp (ref "R344")
      (value "100K")
      (footprint "eagle-import:0201")
      (libsource (lib "eagle-import") (part "R0201"))
    )
    (comp (ref "U$101")
      (value "MT41K256M16")
      (footprint "eagle-import:FBGA_96_10_14")
      (libsource (lib "eagle-import") (part "MT41K256M16"))
    )
    (comp (ref "U34")
      (value "AT24C01B-TH_B")
      (footprint "eagle-import:TSSOP8")
      (libsource (lib "eagle-import") (part "AT24CA"))
    )
    (comp (ref "C21")
      (value "0.1uF")
      (footprint "eagle-import:0201")
      (libsource (lib "eagle-import") (part "C0201"))
    )
    (comp (ref "C22")
      (value "0.1uF")
      (footprint "eagle-import:0201")
      (libsource (lib "eagle-import") (part "C0201"))
    )
    (comp (ref "C23")
      (value "1.0uF")
      (footprint "eagle-import:0402")
      (libsource (lib "eagle-import") (part "C0402"))
    )
    (comp (ref "J6")
      (value "DNP")
      (footprint "eagle-import:MA03-100")
      (libsource (lib "eagle-import") (part "MA03X1100"))
    )
    (comp (ref "U11")
      (value "TXS0102")
      (footprint "eagle-import:DFN8-0.4P")
      (libsource (lib "eagle-import") (part "TXS0102"))
    )
    (comp (ref "C144")
      (value "0.1uF")
      (footprint "eagle-import:0201")
      (libsource (lib "eagle-import") (part "C0201"))
    )
    (comp (ref "C145")
      (value "0.1uF")
      (footprint "eagle-import:0201")
      (libsource (lib "eagle-import") (part "C0201"))
    )
    (comp (ref "C146")
      (value "0.1uF")
      (footprint "eagle-import:0201")
      (libsource (lib "eagle-import") (part "C0201"))
    )
    (comp (ref "C147")
      (value "0.1uF")
      (footprint "eagle-import:0201")
      (libsource (lib "eagle-import") (part "C0201"))
    )
    (comp (ref "C148")
      (value "0.1uF")
      (footprint "eagle-import:0201")
      (libsource (lib "eagle-import") (part "C0201"))
    )
    (comp (ref "C149")
      (value "0.1uF")
      (footprint "eagle-import:0201")
      (libsource (lib "eagle-import") (part "C0201"))
    )
    (comp (ref "C150")
      (value "0.1uF")
      (footprint "eagle-import:0201")
      (libsource (lib "eagle-import") (part "C0201"))
    )
    (comp (ref "C151")
      (value "0.1uF")
      (footprint "eagle-import:0201")
      (libsource (lib "eagle-import") (part "C0201"))
    )
    (comp (ref "C152")
      (value "0.1uF")
      (footprint "eagle-import:0201")
      (libsource (lib "eagle-import") (part "C0201"))
    )
    (comp (ref "R95")
      (value "75K")
      (footprint "eagle-import:0402")
      (libsource (lib "eagle-import") (part "R0402"))
    )
    (comp (ref "U$66")
      (value "ADS7846RGV")
      (footprint "eagle-import:QFN16")
      (libsource (lib "eagle-import") (part "ADS7846RGV"))
    )
    (comp (ref "U$67")
      (value "SN74LVC16T245")
      (footprint "eagle-import:TVSOP48")
      (libsource (lib "eagle-import") (part "74AC164245TVSOP"))
    )
    (comp (ref "U$68")
      (value "SN74LVC16T245")
      (footprint "eagle-import:TVSOP48")
      (libsource (lib "eagle-import") (part "74AC164245TVSOP"))
    )
    (comp (ref "U$69")
      (value "SN74LVC16T245")
      (footprint "eagle-import:TVSOP48")
      (libsource (lib "eagle-import") (part "74AC164245TVSOP"))
    )
    (comp (ref "U$70")
      (value "FH12-40-NHD-4.3")
      (footprint "eagle-import:FH12-40S-0.5SH")
      (libsource (lib "eagle-import") (part "FH12-40-NHD-4.3"))
    )
    (comp (ref "D12")
      (value "YELLOW")
      (footprint "eagle-import:D0603")
      (libsource (lib "eagle-import") (part "LED0603"))
    )
    (comp (ref "Q4")
      (value "BSS138")
      (footprint "eagle-import:SOT23")
      (libsource (lib "eagle-import") (part "BSS138"))
    )
    (comp (ref "R58")
      (value "180R")
      (footprint "eagle-import:0402")
      (libsource (lib "eagle-import") (part "R0402"))
    )
    (comp (ref "R59")
      (value "10K")
      (footprint "eagle-import:0402")
      (libsource (lib "eagle-import") (part "R0402"))
    )
    (comp (ref "R60")
      (value "1K")
      (footprint "eagle-import:0402")
      (libsource (lib "eagle-import") (part "R0402"))
    )
    (comp (ref "C60")
      (value "10pF")
      (footprint "eagle-import:0402")
      (libsource (lib "eagle-import") (part "C0402"))
    )
    (comp (ref "C61")
      (value "0.1uF / 16V")
      (footprint "eagle-import:0402")
      (libsource (lib "eagle-import") (part "C0402"))
    )
    (comp (ref "C62")
      (value "1.0uF")
      (footprint "eagle-import:0603")
      (libsource (lib "eagle-import") (part "C0603"))
    )
    (comp (ref "C63")
      (value "10uF / 16V")
      (footprint "eagle-import:0805")
      (libsource (lib "eagle-import") (part "C0805"))
    )
    (comp (ref "C64")
      (value "22uF")
      (footprint "eagle-import:0805")
      (libsource (lib "eagle-import") (part "C0805"))
    )
    (comp (ref "IC2")
      (value "TPS62111")
      (footprint "eagle-import:PQFP16")
      (libsource (lib "eagle-import") (part "TPS62111"))
    )
    (comp (ref "L1")
      (value "6.8uH")
      (footprint "eagle-import:1515")
      (libsource (lib "eagle-import") (part "L1515"))
    )
    (comp (ref "R38")
      (value "1M0")
      (footprint "eagle-import:0402")
      (libsource (lib "eagle-import") (part "R0402"))
    )
    (comp (ref "R39")
      (value "0R")
      (footprint "eagle-import:0402")
      (libsource (lib "eagle-import") (part "R0402"))
    )
    (comp (ref "R40")
      (value "DNP")
      (footprint "eagle-import:0402")
      (libsource (lib "eagle-import") (part "R0402"))
    )
    (comp (ref "C16")
      (value "0.1uF")
      (footprint "eagle-import:0201")
      (libsource (lib "eagle-import") (part "C0201"))
    )
    (comp (ref "C17")
      (value "0.1uF")
      (footprint "eagle-import:0201")
      (libsource (lib "eagle-import") (part "C0201"))
    )
    (comp (ref "RP3")
      (value "DNP")
      (footprint "eagle-import:741X08")
      (libsource (lib "eagle-import") (part "RP741X083"))
    )
    (comp (ref "U8")
      (value "TXS0108E")
      (footprint "eagle-import:QFN20")
      (libsource (lib "eagle-import") (part "TXS0108E"))
    )
    (comp (ref "C55")
      (value "0.1uF")
      (footprint "eagle-import:0201")
      (libsource (lib "eagle-import") (part "C0201"))
    )
    (comp (ref "C56")
      (value "0.1uF")
      (footprint "eagle-import:0201")
      (libsource (lib "eagle-import") (part "C0201"))
    )
    (comp (ref "R36")
      (value "DNP")
      (footprint "eagle-import:0201")
      (libsource (lib "eagle-import") (part "R0201"))
    )
    (comp (ref "R37")
      (value "DNP")
      (footprint "eagle-import:0201")
      (libsource (lib "eagle-import") (part "R0201"))
    )
    (comp (ref "U16")
      (value "74AVC2T245")
      (footprint "eagle-import:UQFN-10")
      (libsource (lib "eagle-import") (part "74AVC2T245"))
    )
    (comp (ref "BOOT0")
      (value "DNP")
      (footprint "eagle-import:TP0500")
      (libsource (lib "eagle-import") (part "TP05"))
    )
    (comp (ref "C121")
      (value "22pF")
      (footprint "eagle-import:0402")
      (libsource (lib "eagle-import") (part "C0402"))
    )
    (comp (ref "C122")
      (value "22pF")
      (footprint "eagle-import:0402")
      (libsource (lib "eagle-import") (part "C0402"))
    )
    (comp (ref "C123")
      (value "0.1uF")
      (footprint "eagle-import:0201")
      (libsource (lib "eagle-import") (part "C0201"))
    )
    (comp (ref "C124")
      (value "4.7uF")
      (footprint "eagle-import:0603")
      (libsource (lib "eagle-import") (part "C0603"))
    )
    (comp (ref "C125")
      (value "0.1uF")
      (footprint "eagle-import:0201")
      (libsource (lib "eagle-import") (part "C0201"))
    )
    (comp (ref "C126")
      (value "0.1uF")
      (footprint "eagle-import:0201")
      (libsource (lib "eagle-import") (part "C0201"))
    )
    (comp (ref "C127")
      (value "0.1uF")
      (footprint "eagle-import:0201")
      (libsource (lib "eagle-import") (part "C0201"))
    )
    (comp (ref "C128")
      (value "0.1uF")
      (footprint "eagle-import:0201")
      (libsource (lib "eagle-import") (part "C0201"))
    )
    (comp (ref "C129")
      (value "0.1uF")
      (footprint "eagle-import:0201")
      (libsource (lib "eagle-import") (part "C0201"))
    )
    (comp (ref "C130")
      (value "0.1uF")
      (footprint "eagle-import:0201")
      (libsource (lib "eagle-import") (part "C0201"))
    )
    (comp (ref "C131")
      (value "1.0uF")
      (footprint "eagle-import:0402")
      (libsource (lib "eagle-import") (part "C0402"))
    )
    (comp (ref "C132")
      (value "0.01uF")
      (footprint "eagle-import:0201")
      (libsource (lib "eagle-import") (part "C0201"))
    )
    (comp (ref "C133")
      (value "1.0uF")
      (footprint "eagle-import:0402")
      (libsource (lib "eagle-import") (part "C0402"))
    )
    (comp (ref "C134")
      (value "0.01uF")
      (footprint "eagle-import:0201")
      (libsource (lib "eagle-import") (part "C0201"))
    )
    (comp (ref "C135")
      (value "2.2uF")
      (footprint "eagle-import:0603")
      (libsource (lib "eagle-import") (part "C0603"))
    )
    (comp (ref "C136")
      (value "2.2uF")
      (footprint "eagle-import:0603")
      (libsource (lib "eagle-import") (part "C0603"))
    )
    (comp (ref "C137")
      (value "4.7uF")
      (footprint "eagle-import:0603")
      (libsource (lib "eagle-import") (part "C0603"))
    )
    (comp (ref "C138")
      (value "0.1uF")
      (footprint "eagle-import:0201")
      (libsource (lib "eagle-import") (part "C0201"))
    )
    (comp (ref "FB9")
      (value "120R 1A")
      (footprint "eagle-import:0402")
      (libsource (lib "eagle-import") (part "FB0402"))
    )
    (comp (ref "IC3")
      (value "STM32F10XVXT6-FLASH")
      (footprint "eagle-import:TQFP100")
      (libsource (lib "eagle-import") (part "STM32F10XVXT6"))
    )
    (comp (ref "JTAG")
      (value "DNP")
      (footprint "eagle-import:1365-10")
      (libsource (lib "eagle-import") (part "1365-10"))
    )
    (comp (ref "R63")
      (value "DNP")
      (footprint "eagle-import:0603")
      (libsource (lib "eagle-import") (part "R0603"))
    )
    (comp (ref "R83")
      (value "240R0")
      (footprint "eagle-import:0201")
      (libsource (lib "eagle-import") (part "R0201"))
    )
    (comp (ref "R84")
      (value "33R0")
      (footprint "eagle-import:0201")
      (libsource (lib "eagle-import") (part "R0201"))
    )
    (comp (ref "R85")
      (value "100K")
      (footprint "eagle-import:0402")
      (libsource (lib "eagle-import") (part "R0402"))
    )
    (comp (ref "R86")
      (value "10K")
      (footprint "eagle-import:0201")
      (libsource (lib "eagle-import") (part "R0201"))
    )
    (comp (ref "R87")
      (value "0R")
      (footprint "eagle-import:0201")
      (libsource (lib "eagle-import") (part "R0201"))
    )
    (comp (ref "R88")
      (value "100K")
      (footprint "eagle-import:0201")
      (libsource (lib "eagle-import") (part "R0201"))
    )
    (comp (ref "R89")
      (value "10K")
      (footprint "eagle-import:0201")
      (libsource (lib "eagle-import") (part "R0201"))
    )
    (comp (ref "R90")
      (value "0R")
      (footprint "eagle-import:0201")
      (libsource (lib "eagle-import") (part "R0201"))
    )
    (comp (ref "R91")
      (value "10K")
      (footprint "eagle-import:0201")
      (libsource (lib "eagle-import") (part "R0201"))
    )
    (comp (ref "R92")
      (value "100K")
      (footprint "eagle-import:0201")
      (libsource (lib "eagle-import") (part "R0201"))
    )
    (comp (ref "R111")
      (value "DNP")
      (footprint "eagle-import:0603")
      (libsource (lib "eagle-import") (part "R0603"))
    )
    (comp (ref "R136")
      (value "DNP")
      (footprint "eagle-import:0603")
      (libsource (lib "eagle-import") (part "R0603"))
    )
    (comp (ref "R137")
      (value "DNP")
      (footprint "eagle-import:0603")
      (libsource (lib "eagle-import") (part "R0603"))
    )
    (comp (ref "U31")
      (value "EVQKMT0")
      (footprint "eagle-import:KMT0")
      (libsource (lib "eagle-import") (part "EVQKMT0"))
    )
    (comp (ref "VCC1")
      (value "DNP")
      (footprint "eagle-import:TP0500")
      (libsource (lib "eagle-import") (part "TP05"))
    )
    (comp (ref "Y2")
      (value "24.000MHz")
      (footprint "eagle-import:CRYSTAL-3225")
      (libsource (lib "eagle-import") (part "Y4CRYSTAL-3225"))
    )
    (comp (ref "C33")
      (value "1.0uF")
      (footprint "eagle-import:0402")
      (libsource (lib "eagle-import") (part "C0402"))
    )
    (comp (ref "C34")
      (value "0.1uF")
      (footprint "eagle-import:0201")
      (libsource (lib "eagle-import") (part "C0201"))
    )
    (comp (ref "C35")
      (value "1.0uF")
      (footprint "eagle-import:0402")
      (libsource (lib "eagle-import") (part "C0402"))
    )
    (comp (ref "C36")
      (value "0.1uF")
      (footprint "eagle-import:0201")
      (libsource (lib "eagle-import") (part "C0201"))
    )
    (comp (ref "C37")
      (value "1.0uF")
      (footprint "eagle-import:0402")
      (libsource (lib "eagle-import") (part "C0402"))
    )
    (comp (ref "C38")
      (value "0.1uF")
      (footprint "eagle-import:0201")
      (libsource (lib "eagle-import") (part "C0201"))
    )
    (comp (ref "C39")
      (value "10uF")
      (footprint "eagle-import:0603")
      (libsource (lib "eagle-import") (part "C0603"))
    )
    (comp (ref "C40")
      (value "1.0uF")
      (footprint "eagle-import:0402")
      (libsource (lib "eagle-import") (part "C0402"))
    )
    (comp (ref "C41")
      (value "0.1uF")
      (footprint "eagle-import:0201")
      (libsource (lib "eagle-import") (part "C0201"))
    )
    (comp (ref "C42")
      (value "1.0uF")
      (footprint "eagle-import:0402")
      (libsource (lib "eagle-import") (part "C0402"))
    )
    (comp (ref "C51")
      (value "0.1uF")
      (footprint "eagle-import:0201")
      (libsource (lib "eagle-import") (part "C0201"))
    )
    (comp (ref "C52")
      (value "0.47uF")
      (footprint "eagle-import:0402")
      (libsource (lib "eagle-import") (part "C0402"))
    )
    (comp (ref "C53")
      (value "0.47uF")
      (footprint "eagle-import:0402")
      (libsource (lib "eagle-import") (part "C0402"))
    )
    (comp (ref "C54")
      (value "0.47uF")
      (footprint "eagle-import:0402")
      (libsource (lib "eagle-import") (part "C0402"))
    )
    (comp (ref "R26")
      (value "100K")
      (footprint "eagle-import:0201")
      (libsource (lib "eagle-import") (part "R0201"))
    )
    (comp (ref "R27")
      (value "DNP")
      (footprint "eagle-import:0201")
      (libsource (lib "eagle-import") (part "R0201"))
    )
    (comp (ref "R28")
      (value "DNP")
      (footprint "eagle-import:0201")
      (libsource (lib "eagle-import") (part "R0201"))
    )
    (comp (ref "R29")
      (value "100K")
      (footprint "eagle-import:0201")
      (libsource (lib "eagle-import") (part "R0201"))
    )
    (comp (ref "R30")
      (value "100K")
      (footprint "eagle-import:0201")
      (libsource (lib "eagle-import") (part "R0201"))
    )
    (comp (ref "R31")
      (value "100K")
      (footprint "eagle-import:0201")
      (libsource (lib "eagle-import") (part "R0201"))
    )
    (comp (ref "R32")
      (value "1K5")
      (footprint "eagle-import:0201")
      (libsource (lib "eagle-import") (part "R0201"))
    )
    (comp (ref "R34")
      (value "0R")
      (footprint "eagle-import:0201")
      (libsource (lib "eagle-import") (part "R0201"))
    )
    (comp (ref "R35")
      (value "0R")
      (footprint "eagle-import:0201")
      (libsource (lib "eagle-import") (part "R0201"))
    )
    (comp (ref "U15")
      (value "TLV320AIC3106")
      (footprint "eagle-import:QFN48")
      (libsource (lib "eagle-import") (part "TLV320AIC3106"))
    )
    (comp (ref "X2")
      (value "12MHz 1.8V")
      (footprint "eagle-import:ASF")
      (libsource (lib "eagle-import") (part "ASF1"))
    )
    (comp (ref "C168")
      (value "12pF")
      (footprint "eagle-import:0201")
      (libsource (lib "eagle-import") (part "C0201"))
    )
    (comp (ref "C169")
      (value "12pF")
      (footprint "eagle-import:0201")
      (libsource (lib "eagle-import") (part "C0201"))
    )
    (comp (ref "C172")
      (value "0.01uF")
      (footprint "eagle-import:0201")
      (libsource (lib "eagle-import") (part "C0201"))
    )
    (comp (ref "C173")
      (value "0.01uF")
      (footprint "eagle-import:0201")
      (libsource (lib "eagle-import") (part "C0201"))
    )
    (comp (ref "C176")
      (value "0.01uF")
      (footprint "eagle-import:0201")
      (libsource (lib "eagle-import") (part "C0201"))
    )
    (comp (ref "C177")
      (value "0.01uF")
      (footprint "eagle-import:0201")
      (libsource (lib "eagle-import") (part "C0201"))
    )
    (comp (ref "C178")
      (value "0.01uF")
      (footprint "eagle-import:0201")
      (libsource (lib "eagle-import") (part "C0201"))
    )
    (comp (ref "C179")
      (value "0.01uF")
      (footprint "eagle-import:0201")
      (libsource (lib "eagle-import") (part "C0201"))
    )
    (comp (ref "C180")
      (value "0.01uF")
      (footprint "eagle-import:0201")
      (libsource (lib "eagle-import") (part "C0201"))
    )
    (comp (ref "C181")
      (value "0.01uF")
      (footprint "eagle-import:0201")
      (libsource (lib "eagle-import") (part "C0201"))
    )
    (comp (ref "C182")
      (value "0.01uF")
      (footprint "eagle-import:0201")
      (libsource (lib "eagle-import") (part "C0201"))
    )
    (comp (ref "C183")
      (value "0.01uF")
      (footprint "eagle-import:0201")
      (libsource (lib "eagle-import") (part "C0201"))
    )
    (comp (ref "C184")
      (value "0.01uF")
      (footprint "eagle-import:0201")
      (libsource (lib "eagle-import") (part "C0201"))
    )
    (comp (ref "C185")
      (value "0.01uF")
      (footprint "eagle-import:0201")
      (libsource (lib "eagle-import") (part "C0201"))
    )
    (comp (ref "C186")
      (value "0.01uF")
      (footprint "eagle-import:0201")
      (libsource (lib "eagle-import") (part "C0201"))
    )
    (comp (ref "C187")
      (value "0.01uF")
      (footprint "eagle-import:0201")
      (libsource (lib "eagle-import") (part "C0201"))
    )
    (comp (ref "C188")
      (value "0.01uF")
      (footprint "eagle-import:0201")
      (libsource (lib "eagle-import") (part "C0201"))
    )
    (comp (ref "C189")
      (value "0.01uF")
      (footprint "eagle-import:0201")
      (libsource (lib "eagle-import") (part "C0201"))
    )
    (comp (ref "C190")
      (value "0.01uF")
      (footprint "eagle-import:0201")
      (libsource (lib "eagle-import") (part "C0201"))
    )
    (comp (ref "C191")
      (value "0.01uF")
      (footprint "eagle-import:0201")
      (libsource (lib "eagle-import") (part "C0201"))
    )
    (comp (ref "C192")
      (value "0.01uF")
      (footprint "eagle-import:0201")
      (libsource (lib "eagle-import") (part "C0201"))
    )
    (comp (ref "C193")
      (value "0.01uF")
      (footprint "eagle-import:0201")
      (libsource (lib "eagle-import") (part "C0201"))
    )
    (comp (ref "C194")
      (value "0.01uF")
      (footprint "eagle-import:0201")
      (libsource (lib "eagle-import") (part "C0201"))
    )
    (comp (ref "C195")
      (value "0.01uF")
      (footprint "eagle-import:0201")
      (libsource (lib "eagle-import") (part "C0201"))
    )
    (comp (ref "C196")
      (value "0.01uF")
      (footprint "eagle-import:0201")
      (libsource (lib "eagle-import") (part "C0201"))
    )
    (comp (ref "C197")
      (value "10uF")
      (footprint "eagle-import:0603")
      (libsource (lib "eagle-import") (part "C0603"))
    )
    (comp (ref "C198")
      (value "10uF")
      (footprint "eagle-import:0603")
      (libsource (lib "eagle-import") (part "C0603"))
    )
    (comp (ref "C199")
      (value "10uF")
      (footprint "eagle-import:0603")
      (libsource (lib "eagle-import") (part "C0603"))
    )
    (comp (ref "C200")
      (value "10uF")
      (footprint "eagle-import:0603")
      (libsource (lib "eagle-import") (part "C0603"))
    )
    (comp (ref "C201")
      (value "10uF")
      (footprint "eagle-import:0603")
      (libsource (lib "eagle-import") (part "C0603"))
    )
    (comp (ref "C202")
      (value "10uF")
      (footprint "eagle-import:0603")
      (libsource (lib "eagle-import") (part "C0603"))
    )
    (comp (ref "C203")
      (value "10uF")
      (footprint "eagle-import:0603")
      (libsource (lib "eagle-import") (part "C0603"))
    )
    (comp (ref "C204")
      (value "10uF")
      (footprint "eagle-import:0603")
      (libsource (lib "eagle-import") (part "C0603"))
    )
    (comp (ref "C205")
      (value "0.01uF")
      (footprint "eagle-import:0201")
      (libsource (lib "eagle-import") (part "C0201"))
    )
    (comp (ref "C206")
      (value "0.01uF")
      (footprint "eagle-import:0201")
      (libsource (lib "eagle-import") (part "C0201"))
    )
    (comp (ref "C207")
      (value "0.01uF")
      (footprint "eagle-import:0201")
      (libsource (lib "eagle-import") (part "C0201"))
    )
    (comp (ref "C208")
      (value "0.01uF")
      (footprint "eagle-import:0201")
      (libsource (lib "eagle-import") (part "C0201"))
    )
    (comp (ref "C209")
      (value "0.01uF")
      (footprint "eagle-import:0201")
      (libsource (lib "eagle-import") (part "C0201"))
    )
    (comp (ref "C210")
      (value "0.01uF")
      (footprint "eagle-import:0201")
      (libsource (lib "eagle-import") (part "C0201"))
    )
    (comp (ref "C211")
      (value "0.01uF")
      (footprint "eagle-import:0201")
      (libsource (lib "eagle-import") (part "C0201"))
    )
    (comp (ref "C212")
      (value "0.01uF")
      (footprint "eagle-import:0201")
      (libsource (lib "eagle-import") (part "C0201"))
    )
    (comp (ref "C213")
      (value "0.01uF")
      (footprint "eagle-import:0201")
      (libsource (lib "eagle-import") (part "C0201"))
    )
    (comp (ref "C214")
      (value "0.01uF")
      (footprint "eagle-import:0201")
      (libsource (lib "eagle-import") (part "C0201"))
    )
    (comp (ref "C215")
      (value "0.01uF")
      (footprint "eagle-import:0201")
      (libsource (lib "eagle-import") (part "C0201"))
    )
    (comp (ref "C216")
      (value "0.01uF")
      (footprint "eagle-import:0201")
      (libsource (lib "eagle-import") (part "C0201"))
    )
    (comp (ref "C217")
      (value "0.01uF")
      (footprint "eagle-import:0201")
      (libsource (lib "eagle-import") (part "C0201"))
    )
    (comp (ref "C218")
      (value "0.01uF")
      (footprint "eagle-import:0201")
      (libsource (lib "eagle-import") (part "C0201"))
    )
    (comp (ref "C219")
      (value "0.01uF")
      (footprint "eagle-import:0201")
      (libsource (lib "eagle-import") (part "C0201"))
    )
    (comp (ref "C238")
      (value "0.01uF")
      (footprint "eagle-import:0201")
      (libsource (lib "eagle-import") (part "C0201"))
    )
    (comp (ref "C239")
      (value "0.01uF")
      (footprint "eagle-import:0201")
      (libsource (lib "eagle-import") (part "C0201"))
    )
    (comp (ref "C240")
      (value "0.01uF")
      (footprint "eagle-import:0201")
      (libsource (lib "eagle-import") (part "C0201"))
    )
    (comp (ref "C241")
      (value "0.01uF")
      (footprint "eagle-import:0201")
      (libsource (lib "eagle-import") (part "C0201"))
    )
    (comp (ref "C242")
      (value "0.01uF")
      (footprint "eagle-import:0201")
      (libsource (lib "eagle-import") (part "C0201"))
    )
    (comp (ref "C243")
      (value "0.01uF")
      (footprint "eagle-import:0201")
      (libsource (lib "eagle-import") (part "C0201"))
    )
    (comp (ref "C244")
      (value "0.01uF")
      (footprint "eagle-import:0201")
      (libsource (lib "eagle-import") (part "C0201"))
    )
    (comp (ref "C245")
      (value "0.01uF")
      (footprint "eagle-import:0201")
      (libsource (lib "eagle-import") (part "C0201"))
    )
    (comp (ref "C246")
      (value "0.01uF")
      (footprint "eagle-import:0201")
      (libsource (lib "eagle-import") (part "C0201"))
    )
    (comp (ref "C247")
      (value "0.01uF")
      (footprint "eagle-import:0201")
      (libsource (lib "eagle-import") (part "C0201"))
    )
    (comp (ref "C248")
      (value "0.01uF")
      (footprint "eagle-import:0201")
      (libsource (lib "eagle-import") (part "C0201"))
    )
    (comp (ref "C249")
      (value "0.01uF")
      (footprint "eagle-import:0201")
      (libsource (lib "eagle-import") (part "C0201"))
    )
    (comp (ref "C250")
      (value "0.01uF")
      (footprint "eagle-import:0201")
      (libsource (lib "eagle-import") (part "C0201"))
    )
    (comp (ref "C251")
      (value "0.01uF")
      (footprint "eagle-import:0201")
      (libsource (lib "eagle-import") (part "C0201"))
    )
    (comp (ref "FB11")
      (value "120R 1A")
      (footprint "eagle-import:0402")
      (libsource (lib "eagle-import") (part "FB0402"))
    )
    (comp (ref "FB12")
      (value "120R 1A")
      (footprint "eagle-import:0402")
      (libsource (lib "eagle-import") (part "FB0402"))
    )
    (comp (ref "R126")
      (value "10K")
      (footprint "eagle-import:0201")
      (libsource (lib "eagle-import") (part "R0201"))
    )
    (comp (ref "R127")
      (value "10K")
      (footprint "eagle-import:0201")
      (libsource (lib "eagle-import") (part "R0201"))
    )
    (comp (ref "Y3")
      (value "24.000MHz")
      (footprint "eagle-import:CRYSTAL-3225")
      (libsource (lib "eagle-import") (part "Y4CRYSTAL-3225"))
    )
    (comp (ref "ACLK")
      (value "DNP")
      (footprint "eagle-import:TP0500")
      (libsource (lib "eagle-import") (part "TP05"))
    )
    (comp (ref "ACS0")
      (value "DNP")
      (footprint "eagle-import:TP0500")
      (libsource (lib "eagle-import") (part "TP05"))
    )
    (comp (ref "ARX")
      (value "DNP")
      (footprint "eagle-import:TP0500")
      (libsource (lib "eagle-import") (part "TP05"))
    )
    (comp (ref "ATX")
      (value "DNP")
      (footprint "eagle-import:TP0500")
      (libsource (lib "eagle-import") (part "TP05"))
    )
    (comp (ref "BT4")
      (value "DNP")
      (footprint "eagle-import:TP0500")
      (libsource (lib "eagle-import") (part "TP05"))
    )
    (comp (ref "BTEN")
      (value "DNP")
      (footprint "eagle-import:TP0500")
      (libsource (lib "eagle-import") (part "TP05"))
    )
    (comp (ref "C115")
      (value "0.1uF")
      (footprint "eagle-import:0402")
      (libsource (lib "eagle-import") (part "C0402"))
    )
    (comp (ref "C116")
      (value "10uF")
      (footprint "eagle-import:0603")
      (libsource (lib "eagle-import") (part "C0603"))
    )
    (comp (ref "C117")
      (value "10uF")
      (footprint "eagle-import:0603")
      (libsource (lib "eagle-import") (part "C0603"))
    )
    (comp (ref "C142")
      (value "0.1uF")
      (footprint "eagle-import:0402")
      (libsource (lib "eagle-import") (part "C0402"))
    )
    (comp (ref "C143")
      (value "10pF")
      (footprint "eagle-import:0402")
      (libsource (lib "eagle-import") (part "C0402"))
    )
    (comp (ref "C174")
      (value "0.1uF")
      (footprint "eagle-import:0402")
      (libsource (lib "eagle-import") (part "C0402"))
    )
    (comp (ref "C175")
      (value "10pF")
      (footprint "eagle-import:0402")
      (libsource (lib "eagle-import") (part "C0402"))
    )
    (comp (ref "CONN1")
      (value "U.FL")
      (footprint "eagle-import:U.FL")
      (libsource (lib "eagle-import") (part "U.FL"))
    )
    (comp (ref "FB5")
      (value "120R 1A")
      (footprint "eagle-import:0402")
      (libsource (lib "eagle-import") (part "FB0402"))
    )
    (comp (ref "FB6")
      (value "120R 1A")
      (footprint "eagle-import:0402")
      (libsource (lib "eagle-import") (part "FB0402"))
    )
    (comp (ref "Q5")
      (value "32.768kHz")
      (footprint "eagle-import:ASF")
      (fields (field (name "MF") "Abracon Corporation") (field (name "MPN") "ASFL1-125.000MHZ-EC-T"))
      (libsource (lib "eagle-import") (part "ASFL1"))
    )
    (comp (ref "RP5")
      (value "10K0")
      (footprint "eagle-import:741X16")
      (libsource (lib "eagle-import") (part "RP741X163"))
    )
    (comp (ref "RP6")
      (value "33R0")
      (footprint "eagle-import:741X16")
      (libsource (lib "eagle-import") (part "RP741X163"))
    )
    (comp (ref "U28")
      (value "WL1831MOD")
      (footprint "eagle-import:WL1801MOD")
      (libsource (lib "eagle-import") (part "WL1801MOD"))
    )
    (comp (ref "WLDB")
      (value "DNP")
      (footprint "eagle-import:TP0500")
      (libsource (lib "eagle-import") (part "TP05"))
    )
    (comp (ref "WLEN")
      (value "DNP")
      (footprint "eagle-import:TP0500")
      (libsource (lib "eagle-import") (part "TP05"))
    )
    (comp (ref "WLRX")
      (value "DNP")
      (footprint "eagle-import:TP0500")
      (libsource (lib "eagle-import") (part "TP05"))
    )
    (comp (ref "WLTX")
      (value "DNP")
      (footprint "eagle-import:TP0500")
      (libsource (lib "eagle-import") (part "TP05"))
    )
    (comp (ref "C106")
      (value "0.1uF")
      (footprint "eagle-import:0201")
      (libsource (lib "eagle-import") (part "C0201"))
    )
    (comp (ref "C107")
      (value "100uF")
      (footprint "eagle-import:PANASONIC_D")
      (libsource (lib "eagle-import") (part "CPANASONIC_D"))
    )
    (comp (ref "C108")
      (value "10uF / 25V")
      (footprint "eagle-import:1206")
      (libsource (lib "eagle-import") (part "C1206"))
    )
    (comp (ref "C109")
      (value "0.22uF")
      (footprint "eagle-import:0603")
      (libsource (lib "eagle-import") (part "C0603"))
    )
    (comp (ref "C110")
      (value "22pF")
      (footprint "eagle-import:0402")
      (libsource (lib "eagle-import") (part "C0402"))
    )
    (comp (ref "C111")
      (value "22pF")
      (footprint "eagle-import:0402")
      (libsource (lib "eagle-import") (part "C0402"))
    )
    (comp (ref "R64")
      (value "5K6 1P")
      (footprint "eagle-import:0402")
      (libsource (lib "eagle-import") (part "R0402"))
    )
    (comp (ref "R65")
      (value "5K6 1P")
      (footprint "eagle-import:0402")
      (libsource (lib "eagle-import") (part "R0402"))
    )
    (comp (ref "R66")
      (value "2K32 1P")
      (footprint "eagle-import:0402")
      (libsource (lib "eagle-import") (part "R0402"))
    )
    (comp (ref "R67")
      (value "2K32 1P")
      (footprint "eagle-import:0402")
      (libsource (lib "eagle-import") (part "R0402"))
    )
    (comp (ref "R68")
      (value "470R")
      (footprint "eagle-import:0402")
      (libsource (lib "eagle-import") (part "R0402"))
    )
    (comp (ref "R69")
      (value "470R")
      (footprint "eagle-import:0402")
      (libsource (lib "eagle-import") (part "R0402"))
    )
    (comp (ref "R70")
      (value "1K5")
      (footprint "eagle-import:0402")
      (libsource (lib "eagle-import") (part "R0402"))
    )
    (comp (ref "R71")
      (value "5K6 1P")
      (footprint "eagle-import:0402")
      (libsource (lib "eagle-import") (part "R0402"))
    )
    (comp (ref "R72")
      (value "5K6 1P")
      (footprint "eagle-import:0402")
      (libsource (lib "eagle-import") (part "R0402"))
    )
    (comp (ref "R73")
      (value "2K32 1P")
      (footprint "eagle-import:0402")
      (libsource (lib "eagle-import") (part "R0402"))
    )
    (comp (ref "R74")
      (value "2K32 1P")
      (footprint "eagle-import:0402")
      (libsource (lib "eagle-import") (part "R0402"))
    )
    (comp (ref "R75")
      (value "470R")
      (footprint "eagle-import:0402")
      (libsource (lib "eagle-import") (part "R0402"))
    )
    (comp (ref "R76")
      (value "470R")
      (footprint "eagle-import:0402")
      (libsource (lib "eagle-import") (part "R0402"))
    )
    (comp (ref "R77")
      (value "1K5")
      (footprint "eagle-import:0402")
      (libsource (lib "eagle-import") (part "R0402"))
    )
    (comp (ref "U23")
      (value "TB6612FNG")
      (footprint "eagle-import:SSOP24")
      (libsource (lib "eagle-import") (part "TB6612FNG"))
    )
    (comp (ref "U24")
      (value "0.100 MALE PIN")
      (footprint "eagle-import:2X03_SHROUD")
      (libsource (lib "eagle-import") (part "2X03SHROUD"))
    )
    (comp (ref "U25")
      (value "APTB1615")
      (footprint "eagle-import:APTB1615")
      (libsource (lib "eagle-import") (part "APTB1615"))
    )
    (comp (ref "U26")
      (value "APTB1615")
      (footprint "eagle-import:APTB1615")
      (libsource (lib "eagle-import") (part "APTB1615"))
    )
  )
  (nets
    (net (code "1") (name "3V_DISPLAY_EN$43") (class "Default")
      (node (ref "U$67") (pin "38") (pinfunction "1A6_38") (pintype "bidirectional"))
      (node (ref "U$70") (pin "31") (pinfunction "DISP_31") (pintype "output"))
    )
    (net (code "2") (name "3V_L_BIAS$43") (class "Default")
      (node (ref "U$67") (pin "43") (pinfunction "1A3_43") (pintype "bidirectional"))
      (node (ref "U$70") (pin "34") (pinfunction "DE_34") (pintype "output"))
    )
    (net (code "3") (name "3V_L_FCLK$43") (class "Default")
      (node (ref "U$67") (pin "41") (pinfunction "1A4_41") (pintype "bidirectional"))
      (node (ref "U$70") (pin "33") (pinfunction "VSYNC_33") (pintype "output"))
    )
    (net (code "4") (name "3V_L_LCLK$43") (class "Default")
      (node (ref "U$67") (pin "40") (pinfunction "1A5_40") (pintype "bidirectional"))
      (node (ref "U$70") (pin "32") (pinfunction "HSYNC_32") (pintype "output"))
    )
    (net (code "5") (name "3V_L_PCLK$43") (class "Default")
      (node (ref "U$67") (pin "37") (pinfunction "1A7_37") (pintype "bidirectional"))
      (node (ref "U$70") (pin "30") (pinfunction "PCLK_30") (pintype "output"))
    )
    (net (code "6") (name "3V_MISO$43") (class "Default")
      (node (ref "U$66") (pin "16") (pinfunction "DOUT_16") (pintype "bidirectional"))
      (node (ref "U$69") (pin "41") (pinfunction "1A4_41") (pintype "bidirectional"))
    )
    (net (code "7") (name "3V_MOSI$43") (class "Default")
      (node (ref "U$66") (pin "2") (pinfunction "DIN_2") (pintype "bidirectional"))
      (node (ref "U$67") (pin "44") (pinfunction "1A2_44") (pintype "bidirectional"))
    )
    (net (code "8") (name "3V_NPENIRQ$43") (class "Default")
      (node (ref "R95") (pin "2") (pinfunction "2_2") (pintype "passive"))
      (node (ref "U$66") (pin "15") (pinfunction "NPENIRQ_15") (pintype "bidirectional"))
      (node (ref "U$69") (pin "38") (pinfunction "1A6_38") (pintype "bidirectional"))
    )
    (net (code "9") (name "3V_SPI_CLK$43") (class "Default")
      (node (ref "U$66") (pin "4") (pinfunction "DCLK_4") (pintype "bidirectional"))
      (node (ref "U$67") (pin "47") (pinfunction "1A0_47") (pintype "bidirectional"))
    )
    (net (code "10") (name "3V_TS_BUSY$43") (class "Default")
      (node (ref "U$66") (pin "1") (pinfunction "BUSY_1") (pintype "bidirectional"))
    )
    (net (code "11") (name "4.VCC_BATT") (class "Default")
      (node (ref "F3") (pin "2") (pinfunction "2_2") (pintype "passive"))
      (node (ref "Q6") (pin "3") (pinfunction "S_3") (pintype "passive"))
      (node (ref "R19") (pin "2") (pinfunction "2_2") (pintype "passive"))
      (node (ref "R88") (pin "1") (pinfunction "1_1") (pintype "passive"))
      (node (ref "VCC") (pin "TP") (pinfunction "TP_TP") (pintype "bidirectional"))
    )
    (net (code "12") (name "5V_1$2") (class "Default")
      (node (ref "F1") (pin "1") (pinfunction "1_1") (pintype "passive"))
      (node (ref "J2") (pin "B2") (pinfunction "B2_B2") (pintype "bidirectional"))
    )
    (net (code "13") (name "5V_1$28") (class "Default")
      (node (ref "F4") (pin "1") (pinfunction "1_1") (pintype "passive"))
      (node (ref "J9") (pin "B2") (pinfunction "B2_B2") (pintype "bidirectional"))
    )
    (net (code "14") (name "5V_2$2") (class "Default")
      (node (ref "F2") (pin "1") (pinfunction "1_1") (pintype "passive"))
      (node (ref "J2") (pin "A2") (pinfunction "A2_A2") (pintype "bidirectional"))
    )
    (net (code "15") (name "5V_2$28") (class "Default")
      (node (ref "F5") (pin "1") (pinfunction "1_1") (pintype "passive"))
      (node (ref "J9") (pin "A2") (pinfunction "A2_A2") (pintype "bidirectional"))
    )
    (net (code "16") (name "5V_SCL$44") (class "Default")
      (node (ref "D29") (pin "P2") (pinfunction "P2_P2") (pintype "passive"))
      (node (ref "J15") (pin "17") (pinfunction "15_17") (pintype "passive"))
      (node (ref "R112") (pin "2") (pinfunction "2_2") (pintype "passive"))
      (node (ref "U33") (pin "6") (pinfunction "SCL2_6") (pintype "bidirectional"))
    )
    (net (code "17") (name "5V_SDA$44") (class "Default")
      (node (ref "D30") (pin "P2") (pinfunction "P2_P2") (pintype "passive"))
      (node (ref "J15") (pin "18") (pinfunction "16_18") (pintype "passive"))
      (node (ref "R109") (pin "2") (pinfunction "2_2") (pintype "passive"))
      (node (ref "U33") (pin "5") (pinfunction "SDA2_5") (pintype "bidirectional"))
    )
    (net (code "18") (name "9.VCC_BATT_NOFUSE") (class "Default")
      (node (ref "C61") (pin "1") (pinfunction "1_1") (pintype "passive"))
      (node (ref "C62") (pin "1") (pinfunction "1_1") (pintype "passive"))
      (node (ref "C63") (pin "1") (pinfunction "1_1") (pintype "passive"))
      (node (ref "IC2") (pin "2") (pinfunction "VIN_2") (pintype "power_in"))
      (node (ref "IC2") (pin "3") (pinfunction "VIN_3") (pintype "power_in"))
      (node (ref "IC2") (pin "4") (pinfunction "EN_4") (pintype "input"))
      (node (ref "IC2") (pin "8") (pinfunction "VIN_8") (pintype "power_in"))
      (node (ref "Q6") (pin "2") (pinfunction "D_2") (pintype "passive"))
      (node (ref "Q6") (pin "4") (pinfunction "D_4") (pintype "passive"))
      (node (ref "R52") (pin "1") (pinfunction "1_1") (pintype "passive"))
      (node (ref "TP1") (pin "1") (pinfunction "TP_1") (pintype "bidirectional"))
    )
    (net (code "19") (name "9.VCC_BATT_OUT") (class "Default")
      (node (ref "C107") (pin "+") (pinfunction "1_+") (pintype "passive"))
      (node (ref "C108") (pin "1") (pinfunction "1_1") (pintype "passive"))
      (node (ref "C109") (pin "1") (pinfunction "1_1") (pintype "passive"))
      (node (ref "C11") (pin "+") (pinfunction "1_+") (pintype "passive"))
      (node (ref "C12") (pin "1") (pinfunction "1_1") (pintype "passive"))
      (node (ref "C13") (pin "1") (pinfunction "1_1") (pintype "passive"))
      (node (ref "Q1") (pin "2") (pinfunction "D_2") (pintype "passive"))
      (node (ref "Q1") (pin "4") (pinfunction "D_4") (pintype "passive"))
      (node (ref "U23") (pin "13") (pinfunction "VM2_13") (pintype "bidirectional"))
      (node (ref "U23") (pin "14") (pinfunction "VM3_14") (pintype "bidirectional"))
      (node (ref "U23") (pin "24") (pinfunction "VM1_24") (pintype "bidirectional"))
      (node (ref "U4") (pin "13") (pinfunction "VM2_13") (pintype "bidirectional"))
      (node (ref "U4") (pin "14") (pinfunction "VM3_14") (pintype "bidirectional"))
      (node (ref "U4") (pin "24") (pinfunction "VM1_24") (pintype "bidirectional"))
    )
    (net (code "20") (name "15.HSO_L") (class "Default")
      (node (ref "C67") (pin "2") (pinfunction "2_2") (pintype "passive"))
      (node (ref "U15") (pin "18") (pinfunction "HPLOUT_18") (pintype "bidirectional"))
    )
    (net (code "21") (name "17.VCC_1.8") (class "Default")
      (node (ref "C112") (pin "1") (pinfunction "1_1") (pintype "passive"))
      (node (ref "C117") (pin "1") (pinfunction "1_1") (pintype "passive"))
      (node (ref "C139") (pin "1") (pinfunction "1_1") (pintype "passive"))
      (node (ref "C149") (pin "1") (pinfunction "1_1") (pintype "passive"))
      (node (ref "C150") (pin "1") (pinfunction "1_1") (pintype "passive"))
      (node (ref "C152") (pin "1") (pinfunction "1_1") (pintype "passive"))
      (node (ref "C16") (pin "1") (pinfunction "1_1") (pintype "passive"))
      (node (ref "C161") (pin "1") (pinfunction "1_1") (pintype "passive"))
      (node (ref "C18") (pin "1") (pinfunction "1_1") (pintype "passive"))
      (node (ref "C3") (pin "1") (pinfunction "1_1") (pintype "passive"))
      (node (ref "C40") (pin "1") (pinfunction "1_1") (pintype "passive"))
      (node (ref "C41") (pin "1") (pinfunction "1_1") (pintype "passive"))
      (node (ref "C42") (pin "1") (pinfunction "1_1") (pintype "passive"))
      (node (ref "C51") (pin "1") (pinfunction "1_1") (pintype "passive"))
      (node (ref "C55") (pin "1") (pinfunction "1_1") (pintype "passive"))
      (node (ref "C58") (pin "1") (pinfunction "1_1") (pintype "passive"))
      (node (ref "C59") (pin "1") (pinfunction "1_1") (pintype "passive"))
      (node (ref "FB6") (pin "1") (pinfunction "1_1") (pintype "passive"))
      (node (ref "IC1") (pin "5") (pinfunction "VSENSE_5") (pintype "input"))
      (node (ref "IC1") (pin "7") (pinfunction "VOUT_7") (pintype "power_in"))
      (node (ref "IC1") (pin "8") (pinfunction "VOUT_8") (pintype "power_in"))
      (node (ref "R107") (pin "1") (pinfunction "1_1") (pintype "passive"))
      (node (ref "R108") (pin "1") (pinfunction "1_1") (pintype "passive"))
      (node (ref "R26") (pin "2") (pinfunction "2_2") (pintype "passive"))
      (node (ref "R29") (pin "2") (pinfunction "2_2") (pintype "passive"))
      (node (ref "R3") (pin "2") (pinfunction "2_2") (pintype "passive"))
      (node (ref "R31") (pin "1") (pinfunction "1_1") (pintype "passive"))
      (node (ref "R99") (pin "2") (pinfunction "2_2") (pintype "passive"))
      (node (ref "RP5") (pin "10") (pinfunction "10_10") (pintype "passive"))
      (node (ref "RP5") (pin "11") (pinfunction "11_11") (pintype "passive"))
      (node (ref "RP5") (pin "12") (pinfunction "12_12") (pintype "passive"))
      (node (ref "RP5") (pin "13") (pinfunction "13_13") (pintype "passive"))
      (node (ref "RP5") (pin "14") (pinfunction "14_14") (pintype "passive"))
      (node (ref "RP5") (pin "15") (pinfunction "15_15") (pintype "passive"))
      (node (ref "RP5") (pin "16") (pinfunction "16_16") (pintype "passive"))
      (node (ref "RP5") (pin "9") (pinfunction "9_9") (pintype "passive"))
      (node (ref "U$67") (pin "18") (pinfunction "VCCB_18") (pintype "power_in"))
      (node (ref "U$67") (pin "7") (pinfunction "VCCB_7") (pintype "power_in"))
      (node (ref "U$68") (pin "18") (pinfunction "VCCB_18") (pintype "power_in"))
      (node (ref "U$68") (pin "7") (pinfunction "VCCB_7") (pintype "power_in"))
      (node (ref "U$69") (pin "18") (pinfunction "VCCB_18") (pintype "power_in"))
      (node (ref "U$69") (pin "7") (pinfunction "VCCB_7") (pintype "power_in"))
      (node (ref "U1") (pin "1") (pinfunction "VCCA_1") (pintype "power_in"))
      (node (ref "U1") (pin "5") (pinfunction "OE_5") (pintype "input"))
      (node (ref "U10") (pin "1") (pinfunction "VCCA_1") (pintype "power_in"))
      (node (ref "U10") (pin "5") (pinfunction "OE_5") (pintype "input"))
      (node (ref "U15") (pin "36") (pinfunction "DVDD_36") (pintype "bidirectional"))
      (node (ref "U15") (pin "44") (pinfunction "IOVDD_44") (pintype "bidirectional"))
      (node (ref "U16") (pin "1") (pinfunction "2DIR_1") (pintype "input"))
      (node (ref "U16") (pin "7") (pinfunction "VCCA_7") (pintype "power_in"))
      (node (ref "U27") (pin "1") (pinfunction "VCCA_1") (pintype "power_in"))
      (node (ref "U27") (pin "5") (pinfunction "OE_5") (pintype "input"))
      (node (ref "U3") (pin "8") (pinfunction "VCC_8") (pintype "power_in"))
      (node (ref "U32") (pin "1") (pinfunction "VCCA_1") (pintype "power_in"))
      (node (ref "U32") (pin "5") (pinfunction "OE_5") (pintype "input"))
      (node (ref "U33") (pin "2") (pinfunction "VREF1_2") (pintype "input"))
      (node (ref "U8") (pin "10") (pinfunction "OE_10") (pintype "input"))
      (node (ref "U8") (pin "2") (pinfunction "VCCA_2") (pintype "power_in"))
      (node (ref "X2") (pin "1") (pinfunction "OE_1") (pintype "input"))
      (node (ref "X2") (pin "4") (pinfunction "VCC_4") (pintype "power_in"))
    )
    (net (code "22") (name "18.VCC_3.3") (class "Default")
      (node (ref "C10") (pin "1") (pinfunction "1_1") (pintype "passive"))
      (node (ref "C101") (pin "1") (pinfunction "1_1") (pintype "passive"))
      (node (ref "C106") (pin "1") (pinfunction "1_1") (pintype "passive"))
      (node (ref "C116") (pin "1") (pinfunction "1_1") (pintype "passive"))
      (node (ref "C118") (pin "1") (pinfunction "1_1") (pintype "passive"))
      (node (ref "C124") (pin "1") (pinfunction "1_1") (pintype "passive"))
      (node (ref "C125") (pin "1") (pinfunction "1_1") (pintype "passive"))
      (node (ref "C126") (pin "1") (pinfunction "1_1") (pintype "passive"))
      (node (ref "C127") (pin "1") (pinfunction "1_1") (pintype "passive"))
      (node (ref "C128") (pin "1") (pinfunction "1_1") (pintype "passive"))
      (node (ref "C129") (pin "1") (pinfunction "1_1") (pintype "passive"))
      (node (ref "C130") (pin "1") (pinfunction "1_1") (pintype "passive"))
      (node (ref "C137") (pin "1") (pinfunction "1_1") (pintype "passive"))
      (node (ref "C138") (pin "1") (pinfunction "1_1") (pintype "passive"))
      (node (ref "C140") (pin "1") (pinfunction "1_1") (pintype "passive"))
      (node (ref "C141") (pin "1") (pinfunction "1_1") (pintype "passive"))
      (node (ref "C144") (pin "1") (pinfunction "1_1") (pintype "passive"))
      (node (ref "C146") (pin "1") (pinfunction "1_1") (pintype "passive"))
      (node (ref "C147") (pin "1") (pinfunction "1_1") (pintype "passive"))
      (node (ref "C148") (pin "1") (pinfunction "1_1") (pintype "passive"))
      (node (ref "C151") (pin "1") (pinfunction "1_1") (pintype "passive"))
      (node (ref "C155") (pin "1") (pinfunction "1_1") (pintype "passive"))
      (node (ref "C156") (pin "1") (pinfunction "1_1") (pintype "passive"))
      (node (ref "C157") (pin "1") (pinfunction "1_1") (pintype "passive"))
      (node (ref "C158") (pin "1") (pinfunction "1_1") (pintype "passive"))
      (node (ref "C17") (pin "1") (pinfunction "1_1") (pintype "passive"))
      (node (ref "C19") (pin "1") (pinfunction "1_1") (pintype "passive"))
      (node (ref "C20") (pin "1") (pinfunction "1_1") (pintype "passive"))
      (node (ref "C21") (pin "1") (pinfunction "1_1") (pintype "passive"))
      (node (ref "C24") (pin "1") (pinfunction "1_1") (pintype "passive"))
      (node (ref "C25") (pin "1") (pinfunction "1_1") (pintype "passive"))
      (node (ref "C33") (pin "1") (pinfunction "1_1") (pintype "passive"))
      (node (ref "C34") (pin "1") (pinfunction "1_1") (pintype "passive"))
      (node (ref "C35") (pin "1") (pinfunction "1_1") (pintype "passive"))
      (node (ref "C36") (pin "1") (pinfunction "1_1") (pintype "passive"))
      (node (ref "C37") (pin "1") (pinfunction "1_1") (pintype "passive"))
      (node (ref "C38") (pin "1") (pinfunction "1_1") (pintype "passive"))
      (node (ref "C39") (pin "1") (pinfunction "1_1") (pintype "passive"))
      (node (ref "C43") (pin "1") (pinfunction "1_1") (pintype "passive"))
      (node (ref "C44") (pin "1") (pinfunction "1_1") (pintype "passive"))
      (node (ref "C49") (pin "1") (pinfunction "1_1") (pintype "passive"))
      (node (ref "C50") (pin "1") (pinfunction "1_1") (pintype "passive"))
      (node (ref "C56") (pin "1") (pinfunction "1_1") (pintype "passive"))
      (node (ref "C57") (pin "1") (pinfunction "1_1") (pintype "passive"))
      (node (ref "C6") (pin "1") (pinfunction "1_1") (pintype "passive"))
      (node (ref "C60") (pin "1") (pinfunction "1_1") (pintype "passive"))
      (node (ref "C64") (pin "1") (pinfunction "1_1") (pintype "passive"))
      (node (ref "C69") (pin "1") (pinfunction "1_1") (pintype "passive"))
      (node (ref "C75") (pin "1") (pinfunction "1_1") (pintype "passive"))
      (node (ref "C76") (pin "1") (pinfunction "1_1") (pintype "passive"))
      (node (ref "C77") (pin "1") (pinfunction "1_1") (pintype "passive"))
      (node (ref "C78") (pin "1") (pinfunction "1_1") (pintype "passive"))
      (node (ref "C79") (pin "1") (pinfunction "1_1") (pintype "passive"))
      (node (ref "C80") (pin "1") (pinfunction "1_1") (pintype "passive"))
      (node (ref "C81") (pin "1") (pinfunction "1_1") (pintype "passive"))
      (node (ref "C82") (pin "1") (pinfunction "1_1") (pintype "passive"))
      (node (ref "C91") (pin "1") (pinfunction "1_1") (pintype "passive"))
      (node (ref "C92") (pin "1") (pinfunction "1_1") (pintype "passive"))
      (node (ref "C93") (pin "1") (pinfunction "1_1") (pintype "passive"))
      (node (ref "C96") (pin "1") (pinfunction "1_1") (pintype "passive"))
      (node (ref "FB5") (pin "1") (pinfunction "1_1") (pintype "passive"))
      (node (ref "FB7") (pin "1") (pinfunction "1_1") (pintype "passive"))
      (node (ref "FB8") (pin "1") (pinfunction "1_1") (pintype "passive"))
      (node (ref "FB9") (pin "2") (pinfunction "2_2") (pintype "passive"))
      (node (ref "IC1") (pin "11") (pinfunction "VS1_11") (pintype "input"))
      (node (ref "IC1") (pin "14") (pinfunction "VIN_14") (pintype "input"))
      (node (ref "IC3") (pin "100") (pinfunction "VDD_3_100") (pintype "power_in"))
      (node (ref "IC3") (pin "11") (pinfunction "VDD_5_11") (pintype "power_in"))
      (node (ref "IC3") (pin "19") (pinfunction "VSSA_OR_VDD_19") (pintype "power_in"))
      (node (ref "IC3") (pin "28") (pinfunction "VDD_4_28") (pintype "power_in"))
      (node (ref "IC3") (pin "50") (pinfunction "VDD_1_50") (pintype "power_in"))
      (node (ref "IC3") (pin "75") (pinfunction "VDD_2_75") (pintype "power_in"))
      (node (ref "IC4") (pin "1") (pinfunction "VDD_1") (pintype "power_in"))
      (node (ref "IC4") (pin "12") (pinfunction "VDD_12") (pintype "power_in"))
      (node (ref "IC4") (pin "33") (pinfunction "VDD_33") (pintype "power_in"))
      (node (ref "JTAG") (pin "1") (pinfunction "S_1") (pintype "passive"))
      (node (ref "L1") (pin "2") (pinfunction "2_2") (pintype "passive"))
      (node (ref "R1") (pin "2") (pinfunction "2_2") (pintype "passive"))
      (node (ref "R104") (pin "1") (pinfunction "1_1") (pintype "passive"))
      (node (ref "R105") (pin "2") (pinfunction "2_2") (pintype "passive"))
      (node (ref "R111") (pin "2") (pinfunction "2_2") (pintype "passive"))
      (node (ref "R136") (pin "2") (pinfunction "2_2") (pintype "passive"))
      (node (ref "R137") (pin "2") (pinfunction "2_2") (pintype "passive"))
      (node (ref "R138") (pin "2") (pinfunction "2_2") (pintype "passive"))
      (node (ref "R139") (pin "2") (pinfunction "2_2") (pintype "passive"))
      (node (ref "R23") (pin "1") (pinfunction "1_1") (pintype "passive"))
      (node (ref "R38") (pin "2") (pinfunction "2_2") (pintype "passive"))
      (node (ref "R39") (pin "2") (pinfunction "2_2") (pintype "passive"))
      (node (ref "R44") (pin "1") (pinfunction "1_1") (pintype "passive"))
      (node (ref "R45") (pin "2") (pinfunction "2_2") (pintype "passive"))
      (node (ref "R55") (pin "1") (pinfunction "1_1") (pintype "passive"))
      (node (ref "R58") (pin "1") (pinfunction "1_1") (pintype "passive"))
      (node (ref "R61") (pin "2") (pinfunction "2_2") (pintype "passive"))
      (node (ref "R63") (pin "2") (pinfunction "2_2") (pintype "passive"))
      (node (ref "R90") (pin "1") (pinfunction "1_1") (pintype "passive"))
      (node (ref "R92") (pin "1") (pinfunction "1_1") (pintype "passive"))
      (node (ref "R95") (pin "1") (pinfunction "1_1") (pintype "passive"))
      (node (ref "R96") (pin "1") (pinfunction "1_1") (pintype "passive"))
      (node (ref "R98") (pin "1") (pinfunction "1_1") (pintype "passive"))
      (node (ref "RP2") (pin "1") (pinfunction "1_1") (pintype "passive"))
      (node (ref "RP2") (pin "2") (pinfunction "2_2") (pintype "passive"))
      (node (ref "RP2") (pin "3") (pinfunction "3_3") (pintype "passive"))
      (node (ref "RP2") (pin "4") (pinfunction "4_4") (pintype "passive"))
      (node (ref "RP2") (pin "5") (pinfunction "5_5") (pintype "passive"))
      (node (ref "RP2") (pin "6") (pinfunction "6_6") (pintype "passive"))
      (node (ref "RP2") (pin "7") (pinfunction "7_7") (pintype "passive"))
      (node (ref "RP2") (pin "8") (pinfunction "8_8") (pintype "passive"))
      (node (ref "U$30") (pin "4") (pinfunction "VDD_4") (pintype "bidirectional"))
      (node (ref "U$66") (pin "14") (pinfunction "VCC_14") (pintype "bidirectional"))
      (node (ref "U$66") (pin "5") (pinfunction "VCC_5") (pintype "bidirectional"))
      (node (ref "U$67") (pin "31") (pinfunction "VCCA_31") (pintype "power_in"))
      (node (ref "U$67") (pin "42") (pinfunction "VCCA_42") (pintype "power_in"))
      (node (ref "U$68") (pin "31") (pinfunction "VCCA_31") (pintype "power_in"))
      (node (ref "U$68") (pin "42") (pinfunction "VCCA_42") (pintype "power_in"))
      (node (ref "U$69") (pin "1") (pinfunction "1DIR_1") (pintype "input"))
      (node (ref "U$69") (pin "31") (pinfunction "VCCA_31") (pintype "power_in"))
      (node (ref "U$69") (pin "42") (pinfunction "VCCA_42") (pintype "power_in"))
      (node (ref "U$70") (pin "4") (pinfunction "VDD_4") (pintype "power_in"))
      (node (ref "U10") (pin "8") (pinfunction "VCCB_8") (pintype "power_in"))
      (node (ref "U11") (pin "1") (pinfunction "VCCA_1") (pintype "power_in"))
      (node (ref "U11") (pin "5") (pinfunction "OE_5") (pintype "input"))
      (node (ref "U12") (pin "1") (pinfunction "VDD_IO_1") (pintype "power_in"))
      (node (ref "U12") (pin "15") (pinfunction "RSVD_VDD_15") (pintype "power_in"))
      (node (ref "U12") (pin "16") (pinfunction "VDD_16") (pintype "power_in"))
      (node (ref "U13") (pin "1") (pinfunction "VDD_IO_1") (pintype "power_in"))
      (node (ref "U13") (pin "14") (pinfunction "VDD_14") (pintype "power_in"))
      (node (ref "U15") (pin "16") (pinfunction "DRVDD.1_16") (pintype "bidirectional"))
      (node (ref "U15") (pin "17") (pinfunction "DRVDD.2_17") (pintype "bidirectional"))
      (node (ref "U15") (pin "24") (pinfunction "AVDD_ADC_24") (pintype "bidirectional"))
      (node (ref "U15") (pin "25") (pinfunction "AVDD_DAC_25") (pintype "bidirectional"))
      (node (ref "U16") (pin "6") (pinfunction "VCCB_6") (pintype "power_in"))
      (node (ref "U17") (pin "6") (pinfunction "VDD_6") (pintype "power_in"))
      (node (ref "U18") (pin "10") (pinfunction "VDD33_10") (pintype "power_in"))
      (node (ref "U18") (pin "15") (pinfunction "VDD33_15") (pintype "power_in"))
      (node (ref "U18") (pin "23") (pinfunction "VDD33_23") (pintype "power_in"))
      (node (ref "U18") (pin "29") (pinfunction "VDD33_29") (pintype "power_in"))
      (node (ref "U18") (pin "36") (pinfunction "VDD33_36") (pintype "power_in"))
      (node (ref "U18") (pin "5") (pinfunction "VDD33_5") (pintype "power_in"))
      (node (ref "U2") (pin "1") (pinfunction "VCCA_1") (pintype "power_in"))
      (node (ref "U2") (pin "5") (pinfunction "OE_5") (pintype "input"))
      (node (ref "U20") (pin "10") (pinfunction "OE_10") (pintype "input"))
      (node (ref "U20") (pin "2") (pinfunction "VCCA_2") (pintype "power_in"))
      (node (ref "U21") (pin "1") (pinfunction "VCCA_1") (pintype "power_in"))
      (node (ref "U21") (pin "5") (pinfunction "OE_5") (pintype "input"))
      (node (ref "U22") (pin "1") (pinfunction "VCCA_1") (pintype "power_in"))
      (node (ref "U22") (pin "5") (pinfunction "OE_5") (pintype "input"))
      (node (ref "U23") (pin "19") (pinfunction "STBY_19") (pintype "bidirectional"))
      (node (ref "U23") (pin "20") (pinfunction "VCC_20") (pintype "bidirectional"))
      (node (ref "U29") (pin "10") (pinfunction "OE_10") (pintype "input"))
      (node (ref "U29") (pin "2") (pinfunction "VCCA_2") (pintype "power_in"))
      (node (ref "U30") (pin "1") (pinfunction "VCCA_1") (pintype "power_in"))
      (node (ref "U30") (pin "5") (pinfunction "OE_5") (pintype "input"))
      (node (ref "U31") (pin "1") (pinfunction "A_1") (pintype "passive"))
      (node (ref "U31") (pin "2") (pinfunction "A'_2") (pintype "passive"))
      (node (ref "U32") (pin "8") (pinfunction "VCCB_8") (pintype "power_in"))
      (node (ref "U4") (pin "19") (pinfunction "STBY_19") (pintype "bidirectional"))
      (node (ref "U4") (pin "20") (pinfunction "VCC_20") (pintype "bidirectional"))
      (node (ref "U8") (pin "19") (pinfunction "VCCB_19") (pintype "power_in"))
      (node (ref "VCC1") (pin "1") (pinfunction "TP_1") (pintype "bidirectional"))
    )
    (net (code "23") (name "20.USBH1_N") (class "Default")
      (node (ref "L3") (pin "2") (pinfunction "2_2") (pintype "passive"))
      (node (ref "U18") (pin "1") (pinfunction "USBDM_DN1_1") (pintype "bidirectional"))
    )
    (net (code "24") (name "20.USBH1_NOC") (class "Default")
      (node (ref "U14") (pin "8") (pinfunction "NOC1_8") (pintype "output"))
      (node (ref "U18") (pin "13") (pinfunction "OCS_N1_13") (pintype "bidirectional"))
    )
    (net (code "25") (name "20.USBH1_P") (class "Default")
      (node (ref "L3") (pin "3") (pinfunction "3_3") (pintype "passive"))
      (node (ref "U18") (pin "2") (pinfunction "USBDP_DN1_2") (pintype "bidirectional"))
    )
    (net (code "26") (name "20.USBH1_PWREN") (class "Default")
      (node (ref "U14") (pin "3") (pinfunction "EN1_3") (pintype "bidirectional"))
      (node (ref "U18") (pin "12") (pinfunction "PRTPWR1_12") (pintype "bidirectional"))
    )
    (net (code "27") (name "20.USBH1_VBUS") (class "Default")
      (node (ref "D5") (pin "P2") (pinfunction "P2_P2") (pintype "passive"))
      (node (ref "FB4") (pin "2") (pinfunction "2_2") (pintype "passive"))
      (node (ref "U14") (pin "7") (pinfunction "OUT1_7") (pintype "power_in"))
      (node (ref "U19") (pin "1") (pinfunction "I1_1") (pintype "input"))
    )
    (net (code "28") (name "20.USBH2_N") (class "Default")
      (node (ref "L4") (pin "2") (pinfunction "2_2") (pintype "passive"))
      (node (ref "U18") (pin "3") (pinfunction "USBDM_DN2_3") (pintype "bidirectional"))
    )
    (net (code "29") (name "20.USBH2_NOC") (class "Default")
      (node (ref "U14") (pin "5") (pinfunction "NOC2_5") (pintype "output"))
      (node (ref "U18") (pin "17") (pinfunction "OCS_N2_17") (pintype "bidirectional"))
    )
    (net (code "30") (name "20.USBH2_P") (class "Default")
      (node (ref "L4") (pin "3") (pinfunction "3_3") (pintype "passive"))
      (node (ref "U18") (pin "4") (pinfunction "USBDP_DN2_4") (pintype "bidirectional"))
    )
    (net (code "31") (name "20.USBH2_PWREN") (class "Default")
      (node (ref "U14") (pin "4") (pinfunction "EN2_4") (pintype "bidirectional"))
      (node (ref "U18") (pin "16") (pinfunction "PRTPWR2_16") (pintype "bidirectional"))
    )
    (net (code "32") (name "20.USBH2_VBUS") (class "Default")
      (node (ref "D9") (pin "P2") (pinfunction "P2_P2") (pintype "passive"))
      (node (ref "FB3") (pin "2") (pinfunction "2_2") (pintype "passive"))
      (node (ref "U14") (pin "6") (pinfunction "OUT2_6") (pintype "power_in"))
      (node (ref "U19") (pin "3") (pinfunction "I2_3") (pintype "input"))
    )
    (net (code "33") (name "21.VCC_5.0") (class "Default")
      (node (ref "C1") (pin "1") (pinfunction "1_1") (pintype "passive"))
      (node (ref "C100") (pin "1") (pinfunction "1_1") (pintype "passive"))
      (node (ref "C102") (pin "1") (pinfunction "1_1") (pintype "passive"))
      (node (ref "C103") (pin "1") (pinfunction "1_1") (pintype "passive"))
      (node (ref "C113") (pin "1") (pinfunction "1_1") (pintype "passive"))
      (node (ref "C114") (pin "1") (pinfunction "1_1") (pintype "passive"))
      (node (ref "C119") (pin "1") (pinfunction "1_1") (pintype "passive"))
      (node (ref "C162") (pin "1") (pinfunction "1_1") (pintype "passive"))
      (node (ref "C2") (pin "1") (pinfunction "1_1") (pintype "passive"))
      (node (ref "C22") (pin "1") (pinfunction "1_1") (pintype "passive"))
      (node (ref "C221") (pin "1") (pinfunction "1_1") (pintype "passive"))
      (node (ref "C23") (pin "1") (pinfunction "1_1") (pintype "passive"))
      (node (ref "C28") (pin "1") (pinfunction "1_1") (pintype "passive"))
      (node (ref "C4") (pin "1") (pinfunction "1_1") (pintype "passive"))
      (node (ref "C5") (pin "1") (pinfunction "1_1") (pintype "passive"))
      (node (ref "C7") (pin "1") (pinfunction "1_1") (pintype "passive"))
      (node (ref "C8") (pin "1") (pinfunction "1_1") (pintype "passive"))
      (node (ref "C85") (pin "1") (pinfunction "1_1") (pintype "passive"))
      (node (ref "C89") (pin "1") (pinfunction "1_1") (pintype "passive"))
      (node (ref "C90") (pin "+") (pinfunction "1_+") (pintype "passive"))
      (node (ref "C94") (pin "1") (pinfunction "1_1") (pintype "passive"))
      (node (ref "C95") (pin "1") (pinfunction "1_1") (pintype "passive"))
      (node (ref "C97") (pin "1") (pinfunction "1_1") (pintype "passive"))
      (node (ref "C98") (pin "1") (pinfunction "1_1") (pintype "passive"))
      (node (ref "C99") (pin "1") (pinfunction "1_1") (pintype "passive"))
      (node (ref "F1") (pin "2") (pinfunction "2_2") (pintype "passive"))
      (node (ref "F2") (pin "2") (pinfunction "2_2") (pintype "passive"))
      (node (ref "F4") (pin "2") (pinfunction "2_2") (pintype "passive"))
      (node (ref "F5") (pin "2") (pinfunction "2_2") (pintype "passive"))
      (node (ref "FB10") (pin "1") (pinfunction "1_1") (pintype "passive"))
      (node (ref "FB2") (pin "1") (pinfunction "1_1") (pintype "passive"))
      (node (ref "J15") (pin "19") (pinfunction "18_19") (pintype "passive"))
      (node (ref "J5") (pin "B1") (pinfunction "2_B1") (pintype "passive"))
      (node (ref "J5") (pin "B2") (pinfunction "4_B2") (pintype "passive"))
      (node (ref "J5") (pin "B3") (pinfunction "6_B3") (pintype "passive"))
      (node (ref "J5") (pin "B4") (pinfunction "8_B4") (pintype "passive"))
      (node (ref "J5") (pin "B5") (pinfunction "10_B5") (pintype "passive"))
      (node (ref "J5") (pin "B6") (pinfunction "12_B6") (pintype "passive"))
      (node (ref "L2") (pin "2") (pinfunction "2_2") (pintype "passive"))
      (node (ref "R106") (pin "1") (pinfunction "1_1") (pintype "passive"))
      (node (ref "R109") (pin "1") (pinfunction "1_1") (pintype "passive"))
      (node (ref "R110") (pin "2") (pinfunction "2_2") (pintype "passive"))
      (node (ref "R112") (pin "1") (pinfunction "1_1") (pintype "passive"))
      (node (ref "R15") (pin "2") (pinfunction "2_2") (pintype "passive"))
      (node (ref "R18") (pin "2") (pinfunction "2_2") (pintype "passive"))
      (node (ref "R53") (pin "1") (pinfunction "1_1") (pintype "passive"))
      (node (ref "R68") (pin "2") (pinfunction "2_2") (pintype "passive"))
      (node (ref "R75") (pin "2") (pinfunction "2_2") (pintype "passive"))
      (node (ref "R78") (pin "2") (pinfunction "2_2") (pintype "passive"))
      (node (ref "R79") (pin "2") (pinfunction "2_2") (pintype "passive"))
      (node (ref "R8") (pin "2") (pinfunction "2_2") (pintype "passive"))
      (node (ref "U1") (pin "8") (pinfunction "VCCB_8") (pintype "power_in"))
      (node (ref "U11") (pin "8") (pinfunction "VCCB_8") (pintype "power_in"))
      (node (ref "U19") (pin "5") (pinfunction "+3V3_5") (pintype "power_in"))
      (node (ref "U2") (pin "8") (pinfunction "VCCB_8") (pintype "power_in"))
      (node (ref "U20") (pin "19") (pinfunction "VCCB_19") (pintype "power_in"))
      (node (ref "U21") (pin "8") (pinfunction "VCCB_8") (pintype "power_in"))
      (node (ref "U22") (pin "8") (pinfunction "VCCB_8") (pintype "power_in"))
      (node (ref "U27") (pin "8") (pinfunction "VCCB_8") (pintype "power_in"))
    )
    (net (code "34") (name "22.MMC0_CLK") (class "Default")
      (node (ref "RP1") (pin "2") (pinfunction "2_2") (pintype "passive"))
      (node (ref "RP2") (pin "15") (pinfunction "15_15") (pintype "passive"))
      (node (ref "U$72") (pin "G17") (pinfunction "MMC0_CLK|GPMC_A24|UART3_CTSN|UART2_RXD|DCAN1_TX|PR1_PRU0_PRU_R30_12|PR1_PRU0_PRU_R31_12|GPIO2_30_G17") (pintype "bidirectional"))
    )
    (net (code "35") (name "22.MMC0_CMD") (class "Default")
      (node (ref "RP1") (pin "1") (pinfunction "1_1") (pintype "passive"))
      (node (ref "RP2") (pin "16") (pinfunction "16_16") (pintype "passive"))
      (node (ref "U$72") (pin "G18") (pinfunction "MMC0_CMD|GPMC_A25|UART3_RTSN|UART2_TXD|DCAN1_RX|PR1_PRU0_PRU_R30_13|PR1_PRU0_PRU_R31_13|GPIO2_31_G18") (pintype "bidirectional"))
    )
    (net (code "36") (name "22.MMC0_DAT0") (class "Default")
      (node (ref "RP1") (pin "5") (pinfunction "5_5") (pintype "passive"))
      (node (ref "RP2") (pin "14") (pinfunction "14_14") (pintype "passive"))
      (node (ref "U$72") (pin "G16") (pinfunction "MMC0_DAT0|GPMC_A23|UART5_RTSN|UART3_TXD|UART1_RIN|PR1_PRU0_PRU_R30_11|PR1_PRU0_PRU_R31_11|GPIO2_29_G16") (pintype "bidirectional"))
    )
    (net (code "37") (name "22.MMC0_DAT1") (class "Default")
      (node (ref "RP1") (pin "6") (pinfunction "6_6") (pintype "passive"))
      (node (ref "RP2") (pin "13") (pinfunction "13_13") (pintype "passive"))
      (node (ref "U$72") (pin "G15") (pinfunction "MMC0_DAT1|GPMC_A22|UART5_CTSN|UART3_RXD|UART1_DTRN|PR1_PRU0_PRU_R30_10|PR1_PRU0_PRU_R31_10|GPIO2_28_G15") (pintype "bidirectional"))
    )
    (net (code "38") (name "22.MMC0_DAT2") (class "Default")
      (node (ref "RP1") (pin "7") (pinfunction "7_7") (pintype "passive"))
      (node (ref "RP2") (pin "12") (pinfunction "12_12") (pintype "passive"))
      (node (ref "U$72") (pin "F18") (pinfunction "MMC0_DAT2|GPMC_A21|UART4_RTSN|TIMER6|UART1_DSRN|PR1_PRU0_PRU_R30_9|PR1_PRU0_PRU_R31_9|GPIO2_27_F18") (pintype "bidirectional"))
    )
    (net (code "39") (name "22.MMC0_DAT3") (class "Default")
      (node (ref "RP1") (pin "8") (pinfunction "8_8") (pintype "passive"))
      (node (ref "RP2") (pin "11") (pinfunction "11_11") (pintype "passive"))
      (node (ref "U$72") (pin "F17") (pinfunction "MMC0_DAT3|GPMC_A20|UART4_CTSN|TIMER5|UART1_DCDN|PR1_PRU0_PRU_R30_8|PR1_PRU0_PRU_R31_8|GPIO2_26_F17") (pintype "bidirectional"))
    )
    (net (code "40") (name "39.ADC12_IN4") (class "Default")
      (node (ref "C110") (pin "1") (pinfunction "1_1") (pintype "passive"))
      (node (ref "IC3") (pin "29") (pinfunction "PA4_29") (pintype "bidirectional"))
      (node (ref "R64") (pin "2") (pinfunction "2_2") (pintype "passive"))
      (node (ref "R66") (pin "1") (pinfunction "1_1") (pintype "passive"))
    )
    (net (code "41") (name "39.ADC12_IN5") (class "Default")
      (node (ref "C110") (pin "2") (pinfunction "2_2") (pintype "passive"))
      (node (ref "IC3") (pin "30") (pinfunction "PA5_30") (pintype "bidirectional"))
      (node (ref "R65") (pin "2") (pinfunction "2_2") (pintype "passive"))
      (node (ref "R67") (pin "1") (pinfunction "1_1") (pintype "passive"))
    )
    (net (code "42") (name "39.ADC12_IN6") (class "Default")
      (node (ref "C111") (pin "1") (pinfunction "1_1") (pintype "passive"))
      (node (ref "IC3") (pin "31") (pinfunction "PA6_31") (pintype "bidirectional"))
      (node (ref "R71") (pin "2") (pinfunction "2_2") (pintype "passive"))
      (node (ref "R73") (pin "1") (pinfunction "1_1") (pintype "passive"))
    )
    (net (code "43") (name "39.ADC12_IN7") (class "Default")
      (node (ref "C111") (pin "2") (pinfunction "2_2") (pintype "passive"))
      (node (ref "IC3") (pin "32") (pinfunction "PA7_32") (pintype "bidirectional"))
      (node (ref "R72") (pin "2") (pinfunction "2_2") (pintype "passive"))
      (node (ref "R74") (pin "1") (pinfunction "1_1") (pintype "passive"))
    )
    (net (code "44") (name "39.ADC12_IN9") (class "Default")
      (node (ref "IC3") (pin "36") (pinfunction "PB1_36") (pintype "bidirectional"))
      (node (ref "J4") (pin "1") (pinfunction "1_1") (pintype "passive"))
    )
    (net (code "45") (name "39.ADC12_IN14") (class "Default")
      (node (ref "IC3") (pin "33") (pinfunction "PC4_33") (pintype "bidirectional"))
      (node (ref "J4") (pin "5") (pinfunction "5_5") (pintype "passive"))
    )
    (net (code "46") (name "39.ADC12_IN15") (class "Default")
      (node (ref "IC3") (pin "34") (pinfunction "PC5_34") (pintype "bidirectional"))
      (node (ref "J4") (pin "6") (pinfunction "6_6") (pintype "passive"))
    )
    (net (code "47") (name "39.ADC123_IN0") (class "Default")
      (node (ref "C14") (pin "1") (pinfunction "1_1") (pintype "passive"))
      (node (ref "IC3") (pin "23") (pinfunction "PA0_23") (pintype "bidirectional"))
      (node (ref "R4") (pin "2") (pinfunction "2_2") (pintype "passive"))
      (node (ref "R6") (pin "1") (pinfunction "1_1") (pintype "passive"))
    )
    (net (code "48") (name "39.ADC123_IN1") (class "Default")
      (node (ref "C14") (pin "2") (pinfunction "2_2") (pintype "passive"))
      (node (ref "IC3") (pin "24") (pinfunction "PA1_24") (pintype "bidirectional"))
      (node (ref "R5") (pin "2") (pinfunction "2_2") (pintype "passive"))
      (node (ref "R7") (pin "1") (pinfunction "1_1") (pintype "passive"))
    )
    (net (code "49") (name "39.ADC123_IN2") (class "Default")
      (node (ref "C15") (pin "1") (pinfunction "1_1") (pintype "passive"))
      (node (ref "IC3") (pin "25") (pinfunction "PA2_25") (pintype "bidirectional"))
      (node (ref "R11") (pin "2") (pinfunction "2_2") (pintype "passive"))
      (node (ref "R13") (pin "1") (pinfunction "1_1") (pintype "passive"))
    )
    (net (code "50") (name "39.ADC123_IN3") (class "Default")
      (node (ref "C15") (pin "2") (pinfunction "2_2") (pintype "passive"))
      (node (ref "IC3") (pin "26") (pinfunction "PA3_26") (pintype "bidirectional"))
      (node (ref "R12") (pin "2") (pinfunction "2_2") (pintype "passive"))
      (node (ref "R14") (pin "1") (pinfunction "1_1") (pintype "passive"))
    )
    (net (code "51") (name "39.ADC123_IN11") (class "Default")
      (node (ref "IC3") (pin "16") (pinfunction "PC1_16") (pintype "bidirectional"))
      (node (ref "J4") (pin "2") (pinfunction "2_2") (pintype "passive"))
    )
    (net (code "52") (name "39.ADC123_IN12") (class "Default")
      (node (ref "IC3") (pin "17") (pinfunction "PC2_17") (pintype "bidirectional"))
      (node (ref "J4") (pin "3") (pinfunction "3_3") (pintype "passive"))
    )
    (net (code "53") (name "39.ADC123_IN13") (class "Default")
      (node (ref "IC3") (pin "18") (pinfunction "PC3_18") (pintype "bidirectional"))
      (node (ref "J4") (pin "4") (pinfunction "4_4") (pintype "passive"))
    )
    (net (code "54") (name "39.AGND") (class "Default")
      (node (ref "C133") (pin "2") (pinfunction "2_2") (pintype "passive"))
      (node (ref "C134") (pin "2") (pinfunction "2_2") (pintype "passive"))
      (node (ref "IC3") (pin "20") (pinfunction "VSSA_OR_VREF-_20") (pintype "input"))
      (node (ref "J5") (pin "A1") (pinfunction "1_A1") (pintype "passive"))
      (node (ref "J5") (pin "A2") (pinfunction "3_A2") (pintype "passive"))
      (node (ref "J5") (pin "A3") (pinfunction "5_A3") (pintype "passive"))
      (node (ref "J5") (pin "A4") (pinfunction "7_A4") (pintype "passive"))
      (node (ref "J5") (pin "A5") (pinfunction "9_A5") (pintype "passive"))
      (node (ref "J5") (pin "A6") (pinfunction "11_A6") (pintype "passive"))
      (node (ref "R87") (pin "1") (pinfunction "1_1") (pintype "passive"))
    )
    (net (code "55") (name "39.BOOT0") (class "Default")
      (node (ref "BOOT0") (pin "1") (pinfunction "TP_1") (pintype "bidirectional"))
      (node (ref "IC3") (pin "94") (pinfunction "BOOT0_94") (pintype "input"))
      (node (ref "R85") (pin "1") (pinfunction "1_1") (pintype "passive"))
      (node (ref "R91") (pin "2") (pinfunction "2_2") (pintype "passive"))
      (node (ref "R93") (pin "2") (pinfunction "2_2") (pintype "passive"))
      (node (ref "U32") (pin "7") (pinfunction "B1_7") (pintype "output"))
    )
    (net (code "56") (name "39.I2C1_SCL") (class "Default")
      (node (ref "IC3") (pin "92") (pinfunction "PB6_92") (pintype "bidirectional"))
      (node (ref "R138") (pin "1") (pinfunction "1_1") (pintype "passive"))
      (node (ref "U21") (pin "2") (pinfunction "A1_2") (pintype "input"))
    )
    (net (code "57") (name "39.I2C1_SDA") (class "Default")
      (node (ref "IC3") (pin "93") (pinfunction "PB7_93") (pintype "bidirectional"))
      (node (ref "R139") (pin "1") (pinfunction "1_1") (pintype "passive"))
      (node (ref "U21") (pin "3") (pinfunction "A2_3") (pintype "input"))
    )
    (net (code "58") (name "39.PB0") (class "Default")
      (node (ref "C9") (pin "1") (pinfunction "1_1") (pintype "passive"))
      (node (ref "IC3") (pin "35") (pinfunction "PB0_35") (pintype "bidirectional"))
      (node (ref "R1") (pin "1") (pinfunction "1_1") (pintype "passive"))
      (node (ref "R2") (pin "2") (pinfunction "2_2") (pintype "passive"))
      (node (ref "S1") (pin "B@2") (pinfunction "B'_B@2") (pintype "passive"))
    )
    (net (code "59") (name "39.PB8") (class "Default")
      (node (ref "IC3") (pin "95") (pinfunction "PB8_95") (pintype "bidirectional"))
      (node (ref "RP7") (pin "3") (pinfunction "3_3") (pintype "passive"))
      (node (ref "U29") (pin "7") (pinfunction "A6_7") (pintype "bidirectional"))
    )
    (net (code "60") (name "39.PB9") (class "Default")
      (node (ref "IC3") (pin "96") (pinfunction "PB9_96") (pintype "bidirectional"))
      (node (ref "RP7") (pin "4") (pinfunction "4_4") (pintype "passive"))
      (node (ref "U29") (pin "6") (pinfunction "A5_6") (pintype "bidirectional"))
    )
    (net (code "61") (name "39.PC9") (class "Default")
      (node (ref "IC3") (pin "66") (pinfunction "PC9_66") (pintype "bidirectional"))
      (node (ref "RP7") (pin "2") (pinfunction "2_2") (pintype "passive"))
      (node (ref "U29") (pin "8") (pinfunction "A7_8") (pintype "bidirectional"))
    )
    (net (code "62") (name "39.PC13") (class "Default")
      (node (ref "IC3") (pin "7") (pinfunction "PC13_7") (pintype "bidirectional"))
      (node (ref "U4") (pin "16") (pinfunction "BIN2_16") (pintype "bidirectional"))
    )
    (net (code "63") (name "39.PC14") (class "Default")
      (node (ref "IC3") (pin "8") (pinfunction "PC14_8") (pintype "bidirectional"))
      (node (ref "U23") (pin "21") (pinfunction "AIN1_21") (pintype "bidirectional"))
    )
    (net (code "64") (name "39.PC15") (class "Default")
      (node (ref "IC3") (pin "9") (pinfunction "PC15_9") (pintype "bidirectional"))
      (node (ref "U23") (pin "22") (pinfunction "AIN2_22") (pintype "bidirectional"))
    )
    (net (code "65") (name "39.PD0") (class "Default")
      (node (ref "IC3") (pin "81") (pinfunction "PD0_81") (pintype "bidirectional"))
      (node (ref "RP4") (pin "12") (pinfunction "12_12") (pintype "passive"))
      (node (ref "U20") (pin "7") (pinfunction "A6_7") (pintype "bidirectional"))
    )
    (net (code "66") (name "39.PD1") (class "Default")
      (node (ref "IC3") (pin "82") (pinfunction "PD1_82") (pintype "bidirectional"))
      (node (ref "U4") (pin "21") (pinfunction "AIN1_21") (pintype "bidirectional"))
    )
    (net (code "67") (name "39.PD2") (class "Default")
      (node (ref "IC3") (pin "83") (pinfunction "PD2_83") (pintype "bidirectional"))
      (node (ref "U12") (pin "6") (pinfunction "DRDY_6") (pintype "bidirectional"))
    )
    (net (code "68") (name "39.PD3") (class "Default")
      (node (ref "IC3") (pin "84") (pinfunction "PD3_84") (pintype "bidirectional"))
      (node (ref "U13") (pin "11") (pinfunction "INT1_11") (pintype "bidirectional"))
    )
    (net (code "69") (name "39.PD4") (class "Default")
      (node (ref "IC3") (pin "85") (pinfunction "PD4_85") (pintype "bidirectional"))
      (node (ref "U13") (pin "9") (pinfunction "INT2_9") (pintype "bidirectional"))
    )
    (net (code "70") (name "39.PD7") (class "Default")
      (node (ref "IC3") (pin "88") (pinfunction "PD7_88") (pintype "bidirectional"))
      (node (ref "U4") (pin "22") (pinfunction "AIN2_22") (pintype "bidirectional"))
    )
    (net (code "71") (name "39.PD8") (class "Default")
      (node (ref "IC3") (pin "55") (pinfunction "PD8_55") (pintype "bidirectional"))
      (node (ref "R21") (pin "2") (pinfunction "2_2") (pintype "passive"))
      (node (ref "U10") (pin "7") (pinfunction "B1_7") (pintype "output"))
    )
    (net (code "72") (name "39.PD9") (class "Default")
      (node (ref "IC3") (pin "56") (pinfunction "PD9_56") (pintype "bidirectional"))
      (node (ref "R22") (pin "2") (pinfunction "2_2") (pintype "passive"))
      (node (ref "U10") (pin "6") (pinfunction "B2_6") (pintype "output"))
    )
    (net (code "73") (name "39.PD10") (class "Default")
      (node (ref "IC3") (pin "57") (pinfunction "PD10_57") (pintype "bidirectional"))
      (node (ref "U23") (pin "17") (pinfunction "BIN1_17") (pintype "bidirectional"))
    )
    (net (code "74") (name "39.PD11") (class "Default")
      (node (ref "IC3") (pin "58") (pinfunction "PD11_58") (pintype "bidirectional"))
      (node (ref "U23") (pin "16") (pinfunction "BIN2_16") (pintype "bidirectional"))
    )
    (net (code "75") (name "39.PD12") (class "Default")
      (node (ref "IC3") (pin "59") (pinfunction "PD12_59") (pintype "bidirectional"))
      (node (ref "RP7") (pin "8") (pinfunction "8_8") (pintype "passive"))
      (node (ref "U29") (pin "1") (pinfunction "A1_1") (pintype "bidirectional"))
    )
    (net (code "76") (name "39.PD13") (class "Default")
      (node (ref "IC3") (pin "60") (pinfunction "PD13_60") (pintype "bidirectional"))
      (node (ref "RP7") (pin "7") (pinfunction "7_7") (pintype "passive"))
      (node (ref "U29") (pin "3") (pinfunction "A2_3") (pintype "bidirectional"))
    )
    (net (code "77") (name "39.PD14") (class "Default")
      (node (ref "IC3") (pin "61") (pinfunction "PD14_61") (pintype "bidirectional"))
      (node (ref "RP7") (pin "6") (pinfunction "6_6") (pintype "passive"))
      (node (ref "U29") (pin "4") (pinfunction "A3_4") (pintype "bidirectional"))
    )
    (net (code "78") (name "39.PD15") (class "Default")
      (node (ref "IC3") (pin "62") (pinfunction "PD15_62") (pintype "bidirectional"))
      (node (ref "RP7") (pin "5") (pinfunction "5_5") (pintype "passive"))
      (node (ref "U29") (pin "5") (pinfunction "A4_5") (pintype "bidirectional"))
    )
    (net (code "79") (name "39.PE0") (class "Default")
      (node (ref "IC3") (pin "97") (pinfunction "PE0_97") (pintype "bidirectional"))
      (node (ref "RP7") (pin "1") (pinfunction "1_1") (pintype "passive"))
      (node (ref "U29") (pin "9") (pinfunction "A8_9") (pintype "bidirectional"))
    )
    (net (code "80") (name "39.PE1") (class "Default")
      (node (ref "IC3") (pin "98") (pinfunction "PE1_98") (pintype "bidirectional"))
      (node (ref "R80") (pin "1") (pinfunction "1_1") (pintype "passive"))
      (node (ref "U30") (pin "2") (pinfunction "A1_2") (pintype "input"))
    )
    (net (code "81") (name "39.PE4") (class "Default")
      (node (ref "IC3") (pin "3") (pinfunction "PE4_3") (pintype "bidirectional"))
      (node (ref "R81") (pin "1") (pinfunction "1_1") (pintype "passive"))
      (node (ref "U30") (pin "3") (pinfunction "A2_3") (pintype "input"))
    )
    (net (code "82") (name "39.PE9") (class "Default")
      (node (ref "IC3") (pin "40") (pinfunction "PE9_40") (pintype "bidirectional"))
      (node (ref "R59") (pin "1") (pinfunction "1_1") (pintype "passive"))
      (node (ref "R60") (pin "1") (pinfunction "1_1") (pintype "passive"))
    )
    (net (code "83") (name "39.PE11") (class "Default")
      (node (ref "IC3") (pin "42") (pinfunction "PE11_42") (pintype "bidirectional"))
      (node (ref "RP4") (pin "14") (pinfunction "14_14") (pintype "passive"))
      (node (ref "U20") (pin "5") (pinfunction "A4_5") (pintype "bidirectional"))
    )
    (net (code "84") (name "39.PE15") (class "Default")
      (node (ref "IC3") (pin "46") (pinfunction "PE15_46") (pintype "bidirectional"))
      (node (ref "U4") (pin "17") (pinfunction "BIN1_17") (pintype "bidirectional"))
    )
    (net (code "85") (name "39.PWM1") (class "Default")
      (node (ref "IC3") (pin "67") (pinfunction "PA8_67") (pintype "bidirectional"))
      (node (ref "U4") (pin "23") (pinfunction "PWMA_23") (pintype "bidirectional"))
    )
    (net (code "86") (name "39.PWM2") (class "Default")
      (node (ref "IC3") (pin "68") (pinfunction "PA9_68") (pintype "bidirectional"))
      (node (ref "R92") (pin "2") (pinfunction "2_2") (pintype "passive"))
      (node (ref "U4") (pin "15") (pinfunction "PWMB_15") (pintype "bidirectional"))
    )
    (net (code "87") (name "39.PWM3") (class "Default")
      (node (ref "IC3") (pin "69") (pinfunction "PA10_69") (pintype "bidirectional"))
      (node (ref "U23") (pin "23") (pinfunction "PWMA_23") (pintype "bidirectional"))
    )
    (net (code "88") (name "39.PWM4") (class "Default")
      (node (ref "IC3") (pin "63") (pinfunction "PC6_63") (pintype "bidirectional"))
      (node (ref "U23") (pin "15") (pinfunction "PWMB_15") (pintype "bidirectional"))
    )
    (net (code "89") (name "39.PWM5") (class "Default")
      (node (ref "IC3") (pin "64") (pinfunction "PC7_64") (pintype "bidirectional"))
      (node (ref "U2") (pin "2") (pinfunction "A1_2") (pintype "input"))
    )
    (net (code "90") (name "39.PWM6") (class "Default")
      (node (ref "IC3") (pin "65") (pinfunction "PC8_65") (pintype "bidirectional"))
      (node (ref "U2") (pin "3") (pinfunction "A2_3") (pintype "input"))
    )
    (net (code "91") (name "39.PWM7") (class "Default")
      (node (ref "IC3") (pin "4") (pinfunction "PE5_4") (pintype "bidirectional"))
      (node (ref "U22") (pin "2") (pinfunction "A1_2") (pintype "input"))
    )
    (net (code "92") (name "39.PWM8") (class "Default")
      (node (ref "IC3") (pin "5") (pinfunction "PE6_5") (pintype "bidirectional"))
      (node (ref "U22") (pin "3") (pinfunction "A2_3") (pintype "input"))
    )
    (net (code "93") (name "39.SPI2_CLK") (class "Default")
      (node (ref "IC3") (pin "52") (pinfunction "PB13_52") (pintype "bidirectional"))
      (node (ref "RP3") (pin "7") (pinfunction "7_7") (pintype "passive"))
      (node (ref "U8") (pin "14") (pinfunction "B6_14") (pintype "bidirectional"))
    )
    (net (code "94") (name "39.SPI2_CS0") (class "Default")
      (node (ref "IC3") (pin "51") (pinfunction "PB12_51") (pintype "bidirectional"))
      (node (ref "RP3") (pin "6") (pinfunction "6_6") (pintype "passive"))
      (node (ref "U8") (pin "16") (pinfunction "B4_16") (pintype "bidirectional"))
    )
    (net (code "95") (name "39.SPI2_MISO") (class "Default")
      (node (ref "IC3") (pin "53") (pinfunction "PB14_53") (pintype "bidirectional"))
      (node (ref "RP3") (pin "5") (pinfunction "5_5") (pintype "passive"))
      (node (ref "U8") (pin "17") (pinfunction "B3_17") (pintype "bidirectional"))
    )
    (net (code "96") (name "39.SPI2_MOSI") (class "Default")
      (node (ref "IC3") (pin "54") (pinfunction "PB15_54") (pintype "bidirectional"))
      (node (ref "RP3") (pin "8") (pinfunction "8_8") (pintype "passive"))
      (node (ref "U8") (pin "13") (pinfunction "B7_13") (pintype "bidirectional"))
    )
    (net (code "97") (name "39.SPI3_CLK") (class "Default")
      (node (ref "IC3") (pin "78") (pinfunction "PC10_78") (pintype "bidirectional"))
      (node (ref "U12") (pin "2") (pinfunction "SCL/SPC_2") (pintype "bidirectional"))
      (node (ref "U13") (pin "4") (pinfunction "SCL/SPC_4") (pintype "bidirectional"))
    )
    (net (code "98") (name "39.SPI3_CS0") (class "Default")
      (node (ref "IC3") (pin "1") (pinfunction "PE2_1") (pintype "bidirectional"))
      (node (ref "U13") (pin "8") (pinfunction "CS_8") (pintype "bidirectional"))
    )
    (net (code "99") (name "39.SPI3_CS1") (class "Default")
      (node (ref "IC3") (pin "2") (pinfunction "PE3_2") (pintype "bidirectional"))
      (node (ref "U12") (pin "5") (pinfunction "CS_5") (pintype "bidirectional"))
    )
    (net (code "100") (name "39.SPI3_MISO") (class "Default")
      (node (ref "IC3") (pin "79") (pinfunction "PC11_79") (pintype "bidirectional"))
      (node (ref "U12") (pin "4") (pinfunction "SDO/SA0_4") (pintype "bidirectional"))
      (node (ref "U13") (pin "7") (pinfunction "SDO/SA0_7") (pintype "bidirectional"))
    )
    (net (code "101") (name "39.SPI3_MOSI") (class "Default")
      (node (ref "IC3") (pin "80") (pinfunction "PC12_80") (pintype "bidirectional"))
      (node (ref "U12") (pin "3") (pinfunction "SDA/SDI_3") (pintype "bidirectional"))
      (node (ref "U13") (pin "6") (pinfunction "SDA/SDI_6") (pintype "bidirectional"))
    )
    (net (code "102") (name "39.SPI4_CLK") (class "Default")
      (node (ref "IC3") (pin "43") (pinfunction "PE12_43") (pintype "bidirectional"))
      (node (ref "RP4") (pin "15") (pinfunction "15_15") (pintype "passive"))
      (node (ref "U20") (pin "4") (pinfunction "A3_4") (pintype "bidirectional"))
    )
    (net (code "103") (name "39.SPI4_MISO") (class "Default")
      (node (ref "IC3") (pin "44") (pinfunction "PE13_44") (pintype "bidirectional"))
      (node (ref "RP4") (pin "11") (pinfunction "11_11") (pintype "passive"))
      (node (ref "U20") (pin "8") (pinfunction "A7_8") (pintype "bidirectional"))
    )
    (net (code "104") (name "39.SPI4_MOSI") (class "Default")
      (node (ref "IC3") (pin "45") (pinfunction "PE14_45") (pintype "bidirectional"))
      (node (ref "RP4") (pin "16") (pinfunction "16_16") (pintype "passive"))
      (node (ref "U20") (pin "3") (pinfunction "A2_3") (pintype "bidirectional"))
    )
    (net (code "105") (name "39.STM_RESET") (class "Default")
      (node (ref "C123") (pin "1") (pinfunction "1_1") (pintype "passive"))
      (node (ref "IC3") (pin "14") (pinfunction "NRST_14") (pintype "input"))
      (node (ref "JTAG") (pin "10") (pinfunction "S_10") (pintype "passive"))
      (node (ref "R94") (pin "2") (pinfunction "2_2") (pintype "passive"))
      (node (ref "U32") (pin "6") (pinfunction "B2_6") (pintype "output"))
    )
    (net (code "106") (name "39.UART2_RX") (class "Default")
      (node (ref "IC3") (pin "87") (pinfunction "PD6_87") (pintype "bidirectional"))
      (node (ref "U11") (pin "2") (pinfunction "A1_2") (pintype "input"))
    )
    (net (code "107") (name "39.UART2_TX") (class "Default")
      (node (ref "IC3") (pin "86") (pinfunction "PD5_86") (pintype "bidirectional"))
      (node (ref "U11") (pin "3") (pinfunction "A2_3") (pintype "input"))
    )
    (net (code "108") (name "39.UART3_RX") (class "Default")
      (node (ref "IC3") (pin "48") (pinfunction "PB11_48") (pintype "bidirectional"))
      (node (ref "R37") (pin "2") (pinfunction "2_2") (pintype "passive"))
      (node (ref "U16") (pin "4") (pinfunction "B2_4") (pintype "bidirectional"))
    )
    (net (code "109") (name "39.UART3_TX") (class "Default")
      (node (ref "IC3") (pin "47") (pinfunction "PB10_47") (pintype "bidirectional"))
      (node (ref "R36") (pin "2") (pinfunction "2_2") (pintype "passive"))
      (node (ref "U16") (pin "5") (pinfunction "B1_5") (pintype "bidirectional"))
    )
    (net (code "110") (name "39.USB_DEVICE_N") (class "Default")
      (node (ref "IC3") (pin "70") (pinfunction "PA11_70") (pintype "bidirectional"))
      (node (ref "L5") (pin "2") (pinfunction "2_2") (pintype "passive"))
    )
    (net (code "111") (name "39.USB_DEVICE_P") (class "Default")
      (node (ref "IC3") (pin "71") (pinfunction "PA12_71") (pintype "bidirectional"))
      (node (ref "L5") (pin "3") (pinfunction "3_3") (pintype "passive"))
    )
    (net (code "112") (name "45.BACKLIGHT_ENABLE") (class "Default")
      (node (ref "U$67") (pin "11") (pinfunction "1B6_11") (pintype "bidirectional"))
      (node (ref "U$72") (pin "V17") (pinfunction "GPMC_A11|GMII2_RXD0|RGMII2_RD0|RMII2_RXD0|GPMC_A27|PR1_MII1_RXER|MCASP0_AXR1|GPIO1_27_V17") (pintype "output"))
    )
    (net (code "113") (name "45.BACKLIGHT_N") (class "Default")
      (node (ref "U$70") (pin "1") (pinfunction "LED-_1") (pintype "power_in"))
      (node (ref "U35") (pin "33") (pinfunction "ISINK2_33") (pintype "input"))
      (node (ref "U35") (pin "34") (pinfunction "ISINK1_34") (pintype "input"))
    )
    (net (code "114") (name "45.BACKLIGHT_P") (class "Default")
      (node (ref "C234") (pin "1") (pinfunction "1_1") (pintype "passive"))
      (node (ref "D31") (pin "C") (pinfunction "C_C") (pintype "passive"))
      (node (ref "U$70") (pin "2") (pinfunction "LED+_2") (pintype "power_in"))
      (node (ref "U35") (pin "38") (pinfunction "FB_WLED_38") (pintype "input"))
    )
    (net (code "115") (name "45.CLKOUT1") (class "Default")
      (node (ref "Q5") (pin "3") (pinfunction "FO_3") (pintype "output"))
      (node (ref "U$72") (pin "A15") (pinfunction "XDMA_EVENT_INTR0|TIMER4|CLKOUT1|SPI1_CS1|PR1_PRU1_R31_16|EMU2|GPIO0_19_A15") (pintype "input"))
      (node (ref "U28") (pin "36") (pinfunction "EXT_32K_36") (pintype "bidirectional"))
    )
    (net (code "116") (name "45.GPIO0_7") (class "Default")
      (node (ref "U$69") (pin "11") (pinfunction "1B6_11") (pintype "bidirectional"))
      (node (ref "U$72") (pin "C18") (pinfunction "ECAP0_IN_PWM0_OUT|UART3_TXD|SPI1_CS1|PR1_ECAP0_ECAP_CAPIN_APWM_O|SPI1_SCLK|MMC0_SDWP|XDMA_EVENT_INTR2|GPIO0_7_C18") (pintype "bidirectional"))
    )
    (net (code "117") (name "45.GPIO1_1") (class "Default")
      (node (ref "R93") (pin "1") (pinfunction "1_1") (pintype "passive"))
      (node (ref "U$72") (pin "V7") (pinfunction "GPMC_AD1|MMC1_DAT1||||||GPIO1_1_V7") (pintype "bidirectional"))
      (node (ref "U32") (pin "2") (pinfunction "A1_2") (pintype "input"))
    )
    (net (code "118") (name "45.GPIO1_2") (class "Default")
      (node (ref "R94") (pin "1") (pinfunction "1_1") (pintype "passive"))
      (node (ref "U$72") (pin "R8") (pinfunction "GPMC_AD2|MMC1_DAT2||||||GPIO1_2_R8") (pintype "bidirectional"))
      (node (ref "U32") (pin "3") (pinfunction "A2_3") (pintype "input"))
    )
    (net (code "119") (name "45.GPIO1_3") (class "Default")
      (node (ref "R21") (pin "1") (pinfunction "1_1") (pintype "passive"))
      (node (ref "U$72") (pin "T8") (pinfunction "GPMC_AD3|MMC1_DAT3||||||GPIO1_3_T8") (pintype "bidirectional"))
      (node (ref "U10") (pin "2") (pinfunction "A1_2") (pintype "input"))
    )
    (net (code "120") (name "45.GPIO1_4") (class "Default")
      (node (ref "R22") (pin "1") (pinfunction "1_1") (pintype "passive"))
      (node (ref "U$72") (pin "U8") (pinfunction "GPMC_AD4|MMC1_DAT4||||||GPIO1_4_U8") (pintype "bidirectional"))
      (node (ref "U10") (pin "3") (pinfunction "A2_3") (pintype "input"))
    )
    (net (code "121") (name "45.GPIO1_5") (class "Default")
      (node (ref "R103") (pin "1") (pinfunction "1_1") (pintype "passive"))
      (node (ref "U$72") (pin "V8") (pinfunction "GPMC_AD5|MMC1_DAT5||||||GPIO1_5_V8") (pintype "bidirectional"))
    )
    (net (code "122") (name "45.GPIO1_16") (class "Default")
      (node (ref "R31") (pin "2") (pinfunction "2_2") (pintype "passive"))
      (node (ref "U$72") (pin "R13") (pinfunction "GPMC_A0|GMII2_TXEN|RGMII2_TCTL|RMII2_TXEN|GPMC_A16|PR1_MII_MT1_CLK|EHRPWM1_TRIPZONE_INPUT|GPIO1_16_R13") (pintype "output"))
      (node (ref "U15") (pin "33") (pinfunction "~{RESET}_33") (pintype "bidirectional"))
    )
    (net (code "123") (name "45.GPIO1_20") (class "Default")
      (node (ref "R56") (pin "1") (pinfunction "1_1") (pintype "passive"))
      (node (ref "R57") (pin "1") (pinfunction "1_1") (pintype "passive"))
      (node (ref "U$72") (pin "R14") (pinfunction "GPMC_A4|GMII2_TXD1|RGMII2_TD1|RMII2_TXD1|GPMC_A20|PR1_MII1_TXD0|EQEP1A_IN|GPIO1_20_R14") (pintype "output"))
    )
    (net (code "124") (name "45.GPIO1_21") (class "Default")
      (node (ref "R24") (pin "1") (pinfunction "1_1") (pintype "passive"))
      (node (ref "R25") (pin "1") (pinfunction "1_1") (pintype "passive"))
      (node (ref "U$72") (pin "V15") (pinfunction "GPMC_A5|GMII2_TXD0|RGMII2_TD0|RMII2_TXD0|GPMC_A21|PR1_MII1_RXD3|EQEP1B_IN|GPIO1_21_V15") (pintype "output"))
    )
    (net (code "125") (name "45.GPIO1_22") (class "Default")
      (node (ref "C104") (pin "1") (pinfunction "1_1") (pintype "passive"))
      (node (ref "R61") (pin "1") (pinfunction "1_1") (pintype "passive"))
      (node (ref "R62") (pin "2") (pinfunction "2_2") (pintype "passive"))
      (node (ref "S2") (pin "B@2") (pinfunction "B'_B@2") (pintype "passive"))
      (node (ref "U$72") (pin "U15") (pinfunction "GPMC_A6|GMII2_TXCLK|RGMII2_TCLK|MMC2_DAT4|GPMC_A22|PR1_MII1_RXD2|EQEP1_INDEX|GPIO1_22_U15") (pintype "output"))
    )
    (net (code "126") (name "45.GPIO1_29") (class "Default")
      (node (ref "BTEN") (pin "1") (pinfunction "TP_1") (pintype "bidirectional"))
      (node (ref "U$72") (pin "V6") (pinfunction "GPMC_CSN0|GPIO1_29_V6") (pintype "output"))
      (node (ref "U28") (pin "41") (pinfunction "BT_EN_SOC_41") (pintype "bidirectional"))
    )
    (net (code "127") (name "45.GPIO1_30") (class "Default")
      (node (ref "U$72") (pin "U9") (pinfunction "GPMC_CSN1|GPMC_CLK|MMC1_CLK|PRT1EDIO_DATA_IN6|PRT1_EDIO_DATA_OUT6|PR1_PRU1_PRU_R30_12|PR1_PRU1_PRU_R31_12|GPIO1_30_U9") (pintype "output"))
      (node (ref "U28") (pin "40") (pinfunction "WLAN_EN_SOC_40") (pintype "bidirectional"))
      (node (ref "WLEN") (pin "1") (pinfunction "TP_1") (pintype "bidirectional"))
    )
    (net (code "128") (name "45.GPIO1_31") (class "Default")
      (node (ref "U$72") (pin "V9") (pinfunction "GPMC_CSN2|GPMC_BE1N|MMC1_CMD|PR1_EDIO_DATA_IN7|PR1_EDIO_DATA_OUT7|PR1_PRU1_PRU_R30_13|PR1_PRU1_PRU_R31_13|GPIO1_31_V9") (pintype "output"))
      (node (ref "U28") (pin "14") (pinfunction "WLAN_IRQ_14") (pintype "bidirectional"))
    )
    (net (code "129") (name "45.I2C0_SCL") (class "Default")
      (node (ref "R123") (pin "1") (pinfunction "1_1") (pintype "passive"))
      (node (ref "U$72") (pin "C16") (pinfunction "I2C0_SCL|TIMER7|UART2_RTSN|ECAP1_IN_PWM1_OUT||||GPIO3_6_C16") (pintype "bidirectional"))
      (node (ref "U15") (pin "1") (pinfunction "SCL_1") (pintype "bidirectional"))
      (node (ref "U34") (pin "6") (pinfunction "SCL_6") (pintype "bidirectional"))
      (node (ref "U35") (pin "28") (pinfunction "SCL_28") (pintype "input"))
    )
    (net (code "130") (name "45.I2C0_SDA") (class "Default")
      (node (ref "R122") (pin "1") (pinfunction "1_1") (pintype "passive"))
      (node (ref "U$72") (pin "C17") (pinfunction "I2C0_SDA|TIMER4|UART2_CTSN|ECAP2_IN_PWM2_OUT||||GPIO3_5_C17") (pintype "bidirectional"))
      (node (ref "U15") (pin "2") (pinfunction "SDA_2") (pintype "bidirectional"))
      (node (ref "U34") (pin "5") (pinfunction "SDA_5") (pintype "bidirectional"))
      (node (ref "U35") (pin "27") (pinfunction "SDA_27") (pintype "bidirectional"))
    )
    (net (code "131") (name "45.I2C1_SCL") (class "Default")
      (node (ref "R107") (pin "2") (pinfunction "2_2") (pintype "passive"))
      (node (ref "U$72") (pin "E17") (pinfunction "UART0_RTSN|UART4_TXD|DCAN1_RX|I2C1_SCL|SPI1_D1|SPI1_CS0|PR1_EDC_SYNC1_OUT|GPIO1_9_E17") (pintype "output"))
      (node (ref "U3") (pin "6") (pinfunction "SCL_6") (pintype "bidirectional"))
      (node (ref "U33") (pin "3") (pinfunction "SCL1_3") (pintype "bidirectional"))
    )
    (net (code "132") (name "45.I2C1_SDA") (class "Default")
      (node (ref "R108") (pin "2") (pinfunction "2_2") (pintype "passive"))
      (node (ref "U$72") (pin "E18") (pinfunction "UART0_CTSN|UART4_RXD|DCAN1_TX|I2C1_SDA|SPI1_D0|TIMER7|PR1_EDC_SYNC0_OUT|GPIO1_8_E18") (pintype "input"))
      (node (ref "U3") (pin "5") (pinfunction "SDA_5") (pintype "bidirectional"))
      (node (ref "U33") (pin "4") (pinfunction "SDA1_4") (pintype "bidirectional"))
    )
    (net (code "133") (name "45.I2C2_SCL") (class "Default")
      (node (ref "R128") (pin "1") (pinfunction "1_1") (pintype "passive"))
      (node (ref "U$72") (pin "D17") (pinfunction "UART1_RTSN|TIMER5|DCAN0_RX|I2C2_SCL|SPI1_CS1|PR1_UART0_RTS_N|PR1_EDC_LATCH1_IN|GPIO0_13_D17") (pintype "output"))
      (node (ref "U1") (pin "2") (pinfunction "A1_2") (pintype "input"))
    )
    (net (code "134") (name "45.I2C2_SDA") (class "Default")
      (node (ref "R130") (pin "1") (pinfunction "1_1") (pintype "passive"))
      (node (ref "U$72") (pin "D18") (pinfunction "UART1_CTSN|TIMER6|DCAN0_TX|I2C2_SDA|SPI1_CS0|PR1_UART0_CTS_N|PR1_EDC_LATCH0_IN|GPIO0_12_D18") (pintype "input"))
      (node (ref "U1") (pin "3") (pinfunction "A2_3") (pintype "input"))
    )
    (net (code "135") (name "45.LCD_BIAS") (class "Default")
      (node (ref "R115") (pin "1") (pinfunction "1_1") (pintype "passive"))
      (node (ref "U$67") (pin "6") (pinfunction "1B3_6") (pintype "bidirectional"))
      (node (ref "U$72") (pin "R6") (pinfunction "LCD_AC_BIAS_EN|GPMC_A11||PR1_EDIO_DATA_IN5|PR1_EDIO_DATA_OUT5|PR1_PRU1_PRU_R30_11|PR1_PRU1_PRU_R31_11|GPIO2_25_R6") (pintype "bidirectional"))
    )
    (net (code "136") (name "45.LCD_DD0") (class "Default")
      (node (ref "R113") (pin "1") (pinfunction "1_1") (pintype "passive"))
      (node (ref "U$68") (pin "19") (pinfunction "2B4_19") (pintype "bidirectional"))
      (node (ref "U$72") (pin "R1") (pinfunction "LCD_DATA0|GPMC_A0||EHRPWM2A||PR1_PRU1_PRU_R30_0|PR1_PRU1_PRU_R31_0|GPIO2_6_R1") (pintype "bidirectional"))
      (node (ref "U$80") (pin "P5") (pinfunction "P$5_P5") (pintype "bidirectional"))
    )
    (net (code "137") (name "45.LCD_DD1") (class "Default")
      (node (ref "RP8") (pin "16") (pinfunction "16_16") (pintype "passive"))
      (node (ref "U$68") (pin "17") (pinfunction "2B3_17") (pintype "bidirectional"))
      (node (ref "U$72") (pin "R2") (pinfunction "LCD_DATA1|GPMC_A1||EHRPWM2B||PR1_PRU1_PRU_R30_1|PR1_PRU1_PRU_R31_1|GPIO2_7_R2") (pintype "bidirectional"))
      (node (ref "U$80") (pin "P7") (pinfunction "P$7_P7") (pintype "bidirectional"))
    )
    (net (code "138") (name "45.LCD_DD2") (class "Default")
      (node (ref "RP8") (pin "15") (pinfunction "15_15") (pintype "passive"))
      (node (ref "U$68") (pin "16") (pinfunction "2B2_16") (pintype "bidirectional"))
      (node (ref "U$72") (pin "R3") (pinfunction "LCD_DATA2|GPMC_A2||EHRPWM2_TRIPZONE_INPUT||PR1_PRU1_PRU_R30_2|PR1_PRU1_PRU_R31_2|GPIO2_8_R3") (pintype "bidirectional"))
      (node (ref "U$80") (pin "P6") (pinfunction "P$6_P6") (pintype "bidirectional"))
    )
    (net (code "139") (name "45.LCD_DD3") (class "Default")
      (node (ref "RP8") (pin "14") (pinfunction "14_14") (pintype "passive"))
      (node (ref "U$68") (pin "14") (pinfunction "2B1_14") (pintype "bidirectional"))
      (node (ref "U$72") (pin "R4") (pinfunction "LCD_DATA3|GPMC_A3||EHRPWM2_SYNCI_O||PR1_PRU1_PRU_R30_3|PR1_PRU1_PRU_R31_3|GPIO2_9_R4") (pintype "bidirectional"))
      (node (ref "U$80") (pin "P8") (pinfunction "P$8_P8") (pintype "bidirectional"))
    )
    (net (code "140") (name "45.LCD_DD4") (class "Default")
      (node (ref "RP8") (pin "13") (pinfunction "13_13") (pintype "passive"))
      (node (ref "U$68") (pin "13") (pinfunction "2B0_13") (pintype "bidirectional"))
      (node (ref "U$72") (pin "T1") (pinfunction "LCD_DATA4|GPMC_A4||EQEP2A_IN||PR1_PRU1_PRU_R30_4|PR1_PRU1_PRU_R31_4|GPIO2_10_T1") (pintype "bidirectional"))
      (node (ref "U$79") (pin "P5") (pinfunction "P$5_P5") (pintype "bidirectional"))
    )
    (net (code "141") (name "45.LCD_DD5") (class "Default")
      (node (ref "RP8") (pin "12") (pinfunction "12_12") (pintype "passive"))
      (node (ref "U$68") (pin "9") (pinfunction "1B5_9") (pintype "bidirectional"))
      (node (ref "U$72") (pin "T2") (pinfunction "LCD_DATA5|GPMC_A5||EQEP2B_IN||PR1_PRU1_PRU_R30_5|PR1_PRU1_PRU_R31_5|GPIO2_11_T2") (pintype "bidirectional"))
      (node (ref "U$79") (pin "P7") (pinfunction "P$7_P7") (pintype "bidirectional"))
    )
    (net (code "142") (name "45.LCD_DD6") (class "Default")
      (node (ref "RP8") (pin "10") (pinfunction "10_10") (pintype "passive"))
      (node (ref "U$68") (pin "8") (pinfunction "1B4_8") (pintype "bidirectional"))
      (node (ref "U$72") (pin "T3") (pinfunction "LCD_DATA6|GPMC_A6|PR1_EDIO_DATA_IN6|EQEP2_INDEX|PR1_EDIO_DATA_OUT6|PR1_PRU1_PRU_R30_6|PR1_PRU1_PRU_R31_6|GPIO2_12_T3") (pintype "bidirectional"))
      (node (ref "U$79") (pin "P6") (pinfunction "P$6_P6") (pintype "bidirectional"))
    )
    (net (code "143") (name "45.LCD_DD7") (class "Default")
      (node (ref "RP8") (pin "9") (pinfunction "9_9") (pintype "passive"))
      (node (ref "U$68") (pin "6") (pinfunction "1B3_6") (pintype "bidirectional"))
      (node (ref "U$72") (pin "T4") (pinfunction "LCD_DATA7|GPMC_A7|PR1_EDIO_DATA_IN7|EQEP2_STROBE|PR1_EDIO_DATA_OUT7|PR1_PRU1_PRU_R30_7|PR1_PRU1_PRU_R31_7|GPIO2_13_T4") (pintype "bidirectional"))
      (node (ref "U$81") (pin "P5") (pinfunction "P$5_P5") (pintype "bidirectional"))
    )
    (net (code "144") (name "45.LCD_DD8") (class "Default")
      (node (ref "RP9") (pin "16") (pinfunction "16_16") (pintype "passive"))
      (node (ref "U$68") (pin "5") (pinfunction "1B2_5") (pintype "bidirectional"))
      (node (ref "U$72") (pin "U1") (pinfunction "LCD_DATA8|GPMC_A12|EHRPWM1_TRIPZONE_INPUT|MCASP0_ACLKX|UART5_TXD|PR1_MII0_RXD3|UART2_CTSN|GPIO2_14_U1") (pintype "bidirectional"))
      (node (ref "U$79") (pin "P8") (pinfunction "P$8_P8") (pintype "bidirectional"))
    )
    (net (code "145") (name "45.LCD_DD9") (class "Default")
      (node (ref "RP9") (pin "15") (pinfunction "15_15") (pintype "passive"))
      (node (ref "U$68") (pin "3") (pinfunction "1B1_3") (pintype "bidirectional"))
      (node (ref "U$72") (pin "U2") (pinfunction "LCD_DATA9|GPMC_A13|EHRPWM1_SYNCI_O|MCASP0_FSX|UART5_RXD|PR1_MII0_RXD2|UART2_RTSN|GPIO2_15_U2") (pintype "bidirectional"))
      (node (ref "U$81") (pin "P6") (pinfunction "P$6_P6") (pintype "bidirectional"))
    )
    (net (code "146") (name "45.LCD_DD10") (class "Default")
      (node (ref "RP9") (pin "14") (pinfunction "14_14") (pintype "passive"))
      (node (ref "U$68") (pin "2") (pinfunction "1B0_2") (pintype "bidirectional"))
      (node (ref "U$72") (pin "U3") (pinfunction "LCD_DATA10|GPMC_A14|EHRPWM1A|MCASP0_AXR0||PR1_MII0_RXD1|UART3_CTSN|GPIO2_16_U3") (pintype "bidirectional"))
      (node (ref "U$81") (pin "P8") (pinfunction "P$8_P8") (pintype "bidirectional"))
    )
    (net (code "147") (name "45.LCD_DD11") (class "Default")
      (node (ref "RP9") (pin "13") (pinfunction "13_13") (pintype "passive"))
      (node (ref "U$67") (pin "19") (pinfunction "2B4_19") (pintype "bidirectional"))
      (node (ref "U$72") (pin "U4") (pinfunction "LCD_DATA11|GPMC_A15|EHRPWM1B|MCASP0_AHCLKR|MCASP0_AXR2|PR1_MII0_RXD0|UART3_RTSN|GPIO2_17_U4") (pintype "bidirectional"))
      (node (ref "U$82") (pin "P6") (pinfunction "P$6_P6") (pintype "bidirectional"))
    )
    (net (code "148") (name "45.LCD_DD12") (class "Default")
      (node (ref "RP9") (pin "12") (pinfunction "12_12") (pintype "passive"))
      (node (ref "U$67") (pin "17") (pinfunction "2B3_17") (pintype "bidirectional"))
      (node (ref "U$72") (pin "V2") (pinfunction "LCD_DATA12|GPMC_A16|EQEP1A_IN|MCASP0_ACLKR|MCASP0_AXR2|PR1_MII0_RXLINK|UART4_CTSN|GPIO0_8_V2") (pintype "bidirectional"))
      (node (ref "U$81") (pin "P7") (pinfunction "P$7_P7") (pintype "bidirectional"))
    )
    (net (code "149") (name "45.LCD_DD13") (class "Default")
      (node (ref "RP9") (pin "11") (pinfunction "11_11") (pintype "passive"))
      (node (ref "U$67") (pin "16") (pinfunction "2B2_16") (pintype "bidirectional"))
      (node (ref "U$72") (pin "V3") (pinfunction "LCD_DATA13|GPMC_A17|EQEP1B_IN|MCASP0_FSR|MCASP0_AXR3|PR1_MII0_RXER|UART4_RTSN|GPIO0_9_V3") (pintype "bidirectional"))
      (node (ref "U$82") (pin "P5") (pinfunction "P$5_P5") (pintype "bidirectional"))
    )
    (net (code "150") (name "45.LCD_DD14") (class "Default")
      (node (ref "RP9") (pin "10") (pinfunction "10_10") (pintype "passive"))
      (node (ref "U$67") (pin "14") (pinfunction "2B1_14") (pintype "bidirectional"))
      (node (ref "U$72") (pin "V4") (pinfunction "LCD_DATA14|GPMC_A18|EQEP1_INDEX|MCASP0_AXR1|UART5_RXD|PR1_MII_MR0_CLK|UART5_CTSN|GPIO0_10_V4") (pintype "bidirectional"))
      (node (ref "U$82") (pin "P7") (pinfunction "P$7_P7") (pintype "bidirectional"))
    )
    (net (code "151") (name "45.LCD_DD15") (class "Default")
      (node (ref "RP9") (pin "9") (pinfunction "9_9") (pintype "passive"))
      (node (ref "U$67") (pin "13") (pinfunction "2B0_13") (pintype "bidirectional"))
      (node (ref "U$72") (pin "T5") (pinfunction "LCD_DATA15|GPMC_A19|EQEP1_STROBE|MCASP0_AHCLKX|MCASP0_AXR3|PR1_MII0_RXDV|UART5_RTSN|GPIO0_11_T5") (pintype "bidirectional"))
      (node (ref "U$82") (pin "P8") (pinfunction "P$8_P8") (pintype "bidirectional"))
    )
    (net (code "152") (name "45.LCD_DD16") (class "Default")
      (node (ref "RP10") (pin "16") (pinfunction "16_16") (pintype "passive"))
      (node (ref "U$68") (pin "20") (pinfunction "2B5_20") (pintype "bidirectional"))
      (node (ref "U$72") (pin "U13") (pinfunction "GPMC_AD15|LCD_DATA16|MMC1_DAT7|MMC2_DAT3|EQEP2_STROBE|PR1_ECAP0_ECAP_CAPIN_APWM_O|PR1_PRU0_PRU_R31_15|GPIO1_15_U13") (pintype "bidirectional"))
    )
    (net (code "153") (name "45.LCD_DD17") (class "Default")
      (node (ref "RP10") (pin "15") (pinfunction "15_15") (pintype "passive"))
      (node (ref "U$67") (pin "20") (pinfunction "2B5_20") (pintype "bidirectional"))
      (node (ref "U$72") (pin "V13") (pinfunction "GPMC_AD14|LCD_DATA17|MMC1_DAT6|MMC2_DAT2|EQEP2_INDEX|PR1_MII0_TXD0|PR1_PRU0_PRU_R31_14|GPIO1_14_V13") (pintype "bidirectional"))
    )
    (net (code "154") (name "45.LCD_DD18") (class "Default")
      (node (ref "RP10") (pin "14") (pinfunction "14_14") (pintype "passive"))
      (node (ref "U$68") (pin "22") (pinfunction "2B6_22") (pintype "bidirectional"))
      (node (ref "U$72") (pin "R12") (pinfunction "GPMC_AD13|LCD_DATA18|MMC1_DAT5|MMC2_DAT1|EQEP2B_IN|PR1_MII0_TXD1|PR1_PRU0_PRU_R30_15|GPIO1_13_R12") (pintype "bidirectional"))
    )
    (net (code "155") (name "45.LCD_DD19") (class "Default")
      (node (ref "RP10") (pin "13") (pinfunction "13_13") (pintype "passive"))
      (node (ref "U$68") (pin "11") (pinfunction "1B6_11") (pintype "bidirectional"))
      (node (ref "U$72") (pin "T12") (pinfunction "GPMC_AD12|LCD_DATA19|MMC1_DAT4|MMC2_DAT0|EQEP2A_IN|PR1_MII0_TXD2|PR1_PRU0_PRU_R30_14|GPIO1_12_T12") (pintype "bidirectional"))
    )
    (net (code "156") (name "45.LCD_DD20") (class "Default")
      (node (ref "RP10") (pin "12") (pinfunction "12_12") (pintype "passive"))
      (node (ref "U$67") (pin "22") (pinfunction "2B6_22") (pintype "bidirectional"))
      (node (ref "U$72") (pin "U12") (pinfunction "GPMC_AD11|LCD_DATA20|MMC1_DAT3|MMC2_DAT7|EHRPWM2_SYNCI_O|PR1_MII0_TXD3||GPIO0_27_U12") (pintype "bidirectional"))
    )
    (net (code "157") (name "45.LCD_DD21") (class "Default")
      (node (ref "RP10") (pin "11") (pinfunction "11_11") (pintype "passive"))
      (node (ref "U$68") (pin "23") (pinfunction "2B7_23") (pintype "bidirectional"))
      (node (ref "U$72") (pin "T11") (pinfunction "GPMC_AD10|LCD_DATA21|MMC1_DAT2|MMC2_DAT6|EHRPWM2_TRIPZONE_INPUT|PR1_MII0_TXEN||GPIO0_26_T11") (pintype "bidirectional"))
    )
    (net (code "158") (name "45.LCD_DD22") (class "Default")
      (node (ref "RP10") (pin "10") (pinfunction "10_10") (pintype "passive"))
      (node (ref "U$68") (pin "12") (pinfunction "1B7_12") (pintype "bidirectional"))
      (node (ref "U$72") (pin "T10") (pinfunction "GPMC_AD9|LCD_DATA22|MMC1_DAT1|MMC2_DAT5|EHRPWM2B|PR1_MII0_CRS||GPIO0_23_T10") (pintype "bidirectional"))
    )
    (net (code "159") (name "45.LCD_DD23") (class "Default")
      (node (ref "RP10") (pin "9") (pinfunction "9_9") (pintype "passive"))
      (node (ref "U$67") (pin "23") (pinfunction "2B7_23") (pintype "bidirectional"))
      (node (ref "U$72") (pin "U10") (pinfunction "GPMC_AD8|LCD_DATA23|MMC1_DAT0|MMC2_DAT4|EHRPWM2A|PR1_MII_MT0_CLK||GPIO0_22_U10") (pintype "bidirectional"))
    )
    (net (code "160") (name "45.LCD_HSYNC") (class "Default")
      (node (ref "R117") (pin "1") (pinfunction "1_1") (pintype "passive"))
      (node (ref "U$67") (pin "9") (pinfunction "1B5_9") (pintype "bidirectional"))
      (node (ref "U$72") (pin "R5") (pinfunction "LCD_HSYNC|GPMC_A9||PR1_EDIO_DATA_IN3|PR1_EDIO_DATA_OUT3|PR1_PRU1_PRU_R30_9|PR1_PRU1_PRU_R31_9|GPIO2_23_R5") (pintype "output"))
    )
    (net (code "161") (name "45.LCD_PCLK") (class "Default")
      (node (ref "RP8") (pin "11") (pinfunction "11_11") (pintype "passive"))
      (node (ref "U$67") (pin "12") (pinfunction "1B7_12") (pintype "bidirectional"))
      (node (ref "U$72") (pin "V5") (pinfunction "LCD_PCLK|GPMC_A10||PR1_EDIO_DATA_IN4|PR1_EDIO_DATA_OUT4|PR1_PRU1_PRU_R30_10|PR1_PRU1_PRU_R31_10|GPIO2_24_V5") (pintype "output"))
    )
    (net (code "162") (name "45.LCD_VSYNC") (class "Default")
      (node (ref "R116") (pin "1") (pinfunction "1_1") (pintype "passive"))
      (node (ref "U$67") (pin "8") (pinfunction "1B4_8") (pintype "bidirectional"))
      (node (ref "U$72") (pin "U5") (pinfunction "LCD_VSYNC|GPMC_A8||PR1_EDIO_DATA_IN2|PR1_EDIO_DATA_OUT2|PR1_PRU1_PRU_R30_8|PR1_PRU1_PRU_R31_8|GPIO2_22_U5") (pintype "output"))
    )
    (net (code "163") (name "45.MCASP0_ACLKX") (class "Default")
      (node (ref "U$72") (pin "A13") (pinfunction "MCASP0_ACLKX|EHRPWM0A||SPI1_SCLK|MMC0_SDCD|PR1_PRU0_PRU_R30_0|PR1_PRU0_PRU_R31_0|GPIO3_14_A13") (pintype "bidirectional"))
      (node (ref "U15") (pin "38") (pinfunction "BCLK_38") (pintype "bidirectional"))
    )
    (net (code "164") (name "45.MCASP0_AXR0") (class "Default")
      (node (ref "U$72") (pin "D12") (pinfunction "MCASP0_AXR0|EHRPWM0_TRIPZONE_INPUT||SPI1_D1|MMC2_SDCD|PR1_PRU0_PRU_R30_2|PR1_PRU0_PRU_R31_2|GPIO3_16_D12") (pintype "bidirectional"))
      (node (ref "U15") (pin "40") (pinfunction "DIN_40") (pintype "bidirectional"))
    )
    (net (code "165") (name "45.MCASP0_AXR1") (class "Default")
      (node (ref "U$72") (pin "D13") (pinfunction "MCASP0_AXR1|EQEP0_INDEX||MCASP1_AXR0|EMU3|PR1_PRU0_PRU_R30_6|PR1_PRU0_PRU_R31_6|GPIO3_20_D13") (pintype "bidirectional"))
      (node (ref "U15") (pin "41") (pinfunction "DOUT_41") (pintype "bidirectional"))
    )
    (net (code "166") (name "45.MCASP0_FSX") (class "Default")
      (node (ref "U$72") (pin "B13") (pinfunction "MCASP0_FSX|EHRPWM0B||SPI1_D0|MMC1_SDCD|PR1_PRU0_PRU_R30_1|PR1_PRU0_PRU_R31_1|GPIO3_15_B13") (pintype "bidirectional"))
      (node (ref "U15") (pin "39") (pinfunction "WCLK_39") (pintype "bidirectional"))
    )
    (net (code "167") (name "45.MMC2_CLK") (class "Default")
      (node (ref "RP5") (pin "7") (pinfunction "7_7") (pintype "passive"))
      (node (ref "RP6") (pin "10") (pinfunction "10_10") (pintype "passive"))
      (node (ref "U$72") (pin "V12") (pinfunction "GPMC_CLK|LCD_MEM_CLK|GPMC_WAIT1|MMC2_CLK|PRT1_MII1_TXEN|MCASP0_FSR|GPIO2_1_V12") (pintype "output"))
    )
    (net (code "168") (name "45.MMC2_CMD") (class "Default")
      (node (ref "RP5") (pin "8") (pinfunction "8_8") (pintype "passive"))
      (node (ref "RP6") (pin "9") (pinfunction "9_9") (pintype "passive"))
      (node (ref "U$72") (pin "T13") (pinfunction "GPMC_CSN3|MMC2_CMD|PR1_MDIO_DATA|GPIO2_0_T13") (pintype "output"))
    )
    (net (code "169") (name "45.MMC2_DAT0") (class "Default")
      (node (ref "RP5") (pin "5") (pinfunction "5_5") (pintype "passive"))
      (node (ref "RP6") (pin "12") (pinfunction "12_12") (pintype "passive"))
      (node (ref "U$72") (pin "V14") (pinfunction "GPMC_A1|GMII2_RXDV|RGMII2_RCTL|MMC2_DAT0|GPMC_A17|PR1_MII1_TXD3|EHRPWM1_SYNCI_O|GPIO1_17_V14") (pintype "output"))
    )
    (net (code "170") (name "45.MMC2_DAT1") (class "Default")
      (node (ref "RP5") (pin "4") (pinfunction "4_4") (pintype "passive"))
      (node (ref "RP6") (pin "13") (pinfunction "13_13") (pintype "passive"))
      (node (ref "U$72") (pin "U14") (pinfunction "GPMC_A2|GMII2_TXD3|RGMII2_TD3|MMC2_DAT1|GPMC_A18|PR1_MII1_TXD2|EHRPWM1A|GPIO1_18_U14") (pintype "output"))
    )
    (net (code "171") (name "45.MMC2_DAT2") (class "Default")
      (node (ref "RP5") (pin "2") (pinfunction "2_2") (pintype "passive"))
      (node (ref "RP6") (pin "15") (pinfunction "15_15") (pintype "passive"))
      (node (ref "U$72") (pin "T14") (pinfunction "GPMC_A3|GMII2_TXD2|RGMII2_TD2|MMC2_DAT2|GPMC_A19|PR1_MII1_TXD1|EHRPWM1B|GPIO1_19_T14") (pintype "output"))
    )
    (net (code "172") (name "45.MMC2_DAT3") (class "Default")
      (node (ref "RP5") (pin "1") (pinfunction "1_1") (pintype "passive"))
      (node (ref "RP6") (pin "16") (pinfunction "16_16") (pintype "passive"))
      (node (ref "U$72") (pin "U18") (pinfunction "GPMC_BE1N|GMII2_COL|GPMC_CSN6|MMC2_DAT3|GPMC_DIR|PR1_MII1_RXLINK|MCASP0_ACLKR|GPIO1_28_U18") (pintype "output"))
    )
    (net (code "173") (name "45.PMIC_PGOOD") (class "Default")
      (node (ref "IC1") (pin "13") (pinfunction "ENABLE_13") (pintype "input"))
      (node (ref "U$72") (pin "B15") (pinfunction "PWRONRSTN_B15") (pintype "input"))
      (node (ref "U35") (pin "26") (pinfunction "PGOOD_26") (pintype "open_collector"))
    )
    (net (code "174") (name "45.SPI0_CLK") (class "Default")
      (node (ref "RP3") (pin "2") (pinfunction "2_2") (pintype "passive"))
      (node (ref "U$67") (pin "2") (pinfunction "1B0_2") (pintype "bidirectional"))
      (node (ref "U$72") (pin "A17") (pinfunction "SPI0_SCLK|UART2_RXD|I2C2_SDA|EHRPWM0A|PR1_UART0_CTS_N|PR1_EDIO_SOF|EMU2|GPIO0_2_A17") (pintype "bidirectional"))
      (node (ref "U8") (pin "7") (pinfunction "A6_7") (pintype "bidirectional"))
    )
    (net (code "175") (name "45.SPI0_CS0") (class "Default")
      (node (ref "U$67") (pin "3") (pinfunction "1B1_3") (pintype "bidirectional"))
      (node (ref "U$72") (pin "A16") (pinfunction "SPI0_CS0|MMC2_SDWP|I2C1_SCL|EHRPWM0_SYNCI_O|PR1_UART0_TXD|PR1_EDIO_DATA_IN1|PR1_EDIO_DATA_OUT1|GPIO0_5_A16") (pintype "bidirectional"))
    )
    (net (code "176") (name "45.SPI0_CS1") (class "Default")
      (node (ref "RP3") (pin "3") (pinfunction "3_3") (pintype "passive"))
      (node (ref "U$72") (pin "C15") (pinfunction "SPI0_CS1|UART3_RXD|ECAP1_IN_PWM1_OUT|MMC0_POW|XDMA_EVENT_INTR2|MMC0_SDCD|EMU4|GPIO0_6_C15") (pintype "bidirectional"))
      (node (ref "U8") (pin "5") (pinfunction "A4_5") (pintype "bidirectional"))
    )
    (net (code "177") (name "45.SPI0_MISO") (class "Default")
      (node (ref "RP3") (pin "4") (pinfunction "4_4") (pintype "passive"))
      (node (ref "U$69") (pin "8") (pinfunction "1B4_8") (pintype "bidirectional"))
      (node (ref "U$72") (pin "B17") (pinfunction "SPI0_D0|UART2_TXD|I2C2_SCL|EHRPWM0B|PR1_UART0_RTS_N|PR1_EDIO_LATCH_IN|EMU3|GPIO0_3_B17") (pintype "bidirectional"))
      (node (ref "U8") (pin "4") (pinfunction "A3_4") (pintype "bidirectional"))
    )
    (net (code "178") (name "45.SPI0_MOSI") (class "Default")
      (node (ref "RP3") (pin "1") (pinfunction "1_1") (pintype "passive"))
      (node (ref "U$67") (pin "5") (pinfunction "1B2_5") (pintype "bidirectional"))
      (node (ref "U$72") (pin "B16") (pinfunction "SPI0_D1|MMC1_SDWP|I2C1_SDA|EHRPWM0_TRIPZONE_INPUT|PR1_UART0_RXD|PR1_EDIO_DATA_IN0|PR1_EDIO_DATA_OUT0|GPIO0_4_B16") (pintype "bidirectional"))
      (node (ref "U8") (pin "8") (pinfunction "A7_8") (pintype "bidirectional"))
    )
    (net (code "179") (name "45.UART0_RX") (class "Default")
      (node (ref "U$72") (pin "E15") (pinfunction "UART0_RXD|SPI1_CS0|DCAN0_TX|I2C2_SDA|ECAP2_IN_PWM2_OUT|PR1_PRU1_PRU_R30_14|PR1_PRU1_PRU_R31_14|GPIO1_10_E15") (pintype "input"))
      (node (ref "U27") (pin "2") (pinfunction "A1_2") (pintype "input"))
    )
    (net (code "180") (name "45.UART0_TX") (class "Default")
      (node (ref "U$72") (pin "E16") (pinfunction "UART0_TXD|SPI1_CS1|DCAN0_RX|I2C2_SCL|ECAP1_IN_PWM1_OUT|PR1_PRU1_PRU_R30_15|PR1_PRU1_PRU_R31_15|GPIO1_11_E16") (pintype "output"))
      (node (ref "U27") (pin "3") (pinfunction "A2_3") (pintype "input"))
    )
    (net (code "181") (name "45.UART1_RX") (class "Default")
      (node (ref "R36") (pin "1") (pinfunction "1_1") (pintype "passive"))
      (node (ref "U$72") (pin "D16") (pinfunction "UART1_RXD|MMC1_SDWP|DCAN1_TX|I2C1_SDA||PR1_UART0_RXD|PR1_PRU1_PRU_R31_16|GPIO0_14_D16") (pintype "input"))
      (node (ref "U16") (pin "8") (pinfunction "A1_8") (pintype "bidirectional"))
    )
    (net (code "182") (name "45.UART1_TX") (class "Default")
      (node (ref "R37") (pin "1") (pinfunction "1_1") (pintype "passive"))
      (node (ref "U$72") (pin "D15") (pinfunction "UART1_TXD|MMC2_SDWP|DCAN1_RX|I2C1_SCL||PR1_UART0_TXD|PR1_PRU0_PRU_R31_16|GPIO0_15_D15") (pintype "output"))
      (node (ref "U16") (pin "9") (pinfunction "A2_9") (pintype "bidirectional"))
    )
    (net (code "183") (name "45.UART5_CTS") (class "Default")
      (node (ref "U$72") (pin "H17") (pinfunction "GMII1_CRS|RMII1_CRS_DV|SPI1_D0|I2C1_SDA|MCASP1_ACLKX|UART5_CTSN|UART2_RXD|GPIO3_1_H17") (pintype "input"))
      (node (ref "U28") (pin "50") (pinfunction "BT_HCI_RTS_50") (pintype "bidirectional"))
    )
    (net (code "184") (name "45.UART5_RTS") (class "Default")
      (node (ref "U$72") (pin "J15") (pinfunction "GMII1_RXERR|RMII1_RXERR|SPI1_D1|I2C1_SCL|MCASP1_FSX|UART5_RTSN|UART2_TXD|GPIO3_2_J15") (pintype "input"))
      (node (ref "U28") (pin "51") (pinfunction "BT_HCI_CTS_51") (pintype "bidirectional"))
    )
    (net (code "185") (name "45.UART5_RX") (class "Default")
      (node (ref "U$72") (pin "H16") (pinfunction "GMII1_COL|RMII2_REFCLK|SPI1_SCLK|UART5_RXD|MCASP1_AXR2|MMC2_DAT3|MCASP0_AXR2|GPIO3_0_H16") (pintype "input"))
      (node (ref "U28") (pin "52") (pinfunction "BT_HCI_TX_52") (pintype "bidirectional"))
    )
    (net (code "186") (name "45.UART5_TX") (class "Default")
      (node (ref "U$72") (pin "J17") (pinfunction "GMII1_RXDV|LCD_MEMORY_CLK|RGMII1_RCTL|UART5_TXD|MCASP1_ACLKX|MMC2_DAT0|MCASP0_ACLKR|GPIO3_4_J17") (pintype "input"))
      (node (ref "U28") (pin "53") (pinfunction "BT_HCI_RX_53") (pintype "bidirectional"))
    )
    (net (code "187") (name "45.USB_DEVICE_0_N") (class "Default")
      (node (ref "L6") (pin "2") (pinfunction "2_2") (pintype "passive"))
      (node (ref "U$72") (pin "N18") (pinfunction "USB0_DM_N18") (pintype "bidirectional"))
    )
    (net (code "188") (name "45.USB_DEVICE_0_P") (class "Default")
      (node (ref "L6") (pin "3") (pinfunction "3_3") (pintype "passive"))
      (node (ref "U$72") (pin "N17") (pinfunction "USB0_DP_N17") (pintype "bidirectional"))
    )
    (net (code "189") (name "45.USB_DEVICE_0_VBUS") (class "Default")
      (node (ref "R82") (pin "1") (pinfunction "1_1") (pintype "passive"))
      (node (ref "U$72") (pin "P15") (pinfunction "USB0_VBUS_P15") (pintype "bidirectional"))
    )
    (net (code "190") (name "45.USB_HOST_1_N") (class "Default")
      (node (ref "U$72") (pin "R18") (pinfunction "USB1_DM_R18") (pintype "bidirectional"))
      (node (ref "U18") (pin "30") (pinfunction "USBDM_UP_30") (pintype "bidirectional"))
    )
    (net (code "191") (name "45.USB_HOST_1_P") (class "Default")
      (node (ref "U$72") (pin "R17") (pinfunction "USB1_DP_R17") (pintype "bidirectional"))
      (node (ref "U18") (pin "31") (pinfunction "USBDP_UP_31") (pintype "bidirectional"))
    )
    (net (code "192") (name "45.USB_HOST_1_PWREN") (class "Default")
      (node (ref "R44") (pin "2") (pinfunction "2_2") (pintype "passive"))
      (node (ref "U$72") (pin "F15") (pinfunction "USB1_DRVVBUS_F15") (pintype "output"))
      (node (ref "U18") (pin "27") (pinfunction "VBUS_DET_27") (pintype "passive"))
    )
    (net (code "193") (name "45.USB_HOST_1_VBUS") (class "Default")
      (node (ref "R110") (pin "1") (pinfunction "1_1") (pintype "passive"))
      (node (ref "U$72") (pin "T18") (pinfunction "USB1_VBUS_T18") (pintype "bidirectional"))
      (node (ref "U19") (pin "4") (pinfunction "O_4") (pintype "output"))
    )
    (net (code "194") (name "ACCEL_C1$13") (class "Default")
      (node (ref "C46") (pin "1") (pinfunction "1_1") (pintype "passive"))
      (node (ref "U13") (pin "15") (pinfunction "C1_15") (pintype "power_in"))
    )
    (net (code "195") (name "ACCEL_SET1$13") (class "Default")
      (node (ref "C45") (pin "1") (pinfunction "1_1") (pintype "passive"))
      (node (ref "U13") (pin "3") (pinfunction "SETP_3") (pintype "passive"))
    )
    (net (code "196") (name "ACCEL_SET2$13") (class "Default")
      (node (ref "C45") (pin "2") (pinfunction "2_2") (pintype "passive"))
      (node (ref "U13") (pin "2") (pinfunction "SETC_2") (pintype "power_in"))
    )
    (net (code "197") (name "ACLK$33") (class "Default")
      (node (ref "ACLK") (pin "1") (pinfunction "TP_1") (pintype "bidirectional"))
      (node (ref "U28") (pin "60") (pinfunction "BT_AUD_CLK_60") (pintype "bidirectional"))
    )
    (net (code "198") (name "ACS0$33") (class "Default")
      (node (ref "ACS0") (pin "1") (pinfunction "TP_1") (pintype "bidirectional"))
      (node (ref "U28") (pin "58") (pinfunction "BT_AUD_FSYNC_58") (pintype "bidirectional"))
    )
    (net (code "199") (name "ADC123_IN10$39") (class "Default")
      (node (ref "IC3") (pin "15") (pinfunction "PC0_15") (pintype "bidirectional"))
      (node (ref "R88") (pin "2") (pinfunction "2_2") (pintype "passive"))
      (node (ref "R89") (pin "1") (pinfunction "1_1") (pintype "passive"))
    )
    (net (code "200") (name "AGND$45") (class "Default")
      (node (ref "FB11") (pin "1") (pinfunction "1_1") (pintype "passive"))
      (node (ref "U$72") (pin "A9") (pinfunction "VREFN_A9") (pintype "bidirectional"))
      (node (ref "U$72") (pin "E8") (pinfunction "VSSA_ADC_E8") (pintype "power_in"))
    )
    (net (code "201") (name "AIN7$45") (class "Default")
      (node (ref "U$72") (pin "C9") (pinfunction "AIN7_C9") (pintype "bidirectional"))
      (node (ref "U35") (pin "16") (pinfunction "MUX_OUT_16") (pintype "output"))
    )
    (net (code "202") (name "ARX$33") (class "Default")
      (node (ref "ARX") (pin "1") (pinfunction "TP_1") (pintype "bidirectional"))
      (node (ref "U28") (pin "56") (pinfunction "BT_AUD_IN_56") (pintype "bidirectional"))
    )
    (net (code "203") (name "ATX$33") (class "Default")
      (node (ref "ATX") (pin "1") (pinfunction "TP_1") (pintype "bidirectional"))
      (node (ref "U28") (pin "57") (pinfunction "BT_AUD_OUT_57") (pintype "bidirectional"))
    )
    (net (code "204") (name "AVCC$45") (class "Default")
      (node (ref "C251") (pin "1") (pinfunction "1_1") (pintype "passive"))
      (node (ref "FB12") (pin "2") (pinfunction "2_2") (pintype "passive"))
      (node (ref "U$72") (pin "B9") (pinfunction "VREFP_B9") (pintype "bidirectional"))
      (node (ref "U$72") (pin "D8") (pinfunction "VDDA_ADC_D8") (pintype "power_in"))
    )
    (net (code "205") (name "A_GNDF$14") (class "Default")
      (node (ref "C27") (pin "1") (pinfunction "1_1") (pintype "passive"))
      (node (ref "D6") (pin "P2") (pinfunction "P2_P2") (pintype "passive"))
      (node (ref "FB1") (pin "2") (pinfunction "2_2") (pintype "passive"))
      (node (ref "K1") (pin "A4") (pinfunction "GND_A4") (pintype "bidirectional"))
      (node (ref "K1") (pin "B4") (pinfunction "GND_B4") (pintype "bidirectional"))
    )
    (net (code "206") (name "A_USB_DM$14") (class "Default")
      (node (ref "D3") (pin "P2") (pinfunction "P2_P2") (pintype "passive"))
      (node (ref "K1") (pin "A2") (pinfunction "D-_A2") (pintype "bidirectional"))
      (node (ref "L3") (pin "1") (pinfunction "1_1") (pintype "passive"))
    )
    (net (code "207") (name "A_USB_DP$14") (class "Default")
      (node (ref "D4") (pin "P2") (pinfunction "P2_P2") (pintype "passive"))
      (node (ref "K1") (pin "A3") (pinfunction "D+_A3") (pintype "bidirectional"))
      (node (ref "L3") (pin "4") (pinfunction "4_4") (pintype "passive"))
    )
    (net (code "208") (name "BAT$45") (class "Default")
      (node (ref "U35") (pin "4") (pinfunction "BAT1_4") (pintype "bidirectional"))
      (node (ref "U35") (pin "5") (pinfunction "BAT2_5") (pintype "bidirectional"))
      (node (ref "U35") (pin "6") (pinfunction "BAT_SENSE_6") (pintype "input"))
    )
    (net (code "209") (name "BLUE0$43") (class "Default")
      (node (ref "U$67") (pin "26") (pinfunction "2A7_26") (pintype "bidirectional"))
      (node (ref "U$70") (pin "21") (pinfunction "B0_21") (pintype "output"))
    )
    (net (code "210") (name "BLUE1$43") (class "Default")
      (node (ref "U$67") (pin "27") (pinfunction "2A6_27") (pintype "bidirectional"))
      (node (ref "U$70") (pin "22") (pinfunction "B1_22") (pintype "output"))
    )
    (net (code "211") (name "BLUE2$43") (class "Default")
      (node (ref "U$67") (pin "29") (pinfunction "2A5_29") (pintype "bidirectional"))
      (node (ref "U$70") (pin "23") (pinfunction "B2_23") (pintype "output"))
    )
    (net (code "212") (name "BLUE3$43") (class "Default")
      (node (ref "U$67") (pin "30") (pinfunction "2A4_30") (pintype "bidirectional"))
      (node (ref "U$70") (pin "24") (pinfunction "B3_24") (pintype "output"))
    )
    (net (code "213") (name "BLUE4$43") (class "Default")
      (node (ref "U$67") (pin "32") (pinfunction "2A3_32") (pintype "bidirectional"))
      (node (ref "U$70") (pin "25") (pinfunction "B4_25") (pintype "output"))
    )
    (net (code "214") (name "BLUE5$43") (class "Default")
      (node (ref "U$67") (pin "33") (pinfunction "2A2_33") (pintype "bidirectional"))
      (node (ref "U$70") (pin "26") (pinfunction "B5_26") (pintype "output"))
    )
    (net (code "215") (name "BLUE6$43") (class "Default")
      (node (ref "U$67") (pin "35") (pinfunction "2A1_35") (pintype "bidirectional"))
      (node (ref "U$70") (pin "27") (pinfunction "B6_27") (pintype "output"))
    )
    (net (code "216") (name "BLUE7$43") (class "Default")
      (node (ref "U$67") (pin "36") (pinfunction "2A0_36") (pintype "bidirectional"))
      (node (ref "U$70") (pin "28") (pinfunction "B7_28") (pintype "output"))
    )
    (net (code "217") (name "BOOT1$39") (class "Default")
      (node (ref "IC3") (pin "37") (pinfunction "PB2_37") (pintype "bidirectional"))
      (node (ref "R86") (pin "2") (pinfunction "2_2") (pintype "passive"))
    )
    (net (code "218") (name "BT4$33") (class "Default")
      (node (ref "BT4") (pin "1") (pinfunction "TP_1") (pintype "bidirectional"))
      (node (ref "U28") (pin "43") (pinfunction "BT_UART_DBG_43") (pintype "bidirectional"))
    )
    (net (code "219") (name "BYPASS$45") (class "Default")
      (node (ref "C224") (pin "1") (pinfunction "1_1") (pintype "passive"))
      (node (ref "U35") (pin "47") (pinfunction "BYPASS_47") (pintype "output"))
    )
    (net (code "220") (name "B_USB_DM$14") (class "Default")
      (node (ref "D7") (pin "P2") (pinfunction "P2_P2") (pintype "passive"))
      (node (ref "K1") (pin "B2") (pinfunction "D-_B2") (pintype "bidirectional"))
      (node (ref "L4") (pin "1") (pinfunction "1_1") (pintype "passive"))
    )
    (net (code "221") (name "B_USB_DP$14") (class "Default")
      (node (ref "D8") (pin "P2") (pinfunction "P2_P2") (pintype "passive"))
      (node (ref "K1") (pin "B3") (pinfunction "D+_B3") (pintype "bidirectional"))
      (node (ref "L4") (pin "4") (pinfunction "4_4") (pintype "passive"))
    )
    (net (code "222") (name "C+$44") (class "Default")
      (node (ref "D27") (pin "P2") (pinfunction "P2_P2") (pintype "passive"))
      (node (ref "J15") (pin "12") (pinfunction "10_12") (pintype "passive"))
      (node (ref "L10") (pin "2") (pinfunction "2_2") (pintype "passive"))
    )
    (net (code "223") (name "C-$44") (class "Default")
      (node (ref "D28") (pin "P2") (pinfunction "P2_P2") (pintype "passive"))
      (node (ref "J15") (pin "14") (pinfunction "12_14") (pintype "passive"))
      (node (ref "L10") (pin "3") (pinfunction "3_3") (pintype "passive"))
    )
    (net (code "224") (name "CLK$24") (class "Default")
      (node (ref "J7") (pin "A3") (pinfunction "A3_A3") (pintype "bidirectional"))
      (node (ref "RP4") (pin "2") (pinfunction "2_2") (pintype "passive"))
      (node (ref "U20") (pin "17") (pinfunction "B3_17") (pintype "bidirectional"))
    )
    (net (code "225") (name "COMMON_SHIELD") (class "Default")
      (node (ref "D13") (pin "P1") (pinfunction "P1_P1") (pintype "passive"))
      (node (ref "D14") (pin "P1") (pinfunction "P1_P1") (pintype "passive"))
      (node (ref "D16") (pin "P1") (pinfunction "P1_P1") (pintype "passive"))
      (node (ref "D17") (pin "P1") (pinfunction "P1_P1") (pintype "passive"))
      (node (ref "D18") (pin "P1") (pinfunction "P1_P1") (pintype "passive"))
      (node (ref "D19") (pin "P1") (pinfunction "P1_P1") (pintype "passive"))
      (node (ref "D20") (pin "P1") (pinfunction "P1_P1") (pintype "passive"))
      (node (ref "D21") (pin "P1") (pinfunction "P1_P1") (pintype "passive"))
      (node (ref "D22") (pin "P1") (pinfunction "P1_P1") (pintype "passive"))
      (node (ref "D23") (pin "P1") (pinfunction "P1_P1") (pintype "passive"))
      (node (ref "D24") (pin "P1") (pinfunction "P1_P1") (pintype "passive"))
      (node (ref "D25") (pin "P1") (pinfunction "P1_P1") (pintype "passive"))
      (node (ref "D26") (pin "P1") (pinfunction "P1_P1") (pintype "passive"))
      (node (ref "D27") (pin "P1") (pinfunction "P1_P1") (pintype "passive"))
      (node (ref "D28") (pin "P1") (pinfunction "P1_P1") (pintype "passive"))
      (node (ref "D29") (pin "P1") (pinfunction "P1_P1") (pintype "passive"))
      (node (ref "D3") (pin "P1") (pinfunction "P1_P1") (pintype "passive"))
      (node (ref "D30") (pin "P1") (pinfunction "P1_P1") (pintype "passive"))
      (node (ref "D4") (pin "P1") (pinfunction "P1_P1") (pintype "passive"))
      (node (ref "D5") (pin "P1") (pinfunction "P1_P1") (pintype "passive"))
      (node (ref "D6") (pin "P1") (pinfunction "P1_P1") (pintype "passive"))
      (node (ref "D7") (pin "P1") (pinfunction "P1_P1") (pintype "passive"))
      (node (ref "D8") (pin "P1") (pinfunction "P1_P1") (pintype "passive"))
      (node (ref "D9") (pin "P1") (pinfunction "P1_P1") (pintype "passive"))
      (node (ref "J10") (pin "COMMON_SHEILD1") (pinfunction "COMMON_SHIELD1_COMMON_SHEILD1") (pintype "bidirectional"))
      (node (ref "J10") (pin "COMMON_SHEILD2") (pinfunction "COMMON_SHIELD2_COMMON_SHEILD2") (pintype "bidirectional"))
      (node (ref "J10") (pin "COMMON_SHEILD3") (pinfunction "COMMON_SHIELD3_COMMON_SHEILD3") (pintype "bidirectional"))
      (node (ref "J10") (pin "COMMON_SHEILD4") (pinfunction "COMMON_SHIELD4_COMMON_SHEILD4") (pintype "bidirectional"))
      (node (ref "J10") (pin "COMMON_SHEILD5") (pinfunction "COMMON_SHIELD5_COMMON_SHEILD5") (pintype "bidirectional"))
      (node (ref "J10") (pin "COMMON_SHEILD6") (pinfunction "COMMON_SHIELD6_COMMON_SHEILD6") (pintype "bidirectional"))
      (node (ref "J14") (pin "COMMON_SHEILD1") (pinfunction "COMMON_SHIELD1_COMMON_SHEILD1") (pintype "bidirectional"))
      (node (ref "J14") (pin "COMMON_SHEILD2") (pinfunction "COMMON_SHIELD2_COMMON_SHEILD2") (pintype "bidirectional"))
      (node (ref "J14") (pin "COMMON_SHEILD3") (pinfunction "COMMON_SHIELD3_COMMON_SHEILD3") (pintype "bidirectional"))
      (node (ref "J14") (pin "COMMON_SHEILD4") (pinfunction "COMMON_SHIELD4_COMMON_SHEILD4") (pintype "bidirectional"))
      (node (ref "J14") (pin "COMMON_SHEILD5") (pinfunction "COMMON_SHIELD5_COMMON_SHEILD5") (pintype "bidirectional"))
      (node (ref "J14") (pin "COMMON_SHEILD6") (pinfunction "COMMON_SHIELD6_COMMON_SHEILD6") (pintype "bidirectional"))
      (node (ref "J15") (pin "CON1") (pinfunction "20_CON1") (pintype "passive"))
      (node (ref "J15") (pin "CON2") (pinfunction "21_CON2") (pintype "passive"))
      (node (ref "J15") (pin "CON3") (pinfunction "22_CON3") (pintype "passive"))
      (node (ref "J15") (pin "CON4") (pinfunction "23_CON4") (pintype "passive"))
    )
    (net (code "226") (name "CS0$24") (class "Default")
      (node (ref "J7") (pin "B2") (pinfunction "B2_B2") (pintype "bidirectional"))
      (node (ref "RP4") (pin "3") (pinfunction "3_3") (pintype "passive"))
      (node (ref "U20") (pin "16") (pinfunction "B4_16") (pintype "bidirectional"))
    )
    (net (code "227") (name "D0+$44") (class "Default")
      (node (ref "D25") (pin "P2") (pinfunction "P2_P2") (pintype "passive"))
      (node (ref "J15") (pin "9") (pinfunction "7_9") (pintype "passive"))
      (node (ref "L9") (pin "2") (pinfunction "2_2") (pintype "passive"))
    )
    (net (code "228") (name "D0-$44") (class "Default")
      (node (ref "D26") (pin "P2") (pinfunction "P2_P2") (pintype "passive"))
      (node (ref "J15") (pin "11") (pinfunction "9_11") (pintype "passive"))
      (node (ref "L9") (pin "3") (pinfunction "3_3") (pintype "passive"))
    )
    (net (code "229") (name "D1+$44") (class "Default")
      (node (ref "D23") (pin "P2") (pinfunction "P2_P2") (pintype "passive"))
      (node (ref "J15") (pin "6") (pinfunction "4_6") (pintype "passive"))
      (node (ref "L8") (pin "2") (pinfunction "2_2") (pintype "passive"))
    )
    (net (code "230") (name "D1-$44") (class "Default")
      (node (ref "D24") (pin "P2") (pinfunction "P2_P2") (pintype "passive"))
      (node (ref "J15") (pin "8") (pinfunction "6_8") (pintype "passive"))
      (node (ref "L8") (pin "3") (pinfunction "3_3") (pintype "passive"))
    )
    (net (code "231") (name "D2+$44") (class "Default")
      (node (ref "D21") (pin "P2") (pinfunction "P2_P2") (pintype "passive"))
      (node (ref "J15") (pin "3") (pinfunction "1_3") (pintype "passive"))
      (node (ref "L7") (pin "2") (pinfunction "2_2") (pintype "passive"))
    )
    (net (code "232") (name "D2-$44") (class "Default")
      (node (ref "D22") (pin "P2") (pinfunction "P2_P2") (pintype "passive"))
      (node (ref "J15") (pin "5") (pinfunction "3_5") (pintype "passive"))
      (node (ref "L7") (pin "3") (pinfunction "3_3") (pintype "passive"))
    )
    (net (code "233") (name "DC_IN$45") (class "Default")
      (node (ref "C225") (pin "1") (pinfunction "1_1") (pintype "passive"))
      (node (ref "FB10") (pin "2") (pinfunction "2_2") (pintype "passive"))
      (node (ref "U35") (pin "10") (pinfunction "AC_10") (pintype "input"))
    )
    (net (code "234") (name "DDR_A0$45") (class "Default")
      (node (ref "U$101") (pin "N3") (pinfunction "A0_N3") (pintype "input"))
      (node (ref "U$72") (pin "F3") (pinfunction "DDR_A0_F3") (pintype "output"))
    )
    (net (code "235") (name "DDR_A1$45") (class "Default")
      (node (ref "U$101") (pin "P7") (pinfunction "A1_P7") (pintype "input"))
      (node (ref "U$72") (pin "H1") (pinfunction "DDR_A1_H1") (pintype "output"))
    )
    (net (code "236") (name "DDR_A2$45") (class "Default")
      (node (ref "U$101") (pin "P3") (pinfunction "A2_P3") (pintype "input"))
      (node (ref "U$72") (pin "E4") (pinfunction "DDR_A2_E4") (pintype "output"))
    )
    (net (code "237") (name "DDR_A3$45") (class "Default")
      (node (ref "U$101") (pin "N2") (pinfunction "A3_N2") (pintype "input"))
      (node (ref "U$72") (pin "C3") (pinfunction "DDR_A3_C3") (pintype "output"))
    )
    (net (code "238") (name "DDR_A4$45") (class "Default")
      (node (ref "U$101") (pin "P8") (pinfunction "A4_P8") (pintype "input"))
      (node (ref "U$72") (pin "C2") (pinfunction "DDR_A4_C2") (pintype "output"))
    )
    (net (code "239") (name "DDR_A5$45") (class "Default")
      (node (ref "U$101") (pin "P2") (pinfunction "A5_P2") (pintype "input"))
      (node (ref "U$72") (pin "B1") (pinfunction "DDR_A5_B1") (pintype "output"))
    )
    (net (code "240") (name "DDR_A6$45") (class "Default")
      (node (ref "U$101") (pin "R8") (pinfunction "A6_R8") (pintype "input"))
      (node (ref "U$72") (pin "D5") (pinfunction "DDR_A6_D5") (pintype "output"))
    )
    (net (code "241") (name "DDR_A7$45") (class "Default")
      (node (ref "U$101") (pin "R2") (pinfunction "A7_R2") (pintype "input"))
      (node (ref "U$72") (pin "E2") (pinfunction "DDR_A7_E2") (pintype "output"))
    )
    (net (code "242") (name "DDR_A8$45") (class "Default")
      (node (ref "U$101") (pin "T8") (pinfunction "A8_T8") (pintype "input"))
      (node (ref "U$72") (pin "D4") (pinfunction "DDR_A8_D4") (pintype "output"))
    )
    (net (code "243") (name "DDR_A9$45") (class "Default")
      (node (ref "U$101") (pin "R3") (pinfunction "A9_R3") (pintype "input"))
      (node (ref "U$72") (pin "C1") (pinfunction "DDR_A9_C1") (pintype "output"))
    )
    (net (code "244") (name "DDR_A10$45") (class "Default")
      (node (ref "U$101") (pin "L7") (pinfunction "A10_L7") (pintype "input"))
      (node (ref "U$72") (pin "F4") (pinfunction "DDR_A10_F4") (pintype "output"))
    )
    (net (code "245") (name "DDR_A11$45") (class "Default")
      (node (ref "U$101") (pin "R7") (pinfunction "A11_R7") (pintype "input"))
      (node (ref "U$72") (pin "F2") (pinfunction "DDR_A11_F2") (pintype "output"))
    )
    (net (code "246") (name "DDR_A12$45") (class "Default")
      (node (ref "U$101") (pin "N7") (pinfunction "A12_N7") (pintype "input"))
      (node (ref "U$72") (pin "E3") (pinfunction "DDR_A12_E3") (pintype "output"))
    )
    (net (code "247") (name "DDR_A13$45") (class "Default")
      (node (ref "U$101") (pin "T3") (pinfunction "A13_T3") (pintype "input"))
      (node (ref "U$72") (pin "H3") (pinfunction "DDR_A13_H3") (pintype "output"))
    )
    (net (code "248") (name "DDR_A14$45") (class "Default")
      (node (ref "U$101") (pin "T7") (pinfunction "A14_T7") (pintype "input"))
      (node (ref "U$72") (pin "H4") (pinfunction "DDR_A14_H4") (pintype "output"))
    )
    (net (code "249") (name "DDR_A15$45") (class "Default")
      (node (ref "U$101") (pin "M7") (pinfunction "A15_M7") (pintype "input"))
      (node (ref "U$72") (pin "D3") (pinfunction "DDR_A15_D3") (pintype "output"))
    )
    (net (code "250") (name "DDR_BA0$45") (class "Default")
      (node (ref "U$101") (pin "M2") (pinfunction "BA0_M2") (pintype "input"))
      (node (ref "U$72") (pin "C4") (pinfunction "DDR_BA0_C4") (pintype "output"))
    )
    (net (code "251") (name "DDR_BA1$45") (class "Default")
      (node (ref "U$101") (pin "N8") (pinfunction "BA1_N8") (pintype "input"))
      (node (ref "U$72") (pin "E1") (pinfunction "DDR_BA1_E1") (pintype "output"))
    )
    (net (code "252") (name "DDR_BA2$45") (class "Default")
      (node (ref "U$101") (pin "M3") (pinfunction "BA2_M3") (pintype "input"))
      (node (ref "U$72") (pin "B3") (pinfunction "DDR_BA2_B3") (pintype "output"))
    )
    (net (code "253") (name "DDR_CASN$45") (class "Default")
      (node (ref "U$101") (pin "K3") (pinfunction "~{CAS}_K3") (pintype "input"))
      (node (ref "U$72") (pin "F1") (pinfunction "DDR_CASN_F1") (pintype "output"))
    )
    (net (code "254") (name "DDR_CKE$45") (class "Default")
      (node (ref "R135") (pin "2") (pinfunction "2_2") (pintype "passive"))
      (node (ref "U$101") (pin "K9") (pinfunction "CKE_K9") (pintype "input"))
      (node (ref "U$72") (pin "G3") (pinfunction "DDR_CKE_G3") (pintype "output"))
    )
    (net (code "255") (name "DDR_CK_N$45") (class "Default")
      (node (ref "U$101") (pin "K7") (pinfunction "~{CK}_K7") (pintype "input"))
      (node (ref "U$72") (pin "D1") (pinfunction "DDR_CKN_D1") (pintype "output"))
    )
    (net (code "256") (name "DDR_CK_P$45") (class "Default")
      (node (ref "U$101") (pin "J7") (pinfunction "CK_J7") (pintype "input"))
      (node (ref "U$72") (pin "D2") (pinfunction "DDR_CK_D2") (pintype "output"))
    )
    (net (code "257") (name "DDR_CSN0$45") (class "Default")
      (node (ref "U$101") (pin "L2") (pinfunction "~{CS}_L2") (pintype "input"))
      (node (ref "U$72") (pin "H2") (pinfunction "DDR_CSN0_H2") (pintype "output"))
    )
    (net (code "258") (name "DDR_D0$45") (class "Default")
      (node (ref "U$101") (pin "E3") (pinfunction "DQ0_E3") (pintype "bidirectional"))
      (node (ref "U$72") (pin "M3") (pinfunction "DDR_D0_M3") (pintype "bidirectional"))
    )
    (net (code "259") (name "DDR_D1$45") (class "Default")
      (node (ref "U$101") (pin "F7") (pinfunction "DQ1_F7") (pintype "bidirectional"))
      (node (ref "U$72") (pin "M4") (pinfunction "DDR_D1_M4") (pintype "bidirectional"))
    )
    (net (code "260") (name "DDR_D2$45") (class "Default")
      (node (ref "U$101") (pin "F2") (pinfunction "DQ2_F2") (pintype "bidirectional"))
      (node (ref "U$72") (pin "N1") (pinfunction "DDR_D2_N1") (pintype "bidirectional"))
    )
    (net (code "261") (name "DDR_D3$45") (class "Default")
      (node (ref "U$101") (pin "F8") (pinfunction "DQ3_F8") (pintype "bidirectional"))
      (node (ref "U$72") (pin "N2") (pinfunction "DDR_D3_N2") (pintype "bidirectional"))
    )
    (net (code "262") (name "DDR_D4$45") (class "Default")
      (node (ref "U$101") (pin "H3") (pinfunction "DQ4_H3") (pintype "bidirectional"))
      (node (ref "U$72") (pin "N3") (pinfunction "DDR_D4_N3") (pintype "bidirectional"))
    )
    (net (code "263") (name "DDR_D5$45") (class "Default")
      (node (ref "U$101") (pin "H8") (pinfunction "DQ5_H8") (pintype "bidirectional"))
      (node (ref "U$72") (pin "N4") (pinfunction "DDR_D5_N4") (pintype "bidirectional"))
    )
    (net (code "264") (name "DDR_D6$45") (class "Default")
      (node (ref "U$101") (pin "G2") (pinfunction "DQ6_G2") (pintype "bidirectional"))
      (node (ref "U$72") (pin "P3") (pinfunction "DDR_D6_P3") (pintype "bidirectional"))
    )
    (net (code "265") (name "DDR_D7$45") (class "Default")
      (node (ref "U$101") (pin "H7") (pinfunction "DQ7_H7") (pintype "bidirectional"))
      (node (ref "U$72") (pin "P4") (pinfunction "DDR_D7_P4") (pintype "bidirectional"))
    )
    (net (code "266") (name "DDR_D8$45") (class "Default")
      (node (ref "U$101") (pin "D7") (pinfunction "DQ8_D7") (pintype "bidirectional"))
      (node (ref "U$72") (pin "J1") (pinfunction "DDR_D8_J1") (pintype "bidirectional"))
    )
    (net (code "267") (name "DDR_D9$45") (class "Default")
      (node (ref "U$101") (pin "C3") (pinfunction "DQ9_C3") (pintype "bidirectional"))
      (node (ref "U$72") (pin "K1") (pinfunction "DDR_D9_K1") (pintype "bidirectional"))
    )
    (net (code "268") (name "DDR_D10$45") (class "Default")
      (node (ref "U$101") (pin "C8") (pinfunction "DQ10_C8") (pintype "bidirectional"))
      (node (ref "U$72") (pin "K2") (pinfunction "DDR_D10_K2") (pintype "bidirectional"))
    )
    (net (code "269") (name "DDR_D11$45") (class "Default")
      (node (ref "U$101") (pin "C2") (pinfunction "DQ11_C2") (pintype "bidirectional"))
      (node (ref "U$72") (pin "K3") (pinfunction "DDR_D11_K3") (pintype "bidirectional"))
    )
    (net (code "270") (name "DDR_D12$45") (class "Default")
      (node (ref "U$101") (pin "A7") (pinfunction "DQ12_A7") (pintype "bidirectional"))
      (node (ref "U$72") (pin "K4") (pinfunction "DDR_D12_K4") (pintype "bidirectional"))
    )
    (net (code "271") (name "DDR_D13$45") (class "Default")
      (node (ref "U$101") (pin "A2") (pinfunction "DQ13_A2") (pintype "bidirectional"))
      (node (ref "U$72") (pin "L3") (pinfunction "DDR_D13_L3") (pintype "bidirectional"))
    )
    (net (code "272") (name "DDR_D14$45") (class "Default")
      (node (ref "U$101") (pin "B8") (pinfunction "DQ14_B8") (pintype "bidirectional"))
      (node (ref "U$72") (pin "L4") (pinfunction "DDR_D14_L4") (pintype "bidirectional"))
    )
    (net (code "273") (name "DDR_D15$45") (class "Default")
      (node (ref "U$101") (pin "A3") (pinfunction "DQ15_A3") (pintype "bidirectional"))
      (node (ref "U$72") (pin "M1") (pinfunction "DDR_D15_M1") (pintype "bidirectional"))
    )
    (net (code "274") (name "DDR_DQM0$45") (class "Default")
      (node (ref "U$101") (pin "E7") (pinfunction "LDM_E7") (pintype "input"))
      (node (ref "U$72") (pin "M2") (pinfunction "DDR_DQM0_M2") (pintype "output"))
    )
    (net (code "275") (name "DDR_DQM1$45") (class "Default")
      (node (ref "U$101") (pin "D3") (pinfunction "UDM_D3") (pintype "bidirectional"))
      (node (ref "U$72") (pin "J2") (pinfunction "DDR_DQM1_J2") (pintype "output"))
    )
    (net (code "276") (name "DDR_DQS0_N$45") (class "Default")
      (node (ref "U$101") (pin "G3") (pinfunction "~{LDQS}_G3") (pintype "bidirectional"))
      (node (ref "U$72") (pin "P2") (pinfunction "DDR_DQSN0_P2") (pintype "bidirectional"))
    )
    (net (code "277") (name "DDR_DQS0_P$45") (class "Default")
      (node (ref "U$101") (pin "F3") (pinfunction "LDQS_F3") (pintype "input"))
      (node (ref "U$72") (pin "P1") (pinfunction "DDR_DQS0_P1") (pintype "bidirectional"))
    )
    (net (code "278") (name "DDR_DQS1_N$45") (class "Default")
      (node (ref "U$101") (pin "B7") (pinfunction "~{UDQS}_B7") (pintype "bidirectional"))
      (node (ref "U$72") (pin "L2") (pinfunction "DDR_DQSN1_L2") (pintype "bidirectional"))
    )
    (net (code "279") (name "DDR_DQS1_P$45") (class "Default")
      (node (ref "U$101") (pin "C7") (pinfunction "UDQS_C7") (pintype "bidirectional"))
      (node (ref "U$72") (pin "L1") (pinfunction "DDR_DQS1_L1") (pintype "bidirectional"))
    )
    (net (code "280") (name "DDR_ODT$45") (class "Default")
      (node (ref "U$101") (pin "K1") (pinfunction "ODT_K1") (pintype "input"))
      (node (ref "U$72") (pin "G1") (pinfunction "DDR_ODT_G1") (pintype "output"))
    )
    (net (code "281") (name "DDR_RASN$45") (class "Default")
      (node (ref "U$101") (pin "J3") (pinfunction "~{RAS}_J3") (pintype "input"))
      (node (ref "U$72") (pin "G4") (pinfunction "DDR_RASN_G4") (pintype "output"))
    )
    (net (code "282") (name "DDR_VREF$45") (class "Default")
      (node (ref "C256") (pin "1") (pinfunction "1_1") (pintype "passive"))
      (node (ref "C257") (pin "1") (pinfunction "1_1") (pintype "passive"))
      (node (ref "R131") (pin "2") (pinfunction "2_2") (pintype "passive"))
      (node (ref "R132") (pin "1") (pinfunction "1_1") (pintype "passive"))
      (node (ref "U$101") (pin "H1") (pinfunction "VREF_DQ_H1") (pintype "power_in"))
      (node (ref "U$101") (pin "M8") (pinfunction "VREF_CA_M8") (pintype "power_in"))
      (node (ref "U$72") (pin "J4") (pinfunction "DDR_VREF_J4") (pintype "bidirectional"))
    )
    (net (code "283") (name "DDR_VTP$45") (class "Default")
      (node (ref "R129") (pin "2") (pinfunction "2_2") (pintype "passive"))
      (node (ref "U$72") (pin "J3") (pinfunction "DDR_VTP_J3") (pintype "input"))
    )
    (net (code "284") (name "DDR_WEN$45") (class "Default")
      (node (ref "U$101") (pin "L3") (pinfunction "~{WE}_L3") (pintype "input"))
      (node (ref "U$72") (pin "B2") (pinfunction "DDR_WEN_B2") (pintype "output"))
    )
    (net (code "285") (name "DE$44") (class "Default")
      (node (ref "IC4") (pin "2") (pinfunction "DE_2") (pintype "bidirectional"))
      (node (ref "R115") (pin "2") (pinfunction "2_2") (pintype "passive"))
    )
    (net (code "286") (name "DKEN$44") (class "Default")
      (node (ref "IC4") (pin "35") (pinfunction "DKEN_35") (pintype "bidirectional"))
      (node (ref "R105") (pin "1") (pinfunction "1_1") (pintype "passive"))
      (node (ref "R114") (pin "1") (pinfunction "1_1") (pintype "passive"))
    )
    (net (code "287") (name "DM$30") (class "Default")
      (node (ref "D13") (pin "P2") (pinfunction "P2_P2") (pintype "passive"))
      (node (ref "J10") (pin "P2") (pinfunction "D-_P2") (pintype "bidirectional"))
      (node (ref "L5") (pin "1") (pinfunction "1_1") (pintype "passive"))
    )
    (net (code "288") (name "DM$38") (class "Default")
      (node (ref "D17") (pin "P2") (pinfunction "P2_P2") (pintype "passive"))
      (node (ref "J14") (pin "P2") (pinfunction "D-_P2") (pintype "bidirectional"))
      (node (ref "L6") (pin "1") (pinfunction "1_1") (pintype "passive"))
    )
    (net (code "289") (name "DP$30") (class "Default")
      (node (ref "D14") (pin "P2") (pinfunction "P2_P2") (pintype "passive"))
      (node (ref "J10") (pin "P3") (pinfunction "D+_P3") (pintype "bidirectional"))
      (node (ref "L5") (pin "4") (pinfunction "4_4") (pintype "passive"))
    )
    (net (code "290") (name "DP$38") (class "Default")
      (node (ref "D18") (pin "P2") (pinfunction "P2_P2") (pintype "passive"))
      (node (ref "J14") (pin "P3") (pinfunction "D+_P3") (pintype "bidirectional"))
      (node (ref "L6") (pin "4") (pinfunction "4_4") (pintype "passive"))
    )
    (net (code "291") (name "DVI_BSEL$44") (class "Default")
      (node (ref "IC4") (pin "15") (pinfunction "BSEL/SCL_15") (pintype "bidirectional"))
      (node (ref "R98") (pin "2") (pinfunction "2_2") (pintype "passive"))
    )
    (net (code "292") (name "DVI_DSEL$44") (class "Default")
      (node (ref "IC4") (pin "14") (pinfunction "DSEL/SDA_14") (pintype "bidirectional"))
      (node (ref "R101") (pin "2") (pinfunction "2_2") (pintype "passive"))
    )
    (net (code "293") (name "DVI_HTPLG$44") (class "Default")
      (node (ref "IC4") (pin "9") (pinfunction "HTPLG_9") (pintype "bidirectional"))
      (node (ref "R96") (pin "2") (pinfunction "2_2") (pintype "passive"))
    )
    (net (code "294") (name "DVI_VREF$44") (class "Default")
      (node (ref "IC4") (pin "3") (pinfunction "VREF_3") (pintype "bidirectional"))
      (node (ref "R100") (pin "1") (pinfunction "1_1") (pintype "passive"))
      (node (ref "R99") (pin "1") (pinfunction "1_1") (pintype "passive"))
    )
    (net (code "295") (name "DVI_~{RESET}$44") (class "Default")
      (node (ref "IC4") (pin "13") (pinfunction "ISEL/~{RESET}_13") (pintype "bidirectional"))
      (node (ref "R97") (pin "2") (pinfunction "2_2") (pintype "passive"))
    )
    (net (code "296") (name "EE_A0$45") (class "Default")
      (node (ref "R340") (pin "2") (pinfunction "2_2") (pintype "passive"))
      (node (ref "U34") (pin "1") (pinfunction "A0_1") (pintype "input"))
    )
    (net (code "297") (name "EE_A1$45") (class "Default")
      (node (ref "R342") (pin "2") (pinfunction "2_2") (pintype "passive"))
      (node (ref "U34") (pin "2") (pinfunction "A1_2") (pintype "input"))
    )
    (net (code "298") (name "EE_A2$45") (class "Default")
      (node (ref "R344") (pin "2") (pinfunction "2_2") (pintype "passive"))
      (node (ref "U34") (pin "3") (pinfunction "A2_3") (pintype "input"))
    )
    (net (code "299") (name "FB_3.3$18") (class "Default")
      (node (ref "C60") (pin "2") (pinfunction "2_2") (pintype "passive"))
      (node (ref "IC2") (pin "10") (pinfunction "FB_10") (pintype "output"))
      (node (ref "R39") (pin "1") (pinfunction "1_1") (pintype "passive"))
      (node (ref "R40") (pin "2") (pinfunction "2_2") (pintype "passive"))
    )
    (net (code "300") (name "GND") (class "Default")
      (node (ref "C1") (pin "2") (pinfunction "2_2") (pintype "passive"))
      (node (ref "C10") (pin "2") (pinfunction "2_2") (pintype "passive"))
      (node (ref "C100") (pin "2") (pinfunction "2_2") (pintype "passive"))
      (node (ref "C101") (pin "2") (pinfunction "2_2") (pintype "passive"))
      (node (ref "C102") (pin "2") (pinfunction "2_2") (pintype "passive"))
      (node (ref "C103") (pin "2") (pinfunction "2_2") (pintype "passive"))
      (node (ref "C104") (pin "2") (pinfunction "2_2") (pintype "passive"))
      (node (ref "C106") (pin "2") (pinfunction "2_2") (pintype "passive"))
      (node (ref "C107") (pin "-") (pinfunction "2_-") (pintype "passive"))
      (node (ref "C108") (pin "2") (pinfunction "2_2") (pintype "passive"))
      (node (ref "C109") (pin "2") (pinfunction "2_2") (pintype "passive"))
      (node (ref "C11") (pin "-") (pinfunction "2_-") (pintype "passive"))
      (node (ref "C112") (pin "2") (pinfunction "2_2") (pintype "passive"))
      (node (ref "C113") (pin "2") (pinfunction "2_2") (pintype "passive"))
      (node (ref "C114") (pin "2") (pinfunction "2_2") (pintype "passive"))
      (node (ref "C115") (pin "2") (pinfunction "2_2") (pintype "passive"))
      (node (ref "C116") (pin "2") (pinfunction "2_2") (pintype "passive"))
      (node (ref "C117") (pin "2") (pinfunction "2_2") (pintype "passive"))
      (node (ref "C118") (pin "2") (pinfunction "2_2") (pintype "passive"))
      (node (ref "C119") (pin "2") (pinfunction "2_2") (pintype "passive"))
      (node (ref "C12") (pin "2") (pinfunction "2_2") (pintype "passive"))
      (node (ref "C120") (pin "2") (pinfunction "2_2") (pintype "passive"))
      (node (ref "C121") (pin "2") (pinfunction "2_2") (pintype "passive"))
      (node (ref "C122") (pin "2") (pinfunction "2_2") (pintype "passive"))
      (node (ref "C123") (pin "2") (pinfunction "2_2") (pintype "passive"))
      (node (ref "C124") (pin "2") (pinfunction "2_2") (pintype "passive"))
      (node (ref "C125") (pin "2") (pinfunction "2_2") (pintype "passive"))
      (node (ref "C126") (pin "2") (pinfunction "2_2") (pintype "passive"))
      (node (ref "C127") (pin "2") (pinfunction "2_2") (pintype "passive"))
      (node (ref "C128") (pin "2") (pinfunction "2_2") (pintype "passive"))
      (node (ref "C129") (pin "2") (pinfunction "2_2") (pintype "passive"))
      (node (ref "C13") (pin "2") (pinfunction "2_2") (pintype "passive"))
      (node (ref "C130") (pin "2") (pinfunction "2_2") (pintype "passive"))
      (node (ref "C131") (pin "2") (pinfunction "2_2") (pintype "passive"))
      (node (ref "C132") (pin "2") (pinfunction "2_2") (pintype "passive"))
      (node (ref "C135") (pin "2") (pinfunction "2_2") (pintype "passive"))
      (node (ref "C136") (pin "2") (pinfunction "2_2") (pintype "passive"))
      (node (ref "C137") (pin "2") (pinfunction "2_2") (pintype "passive"))
      (node (ref "C138") (pin "2") (pinfunction "2_2") (pintype "passive"))
      (node (ref "C139") (pin "2") (pinfunction "2_2") (pintype "passive"))
      (node (ref "C140") (pin "2") (pinfunction "2_2") (pintype "passive"))
      (node (ref "C141") (pin "2") (pinfunction "2_2") (pintype "passive"))
      (node (ref "C142") (pin "2") (pinfunction "2_2") (pintype "passive"))
      (node (ref "C143") (pin "2") (pinfunction "2_2") (pintype "passive"))
      (node (ref "C144") (pin "2") (pinfunction "2_2") (pintype "passive"))
      (node (ref "C145") (pin "2") (pinfunction "2_2") (pintype "passive"))
      (node (ref "C146") (pin "2") (pinfunction "2_2") (pintype "passive"))
      (node (ref "C147") (pin "2") (pinfunction "2_2") (pintype "passive"))
      (node (ref "C148") (pin "2") (pinfunction "2_2") (pintype "passive"))
      (node (ref "C149") (pin "2") (pinfunction "2_2") (pintype "passive"))
      (node (ref "C150") (pin "2") (pinfunction "2_2") (pintype "passive"))
      (node (ref "C151") (pin "2") (pinfunction "2_2") (pintype "passive"))
      (node (ref "C152") (pin "2") (pinfunction "2_2") (pintype "passive"))
      (node (ref "C153") (pin "2") (pinfunction "2_2") (pintype "passive"))
      (node (ref "C154") (pin "2") (pinfunction "2_2") (pintype "passive"))
      (node (ref "C155") (pin "2") (pinfunction "2_2") (pintype "passive"))
      (node (ref "C156") (pin "2") (pinfunction "2_2") (pintype "passive"))
      (node (ref "C157") (pin "2") (pinfunction "2_2") (pintype "passive"))
      (node (ref "C158") (pin "2") (pinfunction "2_2") (pintype "passive"))
      (node (ref "C159") (pin "2") (pinfunction "2_2") (pintype "passive"))
      (node (ref "C16") (pin "2") (pinfunction "2_2") (pintype "passive"))
      (node (ref "C160") (pin "2") (pinfunction "2_2") (pintype "passive"))
      (node (ref "C161") (pin "2") (pinfunction "2_2") (pintype "passive"))
      (node (ref "C162") (pin "2") (pinfunction "2_2") (pintype "passive"))
      (node (ref "C163") (pin "2") (pinfunction "2_2") (pintype "passive"))
      (node (ref "C164") (pin "2") (pinfunction "2_2") (pintype "passive"))
      (node (ref "C165") (pin "2") (pinfunction "2_2") (pintype "passive"))
      (node (ref "C166") (pin "2") (pinfunction "2_2") (pintype "passive"))
      (node (ref "C167") (pin "2") (pinfunction "2_2") (pintype "passive"))
      (node (ref "C17") (pin "2") (pinfunction "2_2") (pintype "passive"))
      (node (ref "C172") (pin "2") (pinfunction "2_2") (pintype "passive"))
      (node (ref "C173") (pin "2") (pinfunction "2_2") (pintype "passive"))
      (node (ref "C174") (pin "2") (pinfunction "2_2") (pintype "passive"))
      (node (ref "C175") (pin "2") (pinfunction "2_2") (pintype "passive"))
      (node (ref "C176") (pin "2") (pinfunction "2_2") (pintype "passive"))
      (node (ref "C177") (pin "2") (pinfunction "2_2") (pintype "passive"))
      (node (ref "C178") (pin "2") (pinfunction "2_2") (pintype "passive"))
      (node (ref "C179") (pin "2") (pinfunction "2_2") (pintype "passive"))
      (node (ref "C18") (pin "2") (pinfunction "2_2") (pintype "passive"))
      (node (ref "C180") (pin "2") (pinfunction "2_2") (pintype "passive"))
      (node (ref "C181") (pin "2") (pinfunction "2_2") (pintype "passive"))
      (node (ref "C182") (pin "2") (pinfunction "2_2") (pintype "passive"))
      (node (ref "C183") (pin "2") (pinfunction "2_2") (pintype "passive"))
      (node (ref "C184") (pin "2") (pinfunction "2_2") (pintype "passive"))
      (node (ref "C185") (pin "2") (pinfunction "2_2") (pintype "passive"))
      (node (ref "C186") (pin "2") (pinfunction "2_2") (pintype "passive"))
      (node (ref "C187") (pin "2") (pinfunction "2_2") (pintype "passive"))
      (node (ref "C188") (pin "2") (pinfunction "2_2") (pintype "passive"))
      (node (ref "C189") (pin "2") (pinfunction "2_2") (pintype "passive"))
      (node (ref "C19") (pin "2") (pinfunction "2_2") (pintype "passive"))
      (node (ref "C190") (pin "2") (pinfunction "2_2") (pintype "passive"))
      (node (ref "C191") (pin "2") (pinfunction "2_2") (pintype "passive"))
      (node (ref "C192") (pin "2") (pinfunction "2_2") (pintype "passive"))
      (node (ref "C193") (pin "2") (pinfunction "2_2") (pintype "passive"))
      (node (ref "C194") (pin "2") (pinfunction "2_2") (pintype "passive"))
      (node (ref "C195") (pin "2") (pinfunction "2_2") (pintype "passive"))
      (node (ref "C196") (pin "2") (pinfunction "2_2") (pintype "passive"))
      (node (ref "C197") (pin "2") (pinfunction "2_2") (pintype "passive"))
      (node (ref "C198") (pin "2") (pinfunction "2_2") (pintype "passive"))
      (node (ref "C199") (pin "2") (pinfunction "2_2") (pintype "passive"))
      (node (ref "C2") (pin "2") (pinfunction "2_2") (pintype "passive"))
      (node (ref "C20") (pin "2") (pinfunction "2_2") (pintype "passive"))
      (node (ref "C200") (pin "2") (pinfunction "2_2") (pintype "passive"))
      (node (ref "C201") (pin "2") (pinfunction "2_2") (pintype "passive"))
      (node (ref "C202") (pin "2") (pinfunction "2_2") (pintype "passive"))
      (node (ref "C203") (pin "2") (pinfunction "2_2") (pintype "passive"))
      (node (ref "C204") (pin "2") (pinfunction "2_2") (pintype "passive"))
      (node (ref "C205") (pin "2") (pinfunction "2_2") (pintype "passive"))
      (node (ref "C206") (pin "2") (pinfunction "2_2") (pintype "passive"))
      (node (ref "C207") (pin "2") (pinfunction "2_2") (pintype "passive"))
      (node (ref "C208") (pin "2") (pinfunction "2_2") (pintype "passive"))
      (node (ref "C209") (pin "2") (pinfunction "2_2") (pintype "passive"))
      (node (ref "C21") (pin "2") (pinfunction "2_2") (pintype "passive"))
      (node (ref "C210") (pin "2") (pinfunction "2_2") (pintype "passive"))
      (node (ref "C211") (pin "2") (pinfunction "2_2") (pintype "passive"))
      (node (ref "C212") (pin "2") (pinfunction "2_2") (pintype "passive"))
      (node (ref "C213") (pin "2") (pinfunction "2_2") (pintype "passive"))
      (node (ref "C214") (pin "2") (pinfunction "2_2") (pintype "passive"))
      (node (ref "C215") (pin "2") (pinfunction "2_2") (pintype "passive"))
      (node (ref "C216") (pin "2") (pinfunction "2_2") (pintype "passive"))
      (node (ref "C217") (pin "2") (pinfunction "2_2") (pintype "passive"))
      (node (ref "C218") (pin "2") (pinfunction "2_2") (pintype "passive"))
      (node (ref "C219") (pin "2") (pinfunction "2_2") (pintype "passive"))
      (node (ref "C22") (pin "2") (pinfunction "2_2") (pintype "passive"))
      (node (ref "C220") (pin "2") (pinfunction "2_2") (pintype "passive"))
      (node (ref "C221") (pin "2") (pinfunction "2_2") (pintype "passive"))
      (node (ref "C222") (pin "2") (pinfunction "2_2") (pintype "passive"))
      (node (ref "C223") (pin "2") (pinfunction "2_2") (pintype "passive"))
      (node (ref "C224") (pin "2") (pinfunction "2_2") (pintype "passive"))
      (node (ref "C225") (pin "2") (pinfunction "2_2") (pintype "passive"))
      (node (ref "C226") (pin "2") (pinfunction "2_2") (pintype "passive"))
      (node (ref "C227") (pin "2") (pinfunction "2_2") (pintype "passive"))
      (node (ref "C228") (pin "2") (pinfunction "2_2") (pintype "passive"))
      (node (ref "C229") (pin "2") (pinfunction "2_2") (pintype "passive"))
      (node (ref "C23") (pin "2") (pinfunction "2_2") (pintype "passive"))
      (node (ref "C230") (pin "2") (pinfunction "2_2") (pintype "passive"))
      (node (ref "C231") (pin "2") (pinfunction "2_2") (pintype "passive"))
      (node (ref "C232") (pin "2") (pinfunction "2_2") (pintype "passive"))
      (node (ref "C233") (pin "2") (pinfunction "2_2") (pintype "passive"))
      (node (ref "C234") (pin "2") (pinfunction "2_2") (pintype "passive"))
      (node (ref "C235") (pin "2") (pinfunction "2_2") (pintype "passive"))
      (node (ref "C236") (pin "2") (pinfunction "2_2") (pintype "passive"))
      (node (ref "C237") (pin "2") (pinfunction "2_2") (pintype "passive"))
      (node (ref "C238") (pin "2") (pinfunction "2_2") (pintype "passive"))
      (node (ref "C239") (pin "2") (pinfunction "2_2") (pintype "passive"))
      (node (ref "C24") (pin "2") (pinfunction "2_2") (pintype "passive"))
      (node (ref "C240") (pin "2") (pinfunction "2_2") (pintype "passive"))
      (node (ref "C241") (pin "2") (pinfunction "2_2") (pintype "passive"))
      (node (ref "C242") (pin "2") (pinfunction "2_2") (pintype "passive"))
      (node (ref "C243") (pin "2") (pinfunction "2_2") (pintype "passive"))
      (node (ref "C244") (pin "2") (pinfunction "2_2") (pintype "passive"))
      (node (ref "C245") (pin "2") (pinfunction "2_2") (pintype "passive"))
      (node (ref "C246") (pin "2") (pinfunction "2_2") (pintype "passive"))
      (node (ref "C247") (pin "2") (pinfunction "2_2") (pintype "passive"))
      (node (ref "C248") (pin "2") (pinfunction "2_2") (pintype "passive"))
      (node (ref "C249") (pin "2") (pinfunction "2_2") (pintype "passive"))
      (node (ref "C25") (pin "2") (pinfunction "2_2") (pintype "passive"))
      (node (ref "C250") (pin "2") (pinfunction "2_2") (pintype "passive"))
      (node (ref "C251") (pin "2") (pinfunction "2_2") (pintype "passive"))
      (node (ref "C252") (pin "2") (pinfunction "2_2") (pintype "passive"))
      (node (ref "C253") (pin "2") (pinfunction "2_2") (pintype "passive"))
      (node (ref "C254") (pin "2") (pinfunction "2_2") (pintype "passive"))
      (node (ref "C255") (pin "2") (pinfunction "2_2") (pintype "passive"))
      (node (ref "C256") (pin "2") (pinfunction "2_2") (pintype "passive"))
      (node (ref "C257") (pin "2") (pinfunction "2_2") (pintype "passive"))
      (node (ref "C258") (pin "2") (pinfunction "2_2") (pintype "passive"))
      (node (ref "C259") (pin "2") (pinfunction "2_2") (pintype "passive"))
      (node (ref "C26") (pin "2") (pinfunction "2_2") (pintype "passive"))
      (node (ref "C260") (pin "2") (pinfunction "2_2") (pintype "passive"))
      (node (ref "C261") (pin "2") (pinfunction "2_2") (pintype "passive"))
      (node (ref "C262") (pin "2") (pinfunction "2_2") (pintype "passive"))
      (node (ref "C27") (pin "2") (pinfunction "2_2") (pintype "passive"))
      (node (ref "C28") (pin "2") (pinfunction "2_2") (pintype "passive"))
      (node (ref "C29") (pin "2") (pinfunction "2_2") (pintype "passive"))
      (node (ref "C3") (pin "2") (pinfunction "2_2") (pintype "passive"))
      (node (ref "C30") (pin "2") (pinfunction "2_2") (pintype "passive"))
      (node (ref "C31") (pin "2") (pinfunction "2_2") (pintype "passive"))
      (node (ref "C32") (pin "2") (pinfunction "2_2") (pintype "passive"))
      (node (ref "C33") (pin "2") (pinfunction "2_2") (pintype "passive"))
      (node (ref "C34") (pin "2") (pinfunction "2_2") (pintype "passive"))
      (node (ref "C35") (pin "2") (pinfunction "2_2") (pintype "passive"))
      (node (ref "C36") (pin "2") (pinfunction "2_2") (pintype "passive"))
      (node (ref "C37") (pin "2") (pinfunction "2_2") (pintype "passive"))
      (node (ref "C38") (pin "2") (pinfunction "2_2") (pintype "passive"))
      (node (ref "C39") (pin "2") (pinfunction "2_2") (pintype "passive"))
      (node (ref "C4") (pin "2") (pinfunction "2_2") (pintype "passive"))
      (node (ref "C40") (pin "2") (pinfunction "2_2") (pintype "passive"))
      (node (ref "C41") (pin "2") (pinfunction "2_2") (pintype "passive"))
      (node (ref "C42") (pin "2") (pinfunction "2_2") (pintype "passive"))
      (node (ref "C43") (pin "2") (pinfunction "2_2") (pintype "passive"))
      (node (ref "C44") (pin "2") (pinfunction "2_2") (pintype "passive"))
      (node (ref "C46") (pin "2") (pinfunction "2_2") (pintype "passive"))
      (node (ref "C48") (pin "2") (pinfunction "2_2") (pintype "passive"))
      (node (ref "C49") (pin "2") (pinfunction "2_2") (pintype "passive"))
      (node (ref "C5") (pin "2") (pinfunction "2_2") (pintype "passive"))
      (node (ref "C50") (pin "2") (pinfunction "2_2") (pintype "passive"))
      (node (ref "C51") (pin "2") (pinfunction "2_2") (pintype "passive"))
      (node (ref "C52") (pin "2") (pinfunction "2_2") (pintype "passive"))
      (node (ref "C53") (pin "2") (pinfunction "2_2") (pintype "passive"))
      (node (ref "C55") (pin "2") (pinfunction "2_2") (pintype "passive"))
      (node (ref "C56") (pin "2") (pinfunction "2_2") (pintype "passive"))
      (node (ref "C57") (pin "2") (pinfunction "2_2") (pintype "passive"))
      (node (ref "C58") (pin "2") (pinfunction "2_2") (pintype "passive"))
      (node (ref "C59") (pin "2") (pinfunction "2_2") (pintype "passive"))
      (node (ref "C6") (pin "2") (pinfunction "2_2") (pintype "passive"))
      (node (ref "C61") (pin "2") (pinfunction "2_2") (pintype "passive"))
      (node (ref "C62") (pin "2") (pinfunction "2_2") (pintype "passive"))
      (node (ref "C63") (pin "2") (pinfunction "2_2") (pintype "passive"))
      (node (ref "C64") (pin "2") (pinfunction "2_2") (pintype "passive"))
      (node (ref "C65") (pin "2") (pinfunction "2_2") (pintype "passive"))
      (node (ref "C69") (pin "2") (pinfunction "2_2") (pintype "passive"))
      (node (ref "C7") (pin "2") (pinfunction "2_2") (pintype "passive"))
      (node (ref "C70") (pin "2") (pinfunction "2_2") (pintype "passive"))
      (node (ref "C71") (pin "2") (pinfunction "2_2") (pintype "passive"))
      (node (ref "C72") (pin "2") (pinfunction "2_2") (pintype "passive"))
      (node (ref "C73") (pin "2") (pinfunction "2_2") (pintype "passive"))
      (node (ref "C74") (pin "2") (pinfunction "2_2") (pintype "passive"))
      (node (ref "C75") (pin "2") (pinfunction "2_2") (pintype "passive"))
      (node (ref "C76") (pin "2") (pinfunction "2_2") (pintype "passive"))
      (node (ref "C77") (pin "2") (pinfunction "2_2") (pintype "passive"))
      (node (ref "C78") (pin "2") (pinfunction "2_2") (pintype "passive"))
      (node (ref "C79") (pin "2") (pinfunction "2_2") (pintype "passive"))
      (node (ref "C8") (pin "2") (pinfunction "2_2") (pintype "passive"))
      (node (ref "C80") (pin "2") (pinfunction "2_2") (pintype "passive"))
      (node (ref "C81") (pin "2") (pinfunction "2_2") (pintype "passive"))
      (node (ref "C82") (pin "2") (pinfunction "2_2") (pintype "passive"))
      (node (ref "C83") (pin "2") (pinfunction "2_2") (pintype "passive"))
      (node (ref "C84") (pin "2") (pinfunction "2_2") (pintype "passive"))
      (node (ref "C85") (pin "2") (pinfunction "2_2") (pintype "passive"))
      (node (ref "C86") (pin "2") (pinfunction "2_2") (pintype "passive"))
      (node (ref "C87") (pin "2") (pinfunction "2_2") (pintype "passive"))
      (node (ref "C89") (pin "2") (pinfunction "2_2") (pintype "passive"))
      (node (ref "C9") (pin "2") (pinfunction "2_2") (pintype "passive"))
      (node (ref "C90") (pin "-") (pinfunction "2_-") (pintype "passive"))
      (node (ref "C91") (pin "2") (pinfunction "2_2") (pintype "passive"))
      (node (ref "C92") (pin "2") (pinfunction "2_2") (pintype "passive"))
      (node (ref "C93") (pin "2") (pinfunction "2_2") (pintype "passive"))
      (node (ref "C94") (pin "2") (pinfunction "2_2") (pintype "passive"))
      (node (ref "C95") (pin "2") (pinfunction "2_2") (pintype "passive"))
      (node (ref "C96") (pin "2") (pinfunction "2_2") (pintype "passive"))
      (node (ref "C97") (pin "2") (pinfunction "2_2") (pintype "passive"))
      (node (ref "C98") (pin "2") (pinfunction "2_2") (pintype "passive"))
      (node (ref "C99") (pin "2") (pinfunction "2_2") (pintype "passive"))
      (node (ref "CONN1") (pin "2") (pinfunction "2_2") (pintype "power_in"))
      (node (ref "CONN1") (pin "3") (pinfunction "3_3") (pintype "power_in"))
      (node (ref "D1") (pin "C") (pinfunction "C_C") (pintype "passive"))
      (node (ref "D10") (pin "A") (pinfunction "A_A") (pintype "passive"))
      (node (ref "D16") (pin "P2") (pinfunction "P2_P2") (pintype "passive"))
      (node (ref "D20") (pin "P2") (pinfunction "P2_P2") (pintype "passive"))
      (node (ref "FB1") (pin "1") (pinfunction "1_1") (pintype "passive"))
      (node (ref "FB11") (pin "2") (pinfunction "2_2") (pintype "passive"))
      (node (ref "GND") (pin "TP") (pinfunction "TP_TP") (pintype "bidirectional"))
      (node (ref "IC1") (pin "10") (pinfunction "VS2_10") (pintype "input"))
      (node (ref "IC1") (pin "12") (pinfunction "VS0_12") (pintype "input"))
      (node (ref "IC1") (pin "2") (pinfunction "PGND_2") (pintype "power_in"))
      (node (ref "IC1") (pin "6") (pinfunction "AGND_6") (pintype "power_in"))
      (node (ref "IC2") (pin "1") (pinfunction "PGND_1") (pintype "power_in"))
      (node (ref "IC2") (pin "11") (pinfunction "GND_11") (pintype "power_in"))
      (node (ref "IC2") (pin "12") (pinfunction "GND_12") (pintype "power_in"))
      (node (ref "IC2") (pin "16") (pinfunction "PGND_16") (pintype "power_in"))
      (node (ref "IC2") (pin "5") (pinfunction "SYNC_5") (pintype "input"))
      (node (ref "IC2") (pin "6") (pinfunction "LBO_6") (pintype "passive"))
      (node (ref "IC2") (pin "7") (pinfunction "LBI_7") (pintype "input"))
      (node (ref "IC2") (pin "9") (pinfunction "GND_9") (pintype "power_in"))
      (node (ref "IC2") (pin "P$1") (pinfunction "GND_P$1") (pintype "power_in"))
      (node (ref "IC3") (pin "10") (pinfunction "VSS_5_10") (pintype "power_in"))
      (node (ref "IC3") (pin "27") (pinfunction "VSS_4_27") (pintype "power_in"))
      (node (ref "IC3") (pin "74") (pinfunction "VSS_2_74") (pintype "power_in"))
      (node (ref "IC3") (pin "99") (pinfunction "VSS_3_99") (pintype "power_in"))
      (node (ref "IC4") (pin "16") (pinfunction "VSS_16") (pintype "power_in"))
      (node (ref "IC4") (pin "17") (pinfunction "VSS_17") (pintype "power_in"))
      (node (ref "IC4") (pin "20") (pinfunction "VSS_20") (pintype "power_in"))
      (node (ref "IC4") (pin "26") (pinfunction "VSS_26") (pintype "power_in"))
      (node (ref "IC4") (pin "32") (pinfunction "VSS_32") (pintype "power_in"))
      (node (ref "IC4") (pin "34") (pinfunction "RSVD2_34") (pintype "bidirectional"))
      (node (ref "IC4") (pin "48") (pinfunction "VSS_48") (pintype "power_in"))
      (node (ref "IC4") (pin "56") (pinfunction "IDCK-_56") (pintype "bidirectional"))
      (node (ref "IC4") (pin "64") (pinfunction "VSS_64") (pintype "power_in"))
      (node (ref "IC4") (pin "TP") (pinfunction "TP_TP") (pintype "power_in"))
      (node (ref "J1") (pin "2") (pinfunction "2_2") (pintype "bidirectional"))
      (node (ref "J10") (pin "P5") (pinfunction "GND_P5") (pintype "bidirectional"))
      (node (ref "J11") (pin "2") (pinfunction "2_2") (pintype "bidirectional"))
      (node (ref "J12") (pin "1") (pinfunction "1_1") (pintype "passive"))
      (node (ref "J12") (pin "11") (pinfunction "11_11") (pintype "passive"))
      (node (ref "J12") (pin "13") (pinfunction "13_13") (pintype "passive"))
      (node (ref "J12") (pin "15") (pinfunction "15_15") (pintype "passive"))
      (node (ref "J12") (pin "17") (pinfunction "17_17") (pintype "passive"))
      (node (ref "J12") (pin "19") (pinfunction "19_19") (pintype "passive"))
      (node (ref "J12") (pin "3") (pinfunction "3_3") (pintype "passive"))
      (node (ref "J12") (pin "5") (pinfunction "5_5") (pintype "passive"))
      (node (ref "J12") (pin "7") (pinfunction "7_7") (pintype "passive"))
      (node (ref "J12") (pin "9") (pinfunction "9_9") (pintype "passive"))
      (node (ref "J14") (pin "P5") (pinfunction "GND_P5") (pintype "bidirectional"))
      (node (ref "J15") (pin "10") (pinfunction "8_10") (pintype "passive"))
      (node (ref "J15") (pin "13") (pinfunction "11_13") (pintype "passive"))
      (node (ref "J15") (pin "16") (pinfunction "17_16") (pintype "passive"))
      (node (ref "J15") (pin "4") (pinfunction "2_4") (pintype "passive"))
      (node (ref "J15") (pin "7") (pinfunction "5_7") (pintype "passive"))
      (node (ref "J2") (pin "A1") (pinfunction "A1_A1") (pintype "bidirectional"))
      (node (ref "J2") (pin "B1") (pinfunction "B1_B1") (pintype "bidirectional"))
      (node (ref "J3") (pin "-") (pinfunction "-_-") (pintype "passive"))
      (node (ref "J6") (pin "2") (pinfunction "2_2") (pintype "bidirectional"))
      (node (ref "J7") (pin "A2") (pinfunction "A2_A2") (pintype "bidirectional"))
      (node (ref "J8") (pin "2") (pinfunction "2_2") (pintype "bidirectional"))
      (node (ref "J9") (pin "A1") (pinfunction "A1_A1") (pintype "bidirectional"))
      (node (ref "J9") (pin "B1") (pinfunction "B1_B1") (pintype "bidirectional"))
      (node (ref "JTAG") (pin "3") (pinfunction "S_3") (pintype "passive"))
      (node (ref "JTAG") (pin "5") (pinfunction "S_5") (pintype "passive"))
      (node (ref "JTAG") (pin "9") (pinfunction "S_9") (pintype "passive"))
      (node (ref "Q2") (pin "2") (pinfunction "S_2") (pintype "passive"))
      (node (ref "Q3") (pin "2") (pinfunction "S_2") (pintype "passive"))
      (node (ref "Q4") (pin "2") (pinfunction "S_2") (pintype "passive"))
      (node (ref "Q5") (pin "2") (pinfunction "GND_2") (pintype "power_in"))
      (node (ref "R100") (pin "2") (pinfunction "2_2") (pintype "passive"))
      (node (ref "R101") (pin "1") (pinfunction "1_1") (pintype "passive"))
      (node (ref "R114") (pin "2") (pinfunction "2_2") (pintype "passive"))
      (node (ref "R120") (pin "1") (pinfunction "1_1") (pintype "passive"))
      (node (ref "R121") (pin "1") (pinfunction "1_1") (pintype "passive"))
      (node (ref "R129") (pin "1") (pinfunction "1_1") (pintype "passive"))
      (node (ref "R132") (pin "2") (pinfunction "2_2") (pintype "passive"))
      (node (ref "R133") (pin "2") (pinfunction "2_2") (pintype "passive"))
      (node (ref "R135") (pin "1") (pinfunction "1_1") (pintype "passive"))
      (node (ref "R16") (pin "1") (pinfunction "1_1") (pintype "passive"))
      (node (ref "R2") (pin "1") (pinfunction "1_1") (pintype "passive"))
      (node (ref "R24") (pin "2") (pinfunction "2_2") (pintype "passive"))
      (node (ref "R27") (pin "1") (pinfunction "1_1") (pintype "passive"))
      (node (ref "R28") (pin "1") (pinfunction "1_1") (pintype "passive"))
      (node (ref "R30") (pin "1") (pinfunction "1_1") (pintype "passive"))
      (node (ref "R33") (pin "1") (pinfunction "1_1") (pintype "passive"))
      (node (ref "R340") (pin "1") (pinfunction "1_1") (pintype "passive"))
      (node (ref "R342") (pin "1") (pinfunction "1_1") (pintype "passive"))
      (node (ref "R344") (pin "1") (pinfunction "1_1") (pintype "passive"))
      (node (ref "R40") (pin "1") (pinfunction "1_1") (pintype "passive"))
      (node (ref "R46") (pin "1") (pinfunction "1_1") (pintype "passive"))
      (node (ref "R47") (pin "1") (pinfunction "1_1") (pintype "passive"))
      (node (ref "R48") (pin "1") (pinfunction "1_1") (pintype "passive"))
      (node (ref "R49") (pin "1") (pinfunction "1_1") (pintype "passive"))
      (node (ref "R50") (pin "1") (pinfunction "1_1") (pintype "passive"))
      (node (ref "R54") (pin "2") (pinfunction "2_2") (pintype "passive"))
      (node (ref "R56") (pin "2") (pinfunction "2_2") (pintype "passive"))
      (node (ref "R59") (pin "2") (pinfunction "2_2") (pintype "passive"))
      (node (ref "R62") (pin "1") (pinfunction "1_1") (pintype "passive"))
      (node (ref "R69") (pin "1") (pinfunction "1_1") (pintype "passive"))
      (node (ref "R76") (pin "1") (pinfunction "1_1") (pintype "passive"))
      (node (ref "R85") (pin "2") (pinfunction "2_2") (pintype "passive"))
      (node (ref "R86") (pin "1") (pinfunction "1_1") (pintype "passive"))
      (node (ref "R87") (pin "2") (pinfunction "2_2") (pintype "passive"))
      (node (ref "R89") (pin "2") (pinfunction "2_2") (pintype "passive"))
      (node (ref "R9") (pin "1") (pinfunction "1_1") (pintype "passive"))
      (node (ref "R97") (pin "1") (pinfunction "1_1") (pintype "passive"))
      (node (ref "S1") (pin "A@1") (pinfunction "A_A@1") (pintype "passive"))
      (node (ref "S2") (pin "A@1") (pinfunction "A_A@1") (pintype "passive"))
      (node (ref "U$101") (pin "A9") (pinfunction "VSS_A9") (pintype "power_in"))
      (node (ref "U$101") (pin "B1") (pinfunction "VSSQ_B1") (pintype "power_in"))
      (node (ref "U$101") (pin "B3") (pinfunction "VSS_B3") (pintype "power_in"))
      (node (ref "U$101") (pin "B9") (pinfunction "VSSQ_B9") (pintype "power_in"))
      (node (ref "U$101") (pin "D1") (pinfunction "VSSQ_D1") (pintype "power_in"))
      (node (ref "U$101") (pin "D8") (pinfunction "VSSQ_D8") (pintype "power_in"))
      (node (ref "U$101") (pin "E1") (pinfunction "VSS_E1") (pintype "power_in"))
      (node (ref "U$101") (pin "E2") (pinfunction "VSSQ_E2") (pintype "power_in"))
      (node (ref "U$101") (pin "E8") (pinfunction "VSSQ_E8") (pintype "power_in"))
      (node (ref "U$101") (pin "F9") (pinfunction "VSSQ_F9") (pintype "power_in"))
      (node (ref "U$101") (pin "G1") (pinfunction "VSSQ_G1") (pintype "power_in"))
      (node (ref "U$101") (pin "G8") (pinfunction "VSS_G8") (pintype "power_in"))
      (node (ref "U$101") (pin "G9") (pinfunction "VSSQ_G9") (pintype "power_in"))
      (node (ref "U$101") (pin "J2") (pinfunction "VSS_J2") (pintype "power_in"))
      (node (ref "U$101") (pin "J8") (pinfunction "VSS_J8") (pintype "power_in"))
      (node (ref "U$101") (pin "M1") (pinfunction "VSS_M1") (pintype "power_in"))
      (node (ref "U$101") (pin "M9") (pinfunction "VSS_M9") (pintype "power_in"))
      (node (ref "U$101") (pin "P1") (pinfunction "VSS_P1") (pintype "power_in"))
      (node (ref "U$101") (pin "P9") (pinfunction "VSS_P9") (pintype "power_in"))
      (node (ref "U$101") (pin "T1") (pinfunction "VSS_T1") (pintype "power_in"))
      (node (ref "U$101") (pin "T9") (pinfunction "VSS_T9") (pintype "power_in"))
      (node (ref "U$27") (pin "6") (pinfunction "GND1_6") (pintype "bidirectional"))
      (node (ref "U$27") (pin "9") (pinfunction "GND2_9") (pintype "bidirectional"))
      (node (ref "U$30") (pin "6") (pinfunction "GND_6") (pintype "bidirectional"))
      (node (ref "U$30") (pin "GND1") (pinfunction "SHIELD3_GND1") (pintype "bidirectional"))
      (node (ref "U$30") (pin "GND3") (pinfunction "SHIELD4_GND3") (pintype "bidirectional"))
      (node (ref "U$66") (pin "10") (pinfunction "GND_10") (pintype "bidirectional"))
      (node (ref "U$67") (pin "1") (pinfunction "1DIR_1") (pintype "input"))
      (node (ref "U$67") (pin "10") (pinfunction "GND_10") (pintype "power_in"))
      (node (ref "U$67") (pin "15") (pinfunction "GND_15") (pintype "power_in"))
      (node (ref "U$67") (pin "21") (pinfunction "GND_21") (pintype "power_in"))
      (node (ref "U$67") (pin "24") (pinfunction "2DIR_24") (pintype "input"))
      (node (ref "U$67") (pin "25") (pinfunction "2G_25") (pintype "input"))
      (node (ref "U$67") (pin "28") (pinfunction "GND_28") (pintype "power_in"))
      (node (ref "U$67") (pin "34") (pinfunction "GND_34") (pintype "power_in"))
      (node (ref "U$67") (pin "39") (pinfunction "GND_39") (pintype "power_in"))
      (node (ref "U$67") (pin "4") (pinfunction "GND_4") (pintype "power_in"))
      (node (ref "U$67") (pin "45") (pinfunction "GND_45") (pintype "power_in"))
      (node (ref "U$67") (pin "48") (pinfunction "1G_48") (pintype "input"))
      (node (ref "U$68") (pin "1") (pinfunction "1DIR_1") (pintype "input"))
      (node (ref "U$68") (pin "10") (pinfunction "GND_10") (pintype "power_in"))
      (node (ref "U$68") (pin "15") (pinfunction "GND_15") (pintype "power_in"))
      (node (ref "U$68") (pin "21") (pinfunction "GND_21") (pintype "power_in"))
      (node (ref "U$68") (pin "24") (pinfunction "2DIR_24") (pintype "input"))
      (node (ref "U$68") (pin "25") (pinfunction "2G_25") (pintype "input"))
      (node (ref "U$68") (pin "28") (pinfunction "GND_28") (pintype "power_in"))
      (node (ref "U$68") (pin "34") (pinfunction "GND_34") (pintype "power_in"))
      (node (ref "U$68") (pin "39") (pinfunction "GND_39") (pintype "power_in"))
      (node (ref "U$68") (pin "4") (pinfunction "GND_4") (pintype "power_in"))
      (node (ref "U$68") (pin "45") (pinfunction "GND_45") (pintype "power_in"))
      (node (ref "U$68") (pin "48") (pinfunction "1G_48") (pintype "input"))
      (node (ref "U$69") (pin "10") (pinfunction "GND_10") (pintype "power_in"))
      (node (ref "U$69") (pin "15") (pinfunction "GND_15") (pintype "power_in"))
      (node (ref "U$69") (pin "21") (pinfunction "GND_21") (pintype "power_in"))
      (node (ref "U$69") (pin "24") (pinfunction "2DIR_24") (pintype "input"))
      (node (ref "U$69") (pin "25") (pinfunction "2G_25") (pintype "input"))
      (node (ref "U$69") (pin "28") (pinfunction "GND_28") (pintype "power_in"))
      (node (ref "U$69") (pin "34") (pinfunction "GND_34") (pintype "power_in"))
      (node (ref "U$69") (pin "39") (pinfunction "GND_39") (pintype "power_in"))
      (node (ref "U$69") (pin "4") (pinfunction "GND_4") (pintype "power_in"))
      (node (ref "U$69") (pin "45") (pinfunction "GND_45") (pintype "power_in"))
      (node (ref "U$69") (pin "48") (pinfunction "1G_48") (pintype "input"))
      (node (ref "U$70") (pin "29") (pinfunction "GND_29") (pintype "power_in"))
      (node (ref "U$70") (pin "3") (pinfunction "GND_3") (pintype "power_in"))
      (node (ref "U$70") (pin "36") (pinfunction "GND_36") (pintype "power_in"))
      (node (ref "U$72") (pin "A1") (pinfunction "VSS_A1") (pintype "power_in"))
      (node (ref "U$72") (pin "A18") (pinfunction "VSS_A18") (pintype "power_in"))
      (node (ref "U$72") (pin "F8") (pinfunction "VSS_F8") (pintype "power_in"))
      (node (ref "U$72") (pin "G11") (pinfunction "VSS_G11") (pintype "power_in"))
      (node (ref "U$72") (pin "G12") (pinfunction "VSS_G12") (pintype "power_in"))
      (node (ref "U$72") (pin "G8") (pinfunction "VSS_G8") (pintype "power_in"))
      (node (ref "U$72") (pin "G9") (pinfunction "VSS_G9") (pintype "power_in"))
      (node (ref "U$72") (pin "H10") (pinfunction "VSS_H10") (pintype "power_in"))
      (node (ref "U$72") (pin "H12") (pinfunction "VSS_H12") (pintype "power_in"))
      (node (ref "U$72") (pin "H6") (pinfunction "VSS_H6") (pintype "power_in"))
      (node (ref "U$72") (pin "H7") (pinfunction "VSS_H7") (pintype "power_in"))
      (node (ref "U$72") (pin "H8") (pinfunction "VSS_H8") (pintype "power_in"))
      (node (ref "U$72") (pin "H9") (pinfunction "VSS_H9") (pintype "power_in"))
      (node (ref "U$72") (pin "J10") (pinfunction "VSS_J10") (pintype "power_in"))
      (node (ref "U$72") (pin "J11") (pinfunction "VSS_J11") (pintype "power_in"))
      (node (ref "U$72") (pin "J6") (pinfunction "VSS_J6") (pintype "power_in"))
      (node (ref "U$72") (pin "J7") (pinfunction "VSS_J7") (pintype "power_in"))
      (node (ref "U$72") (pin "J8") (pinfunction "VSS_J8") (pintype "power_in"))
      (node (ref "U$72") (pin "J9") (pinfunction "VSS_J9") (pintype "power_in"))
      (node (ref "U$72") (pin "K10") (pinfunction "VSS_K10") (pintype "power_in"))
      (node (ref "U$72") (pin "K11") (pinfunction "VSS_K11") (pintype "power_in"))
      (node (ref "U$72") (pin "K7") (pinfunction "VSS_K7") (pintype "power_in"))
      (node (ref "U$72") (pin "K9") (pinfunction "VSS_K9") (pintype "power_in"))
      (node (ref "U$72") (pin "L10") (pinfunction "VSS_L10") (pintype "power_in"))
      (node (ref "U$72") (pin "L11") (pinfunction "VSS_L11") (pintype "power_in"))
      (node (ref "U$72") (pin "L12") (pinfunction "VSS_L12") (pintype "power_in"))
      (node (ref "U$72") (pin "L13") (pinfunction "VSS_L13") (pintype "bidirectional"))
      (node (ref "U$72") (pin "M10") (pinfunction "VSS_M10") (pintype "power_in"))
      (node (ref "U$72") (pin "M12") (pinfunction "VSS_M12") (pintype "power_in"))
      (node (ref "U$72") (pin "M14") (pinfunction "VSSA_USB_M14") (pintype "power_in"))
      (node (ref "U$72") (pin "M6") (pinfunction "VSS_M6") (pintype "bidirectional"))
      (node (ref "U$72") (pin "M7") (pinfunction "VSS_M7") (pintype "power_in"))
      (node (ref "U$72") (pin "M8") (pinfunction "VSS_M8") (pintype "power_in"))
      (node (ref "U$72") (pin "M9") (pinfunction "VSS_M9") (pintype "power_in"))
      (node (ref "U$72") (pin "N10") (pinfunction "VSS_N10") (pintype "power_in"))
      (node (ref "U$72") (pin "N11") (pinfunction "VSS_N11") (pintype "power_in"))
      (node (ref "U$72") (pin "N14") (pinfunction "VSSA_USB_N14") (pintype "power_in"))
      (node (ref "U$72") (pin "N7") (pinfunction "VSS_N7") (pintype "power_in"))
      (node (ref "U$72") (pin "P17") (pinfunction "USB1_ID_P17") (pintype "bidirectional"))
      (node (ref "U$72") (pin "V1") (pinfunction "VSS_V1") (pintype "power_in"))
      (node (ref "U$72") (pin "V18") (pinfunction "VSS_V18") (pintype "power_in"))
      (node (ref "U$79") (pin "P4") (pinfunction "P$4_P4") (pintype "bidirectional"))
      (node (ref "U$80") (pin "P4") (pinfunction "P$4_P4") (pintype "bidirectional"))
      (node (ref "U$81") (pin "P2") (pinfunction "P$2_P2") (pintype "bidirectional"))
      (node (ref "U$81") (pin "P3") (pinfunction "P$3_P3") (pintype "bidirectional"))
      (node (ref "U$81") (pin "P4") (pinfunction "P$4_P4") (pintype "bidirectional"))
      (node (ref "U$82") (pin "P1") (pinfunction "P$1_P1") (pintype "bidirectional"))
      (node (ref "U$82") (pin "P2") (pinfunction "P$2_P2") (pintype "bidirectional"))
      (node (ref "U$82") (pin "P4") (pinfunction "P$4_P4") (pintype "bidirectional"))
      (node (ref "U1") (pin "4") (pinfunction "GND_4") (pintype "passive"))
      (node (ref "U10") (pin "4") (pinfunction "GND_4") (pintype "passive"))
      (node (ref "U11") (pin "4") (pinfunction "GND_4") (pintype "passive"))
      (node (ref "U12") (pin "10") (pinfunction "RSVD_GND_10") (pintype "power_in"))
      (node (ref "U12") (pin "11") (pinfunction "RSVD_GND_11") (pintype "power_in"))
      (node (ref "U12") (pin "12") (pinfunction "RSVD_GND_12") (pintype "power_in"))
      (node (ref "U12") (pin "13") (pinfunction "GND_13") (pintype "power_in"))
      (node (ref "U12") (pin "8") (pinfunction "RSVD_GND_8") (pintype "power_in"))
      (node (ref "U12") (pin "9") (pinfunction "RSVD_GND_9") (pintype "power_in"))
      (node (ref "U13") (pin "10") (pinfunction "RSVD_GND_10") (pintype "power_in"))
      (node (ref "U13") (pin "12") (pinfunction "GND_12") (pintype "power_in"))
      (node (ref "U13") (pin "13") (pinfunction "GND_13") (pintype "power_in"))
      (node (ref "U13") (pin "16") (pinfunction "GND_16") (pintype "power_in"))
      (node (ref "U13") (pin "5") (pinfunction "GND_5") (pintype "power_in"))
      (node (ref "U14") (pin "1") (pinfunction "GND_1") (pintype "bidirectional"))
      (node (ref "U14") (pin "TP") (pinfunction "GND_TP") (pintype "bidirectional"))
      (node (ref "U15") (pin "15") (pinfunction "AVSS_ADC_15") (pintype "bidirectional"))
      (node (ref "U15") (pin "20") (pinfunction "DRVSS.1_20") (pintype "bidirectional"))
      (node (ref "U15") (pin "21") (pinfunction "DRVSS.2_21") (pintype "bidirectional"))
      (node (ref "U15") (pin "26") (pinfunction "AVSS_DAC_26") (pintype "bidirectional"))
      (node (ref "U15") (pin "42") (pinfunction "DVSS_42") (pintype "bidirectional"))
      (node (ref "U15") (pin "49") (pinfunction "PPAD_49") (pintype "bidirectional"))
      (node (ref "U16") (pin "10") (pinfunction "1DIR_10") (pintype "input"))
      (node (ref "U16") (pin "2") (pinfunction "OE_2") (pintype "input"))
      (node (ref "U16") (pin "3") (pinfunction "GND_3") (pintype "power_in"))
      (node (ref "U17") (pin "1") (pinfunction "SHUTDOWN_1") (pintype "input"))
      (node (ref "U17") (pin "7") (pinfunction "GND_7") (pintype "power_in"))
      (node (ref "U18") (pin "EPAD") (pinfunction "VSS_EPAD") (pintype "power_in"))
      (node (ref "U19") (pin "2") (pinfunction "GND_2") (pintype "power_in"))
      (node (ref "U2") (pin "4") (pinfunction "GND_4") (pintype "passive"))
      (node (ref "U20") (pin "11") (pinfunction "GND_11") (pintype "power_in"))
      (node (ref "U21") (pin "4") (pinfunction "GND_4") (pintype "passive"))
      (node (ref "U22") (pin "4") (pinfunction "GND_4") (pintype "passive"))
      (node (ref "U23") (pin "10") (pinfunction "PGND2_10") (pintype "bidirectional"))
      (node (ref "U23") (pin "18") (pinfunction "GND_18") (pintype "bidirectional"))
      (node (ref "U23") (pin "3") (pinfunction "PGND1_3") (pintype "bidirectional"))
      (node (ref "U23") (pin "4") (pinfunction "PGND1_4") (pintype "bidirectional"))
      (node (ref "U23") (pin "9") (pinfunction "PGND2_9") (pintype "bidirectional"))
      (node (ref "U27") (pin "4") (pinfunction "GND_4") (pintype "passive"))
      (node (ref "U28") (pin "1") (pinfunction "GND_1") (pintype "bidirectional"))
      (node (ref "U28") (pin "15") (pinfunction "GND_15") (pintype "bidirectional"))
      (node (ref "U28") (pin "16") (pinfunction "GND_16") (pintype "bidirectional"))
      (node (ref "U28") (pin "17") (pinfunction "GND_17") (pintype "bidirectional"))
      (node (ref "U28") (pin "19") (pinfunction "GND_19") (pintype "bidirectional"))
      (node (ref "U28") (pin "20") (pinfunction "GND_20") (pintype "bidirectional"))
      (node (ref "U28") (pin "23") (pinfunction "GND_23") (pintype "bidirectional"))
      (node (ref "U28") (pin "24") (pinfunction "GND_24") (pintype "bidirectional"))
      (node (ref "U28") (pin "28") (pinfunction "GND_28") (pintype "bidirectional"))
      (node (ref "U28") (pin "29") (pinfunction "GND_29") (pintype "bidirectional"))
      (node (ref "U28") (pin "30") (pinfunction "GND_30") (pintype "bidirectional"))
      (node (ref "U28") (pin "31") (pinfunction "GND_31") (pintype "bidirectional"))
      (node (ref "U28") (pin "33") (pinfunction "GND_33") (pintype "bidirectional"))
      (node (ref "U28") (pin "34") (pinfunction "GND_34") (pintype "bidirectional"))
      (node (ref "U28") (pin "35") (pinfunction "GND_35") (pintype "bidirectional"))
      (node (ref "U28") (pin "37") (pinfunction "GND_37") (pintype "bidirectional"))
      (node (ref "U28") (pin "39") (pinfunction "GND_39") (pintype "bidirectional"))
      (node (ref "U28") (pin "44") (pinfunction "GND_44") (pintype "bidirectional"))
      (node (ref "U28") (pin "45") (pinfunction "GND_45") (pintype "bidirectional"))
      (node (ref "U28") (pin "48") (pinfunction "GND_48") (pintype "bidirectional"))
      (node (ref "U28") (pin "49") (pinfunction "GND_49") (pintype "bidirectional"))
      (node (ref "U28") (pin "54") (pinfunction "GND_54") (pintype "bidirectional"))
      (node (ref "U28") (pin "55") (pinfunction "GND_55") (pintype "bidirectional"))
      (node (ref "U28") (pin "59") (pinfunction "GND_59") (pintype "bidirectional"))
      (node (ref "U28") (pin "61") (pinfunction "GND_61") (pintype "bidirectional"))
      (node (ref "U28") (pin "63") (pinfunction "GND_63") (pintype "bidirectional"))
      (node (ref "U28") (pin "64") (pinfunction "GND_64") (pintype "bidirectional"))
      (node (ref "U28") (pin "7") (pinfunction "GND_7") (pintype "bidirectional"))
      (node (ref "U28") (pin "9") (pinfunction "GND_9") (pintype "bidirectional"))
      (node (ref "U28") (pin "G1") (pinfunction "GND_G1") (pintype "bidirectional"))
      (node (ref "U28") (pin "G10") (pinfunction "GND_G10") (pintype "bidirectional"))
      (node (ref "U28") (pin "G11") (pinfunction "GND_G11") (pintype "bidirectional"))
      (node (ref "U28") (pin "G12") (pinfunction "GND_G12") (pintype "bidirectional"))
      (node (ref "U28") (pin "G13") (pinfunction "GND_G13") (pintype "bidirectional"))
      (node (ref "U28") (pin "G14") (pinfunction "GND_G14") (pintype "bidirectional"))
      (node (ref "U28") (pin "G15") (pinfunction "GND_G15") (pintype "bidirectional"))
      (node (ref "U28") (pin "G16") (pinfunction "GND_G16") (pintype "bidirectional"))
      (node (ref "U28") (pin "G17") (pinfunction "GND_G17") (pintype "bidirectional"))
      (node (ref "U28") (pin "G18") (pinfunction "GND_G18") (pintype "bidirectional"))
      (node (ref "U28") (pin "G19") (pinfunction "GND_G19") (pintype "bidirectional"))
      (node (ref "U28") (pin "G2") (pinfunction "GND_G2") (pintype "bidirectional"))
      (node (ref "U28") (pin "G20") (pinfunction "GND_G20") (pintype "bidirectional"))
      (node (ref "U28") (pin "G21") (pinfunction "GND_G21") (pintype "bidirectional"))
      (node (ref "U28") (pin "G22") (pinfunction "GND_G22") (pintype "bidirectional"))
      (node (ref "U28") (pin "G23") (pinfunction "GND_G23") (pintype "bidirectional"))
      (node (ref "U28") (pin "G24") (pinfunction "GND_G24") (pintype "bidirectional"))
      (node (ref "U28") (pin "G25") (pinfunction "GND_G25") (pintype "bidirectional"))
      (node (ref "U28") (pin "G26") (pinfunction "GND_G26") (pintype "bidirectional"))
      (node (ref "U28") (pin "G27") (pinfunction "GND_G27") (pintype "bidirectional"))
      (node (ref "U28") (pin "G28") (pinfunction "GND_G28") (pintype "bidirectional"))
      (node (ref "U28") (pin "G29") (pinfunction "GND_G29") (pintype "bidirectional"))
      (node (ref "U28") (pin "G3") (pinfunction "GND_G3") (pintype "bidirectional"))
      (node (ref "U28") (pin "G30") (pinfunction "GND_G30") (pintype "bidirectional"))
      (node (ref "U28") (pin "G31") (pinfunction "GND_G31") (pintype "bidirectional"))
      (node (ref "U28") (pin "G32") (pinfunction "GND_G32") (pintype "bidirectional"))
      (node (ref "U28") (pin "G33") (pinfunction "GND_G33") (pintype "bidirectional"))
      (node (ref "U28") (pin "G34") (pinfunction "GND_G34") (pintype "bidirectional"))
      (node (ref "U28") (pin "G35") (pinfunction "GND_G35") (pintype "bidirectional"))
      (node (ref "U28") (pin "G36") (pinfunction "GND_G36") (pintype "bidirectional"))
      (node (ref "U28") (pin "G4") (pinfunction "GND_G4") (pintype "bidirectional"))
      (node (ref "U28") (pin "G5") (pinfunction "GND_G5") (pintype "bidirectional"))
      (node (ref "U28") (pin "G6") (pinfunction "GND_G6") (pintype "bidirectional"))
      (node (ref "U28") (pin "G7") (pinfunction "GND_G7") (pintype "bidirectional"))
      (node (ref "U28") (pin "G8") (pinfunction "GND_G8") (pintype "bidirectional"))
      (node (ref "U28") (pin "G9") (pinfunction "GND_G9") (pintype "bidirectional"))
      (node (ref "U29") (pin "11") (pinfunction "GND_11") (pintype "power_in"))
      (node (ref "U3") (pin "4") (pinfunction "GND_4") (pintype "power_in"))
      (node (ref "U30") (pin "4") (pinfunction "GND_4") (pintype "passive"))
      (node (ref "U32") (pin "4") (pinfunction "GND_4") (pintype "passive"))
      (node (ref "U33") (pin "1") (pinfunction "GND_1") (pintype "power_in"))
      (node (ref "U34") (pin "4") (pinfunction "GND_4") (pintype "power_in"))
      (node (ref "U34") (pin "7") (pinfunction "WP_7") (pintype "input"))
      (node (ref "U35") (pin "30") (pinfunction "PGND_30") (pintype "power_in"))
      (node (ref "U35") (pin "41") (pinfunction "AGND_41") (pintype "power_in"))
      (node (ref "U35") (pin "49") (pinfunction "PPAD_49") (pintype "power_in"))
      (node (ref "U4") (pin "10") (pinfunction "PGND2_10") (pintype "bidirectional"))
      (node (ref "U4") (pin "18") (pinfunction "GND_18") (pintype "bidirectional"))
      (node (ref "U4") (pin "3") (pinfunction "PGND1_3") (pintype "bidirectional"))
      (node (ref "U4") (pin "4") (pinfunction "PGND1_4") (pintype "bidirectional"))
      (node (ref "U4") (pin "9") (pinfunction "PGND2_9") (pintype "bidirectional"))
      (node (ref "U8") (pin "11") (pinfunction "GND_11") (pintype "power_in"))
      (node (ref "U9") (pin "3") (pinfunction "3_3") (pintype "passive"))
      (node (ref "X2") (pin "2") (pinfunction "GND_2") (pintype "power_in"))
      (node (ref "Y1") (pin "2") (pinfunction "2_2") (pintype "passive"))
      (node (ref "Y1") (pin "4") (pinfunction "4_4") (pintype "passive"))
      (node (ref "Y2") (pin "2") (pinfunction "2_2") (pintype "passive"))
      (node (ref "Y2") (pin "4") (pinfunction "4_4") (pintype "passive"))
    )
    (net (code "301") (name "GREEN0$43") (class "Default")
      (node (ref "U$68") (pin "37") (pinfunction "1A7_37") (pintype "bidirectional"))
      (node (ref "U$70") (pin "13") (pinfunction "G0_13") (pintype "output"))
    )
    (net (code "302") (name "GREEN1$43") (class "Default")
      (node (ref "U$68") (pin "38") (pinfunction "1A6_38") (pintype "bidirectional"))
      (node (ref "U$70") (pin "14") (pinfunction "G1_14") (pintype "output"))
    )
    (net (code "303") (name "GREEN2$43") (class "Default")
      (node (ref "U$68") (pin "40") (pinfunction "1A5_40") (pintype "bidirectional"))
      (node (ref "U$70") (pin "15") (pinfunction "G2_15") (pintype "output"))
    )
    (net (code "304") (name "GREEN3$43") (class "Default")
      (node (ref "U$68") (pin "41") (pinfunction "1A4_41") (pintype "bidirectional"))
      (node (ref "U$70") (pin "16") (pinfunction "G3_16") (pintype "output"))
    )
    (net (code "305") (name "GREEN4$43") (class "Default")
      (node (ref "U$68") (pin "43") (pinfunction "1A3_43") (pintype "bidirectional"))
      (node (ref "U$70") (pin "17") (pinfunction "G4_17") (pintype "output"))
    )
    (net (code "306") (name "GREEN5$43") (class "Default")
      (node (ref "U$68") (pin "44") (pinfunction "1A2_44") (pintype "bidirectional"))
      (node (ref "U$70") (pin "18") (pinfunction "G5_18") (pintype "output"))
    )
    (net (code "307") (name "GREEN6$43") (class "Default")
      (node (ref "U$68") (pin "46") (pinfunction "1A1_46") (pintype "bidirectional"))
      (node (ref "U$70") (pin "19") (pinfunction "G6_19") (pintype "output"))
    )
    (net (code "308") (name "GREEN7$43") (class "Default")
      (node (ref "U$68") (pin "47") (pinfunction "1A0_47") (pintype "bidirectional"))
      (node (ref "U$70") (pin "20") (pinfunction "G7_20") (pintype "output"))
    )
    (net (code "309") (name "GYRO_PLLFILT$13") (class "Default")
      (node (ref "C47") (pin "1") (pinfunction "1_1") (pintype "passive"))
      (node (ref "C48") (pin "1") (pinfunction "1_1") (pintype "passive"))
      (node (ref "U12") (pin "14") (pinfunction "PLLFILT_14") (pintype "passive"))
    )
    (net (code "310") (name "HSYNC$44") (class "Default")
      (node (ref "IC4") (pin "4") (pinfunction "HSYNC_4") (pintype "bidirectional"))
      (node (ref "R117") (pin "2") (pinfunction "2_2") (pintype "passive"))
    )
    (net (code "311") (name "I2C_VREF2$44") (class "Default")
      (node (ref "R106") (pin "2") (pinfunction "2_2") (pintype "passive"))
      (node (ref "U33") (pin "7") (pinfunction "VREF2_7") (pintype "input"))
      (node (ref "U33") (pin "8") (pinfunction "EN_8") (pintype "input"))
    )
    (net (code "312") (name "IDCK+$44") (class "Default")
      (node (ref "IC4") (pin "57") (pinfunction "IDCK+_57") (pintype "bidirectional"))
      (node (ref "RP8") (pin "6") (pinfunction "6_6") (pintype "passive"))
    )
    (net (code "313") (name "INT_LDO$45") (class "Default")
      (node (ref "C223") (pin "1") (pinfunction "1_1") (pintype "passive"))
      (node (ref "U35") (pin "48") (pinfunction "INT_LDO_48") (pintype "output"))
    )
    (net (code "314") (name "ISET1$45") (class "Default")
      (node (ref "R120") (pin "2") (pinfunction "2_2") (pintype "passive"))
      (node (ref "U35") (pin "35") (pinfunction "ISET1_35") (pintype "input"))
    )
    (net (code "315") (name "ISET2$45") (class "Default")
      (node (ref "R121") (pin "2") (pinfunction "2_2") (pintype "passive"))
      (node (ref "U35") (pin "36") (pinfunction "ISET2_36") (pintype "input"))
    )
    (net (code "316") (name "JTAG_EMU0$45") (class "Default")
      (node (ref "R126") (pin "1") (pinfunction "1_1") (pintype "passive"))
      (node (ref "U$72") (pin "C14") (pinfunction "EMU0|GPIO3_7_C14") (pintype "bidirectional"))
    )
    (net (code "317") (name "JTAG_EMU1$45") (class "Default")
      (node (ref "R127") (pin "1") (pinfunction "1_1") (pintype "passive"))
      (node (ref "U$72") (pin "B14") (pinfunction "EMU1|GPIO3_8_B14") (pintype "bidirectional"))
    )
    (net (code "318") (name "LDO_PGOOD$45") (class "Default")
      (node (ref "U$72") (pin "B5") (pinfunction "RTC_PWRONRSTN_B5") (pintype "input"))
      (node (ref "U35") (pin "46") (pinfunction "LDO_PGOOD_46") (pintype "open_collector"))
    )
    (net (code "319") (name "LINE1LM$15") (class "Default")
      (node (ref "C52") (pin "1") (pinfunction "1_1") (pintype "passive"))
      (node (ref "U15") (pin "4") (pinfunction "LINE1LM_4") (pintype "bidirectional"))
    )
    (net (code "320") (name "LINE1RM$15") (class "Default")
      (node (ref "C53") (pin "1") (pinfunction "1_1") (pintype "passive"))
      (node (ref "U15") (pin "6") (pinfunction "LINE1RM_6") (pintype "bidirectional"))
    )
    (net (code "321") (name "L_L4$45") (class "Default")
      (node (ref "D31") (pin "A") (pinfunction "A_A") (pintype "passive"))
      (node (ref "L14") (pin "2") (pinfunction "2_2") (pintype "passive"))
      (node (ref "U35") (pin "37") (pinfunction "L4_37") (pintype "passive"))
    )
    (net (code "322") (name "M0A$6") (class "Default")
      (node (ref "R4") (pin "1") (pinfunction "1_1") (pintype "passive"))
      (node (ref "U4") (pin "1") (pinfunction "A01_1") (pintype "bidirectional"))
      (node (ref "U4") (pin "2") (pinfunction "A01_2") (pintype "bidirectional"))
      (node (ref "U5") (pin "A1") (pinfunction "A1_A1") (pintype "bidirectional"))
      (node (ref "U5") (pin "A2") (pinfunction "A2_A2") (pintype "bidirectional"))
      (node (ref "U6") (pin "1") (pinfunction "1_1") (pintype "passive"))
      (node (ref "U6") (pin "4") (pinfunction "4_4") (pintype "passive"))
    )
    (net (code "323") (name "M0A$31") (class "Default")
      (node (ref "R64") (pin "1") (pinfunction "1_1") (pintype "passive"))
      (node (ref "U23") (pin "1") (pinfunction "A01_1") (pintype "bidirectional"))
      (node (ref "U23") (pin "2") (pinfunction "A01_2") (pintype "bidirectional"))
      (node (ref "U24") (pin "A1") (pinfunction "A1_A1") (pintype "bidirectional"))
      (node (ref "U24") (pin "A2") (pinfunction "A2_A2") (pintype "bidirectional"))
      (node (ref "U25") (pin "1") (pinfunction "1_1") (pintype "passive"))
      (node (ref "U25") (pin "4") (pinfunction "4_4") (pintype "passive"))
    )
    (net (code "324") (name "M0B$6") (class "Default")
      (node (ref "R10") (pin "1") (pinfunction "1_1") (pintype "passive"))
      (node (ref "R5") (pin "1") (pinfunction "1_1") (pintype "passive"))
      (node (ref "U4") (pin "5") (pinfunction "A02_5") (pintype "bidirectional"))
      (node (ref "U4") (pin "6") (pinfunction "A02_6") (pintype "bidirectional"))
      (node (ref "U5") (pin "A3") (pinfunction "A3_A3") (pintype "bidirectional"))
    )
    (net (code "325") (name "M0B$31") (class "Default")
      (node (ref "R65") (pin "1") (pinfunction "1_1") (pintype "passive"))
      (node (ref "R70") (pin "1") (pinfunction "1_1") (pintype "passive"))
      (node (ref "U23") (pin "5") (pinfunction "A02_5") (pintype "bidirectional"))
      (node (ref "U23") (pin "6") (pinfunction "A02_6") (pintype "bidirectional"))
      (node (ref "U24") (pin "A3") (pinfunction "A3_A3") (pintype "bidirectional"))
    )
    (net (code "326") (name "M1A$6") (class "Default")
      (node (ref "R11") (pin "1") (pinfunction "1_1") (pintype "passive"))
      (node (ref "U4") (pin "11") (pinfunction "B01_11") (pintype "bidirectional"))
      (node (ref "U4") (pin "12") (pinfunction "B01_12") (pintype "bidirectional"))
      (node (ref "U5") (pin "B1") (pinfunction "B1_B1") (pintype "bidirectional"))
      (node (ref "U5") (pin "B2") (pinfunction "B2_B2") (pintype "bidirectional"))
      (node (ref "U7") (pin "1") (pinfunction "1_1") (pintype "passive"))
      (node (ref "U7") (pin "4") (pinfunction "4_4") (pintype "passive"))
    )
    (net (code "327") (name "M1A$31") (class "Default")
      (node (ref "R71") (pin "1") (pinfunction "1_1") (pintype "passive"))
      (node (ref "U23") (pin "11") (pinfunction "B01_11") (pintype "bidirectional"))
      (node (ref "U23") (pin "12") (pinfunction "B01_12") (pintype "bidirectional"))
      (node (ref "U24") (pin "B1") (pinfunction "B1_B1") (pintype "bidirectional"))
      (node (ref "U24") (pin "B2") (pinfunction "B2_B2") (pintype "bidirectional"))
      (node (ref "U26") (pin "1") (pinfunction "1_1") (pintype "passive"))
      (node (ref "U26") (pin "4") (pinfunction "4_4") (pintype "passive"))
    )
    (net (code "328") (name "M1B$6") (class "Default")
      (node (ref "R12") (pin "1") (pinfunction "1_1") (pintype "passive"))
      (node (ref "R17") (pin "1") (pinfunction "1_1") (pintype "passive"))
      (node (ref "U4") (pin "7") (pinfunction "B02_7") (pintype "bidirectional"))
      (node (ref "U4") (pin "8") (pinfunction "B02_8") (pintype "bidirectional"))
      (node (ref "U5") (pin "B3") (pinfunction "B3_B3") (pintype "bidirectional"))
    )
    (net (code "329") (name "M1B$31") (class "Default")
      (node (ref "R72") (pin "1") (pinfunction "1_1") (pintype "passive"))
      (node (ref "R77") (pin "1") (pinfunction "1_1") (pintype "passive"))
      (node (ref "U23") (pin "7") (pinfunction "B02_7") (pintype "bidirectional"))
      (node (ref "U23") (pin "8") (pinfunction "B02_8") (pintype "bidirectional"))
      (node (ref "U24") (pin "B3") (pinfunction "B3_B3") (pintype "bidirectional"))
    )
    (net (code "330") (name "MISO$24") (class "Default")
      (node (ref "J7") (pin "B1") (pinfunction "B1_B1") (pintype "bidirectional"))
      (node (ref "RP4") (pin "6") (pinfunction "6_6") (pintype "passive"))
      (node (ref "U20") (pin "13") (pinfunction "B7_13") (pintype "bidirectional"))
    )
    (net (code "331") (name "MMC_CLK$22") (class "Default")
      (node (ref "RP1") (pin "15") (pinfunction "15_15") (pintype "passive"))
      (node (ref "U$30") (pin "5") (pinfunction "CLK/SCLK_5") (pintype "bidirectional"))
    )
    (net (code "332") (name "MMC_CMD$22") (class "Default")
      (node (ref "RP1") (pin "16") (pinfunction "16_16") (pintype "passive"))
      (node (ref "U$30") (pin "3") (pinfunction "CMD/DI_3") (pintype "bidirectional"))
    )
    (net (code "333") (name "MMC_D0$22") (class "Default")
      (node (ref "RP1") (pin "12") (pinfunction "12_12") (pintype "passive"))
      (node (ref "U$30") (pin "7") (pinfunction "DAT0/DO_7") (pintype "bidirectional"))
    )
    (net (code "334") (name "MMC_D1$22") (class "Default")
      (node (ref "RP1") (pin "11") (pinfunction "11_11") (pintype "passive"))
      (node (ref "U$30") (pin "8") (pinfunction "DAT1/RSV_8") (pintype "bidirectional"))
    )
    (net (code "335") (name "MMC_D2$22") (class "Default")
      (node (ref "RP1") (pin "10") (pinfunction "10_10") (pintype "passive"))
      (node (ref "U$30") (pin "1") (pinfunction "DAT2/RSV_1") (pintype "bidirectional"))
    )
    (net (code "336") (name "MMC_D3$22") (class "Default")
      (node (ref "RP1") (pin "9") (pinfunction "9_9") (pintype "passive"))
      (node (ref "U$30") (pin "2") (pinfunction "DAT3_CD/CS_2") (pintype "bidirectional"))
    )
    (net (code "337") (name "MOSI$24") (class "Default")
      (node (ref "J7") (pin "B3") (pinfunction "B3_B3") (pintype "bidirectional"))
      (node (ref "RP4") (pin "1") (pinfunction "1_1") (pintype "passive"))
      (node (ref "U20") (pin "18") (pinfunction "B2_18") (pintype "bidirectional"))
    )
    (net (code "338") (name "MSEN$44") (class "Default")
      (node (ref "IC4") (pin "11") (pinfunction "MSEN_11") (pintype "bidirectional"))
      (node (ref "R104") (pin "2") (pinfunction "2_2") (pintype "passive"))
    )
    (net (code "339") (name "NIRQ$24") (class "Default")
      (node (ref "J7") (pin "A1") (pinfunction "A1_A1") (pintype "bidirectional"))
      (node (ref "RP4") (pin "5") (pinfunction "5_5") (pintype "passive"))
      (node (ref "U20") (pin "14") (pinfunction "B6_14") (pintype "bidirectional"))
    )
    (net (code "340") (name "NMI$45") (class "Default")
      (node (ref "R119") (pin "2") (pinfunction "2_2") (pintype "passive"))
      (node (ref "U$72") (pin "B18") (pinfunction "EXTINTN_B18") (pintype "input"))
    )
    (net (code "341") (name "Net-(C29-Pad1)") (class "Default")
      (node (ref "C29") (pin "1") (pinfunction "1_1") (pintype "passive"))
      (node (ref "C30") (pin "1") (pinfunction "1_1") (pintype "passive"))
      (node (ref "FB4") (pin "1") (pinfunction "1_1") (pintype "passive"))
      (node (ref "K1") (pin "A1") (pinfunction "VCC_A1") (pintype "bidirectional"))
    )
    (net (code "342") (name "Net-(C31-Pad1)") (class "Default")
      (node (ref "C31") (pin "1") (pinfunction "1_1") (pintype "passive"))
      (node (ref "C32") (pin "1") (pinfunction "1_1") (pintype "passive"))
      (node (ref "FB3") (pin "1") (pinfunction "1_1") (pintype "passive"))
      (node (ref "K1") (pin "B1") (pinfunction "VCC_B1") (pintype "bidirectional"))
    )
    (net (code "343") (name "Net-(C47-Pad2)") (class "Default")
      (node (ref "C47") (pin "2") (pinfunction "2_2") (pintype "passive"))
      (node (ref "R33") (pin "2") (pinfunction "2_2") (pintype "passive"))
    )
    (net (code "344") (name "Net-(C54-Pad1)") (class "Default")
      (node (ref "C54") (pin "1") (pinfunction "1_1") (pintype "passive"))
      (node (ref "R32") (pin "1") (pinfunction "1_1") (pintype "passive"))
      (node (ref "R34") (pin "1") (pinfunction "1_1") (pintype "passive"))
    )
    (net (code "345") (name "Net-(C67-Pad1)") (class "Default")
      (node (ref "C67") (pin "1") (pinfunction "1_1") (pintype "passive"))
      (node (ref "R41") (pin "2") (pinfunction "2_2") (pintype "passive"))
    )
    (net (code "346") (name "Net-(C121-Pad1)") (class "Default")
      (node (ref "C121") (pin "1") (pinfunction "1_1") (pintype "passive"))
      (node (ref "R83") (pin "2") (pinfunction "2_2") (pintype "passive"))
      (node (ref "Y2") (pin "1") (pinfunction "1_1") (pintype "passive"))
    )
    (net (code "347") (name "Net-(D1-PadA)") (class "Default")
      (node (ref "D1") (pin "A") (pinfunction "A_A") (pintype "passive"))
      (node (ref "R18") (pin "1") (pinfunction "1_1") (pintype "passive"))
    )
    (net (code "348") (name "Net-(D2-PadA)") (class "Default")
      (node (ref "D2") (pin "A") (pinfunction "A_A") (pintype "passive"))
      (node (ref "R23") (pin "2") (pinfunction "2_2") (pintype "passive"))
    )
    (net (code "349") (name "Net-(D11-PadA)") (class "Default")
      (node (ref "D11") (pin "A") (pinfunction "A_A") (pintype "passive"))
      (node (ref "R55") (pin "2") (pinfunction "2_2") (pintype "passive"))
    )
    (net (code "350") (name "Net-(D12-PadA)") (class "Default")
      (node (ref "D12") (pin "A") (pinfunction "A_A") (pintype "passive"))
      (node (ref "R58") (pin "2") (pinfunction "2_2") (pintype "passive"))
    )
    (net (code "351") (name "Net-(IC3A-VCAP_2)") (class "Default")
      (node (ref "C136") (pin "1") (pinfunction "1_1") (pintype "passive"))
      (node (ref "IC3") (pin "73") (pinfunction "VCAP_2_73") (pintype "input"))
    )
    (net (code "352") (name "Net-(IC3B-OSC_IN)") (class "Default")
      (node (ref "C122") (pin "1") (pinfunction "1_1") (pintype "passive"))
      (node (ref "IC3") (pin "12") (pinfunction "OSC_IN_12") (pintype "input"))
      (node (ref "Y2") (pin "3") (pinfunction "3_3") (pintype "passive"))
    )
    (net (code "353") (name "Net-(IC3B-OSC_OUT)") (class "Default")
      (node (ref "IC3") (pin "13") (pinfunction "OSC_OUT_13") (pintype "output"))
      (node (ref "R83") (pin "1") (pinfunction "1_1") (pintype "passive"))
    )
    (net (code "354") (name "Net-(IC3M-VCAP_1)") (class "Default")
      (node (ref "C135") (pin "1") (pinfunction "1_1") (pintype "passive"))
      (node (ref "IC3") (pin "49") (pinfunction "VCAP_1_49") (pintype "power_in"))
    )
    (net (code "355") (name "Net-(J12-Pad10)") (class "Default")
      (node (ref "J12") (pin "10") (pinfunction "10_10") (pintype "passive"))
      (node (ref "J12") (pin "12") (pinfunction "12_12") (pintype "passive"))
      (node (ref "J12") (pin "14") (pinfunction "14_14") (pintype "passive"))
      (node (ref "J12") (pin "16") (pinfunction "16_16") (pintype "passive"))
      (node (ref "J12") (pin "18") (pinfunction "18_18") (pintype "passive"))
      (node (ref "J12") (pin "2") (pinfunction "2_2") (pintype "passive"))
      (node (ref "J12") (pin "20") (pinfunction "20_20") (pintype "passive"))
      (node (ref "J12") (pin "4") (pinfunction "4_4") (pintype "passive"))
      (node (ref "J12") (pin "6") (pinfunction "6_6") (pintype "passive"))
      (node (ref "J12") (pin "8") (pinfunction "8_8") (pintype "passive"))
      (node (ref "R79") (pin "1") (pinfunction "1_1") (pintype "passive"))
    )
    (net (code "356") (name "Net-(Q1-G)") (class "Default")
      (node (ref "Q1") (pin "1") (pinfunction "G_1") (pintype "passive"))
      (node (ref "Q6") (pin "1") (pinfunction "G_1") (pintype "passive"))
      (node (ref "R19") (pin "1") (pinfunction "1_1") (pintype "passive"))
      (node (ref "R20") (pin "1") (pinfunction "1_1") (pintype "passive"))
    )
    (net (code "357") (name "Net-(Q1-S)") (class "Default")
      (node (ref "F3") (pin "1") (pinfunction "1_1") (pintype "passive"))
      (node (ref "Q1") (pin "3") (pinfunction "S_3") (pintype "passive"))
    )
    (net (code "358") (name "Net-(Q2-D)") (class "Default")
      (node (ref "D2") (pin "C") (pinfunction "C_C") (pintype "passive"))
      (node (ref "Q2") (pin "3") (pinfunction "D_3") (pintype "passive"))
    )
    (net (code "359") (name "Net-(Q2-G)") (class "Default")
      (node (ref "Q2") (pin "1") (pinfunction "G_1") (pintype "passive"))
      (node (ref "R25") (pin "2") (pinfunction "2_2") (pintype "passive"))
    )
    (net (code "360") (name "Net-(Q3-D)") (class "Default")
      (node (ref "D11") (pin "C") (pinfunction "C_C") (pintype "passive"))
      (node (ref "Q3") (pin "3") (pinfunction "D_3") (pintype "passive"))
    )
    (net (code "361") (name "Net-(Q3-G)") (class "Default")
      (node (ref "Q3") (pin "1") (pinfunction "G_1") (pintype "passive"))
      (node (ref "R57") (pin "2") (pinfunction "2_2") (pintype "passive"))
    )
    (net (code "362") (name "Net-(Q4-D)") (class "Default")
      (node (ref "D12") (pin "C") (pinfunction "C_C") (pintype "passive"))
      (node (ref "Q4") (pin "3") (pinfunction "D_3") (pintype "passive"))
    )
    (net (code "363") (name "Net-(Q4-G)") (class "Default")
      (node (ref "Q4") (pin "1") (pinfunction "G_1") (pintype "passive"))
      (node (ref "R60") (pin "2") (pinfunction "2_2") (pintype "passive"))
    )
    (net (code "364") (name "Net-(R6-Pad2)") (class "Default")
      (node (ref "R6") (pin "2") (pinfunction "2_2") (pintype "passive"))
      (node (ref "R7") (pin "2") (pinfunction "2_2") (pintype "passive"))
      (node (ref "R8") (pin "1") (pinfunction "1_1") (pintype "passive"))
      (node (ref "R9") (pin "2") (pinfunction "2_2") (pintype "passive"))
    )
    (net (code "365") (name "Net-(R10-Pad2)") (class "Default")
      (node (ref "R10") (pin "2") (pinfunction "2_2") (pintype "passive"))
      (node (ref "U6") (pin "2") (pinfunction "2_2") (pintype "passive"))
      (node (ref "U6") (pin "3") (pinfunction "3_3") (pintype "passive"))
    )
    (net (code "366") (name "Net-(R13-Pad2)") (class "Default")
      (node (ref "R13") (pin "2") (pinfunction "2_2") (pintype "passive"))
      (node (ref "R14") (pin "2") (pinfunction "2_2") (pintype "passive"))
      (node (ref "R15") (pin "1") (pinfunction "1_1") (pintype "passive"))
      (node (ref "R16") (pin "2") (pinfunction "2_2") (pintype "passive"))
    )
    (net (code "367") (name "Net-(R17-Pad2)") (class "Default")
      (node (ref "R17") (pin "2") (pinfunction "2_2") (pintype "passive"))
      (node (ref "U7") (pin "2") (pinfunction "2_2") (pintype "passive"))
      (node (ref "U7") (pin "3") (pinfunction "3_3") (pintype "passive"))
    )
    (net (code "368") (name "Net-(R20-Pad2)") (class "Default")
      (node (ref "R20") (pin "2") (pinfunction "2_2") (pintype "passive"))
      (node (ref "U9") (pin "2") (pinfunction "2_2") (pintype "passive"))
    )
    (net (code "369") (name "Net-(R66-Pad2)") (class "Default")
      (node (ref "R66") (pin "2") (pinfunction "2_2") (pintype "passive"))
      (node (ref "R67") (pin "2") (pinfunction "2_2") (pintype "passive"))
      (node (ref "R68") (pin "1") (pinfunction "1_1") (pintype "passive"))
      (node (ref "R69") (pin "2") (pinfunction "2_2") (pintype "passive"))
    )
    (net (code "370") (name "Net-(R70-Pad2)") (class "Default")
      (node (ref "R70") (pin "2") (pinfunction "2_2") (pintype "passive"))
      (node (ref "U25") (pin "2") (pinfunction "2_2") (pintype "passive"))
      (node (ref "U25") (pin "3") (pinfunction "3_3") (pintype "passive"))
    )
    (net (code "371") (name "Net-(R73-Pad2)") (class "Default")
      (node (ref "R73") (pin "2") (pinfunction "2_2") (pintype "passive"))
      (node (ref "R74") (pin "2") (pinfunction "2_2") (pintype "passive"))
      (node (ref "R75") (pin "1") (pinfunction "1_1") (pintype "passive"))
      (node (ref "R76") (pin "2") (pinfunction "2_2") (pintype "passive"))
    )
    (net (code "372") (name "Net-(R77-Pad2)") (class "Default")
      (node (ref "R77") (pin "2") (pinfunction "2_2") (pintype "passive"))
      (node (ref "U26") (pin "2") (pinfunction "2_2") (pintype "passive"))
      (node (ref "U26") (pin "3") (pinfunction "3_3") (pintype "passive"))
    )
    (net (code "373") (name "Net-(R118-Pad1)") (class "Default")
      (node (ref "R118") (pin "1") (pinfunction "1_1") (pintype "passive"))
      (node (ref "Y4") (pin "1") (pinfunction "1_1") (pintype "passive"))
    )
    (net (code "374") (name "Net-(U$27-BOOT)") (class "Default")
      (node (ref "C88") (pin "1") (pinfunction "1_1") (pintype "passive"))
      (node (ref "U$27") (pin "1") (pinfunction "BOOT_1") (pintype "bidirectional"))
    )
    (net (code "375") (name "Net-(U$27-PH)") (class "Default")
      (node (ref "C88") (pin "2") (pinfunction "2_2") (pintype "passive"))
      (node (ref "D10") (pin "C") (pinfunction "C_C") (pintype "passive"))
      (node (ref "L2") (pin "1") (pinfunction "1_1") (pintype "passive"))
      (node (ref "U$27") (pin "8") (pinfunction "PH_8") (pintype "bidirectional"))
    )
    (net (code "376") (name "Net-(U$27-VSENSE)") (class "Default")
      (node (ref "R53") (pin "2") (pinfunction "2_2") (pintype "passive"))
      (node (ref "R54") (pin "1") (pinfunction "1_1") (pintype "passive"))
      (node (ref "U$27") (pin "4") (pinfunction "VSENSE_4") (pintype "bidirectional"))
    )
    (net (code "377") (name "Net-(U$72B-CAP_VBB_MPU)") (class "Default")
      (node (ref "C164") (pin "1") (pinfunction "1_1") (pintype "passive"))
      (node (ref "U$72") (pin "C10") (pinfunction "CAP_VBB_MPU_C10") (pintype "bidirectional"))
    )
    (net (code "378") (name "Net-(U$72B-CAP_VDD_SRAM_CORE)") (class "Default")
      (node (ref "C166") (pin "1") (pinfunction "1_1") (pintype "passive"))
      (node (ref "U$72") (pin "D9") (pinfunction "CAP_VDD_SRAM_CORE_D9") (pintype "bidirectional"))
    )
    (net (code "379") (name "Net-(U$72B-CAP_VDD_SRAM_MPU)") (class "Default")
      (node (ref "C167") (pin "1") (pinfunction "1_1") (pintype "passive"))
      (node (ref "U$72") (pin "D11") (pinfunction "CAP_VDD_SRAM_MPU_D11") (pintype "bidirectional"))
    )
    (net (code "380") (name "Net-(U$72B-CAP_VSS_RTC)") (class "Default")
      (node (ref "C165") (pin "1") (pinfunction "1_1") (pintype "passive"))
      (node (ref "U$72") (pin "D6") (pinfunction "CAP_VSS_RTC_D6") (pintype "bidirectional"))
    )
    (net (code "381") (name "Net-(U14-IN)") (class "Default")
      (node (ref "C26") (pin "1") (pinfunction "1_1") (pintype "passive"))
      (node (ref "FB2") (pin "2") (pinfunction "2_2") (pintype "passive"))
      (node (ref "U14") (pin "2") (pinfunction "IN_2") (pintype "bidirectional"))
    )
    (net (code "382") (name "Net-(U15-MCLK)") (class "Default")
      (node (ref "R35") (pin "1") (pinfunction "1_1") (pintype "passive"))
      (node (ref "U15") (pin "37") (pinfunction "MCLK_37") (pintype "bidirectional"))
    )
    (net (code "383") (name "Net-(U15-MFP0)") (class "Default")
      (node (ref "R26") (pin "1") (pinfunction "1_1") (pintype "passive"))
      (node (ref "R27") (pin "2") (pinfunction "2_2") (pintype "passive"))
      (node (ref "U15") (pin "45") (pinfunction "MFP0_45") (pintype "bidirectional"))
    )
    (net (code "384") (name "Net-(U15-MFP1)") (class "Default")
      (node (ref "R28") (pin "2") (pinfunction "2_2") (pintype "passive"))
      (node (ref "R29") (pin "1") (pinfunction "1_1") (pintype "passive"))
      (node (ref "U15") (pin "46") (pinfunction "MFP1_46") (pintype "bidirectional"))
    )
    (net (code "385") (name "Net-(U15-MIC3L)") (class "Default")
      (node (ref "C54") (pin "2") (pinfunction "2_2") (pintype "passive"))
      (node (ref "U15") (pin "11") (pinfunction "MIC3L_11") (pintype "bidirectional"))
    )
    (net (code "386") (name "Net-(U15-MICBIAS)") (class "Default")
      (node (ref "R32") (pin "2") (pinfunction "2_2") (pintype "passive"))
      (node (ref "U15") (pin "13") (pinfunction "MICBIAS_13") (pintype "bidirectional"))
    )
    (net (code "387") (name "Net-(U15-MICDET)") (class "Default")
      (node (ref "R34") (pin "2") (pinfunction "2_2") (pintype "passive"))
      (node (ref "U15") (pin "12") (pinfunction "MICDET_12") (pintype "bidirectional"))
    )
    (net (code "388") (name "Net-(U15-SELECT)") (class "Default")
      (node (ref "R30") (pin "2") (pinfunction "2_2") (pintype "passive"))
      (node (ref "U15") (pin "43") (pinfunction "SELECT_43") (pintype "bidirectional"))
    )
    (net (code "389") (name "Net-(U17-BYPASS)") (class "Default")
      (node (ref "C65") (pin "1") (pinfunction "1_1") (pintype "passive"))
      (node (ref "C66") (pin "2") (pinfunction "2_2") (pintype "passive"))
      (node (ref "R42") (pin "1") (pinfunction "1_1") (pintype "passive"))
      (node (ref "U17") (pin "2") (pinfunction "BYPASS_2") (pintype "passive"))
    )
    (net (code "390") (name "Net-(U17-IN+)") (class "Default")
      (node (ref "C66") (pin "1") (pinfunction "1_1") (pintype "passive"))
      (node (ref "R42") (pin "2") (pinfunction "2_2") (pintype "passive"))
      (node (ref "U17") (pin "3") (pinfunction "IN+_3") (pintype "input"))
    )
    (net (code "391") (name "Net-(U17-IN-)") (class "Default")
      (node (ref "C68") (pin "1") (pinfunction "1_1") (pintype "passive"))
      (node (ref "R41") (pin "1") (pinfunction "1_1") (pintype "passive"))
      (node (ref "R43") (pin "2") (pinfunction "2_2") (pintype "passive"))
      (node (ref "U17") (pin "4") (pinfunction "IN-_4") (pintype "input"))
    )
    (net (code "392") (name "Net-(U17-VO1)") (class "Default")
      (node (ref "C68") (pin "2") (pinfunction "2_2") (pintype "passive"))
      (node (ref "R43") (pin "1") (pinfunction "1_1") (pintype "passive"))
      (node (ref "SPKR-") (pin "TP") (pinfunction "TP_TP") (pintype "input"))
      (node (ref "U17") (pin "5") (pinfunction "VO1_5") (pintype "output"))
    )
    (net (code "393") (name "Net-(U17-VO2)") (class "Default")
      (node (ref "SPKR+") (pin "TP") (pinfunction "TP_TP") (pintype "input"))
      (node (ref "U17") (pin "8") (pinfunction "VO2_8") (pintype "output"))
    )
    (net (code "394") (name "Net-(U28-2G4_ANT1_WB)") (class "Default")
      (node (ref "CONN1") (pin "1") (pinfunction "1_1") (pintype "passive"))
      (node (ref "U28") (pin "32") (pinfunction "2G4_ANT1_WB_32") (pintype "bidirectional"))
    )
    (net (code "395") (name "Net-(U29-VCCB)") (class "Default")
      (node (ref "R78") (pin "1") (pinfunction "1_1") (pintype "passive"))
      (node (ref "U29") (pin "19") (pinfunction "VCCB_19") (pintype "power_in"))
      (node (ref "U30") (pin "8") (pinfunction "VCCB_8") (pintype "power_in"))
    )
    (net (code "396") (name "Net-(U30-B1)") (class "Default")
      (node (ref "J13") (pin "9") (pinfunction "9_9") (pintype "passive"))
      (node (ref "R80") (pin "2") (pinfunction "2_2") (pintype "passive"))
      (node (ref "U30") (pin "7") (pinfunction "B1_7") (pintype "output"))
    )
    (net (code "397") (name "Net-(U30-B2)") (class "Default")
      (node (ref "J13") (pin "10") (pinfunction "10_10") (pintype "passive"))
      (node (ref "R81") (pin "2") (pinfunction "2_2") (pintype "passive"))
      (node (ref "U30") (pin "6") (pinfunction "B2_6") (pintype "output"))
    )
    (net (code "398") (name "Net-(U31-B')") (class "Default")
      (node (ref "R91") (pin "1") (pinfunction "1_1") (pintype "passive"))
      (node (ref "U31") (pin "3") (pinfunction "B_3") (pintype "passive"))
      (node (ref "U31") (pin "4") (pinfunction "B'_4") (pintype "passive"))
    )
    (net (code "399") (name "Net-(U35-L1)") (class "Default")
      (node (ref "L11") (pin "1") (pinfunction "1_1") (pintype "passive"))
      (node (ref "U35") (pin "20") (pinfunction "L1_20") (pintype "passive"))
    )
    (net (code "400") (name "Net-(U35-L2)") (class "Default")
      (node (ref "L12") (pin "1") (pinfunction "1_1") (pintype "passive"))
      (node (ref "U35") (pin "23") (pinfunction "L2_23") (pintype "passive"))
    )
    (net (code "401") (name "Net-(U35-L3)") (class "Default")
      (node (ref "L13") (pin "1") (pinfunction "1_1") (pintype "passive"))
      (node (ref "U35") (pin "31") (pinfunction "L3_31") (pintype "passive"))
    )
    (net (code "402") (name "Net-(X2-FO)") (class "Default")
      (node (ref "R35") (pin "2") (pinfunction "2_2") (pintype "passive"))
      (node (ref "X2") (pin "3") (pinfunction "FO_3") (pintype "output"))
    )
    (net (code "403") (name "OV_RXD$12") (class "Default")
      (node (ref "J6") (pin "3") (pinfunction "3_3") (pintype "bidirectional"))
      (node (ref "U11") (pin "7") (pinfunction "B1_7") (pintype "output"))
    )
    (net (code "404") (name "OV_RXD$32") (class "Default")
      (node (ref "J11") (pin "3") (pinfunction "3_3") (pintype "bidirectional"))
      (node (ref "U27") (pin "7") (pinfunction "B1_7") (pintype "output"))
    )
    (net (code "405") (name "OV_SCL$1") (class "Default")
      (node (ref "J1") (pin "3") (pinfunction "3_3") (pintype "bidirectional"))
      (node (ref "U1") (pin "7") (pinfunction "B1_7") (pintype "output"))
    )
    (net (code "406") (name "OV_SCL$27") (class "Default")
      (node (ref "J8") (pin "3") (pinfunction "3_3") (pintype "bidirectional"))
      (node (ref "U21") (pin "7") (pinfunction "B1_7") (pintype "output"))
    )
    (net (code "407") (name "OV_SDA$1") (class "Default")
      (node (ref "J1") (pin "1") (pinfunction "1_1") (pintype "bidirectional"))
      (node (ref "U1") (pin "6") (pinfunction "B2_6") (pintype "output"))
    )
    (net (code "408") (name "OV_SDA$27") (class "Default")
      (node (ref "J8") (pin "1") (pinfunction "1_1") (pintype "bidirectional"))
      (node (ref "U21") (pin "6") (pinfunction "B2_6") (pintype "output"))
    )
    (net (code "409") (name "OV_TXD$12") (class "Default")
      (node (ref "J6") (pin "1") (pinfunction "1_1") (pintype "bidirectional"))
      (node (ref "U11") (pin "6") (pinfunction "B2_6") (pintype "output"))
    )
    (net (code "410") (name "OV_TXD$32") (class "Default")
      (node (ref "J11") (pin "1") (pinfunction "1_1") (pintype "bidirectional"))
      (node (ref "U27") (pin "6") (pinfunction "B2_6") (pintype "output"))
    )
    (net (code "411") (name "P1$37") (class "Default")
      (node (ref "J13") (pin "1") (pinfunction "1_1") (pintype "passive"))
      (node (ref "RP7") (pin "9") (pinfunction "9_9") (pintype "passive"))
      (node (ref "U29") (pin "20") (pinfunction "B1_20") (pintype "bidirectional"))
    )
    (net (code "412") (name "P2$37") (class "Default")
      (node (ref "J13") (pin "2") (pinfunction "2_2") (pintype "passive"))
      (node (ref "RP7") (pin "10") (pinfunction "10_10") (pintype "passive"))
      (node (ref "U29") (pin "18") (pinfunction "B2_18") (pintype "bidirectional"))
    )
    (net (code "413") (name "P3$37") (class "Default")
      (node (ref "J13") (pin "3") (pinfunction "3_3") (pintype "passive"))
      (node (ref "RP7") (pin "11") (pinfunction "11_11") (pintype "passive"))
      (node (ref "U29") (pin "17") (pinfunction "B3_17") (pintype "bidirectional"))
    )
    (net (code "414") (name "P4$37") (class "Default")
      (node (ref "J13") (pin "4") (pinfunction "4_4") (pintype "passive"))
      (node (ref "RP7") (pin "12") (pinfunction "12_12") (pintype "passive"))
      (node (ref "U29") (pin "16") (pinfunction "B4_16") (pintype "bidirectional"))
    )
    (net (code "415") (name "P5$37") (class "Default")
      (node (ref "J13") (pin "5") (pinfunction "5_5") (pintype "passive"))
      (node (ref "RP7") (pin "13") (pinfunction "13_13") (pintype "passive"))
      (node (ref "U29") (pin "15") (pinfunction "B5_15") (pintype "bidirectional"))
    )
    (net (code "416") (name "P6$37") (class "Default")
      (node (ref "J13") (pin "6") (pinfunction "6_6") (pintype "passive"))
      (node (ref "RP7") (pin "14") (pinfunction "14_14") (pintype "passive"))
      (node (ref "U29") (pin "14") (pinfunction "B6_14") (pintype "bidirectional"))
    )
    (net (code "417") (name "P7$37") (class "Default")
      (node (ref "J13") (pin "7") (pinfunction "7_7") (pintype "passive"))
      (node (ref "RP7") (pin "15") (pinfunction "15_15") (pintype "passive"))
      (node (ref "U29") (pin "13") (pinfunction "B7_13") (pintype "bidirectional"))
    )
    (net (code "418") (name "P8$37") (class "Default")
      (node (ref "J13") (pin "8") (pinfunction "8_8") (pintype "passive"))
      (node (ref "RP7") (pin "16") (pinfunction "16_16") (pintype "passive"))
      (node (ref "U29") (pin "12") (pinfunction "B8_12") (pintype "bidirectional"))
    )
    (net (code "419") (name "PD0$44") (class "Default")
      (node (ref "IC4") (pin "63") (pinfunction "PD0_63") (pintype "bidirectional"))
      (node (ref "R113") (pin "2") (pinfunction "2_2") (pintype "passive"))
    )
    (net (code "420") (name "PD1$44") (class "Default")
      (node (ref "IC4") (pin "62") (pinfunction "PD1_62") (pintype "bidirectional"))
      (node (ref "RP8") (pin "1") (pinfunction "1_1") (pintype "passive"))
    )
    (net (code "421") (name "PD2$44") (class "Default")
      (node (ref "IC4") (pin "61") (pinfunction "PD2_61") (pintype "bidirectional"))
      (node (ref "RP8") (pin "2") (pinfunction "2_2") (pintype "passive"))
    )
    (net (code "422") (name "PD3$44") (class "Default")
      (node (ref "IC4") (pin "60") (pinfunction "PD3_60") (pintype "bidirectional"))
      (node (ref "RP8") (pin "3") (pinfunction "3_3") (pintype "passive"))
    )
    (net (code "423") (name "PD4$44") (class "Default")
      (node (ref "IC4") (pin "59") (pinfunction "PD4_59") (pintype "bidirectional"))
      (node (ref "RP8") (pin "4") (pinfunction "4_4") (pintype "passive"))
    )
    (net (code "424") (name "PD5$44") (class "Default")
      (node (ref "IC4") (pin "58") (pinfunction "PD5_58") (pintype "bidirectional"))
      (node (ref "RP8") (pin "5") (pinfunction "5_5") (pintype "passive"))
    )
    (net (code "425") (name "PD6$44") (class "Default")
      (node (ref "IC4") (pin "55") (pinfunction "PD6_55") (pintype "bidirectional"))
      (node (ref "RP8") (pin "7") (pinfunction "7_7") (pintype "passive"))
    )
    (net (code "426") (name "PD7$44") (class "Default")
      (node (ref "IC4") (pin "54") (pinfunction "PD7_54") (pintype "bidirectional"))
      (node (ref "RP8") (pin "8") (pinfunction "8_8") (pintype "passive"))
    )
    (net (code "427") (name "PD8$44") (class "Default")
      (node (ref "IC4") (pin "53") (pinfunction "PD8_53") (pintype "bidirectional"))
      (node (ref "RP9") (pin "1") (pinfunction "1_1") (pintype "passive"))
    )
    (net (code "428") (name "PD9$44") (class "Default")
      (node (ref "IC4") (pin "52") (pinfunction "PD9_52") (pintype "bidirectional"))
      (node (ref "RP9") (pin "2") (pinfunction "2_2") (pintype "passive"))
    )
    (net (code "429") (name "PD10$44") (class "Default")
      (node (ref "IC4") (pin "51") (pinfunction "PD10_51") (pintype "bidirectional"))
      (node (ref "RP9") (pin "3") (pinfunction "3_3") (pintype "passive"))
    )
    (net (code "430") (name "PD11$44") (class "Default")
      (node (ref "IC4") (pin "50") (pinfunction "PD11_50") (pintype "bidirectional"))
      (node (ref "RP9") (pin "4") (pinfunction "4_4") (pintype "passive"))
    )
    (net (code "431") (name "PD12$44") (class "Default")
      (node (ref "IC4") (pin "47") (pinfunction "PD12_47") (pintype "bidirectional"))
      (node (ref "RP9") (pin "5") (pinfunction "5_5") (pintype "passive"))
    )
    (net (code "432") (name "PD13$44") (class "Default")
      (node (ref "IC4") (pin "46") (pinfunction "PD13_46") (pintype "bidirectional"))
      (node (ref "RP9") (pin "6") (pinfunction "6_6") (pintype "passive"))
    )
    (net (code "433") (name "PD14$44") (class "Default")
      (node (ref "IC4") (pin "45") (pinfunction "PD14_45") (pintype "bidirectional"))
      (node (ref "RP9") (pin "7") (pinfunction "7_7") (pintype "passive"))
    )
    (net (code "434") (name "PD15$44") (class "Default")
      (node (ref "IC4") (pin "44") (pinfunction "PD15_44") (pintype "bidirectional"))
      (node (ref "RP9") (pin "8") (pinfunction "8_8") (pintype "passive"))
    )
    (net (code "435") (name "PD16$44") (class "Default")
      (node (ref "IC4") (pin "43") (pinfunction "PD16_43") (pintype "bidirectional"))
      (node (ref "RP10") (pin "1") (pinfunction "1_1") (pintype "passive"))
    )
    (net (code "436") (name "PD17$44") (class "Default")
      (node (ref "IC4") (pin "42") (pinfunction "PD17_42") (pintype "bidirectional"))
      (node (ref "RP10") (pin "2") (pinfunction "2_2") (pintype "passive"))
    )
    (net (code "437") (name "PD18$44") (class "Default")
      (node (ref "IC4") (pin "41") (pinfunction "PD18_41") (pintype "bidirectional"))
      (node (ref "RP10") (pin "3") (pinfunction "3_3") (pintype "passive"))
    )
    (net (code "438") (name "PD19$44") (class "Default")
      (node (ref "IC4") (pin "40") (pinfunction "PD19_40") (pintype "bidirectional"))
      (node (ref "RP10") (pin "4") (pinfunction "4_4") (pintype "passive"))
    )
    (net (code "439") (name "PD20$44") (class "Default")
      (node (ref "IC4") (pin "39") (pinfunction "PD20_39") (pintype "bidirectional"))
      (node (ref "RP10") (pin "5") (pinfunction "5_5") (pintype "passive"))
    )
    (net (code "440") (name "PD21$44") (class "Default")
      (node (ref "IC4") (pin "38") (pinfunction "PD21_38") (pintype "bidirectional"))
      (node (ref "RP10") (pin "6") (pinfunction "6_6") (pintype "passive"))
    )
    (net (code "441") (name "PD22$44") (class "Default")
      (node (ref "IC4") (pin "37") (pinfunction "PD22_37") (pintype "bidirectional"))
      (node (ref "RP10") (pin "7") (pinfunction "7_7") (pintype "passive"))
    )
    (net (code "442") (name "PD23$44") (class "Default")
      (node (ref "IC4") (pin "36") (pinfunction "PD23_36") (pintype "bidirectional"))
      (node (ref "RP10") (pin "8") (pinfunction "8_8") (pintype "passive"))
    )
    (net (code "443") (name "PG_3.3$18") (class "Default")
      (node (ref "IC2") (pin "13") (pinfunction "PG_13") (pintype "output"))
      (node (ref "R38") (pin "1") (pinfunction "1_1") (pintype "passive"))
    )
    (net (code "444") (name "PMIC_INT$45") (class "Default")
      (node (ref "R119") (pin "1") (pinfunction "1_1") (pintype "passive"))
      (node (ref "R125") (pin "1") (pinfunction "1_1") (pintype "passive"))
      (node (ref "U35") (pin "45") (pinfunction "~{INT}_45") (pintype "open_collector"))
    )
    (net (code "445") (name "PMIC_PWR_EN$45") (class "Default")
      (node (ref "U$72") (pin "C6") (pinfunction "PMIC_POWER_EN_C6") (pintype "output"))
      (node (ref "U35") (pin "9") (pinfunction "PWR_EN_9") (pintype "input"))
    )
    (net (code "446") (name "PMIC_WAKEUP$45") (class "Default")
      (node (ref "R124") (pin "1") (pinfunction "1_1") (pintype "passive"))
      (node (ref "U$72") (pin "C5") (pinfunction "EXT_WAKEUP_C5") (pintype "input"))
      (node (ref "U35") (pin "13") (pinfunction "~{WAKEUP}_13") (pintype "open_collector"))
    )
    (net (code "447") (name "PVDD$44") (class "Default")
      (node (ref "C153") (pin "1") (pinfunction "1_1") (pintype "passive"))
      (node (ref "C159") (pin "1") (pinfunction "1_1") (pintype "passive"))
      (node (ref "FB8") (pin "2") (pinfunction "2_2") (pintype "passive"))
      (node (ref "IC4") (pin "18") (pinfunction "VDD_18") (pintype "power_in"))
    )
    (net (code "448") (name "PWM_1_5V$2") (class "Default")
      (node (ref "J2") (pin "B3") (pinfunction "B3_B3") (pintype "bidirectional"))
      (node (ref "U2") (pin "7") (pinfunction "B1_7") (pintype "output"))
    )
    (net (code "449") (name "PWM_1_5V$28") (class "Default")
      (node (ref "J9") (pin "B3") (pinfunction "B3_B3") (pintype "bidirectional"))
      (node (ref "U22") (pin "7") (pinfunction "B1_7") (pintype "output"))
    )
    (net (code "450") (name "PWM_2_5V$2") (class "Default")
      (node (ref "J2") (pin "A3") (pinfunction "A3_A3") (pintype "bidirectional"))
      (node (ref "U2") (pin "6") (pinfunction "B2_6") (pintype "output"))
    )
    (net (code "451") (name "PWM_2_5V$28") (class "Default")
      (node (ref "J9") (pin "A3") (pinfunction "A3_A3") (pintype "bidirectional"))
      (node (ref "U22") (pin "6") (pinfunction "B2_6") (pintype "output"))
    )
    (net (code "452") (name "RED0$43") (class "Default")
      (node (ref "U$68") (pin "26") (pinfunction "2A7_26") (pintype "bidirectional"))
      (node (ref "U$70") (pin "5") (pinfunction "R0_5") (pintype "output"))
    )
    (net (code "453") (name "RED1$43") (class "Default")
      (node (ref "U$68") (pin "27") (pinfunction "2A6_27") (pintype "bidirectional"))
      (node (ref "U$70") (pin "6") (pinfunction "R1_6") (pintype "output"))
    )
    (net (code "454") (name "RED2$43") (class "Default")
      (node (ref "U$68") (pin "29") (pinfunction "2A5_29") (pintype "bidirectional"))
      (node (ref "U$70") (pin "7") (pinfunction "R2_7") (pintype "output"))
    )
    (net (code "455") (name "RED3$43") (class "Default")
      (node (ref "U$68") (pin "30") (pinfunction "2A4_30") (pintype "bidirectional"))
      (node (ref "U$70") (pin "8") (pinfunction "R3_8") (pintype "output"))
    )
    (net (code "456") (name "RED4$43") (class "Default")
      (node (ref "U$68") (pin "32") (pinfunction "2A3_32") (pintype "bidirectional"))
      (node (ref "U$70") (pin "9") (pinfunction "R4_9") (pintype "output"))
    )
    (net (code "457") (name "RED5$43") (class "Default")
      (node (ref "U$68") (pin "33") (pinfunction "2A2_33") (pintype "bidirectional"))
      (node (ref "U$70") (pin "10") (pinfunction "R5_10") (pintype "output"))
    )
    (net (code "458") (name "RED6$43") (class "Default")
      (node (ref "U$68") (pin "35") (pinfunction "2A1_35") (pintype "bidirectional"))
      (node (ref "U$70") (pin "11") (pinfunction "R6_11") (pintype "output"))
    )
    (net (code "459") (name "RED7$43") (class "Default")
      (node (ref "U$68") (pin "36") (pinfunction "2A0_36") (pintype "bidirectional"))
      (node (ref "U$70") (pin "12") (pinfunction "R7_12") (pintype "output"))
    )
    (net (code "460") (name "RTC_XTAL_IN$45") (class "Default")
      (node (ref "C170") (pin "1") (pinfunction "1_1") (pintype "passive"))
      (node (ref "U$72") (pin "A6") (pinfunction "RTC_XTALIN_A6") (pintype "input"))
      (node (ref "Y4") (pin "2") (pinfunction "2_2") (pintype "passive"))
    )
    (net (code "461") (name "RTC_XTAL_OUT$45") (class "Default")
      (node (ref "C171") (pin "1") (pinfunction "1_1") (pintype "passive"))
      (node (ref "R118") (pin "2") (pinfunction "2_2") (pintype "passive"))
      (node (ref "U$72") (pin "A4") (pinfunction "RTC_XTALOUT_A4") (pintype "output"))
    )
    (net (code "462") (name "SDIO2_CLK$33") (class "Default")
      (node (ref "RP6") (pin "7") (pinfunction "7_7") (pintype "passive"))
      (node (ref "U28") (pin "8") (pinfunction "WL_SDIO_CLK_8") (pintype "bidirectional"))
    )
    (net (code "463") (name "SDIO2_CMD$33") (class "Default")
      (node (ref "RP6") (pin "8") (pinfunction "8_8") (pintype "passive"))
      (node (ref "U28") (pin "6") (pinfunction "WL_SDIO_CMD_6") (pintype "bidirectional"))
    )
    (net (code "464") (name "SDIO2_DAT0$33") (class "Default")
      (node (ref "RP6") (pin "5") (pinfunction "5_5") (pintype "passive"))
      (node (ref "U28") (pin "10") (pinfunction "WL_SDIO_D0_10") (pintype "bidirectional"))
    )
    (net (code "465") (name "SDIO2_DAT1$33") (class "Default")
      (node (ref "RP6") (pin "4") (pinfunction "4_4") (pintype "passive"))
      (node (ref "U28") (pin "11") (pinfunction "WL_SDIO_D1_11") (pintype "bidirectional"))
    )
    (net (code "466") (name "SDIO2_DAT2$33") (class "Default")
      (node (ref "RP6") (pin "2") (pinfunction "2_2") (pintype "passive"))
      (node (ref "U28") (pin "12") (pinfunction "WL_SDIO_D2_12") (pintype "bidirectional"))
    )
    (net (code "467") (name "SDIO2_DAT3$33") (class "Default")
      (node (ref "RP6") (pin "1") (pinfunction "1_1") (pintype "passive"))
      (node (ref "U28") (pin "13") (pinfunction "WL_SDIO_D3_13") (pintype "bidirectional"))
    )
    (net (code "468") (name "SQW$5") (class "Default")
      (node (ref "R3") (pin "1") (pinfunction "1_1") (pintype "passive"))
      (node (ref "U3") (pin "7") (pinfunction "SQW_7") (pintype "output"))
    )
    (net (code "469") (name "SW_3.3$18") (class "Default")
      (node (ref "IC2") (pin "14") (pinfunction "SW_14") (pintype "input"))
      (node (ref "IC2") (pin "15") (pinfunction "SW_15") (pintype "input"))
      (node (ref "L1") (pin "1") (pinfunction "1_1") (pintype "passive"))
    )
    (net (code "470") (name "TCK$39") (class "Default")
      (node (ref "IC3") (pin "76") (pinfunction "PA14_76") (pintype "bidirectional"))
      (node (ref "JTAG") (pin "4") (pinfunction "S_4") (pintype "passive"))
      (node (ref "R111") (pin "1") (pinfunction "1_1") (pintype "passive"))
    )
    (net (code "471") (name "TDI$39") (class "Default")
      (node (ref "IC3") (pin "77") (pinfunction "PA15_77") (pintype "bidirectional"))
      (node (ref "JTAG") (pin "8") (pinfunction "S_8") (pintype "passive"))
      (node (ref "R137") (pin "1") (pinfunction "1_1") (pintype "passive"))
    )
    (net (code "472") (name "TDO$39") (class "Default")
      (node (ref "IC3") (pin "89") (pinfunction "PB3_89") (pintype "bidirectional"))
      (node (ref "JTAG") (pin "6") (pinfunction "S_6") (pintype "passive"))
      (node (ref "R136") (pin "1") (pinfunction "1_1") (pintype "passive"))
    )
    (net (code "473") (name "TFADJ$44") (class "Default")
      (node (ref "IC4") (pin "19") (pinfunction "TFADJ_19") (pintype "bidirectional"))
      (node (ref "R102") (pin "1") (pinfunction "1_1") (pintype "passive"))
    )
    (net (code "474") (name "TMS$39") (class "Default")
      (node (ref "IC3") (pin "72") (pinfunction "PA13_72") (pintype "bidirectional"))
      (node (ref "JTAG") (pin "2") (pinfunction "S_2") (pintype "passive"))
      (node (ref "R63") (pin "1") (pinfunction "1_1") (pintype "passive"))
    )
    (net (code "475") (name "TSMX$43") (class "Default")
      (node (ref "U$66") (pin "8") (pinfunction "X-_8") (pintype "bidirectional"))
      (node (ref "U$70") (pin "39") (pinfunction "XL_39") (pintype "output"))
    )
    (net (code "476") (name "TSMY$43") (class "Default")
      (node (ref "U$66") (pin "9") (pinfunction "Y-_9") (pintype "bidirectional"))
      (node (ref "U$70") (pin "38") (pinfunction "YD_38") (pintype "output"))
    )
    (net (code "477") (name "TSPX$43") (class "Default")
      (node (ref "U$66") (pin "6") (pinfunction "X+_6") (pintype "bidirectional"))
      (node (ref "U$70") (pin "37") (pinfunction "XR_37") (pintype "output"))
    )
    (net (code "478") (name "TSPY$43") (class "Default")
      (node (ref "U$66") (pin "7") (pinfunction "Y+_7") (pintype "bidirectional"))
      (node (ref "U$70") (pin "40") (pinfunction "YU_40") (pintype "output"))
    )
    (net (code "479") (name "TVDD$44") (class "Default")
      (node (ref "C154") (pin "1") (pinfunction "1_1") (pintype "passive"))
      (node (ref "C160") (pin "1") (pinfunction "1_1") (pintype "passive"))
      (node (ref "C163") (pin "1") (pinfunction "1_1") (pintype "passive"))
      (node (ref "FB7") (pin "2") (pinfunction "2_2") (pintype "passive"))
      (node (ref "IC4") (pin "23") (pinfunction "VDD_23") (pintype "power_in"))
      (node (ref "IC4") (pin "29") (pinfunction "VDD_29") (pintype "power_in"))
      (node (ref "R102") (pin "2") (pinfunction "2_2") (pintype "passive"))
    )
    (net (code "480") (name "TXC+$44") (class "Default")
      (node (ref "IC4") (pin "22") (pinfunction "TXC+_22") (pintype "bidirectional"))
      (node (ref "L10") (pin "1") (pinfunction "1_1") (pintype "passive"))
    )
    (net (code "481") (name "TXC-$44") (class "Default")
      (node (ref "IC4") (pin "21") (pinfunction "TXC-_21") (pintype "bidirectional"))
      (node (ref "L10") (pin "4") (pinfunction "4_4") (pintype "passive"))
    )
    (net (code "482") (name "TXD0+$44") (class "Default")
      (node (ref "IC4") (pin "25") (pinfunction "TXD0+_25") (pintype "bidirectional"))
      (node (ref "L9") (pin "1") (pinfunction "1_1") (pintype "passive"))
    )
    (net (code "483") (name "TXD0-$44") (class "Default")
      (node (ref "IC4") (pin "24") (pinfunction "TXD0-_24") (pintype "bidirectional"))
      (node (ref "L9") (pin "4") (pinfunction "4_4") (pintype "passive"))
    )
    (net (code "484") (name "TXD1+$44") (class "Default")
      (node (ref "IC4") (pin "28") (pinfunction "TXD1+_28") (pintype "bidirectional"))
      (node (ref "L8") (pin "1") (pinfunction "1_1") (pintype "passive"))
    )
    (net (code "485") (name "TXD1-$44") (class "Default")
      (node (ref "IC4") (pin "27") (pinfunction "TXD1-_27") (pintype "bidirectional"))
      (node (ref "L8") (pin "4") (pinfunction "4_4") (pintype "passive"))
    )
    (net (code "486") (name "TXD2+$44") (class "Default")
      (node (ref "IC4") (pin "31") (pinfunction "TXD2+_31") (pintype "bidirectional"))
      (node (ref "L7") (pin "1") (pinfunction "1_1") (pintype "passive"))
    )
    (net (code "487") (name "TXD2-$44") (class "Default")
      (node (ref "IC4") (pin "30") (pinfunction "TXD2-_30") (pintype "bidirectional"))
      (node (ref "L7") (pin "4") (pinfunction "4_4") (pintype "passive"))
    )
    (net (code "488") (name "USB_CRFILT$20") (class "Default")
      (node (ref "C70") (pin "1") (pinfunction "1_1") (pintype "passive"))
      (node (ref "C71") (pin "1") (pinfunction "1_1") (pintype "passive"))
      (node (ref "U18") (pin "14") (pinfunction "CRFILT_14") (pintype "passive"))
    )
    (net (code "489") (name "USB_HS_IND$20") (class "Default")
      (node (ref "R48") (pin "2") (pinfunction "2_2") (pintype "passive"))
      (node (ref "U18") (pin "25") (pinfunction "HS_IND/CFG_SEL1_25") (pintype "passive"))
    )
    (net (code "490") (name "USB_NRESET$20") (class "Default")
      (node (ref "C74") (pin "1") (pinfunction "1_1") (pintype "passive"))
      (node (ref "R45") (pin "1") (pinfunction "1_1") (pintype "passive"))
      (node (ref "U18") (pin "26") (pinfunction "RESET_N_26") (pintype "passive"))
    )
    (net (code "491") (name "USB_PLLFILT$20") (class "Default")
      (node (ref "C72") (pin "1") (pinfunction "1_1") (pintype "passive"))
      (node (ref "C73") (pin "1") (pinfunction "1_1") (pintype "passive"))
      (node (ref "U18") (pin "34") (pinfunction "PLLFILT_34") (pintype "passive"))
    )
    (net (code "492") (name "USB_RBIAS$20") (class "Default")
      (node (ref "R46") (pin "2") (pinfunction "2_2") (pintype "passive"))
      (node (ref "U18") (pin "35") (pinfunction "RBIAS_35") (pintype "passive"))
    )
    (net (code "493") (name "USB_SCL$20") (class "Default")
      (node (ref "R47") (pin "2") (pinfunction "2_2") (pintype "passive"))
      (node (ref "U18") (pin "24") (pinfunction "SCL/CFG_SEL0_24") (pintype "passive"))
    )
    (net (code "494") (name "USB_SDA$20") (class "Default")
      (node (ref "R50") (pin "2") (pinfunction "2_2") (pintype "passive"))
      (node (ref "U18") (pin "22") (pinfunction "SDA/NON_REM1_22") (pintype "passive"))
    )
    (net (code "495") (name "USB_SUSP_IND$20") (class "Default")
      (node (ref "R49") (pin "2") (pinfunction "2_2") (pintype "passive"))
      (node (ref "U18") (pin "28") (pinfunction "SUSP_IND/NON_REM0_28") (pintype "passive"))
    )
    (net (code "496") (name "USB_XTAL1$20") (class "Default")
      (node (ref "C84") (pin "1") (pinfunction "1_1") (pintype "passive"))
      (node (ref "R51") (pin "2") (pinfunction "2_2") (pintype "passive"))
      (node (ref "U18") (pin "33") (pinfunction "XTALIN_33") (pintype "passive"))
      (node (ref "Y1") (pin "3") (pinfunction "3_3") (pintype "passive"))
    )
    (net (code "497") (name "USB_XTAL2$20") (class "Default")
      (node (ref "C83") (pin "1") (pinfunction "1_1") (pintype "passive"))
      (node (ref "R51") (pin "1") (pinfunction "1_1") (pintype "passive"))
      (node (ref "U18") (pin "32") (pinfunction "XTALOUT_32") (pintype "passive"))
      (node (ref "Y1") (pin "1") (pinfunction "1_1") (pintype "passive"))
    )
    (net (code "498") (name "VBACKUP$5") (class "Default")
      (node (ref "J3") (pin "+1") (pinfunction "+1_+1") (pintype "passive"))
      (node (ref "J3") (pin "+2") (pinfunction "+2_+2") (pintype "passive"))
      (node (ref "U3") (pin "3") (pinfunction "VBAT_3") (pintype "power_in"))
    )
    (net (code "499") (name "VBAT$39") (class "Default")
      (node (ref "IC3") (pin "6") (pinfunction "VBAT_6") (pintype "power_in"))
      (node (ref "R90") (pin "2") (pinfunction "2_2") (pintype "passive"))
    )
    (net (code "500") (name "VCC_5.0$38") (class "Default")
      (node (ref "C120") (pin "1") (pinfunction "1_1") (pintype "passive"))
      (node (ref "D19") (pin "P2") (pinfunction "P2_P2") (pintype "passive"))
      (node (ref "J14") (pin "P1") (pinfunction "VBUS_P1") (pintype "bidirectional"))
      (node (ref "R82") (pin "2") (pinfunction "2_2") (pintype "passive"))
    )
    (net (code "501") (name "VDDA$39") (class "Default")
      (node (ref "C133") (pin "1") (pinfunction "1_1") (pintype "passive"))
      (node (ref "C134") (pin "1") (pinfunction "1_1") (pintype "passive"))
      (node (ref "FB9") (pin "1") (pinfunction "1_1") (pintype "passive"))
      (node (ref "IC3") (pin "22") (pinfunction "VDDA_22") (pintype "power_in"))
      (node (ref "R84") (pin "2") (pinfunction "2_2") (pintype "passive"))
    )
    (net (code "502") (name "VDDS_DDR$45") (class "Default")
      (node (ref "C198") (pin "1") (pinfunction "1_1") (pintype "passive"))
      (node (ref "C207") (pin "1") (pinfunction "1_1") (pintype "passive"))
      (node (ref "C208") (pin "1") (pinfunction "1_1") (pintype "passive"))
      (node (ref "C209") (pin "1") (pinfunction "1_1") (pintype "passive"))
      (node (ref "C210") (pin "1") (pinfunction "1_1") (pintype "passive"))
      (node (ref "C211") (pin "1") (pinfunction "1_1") (pintype "passive"))
      (node (ref "C212") (pin "1") (pinfunction "1_1") (pintype "passive"))
      (node (ref "C228") (pin "1") (pinfunction "1_1") (pintype "passive"))
      (node (ref "C252") (pin "1") (pinfunction "1_1") (pintype "passive"))
      (node (ref "C253") (pin "1") (pinfunction "1_1") (pintype "passive"))
      (node (ref "C254") (pin "1") (pinfunction "1_1") (pintype "passive"))
      (node (ref "C255") (pin "1") (pinfunction "1_1") (pintype "passive"))
      (node (ref "C258") (pin "1") (pinfunction "1_1") (pintype "passive"))
      (node (ref "C259") (pin "1") (pinfunction "1_1") (pintype "passive"))
      (node (ref "C260") (pin "1") (pinfunction "1_1") (pintype "passive"))
      (node (ref "C261") (pin "1") (pinfunction "1_1") (pintype "passive"))
      (node (ref "C262") (pin "1") (pinfunction "1_1") (pintype "passive"))
      (node (ref "L11") (pin "2") (pinfunction "2_2") (pintype "passive"))
      (node (ref "R131") (pin "1") (pinfunction "1_1") (pintype "passive"))
      (node (ref "R134") (pin "1") (pinfunction "1_1") (pintype "passive"))
      (node (ref "U$101") (pin "A1") (pinfunction "VDDQ_A1") (pintype "power_in"))
      (node (ref "U$101") (pin "A8") (pinfunction "VDDQ_A8") (pintype "power_in"))
      (node (ref "U$101") (pin "B2") (pinfunction "VDD_B2") (pintype "power_in"))
      (node (ref "U$101") (pin "C1") (pinfunction "VDDQ_C1") (pintype "power_in"))
      (node (ref "U$101") (pin "C9") (pinfunction "VDDQ_C9") (pintype "power_in"))
      (node (ref "U$101") (pin "D2") (pinfunction "VDDQ_D2") (pintype "power_in"))
      (node (ref "U$101") (pin "D9") (pinfunction "VDD_D9") (pintype "power_in"))
      (node (ref "U$101") (pin "E9") (pinfunction "VDDQ_E9") (pintype "power_in"))
      (node (ref "U$101") (pin "F1") (pinfunction "VDDQ_F1") (pintype "power_in"))
      (node (ref "U$101") (pin "G7") (pinfunction "VDD_G7") (pintype "power_in"))
      (node (ref "U$101") (pin "H2") (pinfunction "VDDQ_H2") (pintype "power_in"))
      (node (ref "U$101") (pin "H9") (pinfunction "VDDQ_H9") (pintype "power_in"))
      (node (ref "U$101") (pin "K2") (pinfunction "VDD_K2") (pintype "power_in"))
      (node (ref "U$101") (pin "K8") (pinfunction "VDD_K8") (pintype "power_in"))
      (node (ref "U$101") (pin "N1") (pinfunction "VDD_N1") (pintype "power_in"))
      (node (ref "U$101") (pin "N9") (pinfunction "VDD_N9") (pintype "power_in"))
      (node (ref "U$101") (pin "R1") (pinfunction "VDD_R1") (pintype "power_in"))
      (node (ref "U$101") (pin "R9") (pinfunction "VDD_R9") (pintype "power_in"))
      (node (ref "U$72") (pin "E5") (pinfunction "VDDS_DDR_E5") (pintype "power_in"))
      (node (ref "U$72") (pin "F5") (pinfunction "VDDS_DDR_F5") (pintype "power_in"))
      (node (ref "U$72") (pin "G5") (pinfunction "VDDS_DDR_G5") (pintype "power_in"))
      (node (ref "U$72") (pin "H5") (pinfunction "VDDS_DDR_H5") (pintype "power_in"))
      (node (ref "U$72") (pin "J5") (pinfunction "VDDS_DDR_J5") (pintype "power_in"))
      (node (ref "U$72") (pin "K5") (pinfunction "VDDS_DDR_K5") (pintype "power_in"))
      (node (ref "U$72") (pin "L5") (pinfunction "VDDS_DDR_L5") (pintype "power_in"))
      (node (ref "U35") (pin "19") (pinfunction "VDCDC1_19") (pintype "input"))
    )
    (net (code "503") (name "VDD_1V8$45") (class "Default")
      (node (ref "C172") (pin "1") (pinfunction "1_1") (pintype "passive"))
      (node (ref "C176") (pin "1") (pinfunction "1_1") (pintype "passive"))
      (node (ref "C177") (pin "1") (pinfunction "1_1") (pintype "passive"))
      (node (ref "C178") (pin "1") (pinfunction "1_1") (pintype "passive"))
      (node (ref "C179") (pin "1") (pinfunction "1_1") (pintype "passive"))
      (node (ref "C180") (pin "1") (pinfunction "1_1") (pintype "passive"))
      (node (ref "C181") (pin "1") (pinfunction "1_1") (pintype "passive"))
      (node (ref "C182") (pin "1") (pinfunction "1_1") (pintype "passive"))
      (node (ref "C183") (pin "1") (pinfunction "1_1") (pintype "passive"))
      (node (ref "C184") (pin "1") (pinfunction "1_1") (pintype "passive"))
      (node (ref "C185") (pin "1") (pinfunction "1_1") (pintype "passive"))
      (node (ref "C186") (pin "1") (pinfunction "1_1") (pintype "passive"))
      (node (ref "C187") (pin "1") (pinfunction "1_1") (pintype "passive"))
      (node (ref "C188") (pin "1") (pinfunction "1_1") (pintype "passive"))
      (node (ref "C189") (pin "1") (pinfunction "1_1") (pintype "passive"))
      (node (ref "C190") (pin "1") (pinfunction "1_1") (pintype "passive"))
      (node (ref "C191") (pin "1") (pinfunction "1_1") (pintype "passive"))
      (node (ref "C192") (pin "1") (pinfunction "1_1") (pintype "passive"))
      (node (ref "C197") (pin "1") (pinfunction "1_1") (pintype "passive"))
      (node (ref "C201") (pin "1") (pinfunction "1_1") (pintype "passive"))
      (node (ref "C202") (pin "1") (pinfunction "1_1") (pintype "passive"))
      (node (ref "C203") (pin "1") (pinfunction "1_1") (pintype "passive"))
      (node (ref "C204") (pin "1") (pinfunction "1_1") (pintype "passive"))
      (node (ref "C205") (pin "1") (pinfunction "1_1") (pintype "passive"))
      (node (ref "C213") (pin "1") (pinfunction "1_1") (pintype "passive"))
      (node (ref "C214") (pin "1") (pinfunction "1_1") (pintype "passive"))
      (node (ref "C215") (pin "1") (pinfunction "1_1") (pintype "passive"))
      (node (ref "C216") (pin "1") (pinfunction "1_1") (pintype "passive"))
      (node (ref "C217") (pin "1") (pinfunction "1_1") (pintype "passive"))
      (node (ref "C218") (pin "1") (pinfunction "1_1") (pintype "passive"))
      (node (ref "C220") (pin "1") (pinfunction "1_1") (pintype "passive"))
      (node (ref "C232") (pin "1") (pinfunction "1_1") (pintype "passive"))
      (node (ref "FB12") (pin "1") (pinfunction "1_1") (pintype "passive"))
      (node (ref "R122") (pin "2") (pinfunction "2_2") (pintype "passive"))
      (node (ref "R123") (pin "2") (pinfunction "2_2") (pintype "passive"))
      (node (ref "R126") (pin "2") (pinfunction "2_2") (pintype "passive"))
      (node (ref "R127") (pin "2") (pinfunction "2_2") (pintype "passive"))
      (node (ref "R128") (pin "2") (pinfunction "2_2") (pintype "passive"))
      (node (ref "R130") (pin "2") (pinfunction "2_2") (pintype "passive"))
      (node (ref "U$72") (pin "D10") (pinfunction "VDDS_SRAM_MPU_BB_D10") (pintype "power_in"))
      (node (ref "U$72") (pin "E10") (pinfunction "VDDSHV6_E10") (pintype "power_in"))
      (node (ref "U$72") (pin "E11") (pinfunction "VDDSHV6_E11") (pintype "power_in"))
      (node (ref "U$72") (pin "E12") (pinfunction "VDDSHV6_E12") (pintype "power_in"))
      (node (ref "U$72") (pin "E13") (pinfunction "VDDSHV6_E13") (pintype "power_in"))
      (node (ref "U$72") (pin "E14") (pinfunction "VDDS_E14") (pintype "power_in"))
      (node (ref "U$72") (pin "E6") (pinfunction "VDDS_E6") (pintype "power_in"))
      (node (ref "U$72") (pin "E7") (pinfunction "VDDS_PLL_DDR_E7") (pintype "power_in"))
      (node (ref "U$72") (pin "E9") (pinfunction "VDDS_SRAM_CORE_BG_E9") (pintype "power_in"))
      (node (ref "U$72") (pin "F14") (pinfunction "VDDSHV6_F14") (pintype "power_in"))
      (node (ref "U$72") (pin "F9") (pinfunction "VDDS_F9") (pintype "power_in"))
      (node (ref "U$72") (pin "G14") (pinfunction "VDDSHV6_G14") (pintype "power_in"))
      (node (ref "U$72") (pin "H15") (pinfunction "VDDS_PLL_MPU_H15") (pintype "power_in"))
      (node (ref "U$72") (pin "K13") (pinfunction "VDDS_K13") (pintype "power_in"))
      (node (ref "U$72") (pin "N16") (pinfunction "VDDA1P8V_USB0_N16") (pintype "power_in"))
      (node (ref "U$72") (pin "N5") (pinfunction "VDDSHV6_N5") (pintype "power_in"))
      (node (ref "U$72") (pin "N6") (pinfunction "VDDS_N6") (pintype "power_in"))
      (node (ref "U$72") (pin "P10") (pinfunction "VDDSHV2_P10") (pintype "power_in"))
      (node (ref "U$72") (pin "P11") (pinfunction "VDDSHV2_P11") (pintype "power_in"))
      (node (ref "U$72") (pin "P12") (pinfunction "VDDSHV3_P12") (pintype "power_in"))
      (node (ref "U$72") (pin "P13") (pinfunction "VDDSHV3_P13") (pintype "power_in"))
      (node (ref "U$72") (pin "P14") (pinfunction "VDDS_P14") (pintype "power_in"))
      (node (ref "U$72") (pin "P5") (pinfunction "VDDSHV6_P5") (pintype "power_in"))
      (node (ref "U$72") (pin "P6") (pinfunction "VDDSHV6_P6") (pintype "power_in"))
      (node (ref "U$72") (pin "P7") (pinfunction "VDDSHV1_P7") (pintype "power_in"))
      (node (ref "U$72") (pin "P8") (pinfunction "VDDSHV1_P8") (pintype "power_in"))
      (node (ref "U$72") (pin "P9") (pinfunction "VDDS_P9") (pintype "power_in"))
      (node (ref "U$72") (pin "R10") (pinfunction "VDDS_PLL_CORE_LCD_R10") (pintype "power_in"))
      (node (ref "U$72") (pin "R11") (pinfunction "VDDS_OSC_R11") (pintype "power_in"))
      (node (ref "U$72") (pin "R16") (pinfunction "VDDA1P8V_USB1_R16") (pintype "power_in"))
      (node (ref "U$79") (pin "P1") (pinfunction "P$1_P1") (pintype "bidirectional"))
      (node (ref "U$79") (pin "P2") (pinfunction "P$2_P2") (pintype "bidirectional"))
      (node (ref "U$79") (pin "P3") (pinfunction "P$3_P3") (pintype "bidirectional"))
      (node (ref "U$80") (pin "P1") (pinfunction "P$1_P1") (pintype "bidirectional"))
      (node (ref "U$80") (pin "P2") (pinfunction "P$2_P2") (pintype "bidirectional"))
      (node (ref "U$80") (pin "P3") (pinfunction "P$3_P3") (pintype "bidirectional"))
      (node (ref "U$81") (pin "P1") (pinfunction "P$1_P1") (pintype "bidirectional"))
      (node (ref "U$82") (pin "P3") (pinfunction "P$3_P3") (pintype "bidirectional"))
      (node (ref "U34") (pin "8") (pinfunction "VCC_8") (pintype "power_in"))
      (node (ref "U35") (pin "40") (pinfunction "LS1_OUT_40") (pintype "output"))
    )
    (net (code "504") (name "VDD_3V3$45") (class "Default")
      (node (ref "C173") (pin "1") (pinfunction "1_1") (pintype "passive"))
      (node (ref "C193") (pin "1") (pinfunction "1_1") (pintype "passive"))
      (node (ref "C194") (pin "1") (pinfunction "1_1") (pintype "passive"))
      (node (ref "C195") (pin "1") (pinfunction "1_1") (pintype "passive"))
      (node (ref "C196") (pin "1") (pinfunction "1_1") (pintype "passive"))
      (node (ref "C199") (pin "1") (pinfunction "1_1") (pintype "passive"))
      (node (ref "C200") (pin "1") (pinfunction "1_1") (pintype "passive"))
      (node (ref "C206") (pin "1") (pinfunction "1_1") (pintype "passive"))
      (node (ref "C233") (pin "1") (pinfunction "1_1") (pintype "passive"))
      (node (ref "U$72") (pin "H14") (pinfunction "VDDSHV4_H14") (pintype "power_in"))
      (node (ref "U$72") (pin "J14") (pinfunction "VDDSHV4_J14") (pintype "power_in"))
      (node (ref "U$72") (pin "K14") (pinfunction "VDDSHV5_K14") (pintype "power_in"))
      (node (ref "U$72") (pin "L14") (pinfunction "VDDSHV5_L14") (pintype "power_in"))
      (node (ref "U$72") (pin "N15") (pinfunction "VDDA3P3V_USB0_N15") (pintype "power_in"))
      (node (ref "U$72") (pin "R15") (pinfunction "VDDA3P3V_USB1_R15") (pintype "power_in"))
      (node (ref "U35") (pin "43") (pinfunction "LS2_OUT_43") (pintype "output"))
    )
    (net (code "505") (name "VDD_CORE$45") (class "Default")
      (node (ref "C230") (pin "1") (pinfunction "1_1") (pintype "passive"))
      (node (ref "C238") (pin "1") (pinfunction "1_1") (pintype "passive"))
      (node (ref "C239") (pin "1") (pinfunction "1_1") (pintype "passive"))
      (node (ref "C240") (pin "1") (pinfunction "1_1") (pintype "passive"))
      (node (ref "C241") (pin "1") (pinfunction "1_1") (pintype "passive"))
      (node (ref "C242") (pin "1") (pinfunction "1_1") (pintype "passive"))
      (node (ref "C243") (pin "1") (pinfunction "1_1") (pintype "passive"))
      (node (ref "C244") (pin "1") (pinfunction "1_1") (pintype "passive"))
      (node (ref "C245") (pin "1") (pinfunction "1_1") (pintype "passive"))
      (node (ref "L13") (pin "2") (pinfunction "2_2") (pintype "passive"))
      (node (ref "U$72") (pin "F6") (pinfunction "VDD_CORE_F6") (pintype "power_in"))
      (node (ref "U$72") (pin "F7") (pinfunction "VDD_CORE_F7") (pintype "power_in"))
      (node (ref "U$72") (pin "G10") (pinfunction "VDD_CORE_G10") (pintype "power_in"))
      (node (ref "U$72") (pin "G6") (pinfunction "VDD_CORE_G6") (pintype "power_in"))
      (node (ref "U$72") (pin "G7") (pinfunction "VDD_CORE_G7") (pintype "power_in"))
      (node (ref "U$72") (pin "H11") (pinfunction "VDD_CORE_H11") (pintype "power_in"))
      (node (ref "U$72") (pin "J12") (pinfunction "VDD_CORE_J12") (pintype "power_in"))
      (node (ref "U$72") (pin "K12") (pinfunction "VDD_CORE_K12") (pintype "power_in"))
      (node (ref "U$72") (pin "K6") (pinfunction "VDD_CORE_K6") (pintype "power_in"))
      (node (ref "U$72") (pin "K8") (pinfunction "VDD_CORE_K8") (pintype "power_in"))
      (node (ref "U$72") (pin "L6") (pinfunction "VDD_CORE_L6") (pintype "power_in"))
      (node (ref "U$72") (pin "L7") (pinfunction "VDD_CORE_L7") (pintype "power_in"))
      (node (ref "U$72") (pin "L8") (pinfunction "VDD_CORE_L8") (pintype "power_in"))
      (node (ref "U$72") (pin "L9") (pinfunction "VDD_CORE_L9") (pintype "power_in"))
      (node (ref "U$72") (pin "M11") (pinfunction "VDD_CORE_M11") (pintype "power_in"))
      (node (ref "U$72") (pin "M13") (pinfunction "VDD_CORE_M13") (pintype "power_in"))
      (node (ref "U$72") (pin "N12") (pinfunction "VDD_CORE_N12") (pintype "power_in"))
      (node (ref "U$72") (pin "N13") (pinfunction "VDD_CORE_N13") (pintype "power_in"))
      (node (ref "U$72") (pin "N8") (pinfunction "VDD_CORE_N8") (pintype "power_in"))
      (node (ref "U$72") (pin "N9") (pinfunction "VDD_CORE_N9") (pintype "power_in"))
      (node (ref "U35") (pin "29") (pinfunction "VDCDC3_29") (pintype "input"))
    )
    (net (code "506") (name "VDD_MPU$45") (class "Default")
      (node (ref "C231") (pin "1") (pinfunction "1_1") (pintype "passive"))
      (node (ref "C246") (pin "1") (pinfunction "1_1") (pintype "passive"))
      (node (ref "C247") (pin "1") (pinfunction "1_1") (pintype "passive"))
      (node (ref "C248") (pin "1") (pinfunction "1_1") (pintype "passive"))
      (node (ref "C249") (pin "1") (pinfunction "1_1") (pintype "passive"))
      (node (ref "C250") (pin "1") (pinfunction "1_1") (pintype "passive"))
      (node (ref "L12") (pin "2") (pinfunction "2_2") (pintype "passive"))
      (node (ref "U$72") (pin "F10") (pinfunction "VDD_MPU_F10") (pintype "power_in"))
      (node (ref "U$72") (pin "F11") (pinfunction "VDD_MPU_F11") (pintype "power_in"))
      (node (ref "U$72") (pin "F12") (pinfunction "VDD_MPU_F12") (pintype "power_in"))
      (node (ref "U$72") (pin "F13") (pinfunction "VDD_MPU_F13") (pintype "power_in"))
      (node (ref "U$72") (pin "G13") (pinfunction "VDD_MPU_G13") (pintype "power_in"))
      (node (ref "U$72") (pin "H13") (pinfunction "VDD_MPU_H13") (pintype "power_in"))
      (node (ref "U$72") (pin "J13") (pinfunction "VDD_MPU_J13") (pintype "power_in"))
      (node (ref "U35") (pin "24") (pinfunction "VDCDC2_24") (pintype "input"))
    )
    (net (code "507") (name "VLDO2$45") (class "Default")
      (node (ref "C236") (pin "1") (pinfunction "1_1") (pintype "passive"))
      (node (ref "U35") (pin "1") (pinfunction "VLDO2_1") (pintype "output"))
    )
    (net (code "508") (name "VPP") (class "Default")
      (node (ref "U$72") (pin "M5") (pinfunction "VPP_M5") (pintype "power_in"))
    )
    (net (code "509") (name "VREF$43") (class "Default")
      (node (ref "C145") (pin "1") (pinfunction "1_1") (pintype "passive"))
      (node (ref "U$66") (pin "13") (pinfunction "VREF_13") (pintype "bidirectional"))
    )
    (net (code "510") (name "VREFP$39") (class "Default")
      (node (ref "C131") (pin "1") (pinfunction "1_1") (pintype "passive"))
      (node (ref "C132") (pin "1") (pinfunction "1_1") (pintype "passive"))
      (node (ref "IC3") (pin "21") (pinfunction "VREF+_21") (pintype "input"))
      (node (ref "R84") (pin "1") (pinfunction "1_1") (pintype "passive"))
    )
    (net (code "511") (name "VRTC$45") (class "Default")
      (node (ref "C219") (pin "1") (pinfunction "1_1") (pintype "passive"))
      (node (ref "C237") (pin "1") (pinfunction "1_1") (pintype "passive"))
      (node (ref "R124") (pin "2") (pinfunction "2_2") (pintype "passive"))
      (node (ref "R125") (pin "2") (pinfunction "2_2") (pintype "passive"))
      (node (ref "U$72") (pin "D7") (pinfunction "VDDS_RTC_D7") (pintype "power_in"))
      (node (ref "U35") (pin "18") (pinfunction "VIO_18") (pintype "input"))
      (node (ref "U35") (pin "3") (pinfunction "VLDO1_3") (pintype "output"))
    )
    (net (code "512") (name "VSS_OSC$45") (class "Default")
      (node (ref "C168") (pin "2") (pinfunction "2_2") (pintype "passive"))
      (node (ref "C169") (pin "2") (pinfunction "2_2") (pintype "passive"))
      (node (ref "U$72") (pin "V11") (pinfunction "VSS_OSC_V11") (pintype "power_in"))
      (node (ref "Y3") (pin "2") (pinfunction "2_2") (pintype "passive"))
      (node (ref "Y3") (pin "4") (pinfunction "4_4") (pintype "passive"))
    )
    (net (code "513") (name "VSS_RTC$45") (class "Default")
      (node (ref "C170") (pin "2") (pinfunction "2_2") (pintype "passive"))
      (node (ref "C171") (pin "2") (pinfunction "2_2") (pintype "passive"))
      (node (ref "U$72") (pin "A5") (pinfunction "VSS_RTC_A5") (pintype "power_in"))
    )
    (net (code "514") (name "VSYNC$44") (class "Default")
      (node (ref "IC4") (pin "5") (pinfunction "VSYNC_5") (pintype "bidirectional"))
      (node (ref "R116") (pin "2") (pinfunction "2_2") (pintype "passive"))
    )
    (net (code "515") (name "V_POWER$21") (class "Default")
      (node (ref "C86") (pin "1") (pinfunction "1_1") (pintype "passive"))
      (node (ref "C87") (pin "1") (pinfunction "1_1") (pintype "passive"))
      (node (ref "R52") (pin "2") (pinfunction "2_2") (pintype "passive"))
      (node (ref "U$27") (pin "7") (pinfunction "VIN_7") (pintype "bidirectional"))
    )
    (net (code "516") (name "V_SYS$45") (class "Default")
      (node (ref "C222") (pin "1") (pinfunction "1_1") (pintype "passive"))
      (node (ref "C226") (pin "1") (pinfunction "1_1") (pintype "passive"))
      (node (ref "C227") (pin "1") (pinfunction "1_1") (pintype "passive"))
      (node (ref "C229") (pin "1") (pinfunction "1_1") (pintype "passive"))
      (node (ref "C235") (pin "1") (pinfunction "1_1") (pintype "passive"))
      (node (ref "L14") (pin "1") (pinfunction "1_1") (pintype "passive"))
      (node (ref "U35") (pin "2") (pinfunction "VINLDO_2") (pintype "input"))
      (node (ref "U35") (pin "21") (pinfunction "VIN_DCDC1_21") (pintype "input"))
      (node (ref "U35") (pin "22") (pinfunction "VIN_DCDC2_22") (pintype "input"))
      (node (ref "U35") (pin "32") (pinfunction "VIN_DCDC3_32") (pintype "input"))
      (node (ref "U35") (pin "39") (pinfunction "LS1_IN_39") (pintype "input"))
      (node (ref "U35") (pin "42") (pinfunction "LS2_IN_42") (pintype "input"))
      (node (ref "U35") (pin "7") (pinfunction "SYS1_7") (pintype "output"))
      (node (ref "U35") (pin "8") (pinfunction "SYS2_8") (pintype "output"))
    )
    (net (code "517") (name "WLAN_VBAT_IN$33") (class "Default")
      (node (ref "C142") (pin "1") (pinfunction "1_1") (pintype "passive"))
      (node (ref "C143") (pin "1") (pinfunction "1_1") (pintype "passive"))
      (node (ref "FB5") (pin "2") (pinfunction "2_2") (pintype "passive"))
      (node (ref "U28") (pin "46") (pinfunction "VBAT_46") (pintype "bidirectional"))
      (node (ref "U28") (pin "47") (pinfunction "VBAT_47") (pintype "bidirectional"))
    )
    (net (code "518") (name "WLAN_VIO_IN$33") (class "Default")
      (node (ref "C115") (pin "1") (pinfunction "1_1") (pintype "passive"))
      (node (ref "C174") (pin "1") (pinfunction "1_1") (pintype "passive"))
      (node (ref "C175") (pin "1") (pinfunction "1_1") (pintype "passive"))
      (node (ref "FB6") (pin "2") (pinfunction "2_2") (pintype "passive"))
      (node (ref "Q5") (pin "1") (pinfunction "OE_1") (pintype "input"))
      (node (ref "Q5") (pin "4") (pinfunction "VCC_4") (pintype "power_in"))
      (node (ref "U28") (pin "38") (pinfunction "VIO_38") (pintype "bidirectional"))
    )
    (net (code "519") (name "WLDB$33") (class "Default")
      (node (ref "U28") (pin "42") (pinfunction "WL_UART_DBG_42") (pintype "bidirectional"))
      (node (ref "WLDB") (pin "1") (pinfunction "TP_1") (pintype "bidirectional"))
    )
    (net (code "520") (name "WLRX$33") (class "Default")
      (node (ref "U28") (pin "26") (pinfunction "GPIO_2_26") (pintype "bidirectional"))
      (node (ref "WLRX") (pin "1") (pinfunction "TP_1") (pintype "bidirectional"))
    )
    (net (code "521") (name "WLTX$33") (class "Default")
      (node (ref "U28") (pin "27") (pinfunction "GPIO_1_27") (pintype "bidirectional"))
      (node (ref "WLTX") (pin "1") (pinfunction "TP_1") (pintype "bidirectional"))
    )
    (net (code "522") (name "X1$5") (class "Default")
      (node (ref "U3") (pin "1") (pinfunction "X1_1") (pintype "input"))
      (node (ref "X1") (pin "2") (pinfunction "2_2") (pintype "passive"))
    )
    (net (code "523") (name "X2$5") (class "Default")
      (node (ref "U3") (pin "2") (pinfunction "X2_2") (pintype "input"))
      (node (ref "X1") (pin "1") (pinfunction "1_1") (pintype "passive"))
    )
    (net (code "524") (name "XTAL_IN$45") (class "Default")
      (node (ref "C168") (pin "1") (pinfunction "1_1") (pintype "passive"))
      (node (ref "U$72") (pin "V10") (pinfunction "XTALIN_V10") (pintype "input"))
      (node (ref "Y3") (pin "1") (pinfunction "1_1") (pintype "passive"))
    )
    (net (code "525") (name "XTAL_OUT$45") (class "Default")
      (node (ref "C169") (pin "1") (pinfunction "1_1") (pintype "passive"))
      (node (ref "U$72") (pin "U11") (pinfunction "XTALOUT_U11") (pintype "output"))
      (node (ref "Y3") (pin "3") (pinfunction "3_3") (pintype "passive"))
    )
    (net (code "526") (name "ZQ$45") (class "Default")
      (node (ref "R133") (pin "1") (pinfunction "1_1") (pintype "passive"))
      (node (ref "U$101") (pin "L8") (pinfunction "ZQ_L8") (pintype "power_in"))
    )
    (net (code "527") (name "unconnected-(IC1-NC-Pad1)") (class "Default")
      (node (ref "IC1") (pin "1") (pinfunction "NC_1") (pintype "no_connect"))
    )
    (net (code "528") (name "unconnected-(IC1-NC-Pad3)") (class "Default")
      (node (ref "IC1") (pin "3") (pinfunction "NC_3") (pintype "no_connect"))
    )
    (net (code "529") (name "unconnected-(IC1-NC-Pad9)") (class "Default")
      (node (ref "IC1") (pin "9") (pinfunction "NC_9") (pintype "no_connect"))
    )
    (net (code "530") (name "unconnected-(IC1-NC-Pad15)") (class "Default")
      (node (ref "IC1") (pin "15") (pinfunction "NC_15") (pintype "no_connect"))
    )
    (net (code "531") (name "unconnected-(IC1-NC-Pad16)") (class "Default")
      (node (ref "IC1") (pin "16") (pinfunction "NC_16") (pintype "no_connect"))
    )
    (net (code "532") (name "unconnected-(IC1-VFB-Pad4)") (class "Default")
      (node (ref "IC1") (pin "4") (pinfunction "VFB_4") (pintype "passive"))
    )
    (net (code "533") (name "unconnected-(IC3F-PB4-Pad90)") (class "Default")
      (node (ref "IC3") (pin "90") (pinfunction "PB4_90") (pintype "bidirectional"))
    )
    (net (code "534") (name "unconnected-(IC3F-PB5-Pad91)") (class "Default")
      (node (ref "IC3") (pin "91") (pinfunction "PB5_91") (pintype "bidirectional"))
    )
    (net (code "535") (name "unconnected-(IC3K-PE8-Pad39)") (class "Default")
      (node (ref "IC3") (pin "39") (pinfunction "PE8_39") (pintype "bidirectional"))
    )
    (net (code "536") (name "unconnected-(IC3K-PE10-Pad41)") (class "Default")
      (node (ref "IC3") (pin "41") (pinfunction "PE10_41") (pintype "bidirectional"))
    )
    (net (code "537") (name "unconnected-(IC3L-PE7-Pad38)") (class "Default")
      (node (ref "IC3") (pin "38") (pinfunction "PE7_38") (pintype "bidirectional"))
    )
    (net (code "538") (name "unconnected-(IC4-DK1-Pad8)") (class "Default")
      (node (ref "IC4") (pin "8") (pinfunction "DK1_8") (pintype "bidirectional"))
    )
    (net (code "539") (name "unconnected-(IC4-DK2-Pad7)") (class "Default")
      (node (ref "IC4") (pin "7") (pinfunction "DK2_7") (pintype "bidirectional"))
    )
    (net (code "540") (name "unconnected-(IC4-DK3-Pad6)") (class "Default")
      (node (ref "IC4") (pin "6") (pinfunction "DK3_6") (pintype "bidirectional"))
    )
    (net (code "541") (name "unconnected-(IC4-NC-Pad49)") (class "Default")
      (node (ref "IC4") (pin "49") (pinfunction "NC_49") (pintype "bidirectional"))
    )
    (net (code "542") (name "unconnected-(J10-ID-PadP4)") (class "Default")
      (node (ref "J10") (pin "P4") (pinfunction "ID_P4") (pintype "bidirectional"))
    )
    (net (code "543") (name "unconnected-(J10-VBUS-PadP1)") (class "Default")
      (node (ref "J10") (pin "P1") (pinfunction "VBUS_P1") (pintype "bidirectional"))
    )
    (net (code "544") (name "unconnected-(J14-ID-PadP4)") (class "Default")
      (node (ref "J14") (pin "P4") (pinfunction "ID_P4") (pintype "bidirectional"))
    )
    (net (code "545") (name "unconnected-(J15-13-Pad15)") (class "Default")
      (node (ref "J15") (pin "15") (pinfunction "13_15") (pintype "passive"))
    )
    (net (code "546") (name "unconnected-(J15-14-Pad2)") (class "Default")
      (node (ref "J15") (pin "2") (pinfunction "14_2") (pintype "passive"))
    )
    (net (code "547") (name "unconnected-(J15-19-Pad1)") (class "Default")
      (node (ref "J15") (pin "1") (pinfunction "19_1") (pintype "passive"))
    )
    (net (code "548") (name "unconnected-(JTAGH-S-Pad7)") (class "Default")
      (node (ref "JTAG") (pin "7") (pinfunction "S_7") (pintype "passive"))
    )
    (net (code "549") (name "unconnected-(RP1-Pad3)") (class "Default")
      (node (ref "RP1") (pin "3") (pinfunction "3_3") (pintype "passive"))
    )
    (net (code "550") (name "unconnected-(RP1-Pad4)") (class "Default")
      (node (ref "RP1") (pin "4") (pinfunction "4_4") (pintype "passive"))
    )
    (net (code "551") (name "unconnected-(RP1-Pad13)") (class "Default")
      (node (ref "RP1") (pin "13") (pinfunction "13_13") (pintype "passive"))
    )
    (net (code "552") (name "unconnected-(RP1-Pad14)") (class "Default")
      (node (ref "RP1") (pin "14") (pinfunction "14_14") (pintype "passive"))
    )
    (net (code "553") (name "unconnected-(RP2-Pad9)") (class "Default")
      (node (ref "RP2") (pin "9") (pinfunction "9_9") (pintype "passive"))
    )
    (net (code "554") (name "unconnected-(RP2-Pad10)") (class "Default")
      (node (ref "RP2") (pin "10") (pinfunction "10_10") (pintype "passive"))
    )
    (net (code "555") (name "unconnected-(RP4-Pad4)") (class "Default")
      (node (ref "RP4") (pin "4") (pinfunction "4_4") (pintype "passive"))
    )
    (net (code "556") (name "unconnected-(RP4-Pad7)") (class "Default")
      (node (ref "RP4") (pin "7") (pinfunction "7_7") (pintype "passive"))
    )
    (net (code "557") (name "unconnected-(RP4-Pad8)") (class "Default")
      (node (ref "RP4") (pin "8") (pinfunction "8_8") (pintype "passive"))
    )
    (net (code "558") (name "unconnected-(RP4-Pad9)") (class "Default")
      (node (ref "RP4") (pin "9") (pinfunction "9_9") (pintype "passive"))
    )
    (net (code "559") (name "unconnected-(RP4-Pad10)") (class "Default")
      (node (ref "RP4") (pin "10") (pinfunction "10_10") (pintype "passive"))
    )
    (net (code "560") (name "unconnected-(RP4-Pad13)") (class "Default")
      (node (ref "RP4") (pin "13") (pinfunction "13_13") (pintype "passive"))
    )
    (net (code "561") (name "unconnected-(RP5-Pad3)") (class "Default")
      (node (ref "RP5") (pin "3") (pinfunction "3_3") (pintype "passive"))
    )
    (net (code "562") (name "unconnected-(RP5-Pad6)") (class "Default")
      (node (ref "RP5") (pin "6") (pinfunction "6_6") (pintype "passive"))
    )
    (net (code "563") (name "unconnected-(RP6-Pad3)") (class "Default")
      (node (ref "RP6") (pin "3") (pinfunction "3_3") (pintype "passive"))
    )
    (net (code "564") (name "unconnected-(RP6-Pad6)") (class "Default")
      (node (ref "RP6") (pin "6") (pinfunction "6_6") (pintype "passive"))
    )
    (net (code "565") (name "unconnected-(RP6-Pad11)") (class "Default")
      (node (ref "RP6") (pin "11") (pinfunction "11_11") (pintype "passive"))
    )
    (net (code "566") (name "unconnected-(RP6-Pad14)") (class "Default")
      (node (ref "RP6") (pin "14") (pinfunction "14_14") (pintype "passive"))
    )
    (net (code "567") (name "unconnected-(S1-A'-PadA@2)") (class "Default")
      (node (ref "S1") (pin "A@2") (pinfunction "A'_A@2") (pintype "passive"))
    )
    (net (code "568") (name "unconnected-(S1-B-PadB@1)") (class "Default")
      (node (ref "S1") (pin "B@1") (pinfunction "B_B@1") (pintype "passive"))
    )
    (net (code "569") (name "unconnected-(S2-A'-PadA@2)") (class "Default")
      (node (ref "S2") (pin "A@2") (pinfunction "A'_A@2") (pintype "passive"))
    )
    (net (code "570") (name "unconnected-(S2-B-PadB@1)") (class "Default")
      (node (ref "S2") (pin "B@1") (pinfunction "B_B@1") (pintype "passive"))
    )
    (net (code "571") (name "unconnected-(U$27-ENA-Pad5)") (class "Default")
      (node (ref "U$27") (pin "5") (pinfunction "ENA_5") (pintype "bidirectional"))
    )
    (net (code "572") (name "unconnected-(U$27-NC1-Pad2)") (class "Default")
      (node (ref "U$27") (pin "2") (pinfunction "NC1_2") (pintype "bidirectional"))
    )
    (net (code "573") (name "unconnected-(U$27-NC2-Pad3)") (class "Default")
      (node (ref "U$27") (pin "3") (pinfunction "NC2_3") (pintype "bidirectional"))
    )
    (net (code "574") (name "unconnected-(U$30-SHIELD1-PadCD1)") (class "Default")
      (node (ref "U$30") (pin "CD1") (pinfunction "SHIELD1_CD1") (pintype "bidirectional"))
    )
    (net (code "575") (name "unconnected-(U$30-SHIELD2-PadCD2)") (class "Default")
      (node (ref "U$30") (pin "CD2") (pinfunction "SHIELD2_CD2") (pintype "bidirectional"))
    )
    (net (code "576") (name "unconnected-(U$66-AUX-Pad12)") (class "Default")
      (node (ref "U$66") (pin "12") (pinfunction "AUX_12") (pintype "bidirectional"))
    )
    (net (code "577") (name "unconnected-(U$66-VBAT-Pad11)") (class "Default")
      (node (ref "U$66") (pin "11") (pinfunction "VBAT_11") (pintype "bidirectional"))
    )
    (net (code "578") (name "unconnected-(U$69C-1A0-Pad47)") (class "Default")
      (node (ref "U$69") (pin "47") (pinfunction "1A0_47") (pintype "bidirectional"))
    )
    (net (code "579") (name "unconnected-(U$69C-1A1-Pad46)") (class "Default")
      (node (ref "U$69") (pin "46") (pinfunction "1A1_46") (pintype "bidirectional"))
    )
    (net (code "580") (name "unconnected-(U$69C-1A2-Pad44)") (class "Default")
      (node (ref "U$69") (pin "44") (pinfunction "1A2_44") (pintype "bidirectional"))
    )
    (net (code "581") (name "unconnected-(U$69C-1A3-Pad43)") (class "Default")
      (node (ref "U$69") (pin "43") (pinfunction "1A3_43") (pintype "bidirectional"))
    )
    (net (code "582") (name "unconnected-(U$69C-1A5-Pad40)") (class "Default")
      (node (ref "U$69") (pin "40") (pinfunction "1A5_40") (pintype "bidirectional"))
    )
    (net (code "583") (name "unconnected-(U$69C-1A7-Pad37)") (class "Default")
      (node (ref "U$69") (pin "37") (pinfunction "1A7_37") (pintype "bidirectional"))
    )
    (net (code "584") (name "unconnected-(U$69C-1B0-Pad2)") (class "Default")
      (node (ref "U$69") (pin "2") (pinfunction "1B0_2") (pintype "bidirectional"))
    )
    (net (code "585") (name "unconnected-(U$69C-1B1-Pad3)") (class "Default")
      (node (ref "U$69") (pin "3") (pinfunction "1B1_3") (pintype "bidirectional"))
    )
    (net (code "586") (name "unconnected-(U$69C-1B2-Pad5)") (class "Default")
      (node (ref "U$69") (pin "5") (pinfunction "1B2_5") (pintype "bidirectional"))
    )
    (net (code "587") (name "unconnected-(U$69C-1B3-Pad6)") (class "Default")
      (node (ref "U$69") (pin "6") (pinfunction "1B3_6") (pintype "bidirectional"))
    )
    (net (code "588") (name "unconnected-(U$69C-1B5-Pad9)") (class "Default")
      (node (ref "U$69") (pin "9") (pinfunction "1B5_9") (pintype "bidirectional"))
    )
    (net (code "589") (name "unconnected-(U$69C-1B7-Pad12)") (class "Default")
      (node (ref "U$69") (pin "12") (pinfunction "1B7_12") (pintype "bidirectional"))
    )
    (net (code "590") (name "unconnected-(U$69C-2A0-Pad36)") (class "Default")
      (node (ref "U$69") (pin "36") (pinfunction "2A0_36") (pintype "bidirectional"))
    )
    (net (code "591") (name "unconnected-(U$69C-2A1-Pad35)") (class "Default")
      (node (ref "U$69") (pin "35") (pinfunction "2A1_35") (pintype "bidirectional"))
    )
    (net (code "592") (name "unconnected-(U$69C-2A2-Pad33)") (class "Default")
      (node (ref "U$69") (pin "33") (pinfunction "2A2_33") (pintype "bidirectional"))
    )
    (net (code "593") (name "unconnected-(U$69C-2A3-Pad32)") (class "Default")
      (node (ref "U$69") (pin "32") (pinfunction "2A3_32") (pintype "bidirectional"))
    )
    (net (code "594") (name "unconnected-(U$69C-2A4-Pad30)") (class "Default")
      (node (ref "U$69") (pin "30") (pinfunction "2A4_30") (pintype "bidirectional"))
    )
    (net (code "595") (name "unconnected-(U$69C-2A5-Pad29)") (class "Default")
      (node (ref "U$69") (pin "29") (pinfunction "2A5_29") (pintype "bidirectional"))
    )
    (net (code "596") (name "unconnected-(U$69C-2A6-Pad27)") (class "Default")
      (node (ref "U$69") (pin "27") (pinfunction "2A6_27") (pintype "bidirectional"))
    )
    (net (code "597") (name "unconnected-(U$69C-2A7-Pad26)") (class "Default")
      (node (ref "U$69") (pin "26") (pinfunction "2A7_26") (pintype "bidirectional"))
    )
    (net (code "598") (name "unconnected-(U$69C-2B0-Pad13)") (class "Default")
      (node (ref "U$69") (pin "13") (pinfunction "2B0_13") (pintype "bidirectional"))
    )
    (net (code "599") (name "unconnected-(U$69C-2B1-Pad14)") (class "Default")
      (node (ref "U$69") (pin "14") (pinfunction "2B1_14") (pintype "bidirectional"))
    )
    (net (code "600") (name "unconnected-(U$69C-2B2-Pad16)") (class "Default")
      (node (ref "U$69") (pin "16") (pinfunction "2B2_16") (pintype "bidirectional"))
    )
    (net (code "601") (name "unconnected-(U$69C-2B3-Pad17)") (class "Default")
      (node (ref "U$69") (pin "17") (pinfunction "2B3_17") (pintype "bidirectional"))
    )
    (net (code "602") (name "unconnected-(U$69C-2B4-Pad19)") (class "Default")
      (node (ref "U$69") (pin "19") (pinfunction "2B4_19") (pintype "bidirectional"))
    )
    (net (code "603") (name "unconnected-(U$69C-2B5-Pad20)") (class "Default")
      (node (ref "U$69") (pin "20") (pinfunction "2B5_20") (pintype "bidirectional"))
    )
    (net (code "604") (name "unconnected-(U$69C-2B6-Pad22)") (class "Default")
      (node (ref "U$69") (pin "22") (pinfunction "2B6_22") (pintype "bidirectional"))
    )
    (net (code "605") (name "unconnected-(U$69C-2B7-Pad23)") (class "Default")
      (node (ref "U$69") (pin "23") (pinfunction "2B7_23") (pintype "bidirectional"))
    )
    (net (code "606") (name "unconnected-(U$70-AVDD-Pad35)") (class "Default")
      (node (ref "U$70") (pin "35") (pinfunction "AVDD_35") (pintype "no_connect"))
    )
    (net (code "607") (name "unconnected-(U$72A-VDD_MPU_MON-PadA2)") (class "Default")
      (node (ref "U$72") (pin "A2") (pinfunction "VDD_MPU_MON_A2") (pintype "bidirectional"))
    )
    (net (code "608") (name "unconnected-(U$72A-WARMRSTN-PadA10)") (class "Default")
      (node (ref "U$72") (pin "A10") (pinfunction "WARMRSTN_A10") (pintype "bidirectional"))
    )
    (net (code "609") (name "unconnected-(U$72A-XDMA_EVENT_INTR1|TCLKIN|CLKOUT2|TIMER7|PR1_PRU0_PRU_R31_16|EMU3|GPIO0_20-PadD14)") (class "Default")
      (node (ref "U$72") (pin "D14") (pinfunction "XDMA_EVENT_INTR1|TCLKIN|CLKOUT2|TIMER7|PR1_PRU0_PRU_R31_16|EMU3|GPIO0_20_D14") (pintype "input"))
    )
    (net (code "610") (name "unconnected-(U$72B-AIN0-PadB6)") (class "Default")
      (node (ref "U$72") (pin "B6") (pinfunction "AIN0_B6") (pintype "bidirectional"))
    )
    (net (code "611") (name "unconnected-(U$72B-AIN1-PadC7)") (class "Default")
      (node (ref "U$72") (pin "C7") (pinfunction "AIN1_C7") (pintype "bidirectional"))
    )
    (net (code "612") (name "unconnected-(U$72B-AIN2-PadB7)") (class "Default")
      (node (ref "U$72") (pin "B7") (pinfunction "AIN2_B7") (pintype "bidirectional"))
    )
    (net (code "613") (name "unconnected-(U$72B-AIN3-PadA7)") (class "Default")
      (node (ref "U$72") (pin "A7") (pinfunction "AIN3_A7") (pintype "bidirectional"))
    )
    (net (code "614") (name "unconnected-(U$72B-AIN4-PadC8)") (class "Default")
      (node (ref "U$72") (pin "C8") (pinfunction "AIN4_C8") (pintype "bidirectional"))
    )
    (net (code "615") (name "unconnected-(U$72B-AIN5-PadB8)") (class "Default")
      (node (ref "U$72") (pin "B8") (pinfunction "AIN5_B8") (pintype "bidirectional"))
    )
    (net (code "616") (name "unconnected-(U$72B-AIN6-PadA8)") (class "Default")
      (node (ref "U$72") (pin "A8") (pinfunction "AIN6_A8") (pintype "bidirectional"))
    )
    (net (code "617") (name "unconnected-(U$72B-GPMC_A7|GMII2_RXCLK|RGMII2_RCLK|MMC2_DAT5|GPMC_A23|PR1_MII1_RXD1|EQEP1_STROBE|GPIO1_23-PadT15)") (class "Default")
      (node (ref "U$72") (pin "T15") (pinfunction "GPMC_A7|GMII2_RXCLK|RGMII2_RCLK|MMC2_DAT5|GPMC_A23|PR1_MII1_RXD1|EQEP1_STROBE|GPIO1_23_T15") (pintype "output"))
    )
    (net (code "618") (name "unconnected-(U$72B-GPMC_A8|GMII2_RXD3|RGMII2_RD3|MMC2_DAT6|GPMC_A24|PR1_MII1_RXD0|MCASP0_ACLKX|GPIO1_24-PadV16)") (class "Default")
      (node (ref "U$72") (pin "V16") (pinfunction "GPMC_A8|GMII2_RXD3|RGMII2_RD3|MMC2_DAT6|GPMC_A24|PR1_MII1_RXD0|MCASP0_ACLKX|GPIO1_24_V16") (pintype "output"))
    )
    (net (code "619") (name "unconnected-(U$72B-GPMC_A9|GMII2_RXD2|RGMII2_RD2|MMC2_DAT7|GPMC_A25|PR1_MII_MR1_CLK|MCASP0_FSX|GPIO1_25-PadU16)") (class "Default")
      (node (ref "U$72") (pin "U16") (pinfunction "GPMC_A9|GMII2_RXD2|RGMII2_RD2|MMC2_DAT7|GPMC_A25|PR1_MII_MR1_CLK|MCASP0_FSX|GPIO1_25_U16") (pintype "output"))
    )
    (net (code "620") (name "unconnected-(U$72B-GPMC_A10|GMII2_RXD1|RGMII2_RD1|RMII2_RXD1|GPMC_A26|PR1_MII1_CRS|MCASP0_AXR0|GPIO1_26-PadT16)") (class "Default")
      (node (ref "U$72") (pin "T16") (pinfunction "GPMC_A10|GMII2_RXD1|RGMII2_RD1|RMII2_RXD1|GPMC_A26|PR1_MII1_CRS|MCASP0_AXR0|GPIO1_26_T16") (pintype "output"))
    )
    (net (code "621") (name "unconnected-(U$72B-GPMC_AD0|MMC1_DAT0||||||GPIO1_0-PadU7)") (class "Default")
      (node (ref "U$72") (pin "U7") (pinfunction "GPMC_AD0|MMC1_DAT0||||||GPIO1_0_U7") (pintype "bidirectional"))
    )
    (net (code "622") (name "unconnected-(U$72B-GPMC_AD6|MMC1_DAT6||||||GPIO1_6-PadR9)") (class "Default")
      (node (ref "U$72") (pin "R9") (pinfunction "GPMC_AD6|MMC1_DAT6||||||GPIO1_6_R9") (pintype "bidirectional"))
    )
    (net (code "623") (name "unconnected-(U$72B-GPMC_AD7|MMC1_DAT7||||||GPIO1_7-PadT9)") (class "Default")
      (node (ref "U$72") (pin "T9") (pinfunction "GPMC_AD7|MMC1_DAT7||||||GPIO1_7_T9") (pintype "bidirectional"))
    )
    (net (code "624") (name "unconnected-(U$72B-GPMC_ADVN_ALE|TIMER4|GPIO2_2-PadR7)") (class "Default")
      (node (ref "U$72") (pin "R7") (pinfunction "GPMC_ADVN_ALE|TIMER4|GPIO2_2_R7") (pintype "output"))
    )
    (net (code "625") (name "unconnected-(U$72B-GPMC_BE0N_CLE|TIMER5|GPIO2_5-PadT6)") (class "Default")
      (node (ref "U$72") (pin "T6") (pinfunction "GPMC_BE0N_CLE|TIMER5|GPIO2_5_T6") (pintype "output"))
    )
    (net (code "626") (name "unconnected-(U$72B-GPMC_OEN_REN|TIMER7|EMU4|GPIO2_3-PadT7)") (class "Default")
      (node (ref "U$72") (pin "T7") (pinfunction "GPMC_OEN_REN|TIMER7|EMU4|GPIO2_3_T7") (pintype "output"))
    )
    (net (code "627") (name "unconnected-(U$72B-GPMC_WAIT0|GM112_CRS|GPMC_CSN4|RMII2_CRS_DV|MMC1_SDCD|PR1_MII1_RXDV|UART4_RXD|GPIO0_30-PadT17)") (class "Default")
      (node (ref "U$72") (pin "T17") (pinfunction "GPMC_WAIT0|GM112_CRS|GPMC_CSN4|RMII2_CRS_DV|MMC1_SDCD|PR1_MII1_RXDV|UART4_RXD|GPIO0_30_T17") (pintype "input"))
    )
    (net (code "628") (name "unconnected-(U$72B-GPMC_WEN|TIMER6|GPIO2_4-PadU6)") (class "Default")
      (node (ref "U$72") (pin "U6") (pinfunction "GPMC_WEN|TIMER6|GPIO2_4_U6") (pintype "output"))
    )
    (net (code "629") (name "unconnected-(U$72B-GPMC_WPN|GMII2_RXERR|GPMC_CSN5|RMII2_RXERR|MMC2_SDCD|PR1_MDIO_MDCLK|UART4_TXD|GPIO0_31-PadU17)") (class "Default")
      (node (ref "U$72") (pin "U17") (pinfunction "GPMC_WPN|GMII2_RXERR|GPMC_CSN5|RMII2_RXERR|MMC2_SDCD|PR1_MDIO_MDCLK|UART4_TXD|GPIO0_31_U17") (pintype "output"))
    )
    (net (code "630") (name "unconnected-(U$72C-GMII1_RXCLK|UART2_TXD|RGMII1_RCLK|MMC0_DAT6|MMC1_DAT1|UART1_DSRN|MCASP0_FSX|GPIO3_10-PadL18)") (class "Default")
      (node (ref "U$72") (pin "L18") (pinfunction "GMII1_RXCLK|UART2_TXD|RGMII1_RCLK|MMC0_DAT6|MMC1_DAT1|UART1_DSRN|MCASP0_FSX|GPIO3_10_L18") (pintype "input"))
    )
    (net (code "631") (name "unconnected-(U$72C-GMII1_RXD0|RMII1_RXD0|RGMII1_RD0|MCASP1_AHCLKX|MCASP1_AHCLKR|MCASP1_ACLKR|MCASP0_AXR3|GPIO2_21-PadM16)") (class "Default")
      (node (ref "U$72") (pin "M16") (pinfunction "GMII1_RXD0|RMII1_RXD0|RGMII1_RD0|MCASP1_AHCLKX|MCASP1_AHCLKR|MCASP1_ACLKR|MCASP0_AXR3|GPIO2_21_M16") (pintype "input"))
    )
    (net (code "632") (name "unconnected-(U$72C-GMII1_RXD1|RMII1_RXD1|RGMII1_RD1|MCASP1_AXR3|MCASP1_FSR|EQEP0_STROBE|MMC2_CLK|GPIO2_20-PadL15)") (class "Default")
      (node (ref "U$72") (pin "L15") (pinfunction "GMII1_RXD1|RMII1_RXD1|RGMII1_RD1|MCASP1_AXR3|MCASP1_FSR|EQEP0_STROBE|MMC2_CLK|GPIO2_20_L15") (pintype "input"))
    )
    (net (code "633") (name "unconnected-(U$72C-GMII1_RXD2|UART3_TXD|RGMII1_RD2|MMC0_DAT4|MMC1_DAT3|UART1_RIN|MCASP0_AXR1|GPIO2_19-PadL16)") (class "Default")
      (node (ref "U$72") (pin "L16") (pinfunction "GMII1_RXD2|UART3_TXD|RGMII1_RD2|MMC0_DAT4|MMC1_DAT3|UART1_RIN|MCASP0_AXR1|GPIO2_19_L16") (pintype "input"))
    )
    (net (code "634") (name "unconnected-(U$72C-GMII1_RXD3|UART3_RXD|RGMII1_RD3|MMC0_DAT5|MMC1_DAT2|UART1_DTRN|MCASP0_AXR0|GPIO2_18-PadL17)") (class "Default")
      (node (ref "U$72") (pin "L17") (pinfunction "GMII1_RXD3|UART3_RXD|RGMII1_RD3|MMC0_DAT5|MMC1_DAT2|UART1_DTRN|MCASP0_AXR0|GPIO2_18_L17") (pintype "input"))
    )
    (net (code "635") (name "unconnected-(U$72C-GMII1_TXCLK|UART2_RXD|RGMII1_TCLK|MMC0_DAT7|MMC1_DAT0|UART1_DCDN|MCASP0_ACLKX|GPIO3_9-PadK18)") (class "Default")
      (node (ref "U$72") (pin "K18") (pinfunction "GMII1_TXCLK|UART2_RXD|RGMII1_TCLK|MMC0_DAT7|MMC1_DAT0|UART1_DCDN|MCASP0_ACLKX|GPIO3_9_K18") (pintype "input"))
    )
    (net (code "636") (name "unconnected-(U$72C-GMII1_TXD0|RMII1_TXD0|RGMII1_TD0|MCASP1_AXR2|MCASP1_ACLKR|EQEP0B_IN|MMC1_CLK|GPIO0_28-PadK17)") (class "Default")
      (node (ref "U$72") (pin "K17") (pinfunction "GMII1_TXD0|RMII1_TXD0|RGMII1_TD0|MCASP1_AXR2|MCASP1_ACLKR|EQEP0B_IN|MMC1_CLK|GPIO0_28_K17") (pintype "output"))
    )
    (net (code "637") (name "unconnected-(U$72C-GMII1_TXD1|RMII1_TXD1|RGMII1_TD1|MCASP1_FSR|MCASP1_AXR1|EQEP0A_IN|MMC1_CMD|GPIO0_21-PadK16)") (class "Default")
      (node (ref "U$72") (pin "K16") (pinfunction "GMII1_TXD1|RMII1_TXD1|RGMII1_TD1|MCASP1_FSR|MCASP1_AXR1|EQEP0A_IN|MMC1_CMD|GPIO0_21_K16") (pintype "output"))
    )
    (net (code "638") (name "unconnected-(U$72C-GMII1_TXD2|DCAN0_RX|RGMII1_TD2|UART4_TXD|MCASP1_AXR0|MMC2_DAT2|MCASP0_AHCLKX|GPIO0_17-PadK15)") (class "Default")
      (node (ref "U$72") (pin "K15") (pinfunction "GMII1_TXD2|DCAN0_RX|RGMII1_TD2|UART4_TXD|MCASP1_AXR0|MMC2_DAT2|MCASP0_AHCLKX|GPIO0_17_K15") (pintype "output"))
    )
    (net (code "639") (name "unconnected-(U$72C-GMII1_TXD3|DCAN0_TX|RGMII1_TD3|UART4_RXD|MCASP1_FSX|MMC2_DAT1|MCASP0_FSR|GPIO0_16-PadJ18)") (class "Default")
      (node (ref "U$72") (pin "J18") (pinfunction "GMII1_TXD3|DCAN0_TX|RGMII1_TD3|UART4_RXD|MCASP1_FSX|MMC2_DAT1|MCASP0_FSR|GPIO0_16_J18") (pintype "output"))
    )
    (net (code "640") (name "unconnected-(U$72C-GMII1_TXEN|RMII1_TXEN|RGMII1_TCTL|TIMER4|MCASP1_AXR0|EQEP0_INDEX|MMC2_CMD|GPIO3_3-PadJ16)") (class "Default")
      (node (ref "U$72") (pin "J16") (pinfunction "GMII1_TXEN|RMII1_TXEN|RGMII1_TCTL|TIMER4|MCASP1_AXR0|EQEP0_INDEX|MMC2_CMD|GPIO3_3_J16") (pintype "input"))
    )
    (net (code "641") (name "unconnected-(U$72C-MCASP0_ACLKR|EQEP0A_IN|MCASP0_AXR2|MCASP1_ACLKX|MMC0_SDWP|PR1_PRU0_PRU_R30_4|PR1_PRU0_PRU_R31_4|GPIO3_18-PadB12)") (class "Default")
      (node (ref "U$72") (pin "B12") (pinfunction "MCASP0_ACLKR|EQEP0A_IN|MCASP0_AXR2|MCASP1_ACLKX|MMC0_SDWP|PR1_PRU0_PRU_R30_4|PR1_PRU0_PRU_R31_4|GPIO3_18_B12") (pintype "bidirectional"))
    )
    (net (code "642") (name "unconnected-(U$72C-MCASP0_AHCLKR|EHRPWM0_SYNCI_O|MCASP0_AXR2|SPI1_CS0|ECAP2_IN_PWM2_OUT|PR1_PRU0_PRU_R30_3|PR1_PRU0_PRU_R31_3|GPIO3_17-PadC12)") (class "Default")
      (node (ref "U$72") (pin "C12") (pinfunction "MCASP0_AHCLKR|EHRPWM0_SYNCI_O|MCASP0_AXR2|SPI1_CS0|ECAP2_IN_PWM2_OUT|PR1_PRU0_PRU_R30_3|PR1_PRU0_PRU_R31_3|GPIO3_17_C12") (pintype "bidirectional"))
    )
    (net (code "643") (name "unconnected-(U$72C-MCASP0_AHCLKX|EQEP0_STROBE|MCASP0_AXR3|MCASP1_AXR1|EMU4|PR1_PRU0_PRU_R30_7|PR1_PRU0_PRU_R31_7|GPIO3_21-PadA14)") (class "Default")
      (node (ref "U$72") (pin "A14") (pinfunction "MCASP0_AHCLKX|EQEP0_STROBE|MCASP0_AXR3|MCASP1_AXR1|EMU4|PR1_PRU0_PRU_R30_7|PR1_PRU0_PRU_R31_7|GPIO3_21_A14") (pintype "bidirectional"))
    )
    (net (code "644") (name "unconnected-(U$72C-MCASP0_FSR|EQEP0B_IN|MCASP0_AXR3|MCASP1_FSX|EMU2|PR1_PRU0_PRU_R30_5|PR1_PRU0_PRU_R31_5|GPIO3_19-PadC13)") (class "Default")
      (node (ref "U$72") (pin "C13") (pinfunction "MCASP0_FSR|EQEP0B_IN|MCASP0_AXR3|MCASP1_FSX|EMU2|PR1_PRU0_PRU_R30_5|PR1_PRU0_PRU_R31_5|GPIO3_19_C13") (pintype "bidirectional"))
    )
    (net (code "645") (name "unconnected-(U$72C-MDIO_CLK|TIMER5|UART5_TXD|UART3_RTSN|MMC0_SDWP|MMC1_CLK|MMC2_CLK|GPIO0_1-PadM18)") (class "Default")
      (node (ref "U$72") (pin "M18") (pinfunction "MDIO_CLK|TIMER5|UART5_TXD|UART3_RTSN|MMC0_SDWP|MMC1_CLK|MMC2_CLK|GPIO0_1_M18") (pintype "bidirectional"))
    )
    (net (code "646") (name "unconnected-(U$72C-MDIO_DATA|TIMER6|UART5_RXD|UART3_CTSN|MMC0_SDCD|MMC1_CMD|MMC2_CMD|GPIO0_0-PadM17)") (class "Default")
      (node (ref "U$72") (pin "M17") (pinfunction "MDIO_DATA|TIMER6|UART5_RXD|UART3_CTSN|MMC0_SDCD|MMC1_CMD|MMC2_CMD|GPIO0_0_M17") (pintype "bidirectional"))
    )
    (net (code "647") (name "unconnected-(U$72C-RESERVED-PadA3)") (class "Default")
      (node (ref "U$72") (pin "A3") (pinfunction "RESERVED_A3") (pintype "output"))
    )
    (net (code "648") (name "unconnected-(U$72C-RMII1_REFCLK|XDMA_EVENT_INTR2|SPI1_CS0|UART5_TXD|MCASP1_AXR3|MMC0_POW|MCASP1_AHCLKX|GPIO0_29-PadH18)") (class "Default")
      (node (ref "U$72") (pin "H18") (pinfunction "RMII1_REFCLK|XDMA_EVENT_INTR2|SPI1_CS0|UART5_TXD|MCASP1_AXR3|MMC0_POW|MCASP1_AHCLKX|GPIO0_29_H18") (pintype "bidirectional"))
    )
    (net (code "649") (name "unconnected-(U$72C-RTC_KALDO_ENN-PadB4)") (class "Default")
      (node (ref "U$72") (pin "B4") (pinfunction "RTC_KALDO_ENN_B4") (pintype "input"))
    )
    (net (code "650") (name "unconnected-(U$72C-TCK-PadA12)") (class "Default")
      (node (ref "U$72") (pin "A12") (pinfunction "TCK_A12") (pintype "input"))
    )
    (net (code "651") (name "unconnected-(U$72C-TDI-PadB11)") (class "Default")
      (node (ref "U$72") (pin "B11") (pinfunction "TDI_B11") (pintype "input"))
    )
    (net (code "652") (name "unconnected-(U$72C-TDO-PadA11)") (class "Default")
      (node (ref "U$72") (pin "A11") (pinfunction "TDO_A11") (pintype "output"))
    )
    (net (code "653") (name "unconnected-(U$72C-TMS-PadC11)") (class "Default")
      (node (ref "U$72") (pin "C11") (pinfunction "TMS_C11") (pintype "input"))
    )
    (net (code "654") (name "unconnected-(U$72C-TRSTN-PadB10)") (class "Default")
      (node (ref "U$72") (pin "B10") (pinfunction "TRSTN_B10") (pintype "input"))
    )
    (net (code "655") (name "unconnected-(U$72C-USB0_CE-PadM15)") (class "Default")
      (node (ref "U$72") (pin "M15") (pinfunction "USB0_CE_M15") (pintype "bidirectional"))
    )
    (net (code "656") (name "unconnected-(U$72C-USB0_DRVVBUS-PadF16)") (class "Default")
      (node (ref "U$72") (pin "F16") (pinfunction "USB0_DRVVBUS_F16") (pintype "output"))
    )
    (net (code "657") (name "unconnected-(U$72C-USB0_ID-PadP16)") (class "Default")
      (node (ref "U$72") (pin "P16") (pinfunction "USB0_ID_P16") (pintype "bidirectional"))
    )
    (net (code "658") (name "unconnected-(U$72C-USB1_CE-PadP18)") (class "Default")
      (node (ref "U$72") (pin "P18") (pinfunction "USB1_CE_P18") (pintype "bidirectional"))
    )
    (net (code "659") (name "unconnected-(U8-A1-Pad1)") (class "Default")
      (node (ref "U8") (pin "1") (pinfunction "A1_1") (pintype "bidirectional"))
    )
    (net (code "660") (name "unconnected-(U8-A2-Pad3)") (class "Default")
      (node (ref "U8") (pin "3") (pinfunction "A2_3") (pintype "bidirectional"))
    )
    (net (code "661") (name "unconnected-(U8-A5-Pad6)") (class "Default")
      (node (ref "U8") (pin "6") (pinfunction "A5_6") (pintype "bidirectional"))
    )
    (net (code "662") (name "unconnected-(U8-A8-Pad9)") (class "Default")
      (node (ref "U8") (pin "9") (pinfunction "A8_9") (pintype "bidirectional"))
    )
    (net (code "663") (name "unconnected-(U8-B1-Pad20)") (class "Default")
      (node (ref "U8") (pin "20") (pinfunction "B1_20") (pintype "bidirectional"))
    )
    (net (code "664") (name "unconnected-(U8-B2-Pad18)") (class "Default")
      (node (ref "U8") (pin "18") (pinfunction "B2_18") (pintype "bidirectional"))
    )
    (net (code "665") (name "unconnected-(U8-B5-Pad15)") (class "Default")
      (node (ref "U8") (pin "15") (pinfunction "B5_15") (pintype "bidirectional"))
    )
    (net (code "666") (name "unconnected-(U8-B8-Pad12)") (class "Default")
      (node (ref "U8") (pin "12") (pinfunction "B8_12") (pintype "bidirectional"))
    )
    (net (code "667") (name "unconnected-(U9-Pad1)") (class "Default")
      (node (ref "U9") (pin "1") (pinfunction "1_1") (pintype "passive"))
    )
    (net (code "668") (name "unconnected-(U12-INT-Pad7)") (class "Default")
      (node (ref "U12") (pin "7") (pinfunction "INT_7") (pintype "bidirectional"))
    )
    (net (code "669") (name "unconnected-(U15-GPIO1-Pad35)") (class "Default")
      (node (ref "U15") (pin "35") (pinfunction "GPIO1_35") (pintype "bidirectional"))
    )
    (net (code "670") (name "unconnected-(U15-GPIO2-Pad34)") (class "Default")
      (node (ref "U15") (pin "34") (pinfunction "GPIO2_34") (pintype "bidirectional"))
    )
    (net (code "671") (name "unconnected-(U15-HPLCOM-Pad19)") (class "Default")
      (node (ref "U15") (pin "19") (pinfunction "HPLCOM_19") (pintype "bidirectional"))
    )
    (net (code "672") (name "unconnected-(U15-HPRCOM-Pad22)") (class "Default")
      (node (ref "U15") (pin "22") (pinfunction "HPRCOM_22") (pintype "bidirectional"))
    )
    (net (code "673") (name "unconnected-(U15-HPROUT-Pad23)") (class "Default")
      (node (ref "U15") (pin "23") (pinfunction "HPROUT_23") (pintype "bidirectional"))
    )
    (net (code "674") (name "unconnected-(U15-LEFT_LOM-Pad30)") (class "Default")
      (node (ref "U15") (pin "30") (pinfunction "LEFT_LOM_30") (pintype "bidirectional"))
    )
    (net (code "675") (name "unconnected-(U15-LEFT_LOP-Pad29)") (class "Default")
      (node (ref "U15") (pin "29") (pinfunction "LEFT_LOP_29") (pintype "bidirectional"))
    )
    (net (code "676") (name "unconnected-(U15-LINE1LP-Pad3)") (class "Default")
      (node (ref "U15") (pin "3") (pinfunction "LINE1LP_3") (pintype "bidirectional"))
    )
    (net (code "677") (name "unconnected-(U15-LINE1RP-Pad5)") (class "Default")
      (node (ref "U15") (pin "5") (pinfunction "LINE1RP_5") (pintype "bidirectional"))
    )
    (net (code "678") (name "unconnected-(U15-LINE2LM-Pad8)") (class "Default")
      (node (ref "U15") (pin "8") (pinfunction "LINE2LM_8") (pintype "bidirectional"))
    )
    (net (code "679") (name "unconnected-(U15-LINE2LP-Pad7)") (class "Default")
      (node (ref "U15") (pin "7") (pinfunction "LINE2LP_7") (pintype "bidirectional"))
    )
    (net (code "680") (name "unconnected-(U15-LINE2RM-Pad10)") (class "Default")
      (node (ref "U15") (pin "10") (pinfunction "LINE2RM_10") (pintype "bidirectional"))
    )
    (net (code "681") (name "unconnected-(U15-LINE2RP-Pad9)") (class "Default")
      (node (ref "U15") (pin "9") (pinfunction "LINE2RP_9") (pintype "bidirectional"))
    )
    (net (code "682") (name "unconnected-(U15-MFP2-Pad47)") (class "Default")
      (node (ref "U15") (pin "47") (pinfunction "MFP2_47") (pintype "bidirectional"))
    )
    (net (code "683") (name "unconnected-(U15-MFP3-Pad48)") (class "Default")
      (node (ref "U15") (pin "48") (pinfunction "MFP3_48") (pintype "bidirectional"))
    )
    (net (code "684") (name "unconnected-(U15-MIC3R-Pad14)") (class "Default")
      (node (ref "U15") (pin "14") (pinfunction "MIC3R_14") (pintype "bidirectional"))
    )
    (net (code "685") (name "unconnected-(U15-MONO_LOM-Pad28)") (class "Default")
      (node (ref "U15") (pin "28") (pinfunction "MONO_LOM_28") (pintype "bidirectional"))
    )
    (net (code "686") (name "unconnected-(U15-MONO_LOP-Pad27)") (class "Default")
      (node (ref "U15") (pin "27") (pinfunction "MONO_LOP_27") (pintype "bidirectional"))
    )
    (net (code "687") (name "unconnected-(U15-RIGHT_LOM-Pad32)") (class "Default")
      (node (ref "U15") (pin "32") (pinfunction "RIGHT_LOM_32") (pintype "bidirectional"))
    )
    (net (code "688") (name "unconnected-(U15-RIGHT_LOP-Pad31)") (class "Default")
      (node (ref "U15") (pin "31") (pinfunction "RIGHT_LOP_31") (pintype "bidirectional"))
    )
    (net (code "689") (name "unconnected-(U18-NC-Pad8)") (class "Default")
      (node (ref "U18") (pin "8") (pinfunction "NC_8") (pintype "no_connect"))
    )
    (net (code "690") (name "unconnected-(U18-NC-Pad9)") (class "Default")
      (node (ref "U18") (pin "9") (pinfunction "NC_9") (pintype "no_connect"))
    )
    (net (code "691") (name "unconnected-(U18-NC-Pad20)") (class "Default")
      (node (ref "U18") (pin "20") (pinfunction "NC_20") (pintype "no_connect"))
    )
    (net (code "692") (name "unconnected-(U18-NC-Pad21)") (class "Default")
      (node (ref "U18") (pin "21") (pinfunction "NC_21") (pintype "no_connect"))
    )
    (net (code "693") (name "unconnected-(U18-OCS_N3-Pad19)") (class "Default")
      (node (ref "U18") (pin "19") (pinfunction "OCS_N3_19") (pintype "bidirectional"))
    )
    (net (code "694") (name "unconnected-(U18-PRTPWR3-Pad18)") (class "Default")
      (node (ref "U18") (pin "18") (pinfunction "PRTPWR3_18") (pintype "bidirectional"))
    )
    (net (code "695") (name "unconnected-(U18-TEST_NC-Pad11)") (class "Default")
      (node (ref "U18") (pin "11") (pinfunction "TEST_NC_11") (pintype "no_connect"))
    )
    (net (code "696") (name "unconnected-(U18-USBDM_DN3-Pad6)") (class "Default")
      (node (ref "U18") (pin "6") (pinfunction "USBDM_DN3_6") (pintype "bidirectional"))
    )
    (net (code "697") (name "unconnected-(U18-USBDP_DN3-Pad7)") (class "Default")
      (node (ref "U18") (pin "7") (pinfunction "USBDP_DN3_7") (pintype "bidirectional"))
    )
    (net (code "698") (name "unconnected-(U19A-I3-Pad6)") (class "Default")
      (node (ref "U19") (pin "6") (pinfunction "I3_6") (pintype "input"))
    )
    (net (code "699") (name "unconnected-(U20-A1-Pad1)") (class "Default")
      (node (ref "U20") (pin "1") (pinfunction "A1_1") (pintype "bidirectional"))
    )
    (net (code "700") (name "unconnected-(U20-A5-Pad6)") (class "Default")
      (node (ref "U20") (pin "6") (pinfunction "A5_6") (pintype "bidirectional"))
    )
    (net (code "701") (name "unconnected-(U20-A8-Pad9)") (class "Default")
      (node (ref "U20") (pin "9") (pinfunction "A8_9") (pintype "bidirectional"))
    )
    (net (code "702") (name "unconnected-(U20-B1-Pad20)") (class "Default")
      (node (ref "U20") (pin "20") (pinfunction "B1_20") (pintype "bidirectional"))
    )
    (net (code "703") (name "unconnected-(U20-B5-Pad15)") (class "Default")
      (node (ref "U20") (pin "15") (pinfunction "B5_15") (pintype "bidirectional"))
    )
    (net (code "704") (name "unconnected-(U20-B8-Pad12)") (class "Default")
      (node (ref "U20") (pin "12") (pinfunction "B8_12") (pintype "bidirectional"))
    )
    (net (code "705") (name "unconnected-(U28-2G4_ANT2_W-Pad18)") (class "Default")
      (node (ref "U28") (pin "18") (pinfunction "2G4_ANT2_W_18") (pintype "bidirectional"))
    )
    (net (code "706") (name "unconnected-(U28-GPIO9-Pad3)") (class "Default")
      (node (ref "U28") (pin "3") (pinfunction "GPIO9_3") (pintype "bidirectional"))
    )
    (net (code "707") (name "unconnected-(U28-GPIO10-Pad4)") (class "Default")
      (node (ref "U28") (pin "4") (pinfunction "GPIO10_4") (pintype "bidirectional"))
    )
    (net (code "708") (name "unconnected-(U28-GPIO11-Pad2)") (class "Default")
      (node (ref "U28") (pin "2") (pinfunction "GPIO11_2") (pintype "bidirectional"))
    )
    (net (code "709") (name "unconnected-(U28-GPIO12-Pad5)") (class "Default")
      (node (ref "U28") (pin "5") (pinfunction "GPIO12_5") (pintype "bidirectional"))
    )
    (net (code "710") (name "unconnected-(U28-GPIO_4-Pad25)") (class "Default")
      (node (ref "U28") (pin "25") (pinfunction "GPIO_4_25") (pintype "bidirectional"))
    )
    (net (code "711") (name "unconnected-(U28-RESERVED1-Pad21)") (class "Default")
      (node (ref "U28") (pin "21") (pinfunction "RESERVED1_21") (pintype "bidirectional"))
    )
    (net (code "712") (name "unconnected-(U28-RESERVED2-Pad22)") (class "Default")
      (node (ref "U28") (pin "22") (pinfunction "RESERVED2_22") (pintype "bidirectional"))
    )
    (net (code "713") (name "unconnected-(U28-RESERVED3-Pad62)") (class "Default")
      (node (ref "U28") (pin "62") (pinfunction "RESERVED3_62") (pintype "bidirectional"))
    )
    (net (code "714") (name "unconnected-(U35-MUX_IN-Pad14)") (class "Default")
      (node (ref "U35") (pin "14") (pinfunction "MUX_IN_14") (pintype "input"))
    )
    (net (code "715") (name "unconnected-(U35-NC-Pad15)") (class "Default")
      (node (ref "U35") (pin "15") (pinfunction "NC_15") (pintype "no_connect"))
    )
    (net (code "716") (name "unconnected-(U35-NC1-Pad17)") (class "Default")
      (node (ref "U35") (pin "17") (pinfunction "NC1_17") (pintype "no_connect"))
    )
    (net (code "717") (name "unconnected-(U35-TS-Pad11)") (class "Default")
      (node (ref "U35") (pin "11") (pinfunction "TS_11") (pintype "input"))
    )
    (net (code "718") (name "unconnected-(U35-USB-Pad12)") (class "Default")
      (node (ref "U35") (pin "12") (pinfunction "USB_12") (pintype "input"))
    )
    (net (code "719") (name "unconnected-(U35-~{PB_IN}-Pad25)") (class "Default")
      (node (ref "U35") (pin "25") (pinfunction "~{PB_IN}_25") (pintype "input"))
    )
    (net (code "720") (name "unconnected-(U35-~{RESET}-Pad44)") (class "Default")
      (node (ref "U35") (pin "44") (pinfunction "~{RESET}_44") (pintype "input"))
    )
    (net (code "721") (name "~{3V_SPI_TS_CS$43}") (class "Default")
      (node (ref "U$66") (pin "3") (pinfunction "~{CS}_3") (pintype "bidirectional"))
      (node (ref "U$67") (pin "46") (pinfunction "1A1_46") (pintype "bidirectional"))
    )
    (net (code "722") (name "~{DDR3_RESET$45}") (class "Default")
      (node (ref "R134") (pin "2") (pinfunction "2_2") (pintype "passive"))
      (node (ref "U$101") (pin "T2") (pinfunction "~{RESET}_T2") (pintype "power_in"))
      (node (ref "U$72") (pin "G2") (pinfunction "DDR_RESETN_G2") (pintype "output"))
    )
    (net (code "723") (name "~{PD$44}") (class "Default")
      (node (ref "IC4") (pin "10") (pinfunction "~{PD}_10") (pintype "bidirectional"))
      (node (ref "R103") (pin "2") (pinfunction "2_2") (pintype "passive"))
    )
  )
)
